# GridSeed.net
KiCad netlist of a schematic drawn in Altium Designer
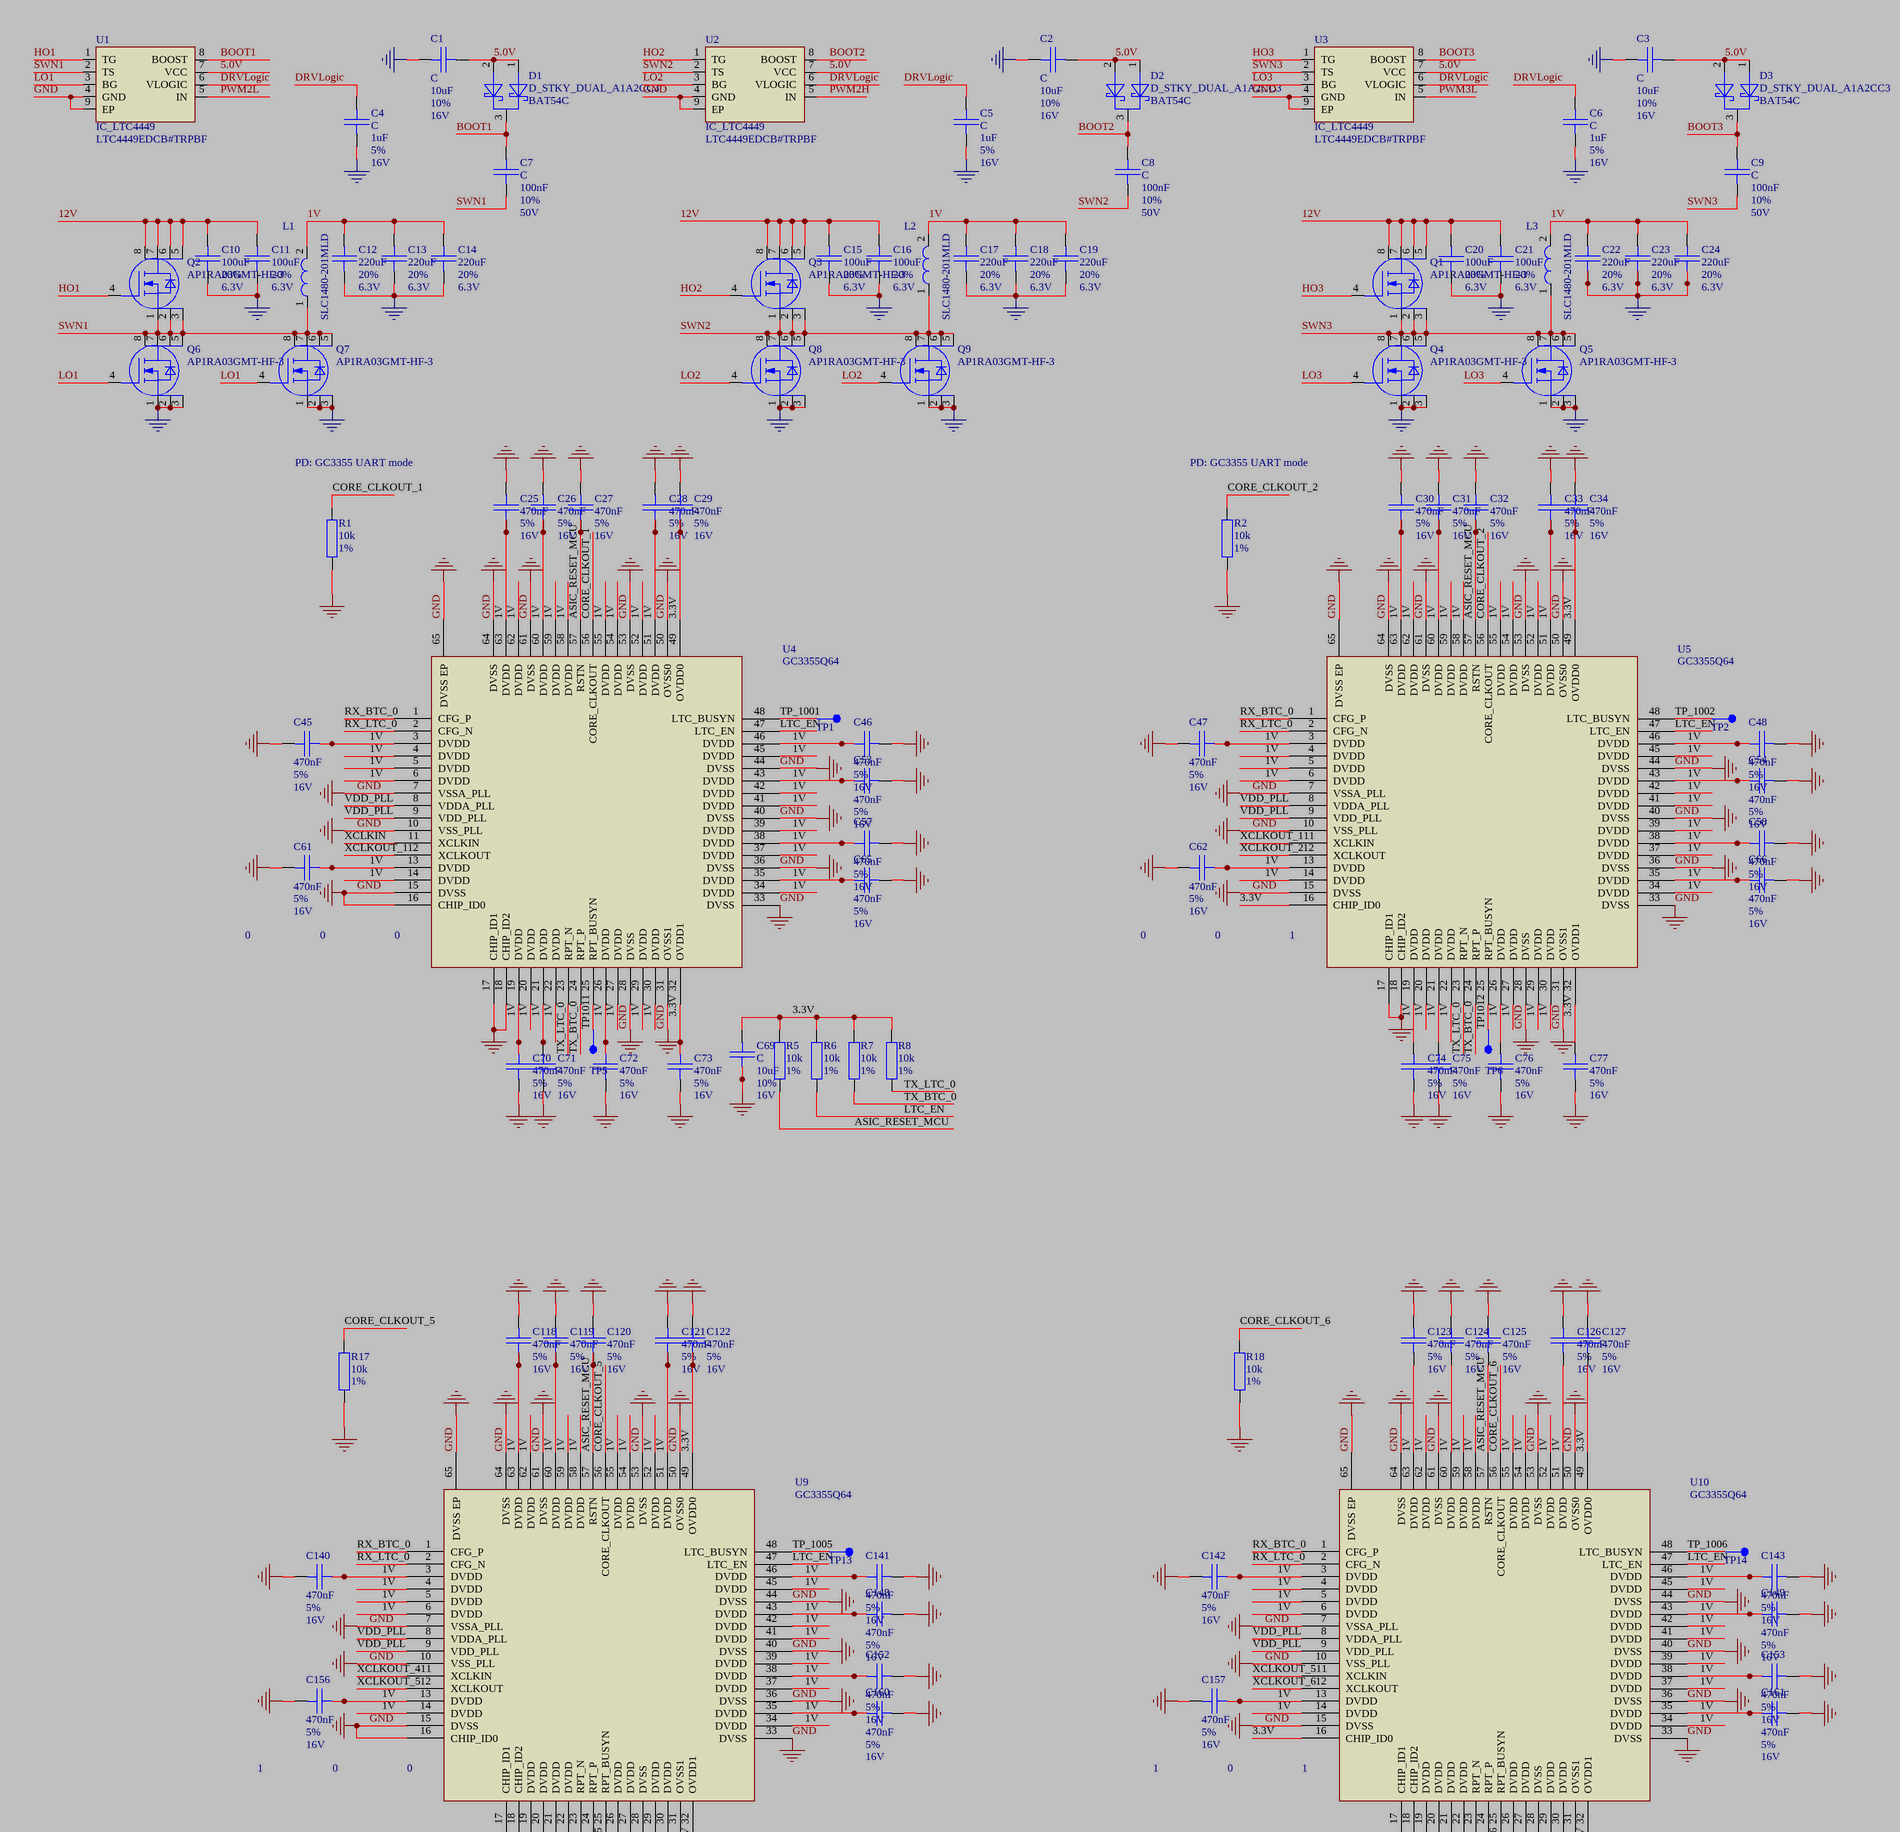
[diagram p0: GridSeed.SchDoc, top left]
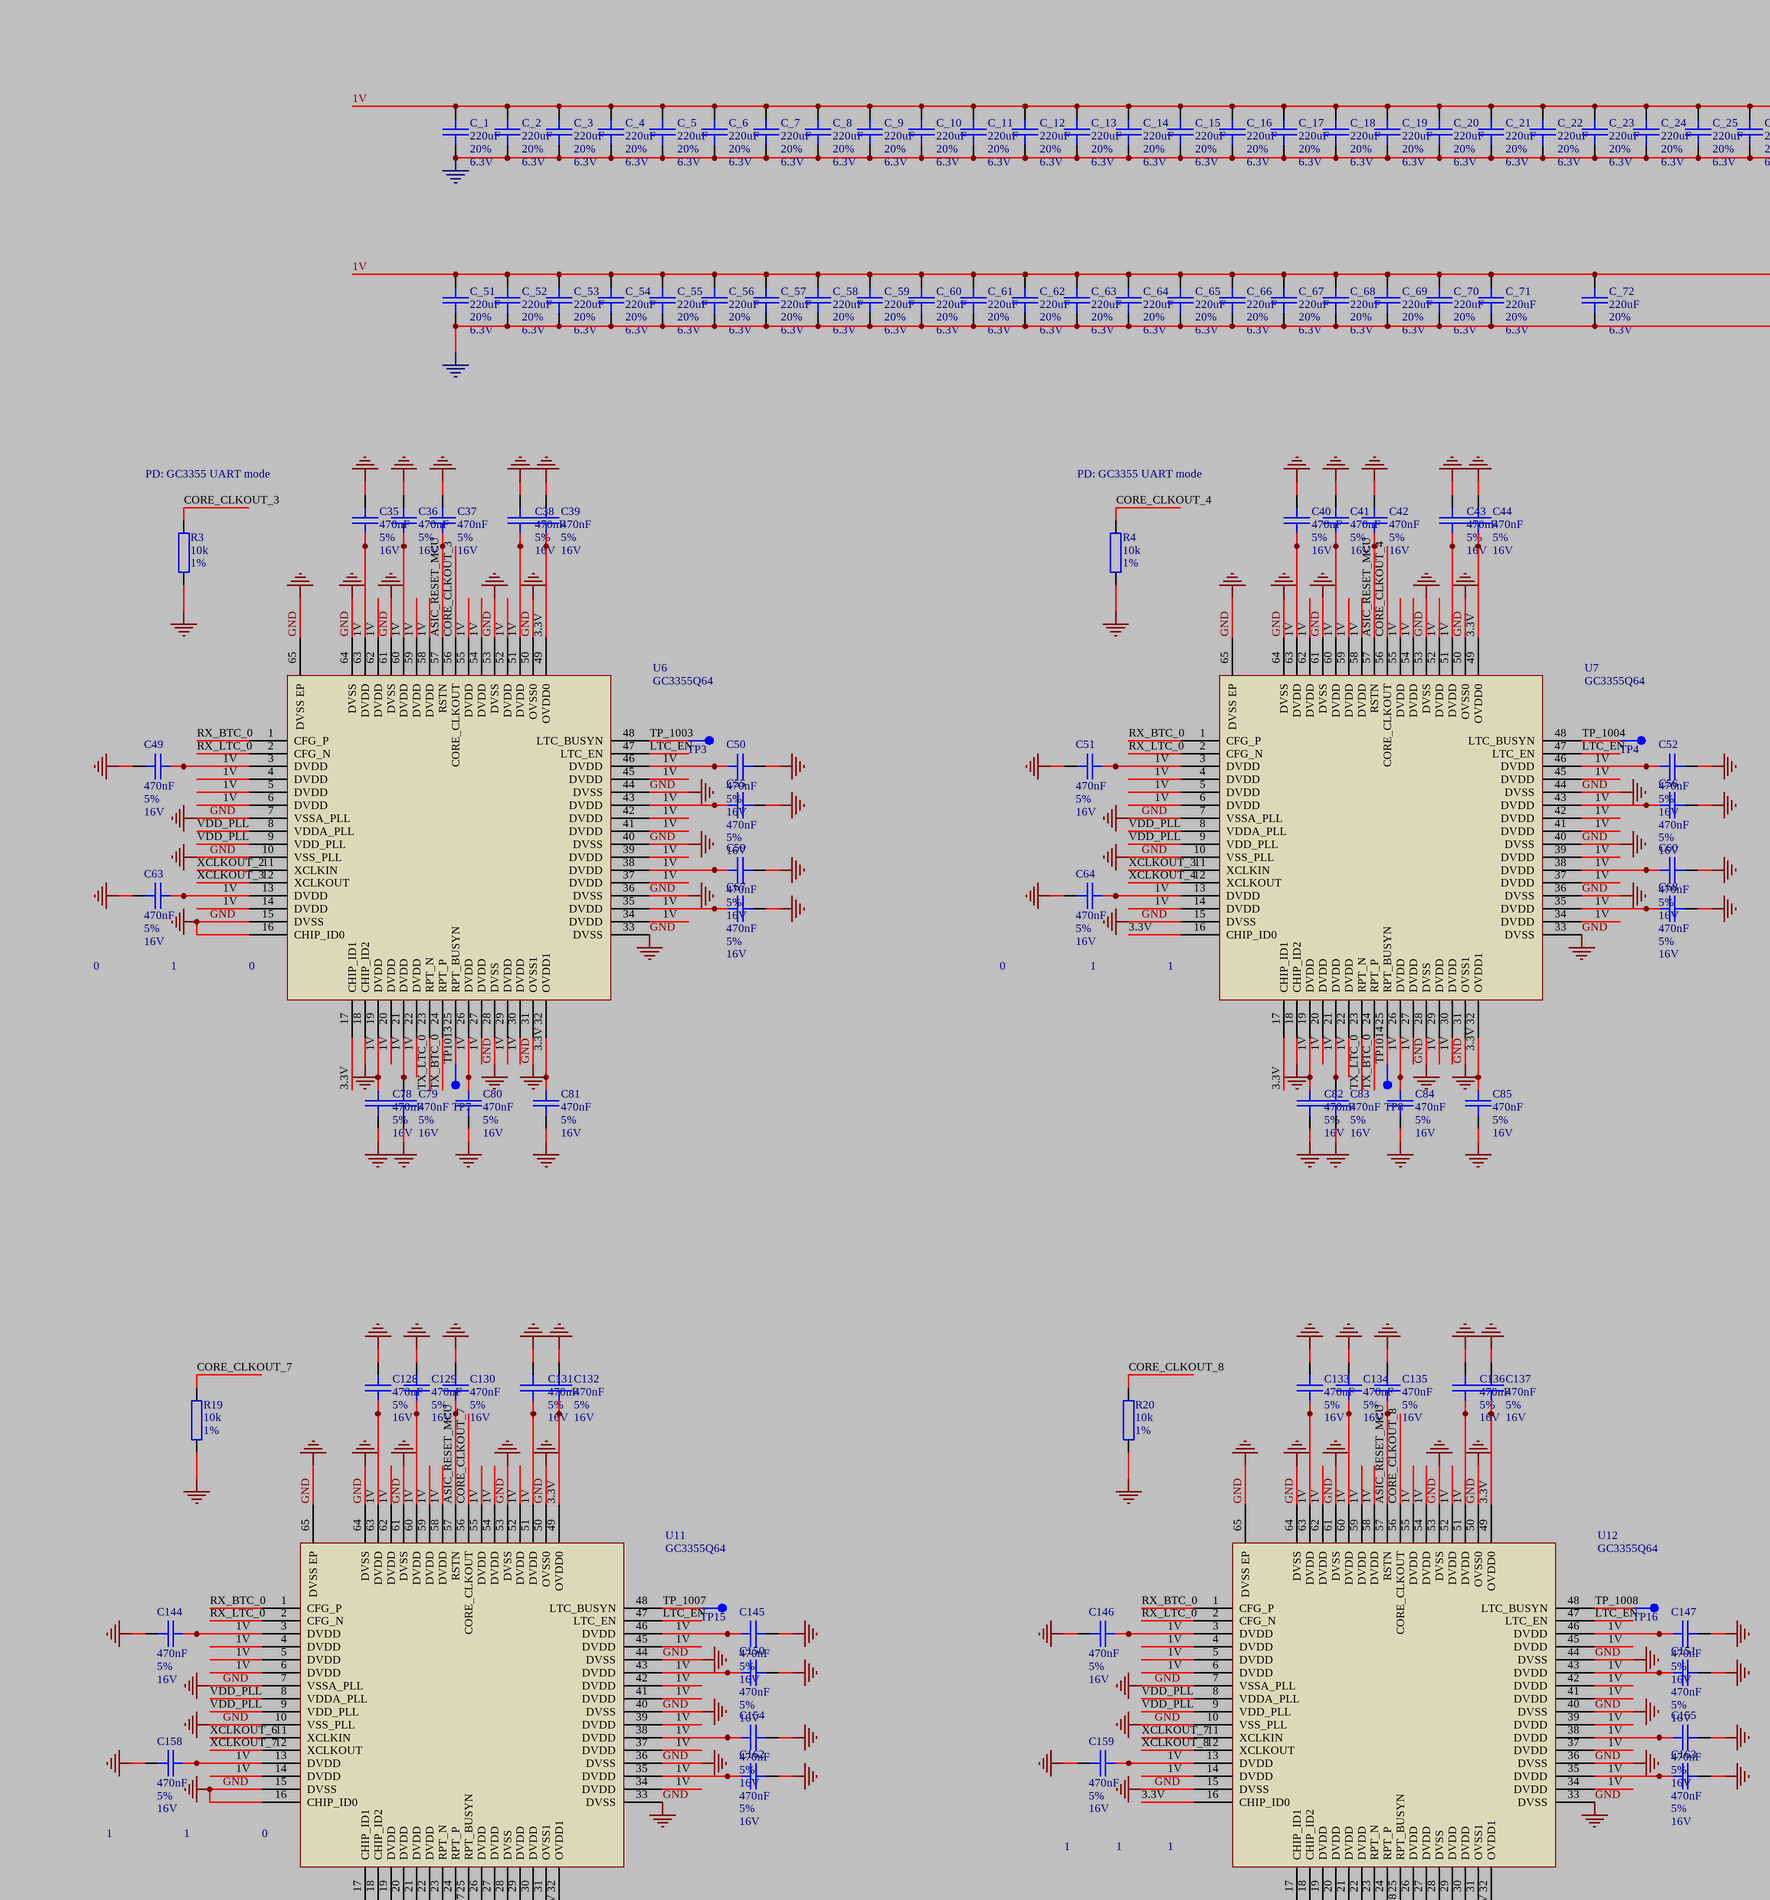
[diagram p1: GridSeed.SchDoc, top middle]
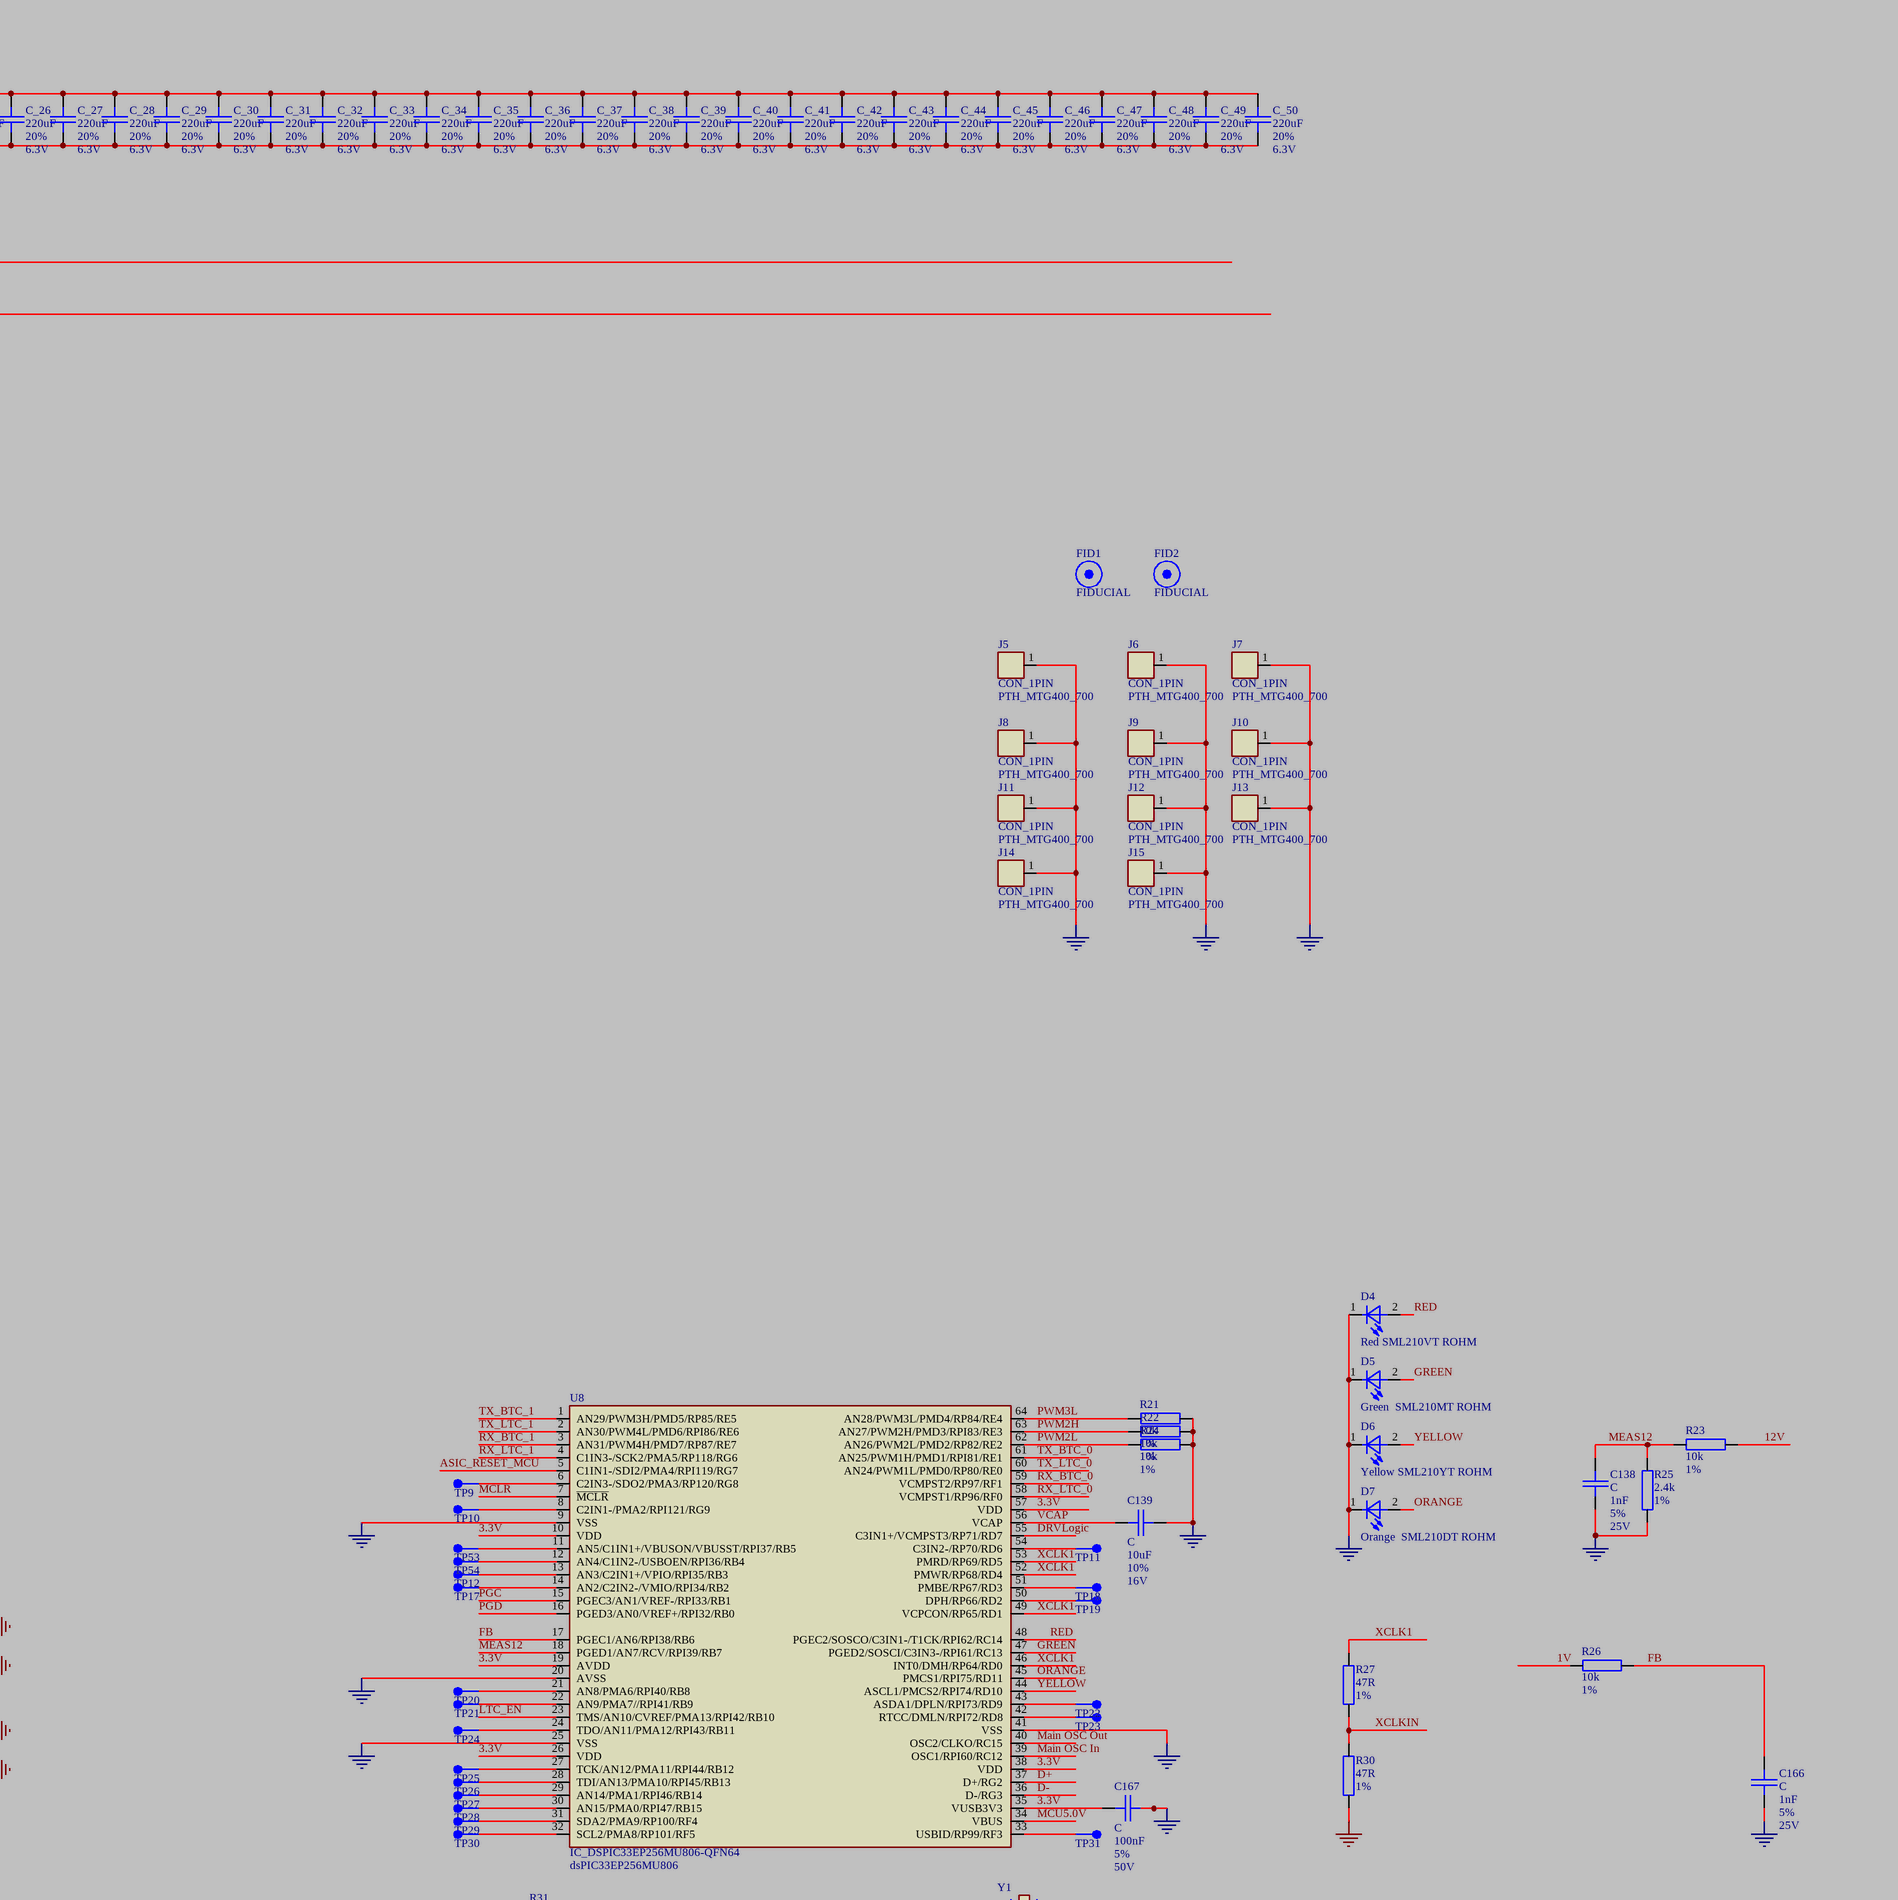
[diagram p2: GridSeed.SchDoc, top right]
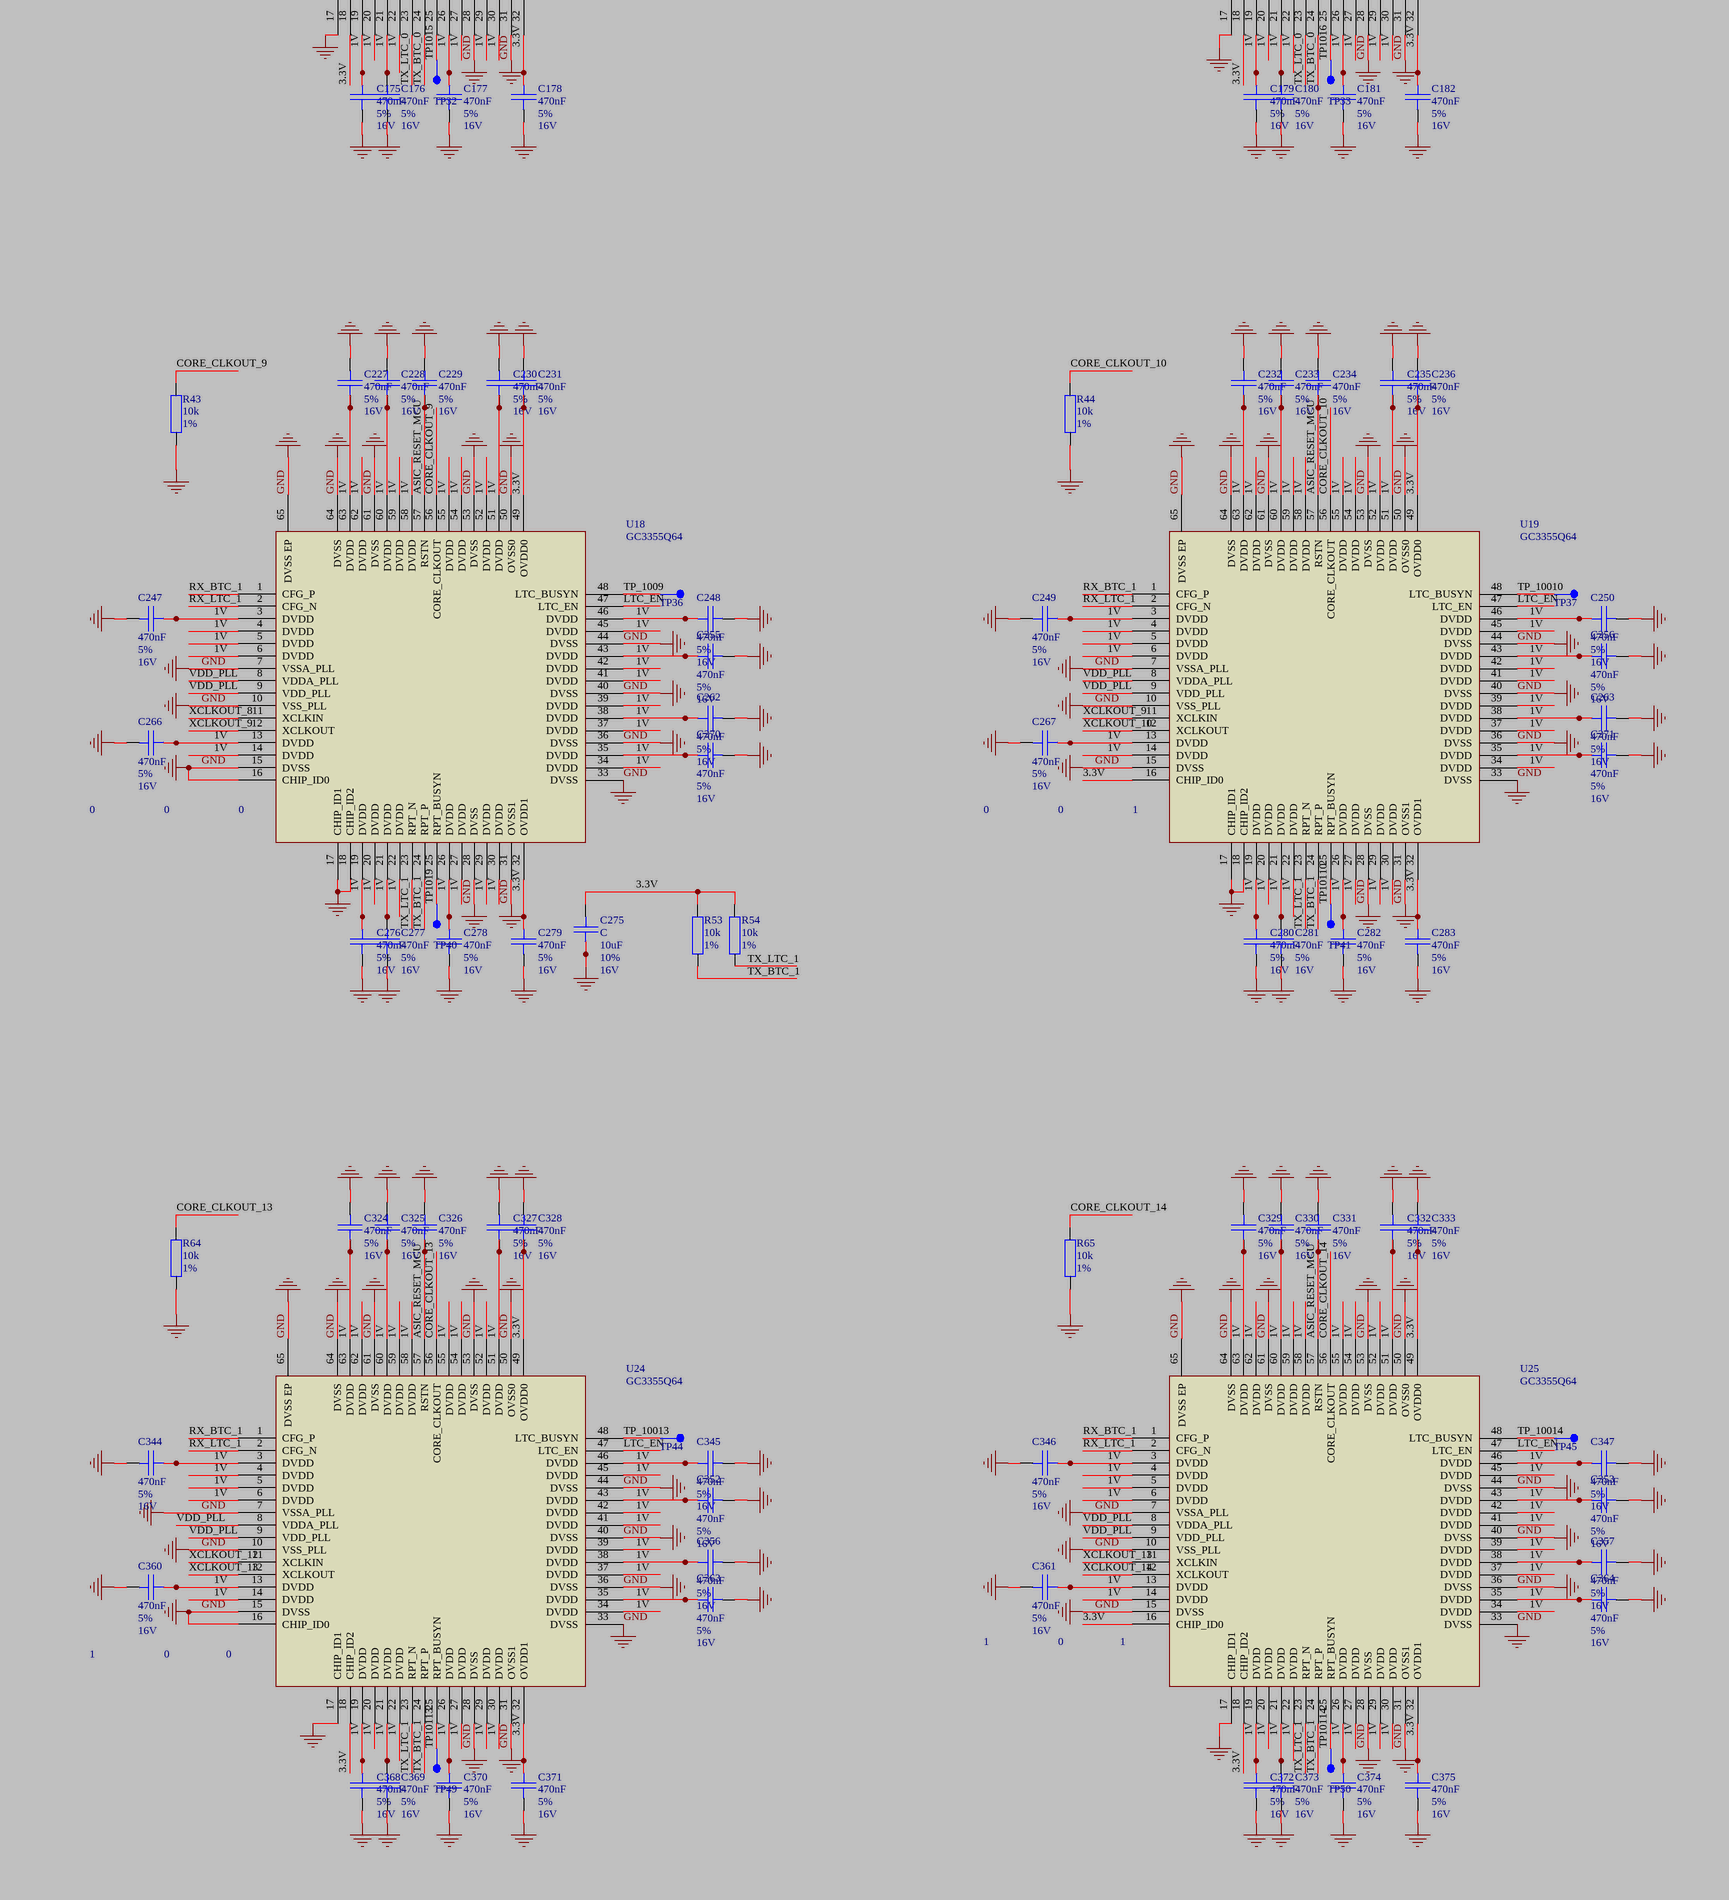
[diagram p3: GridSeed.SchDoc, bottom left]
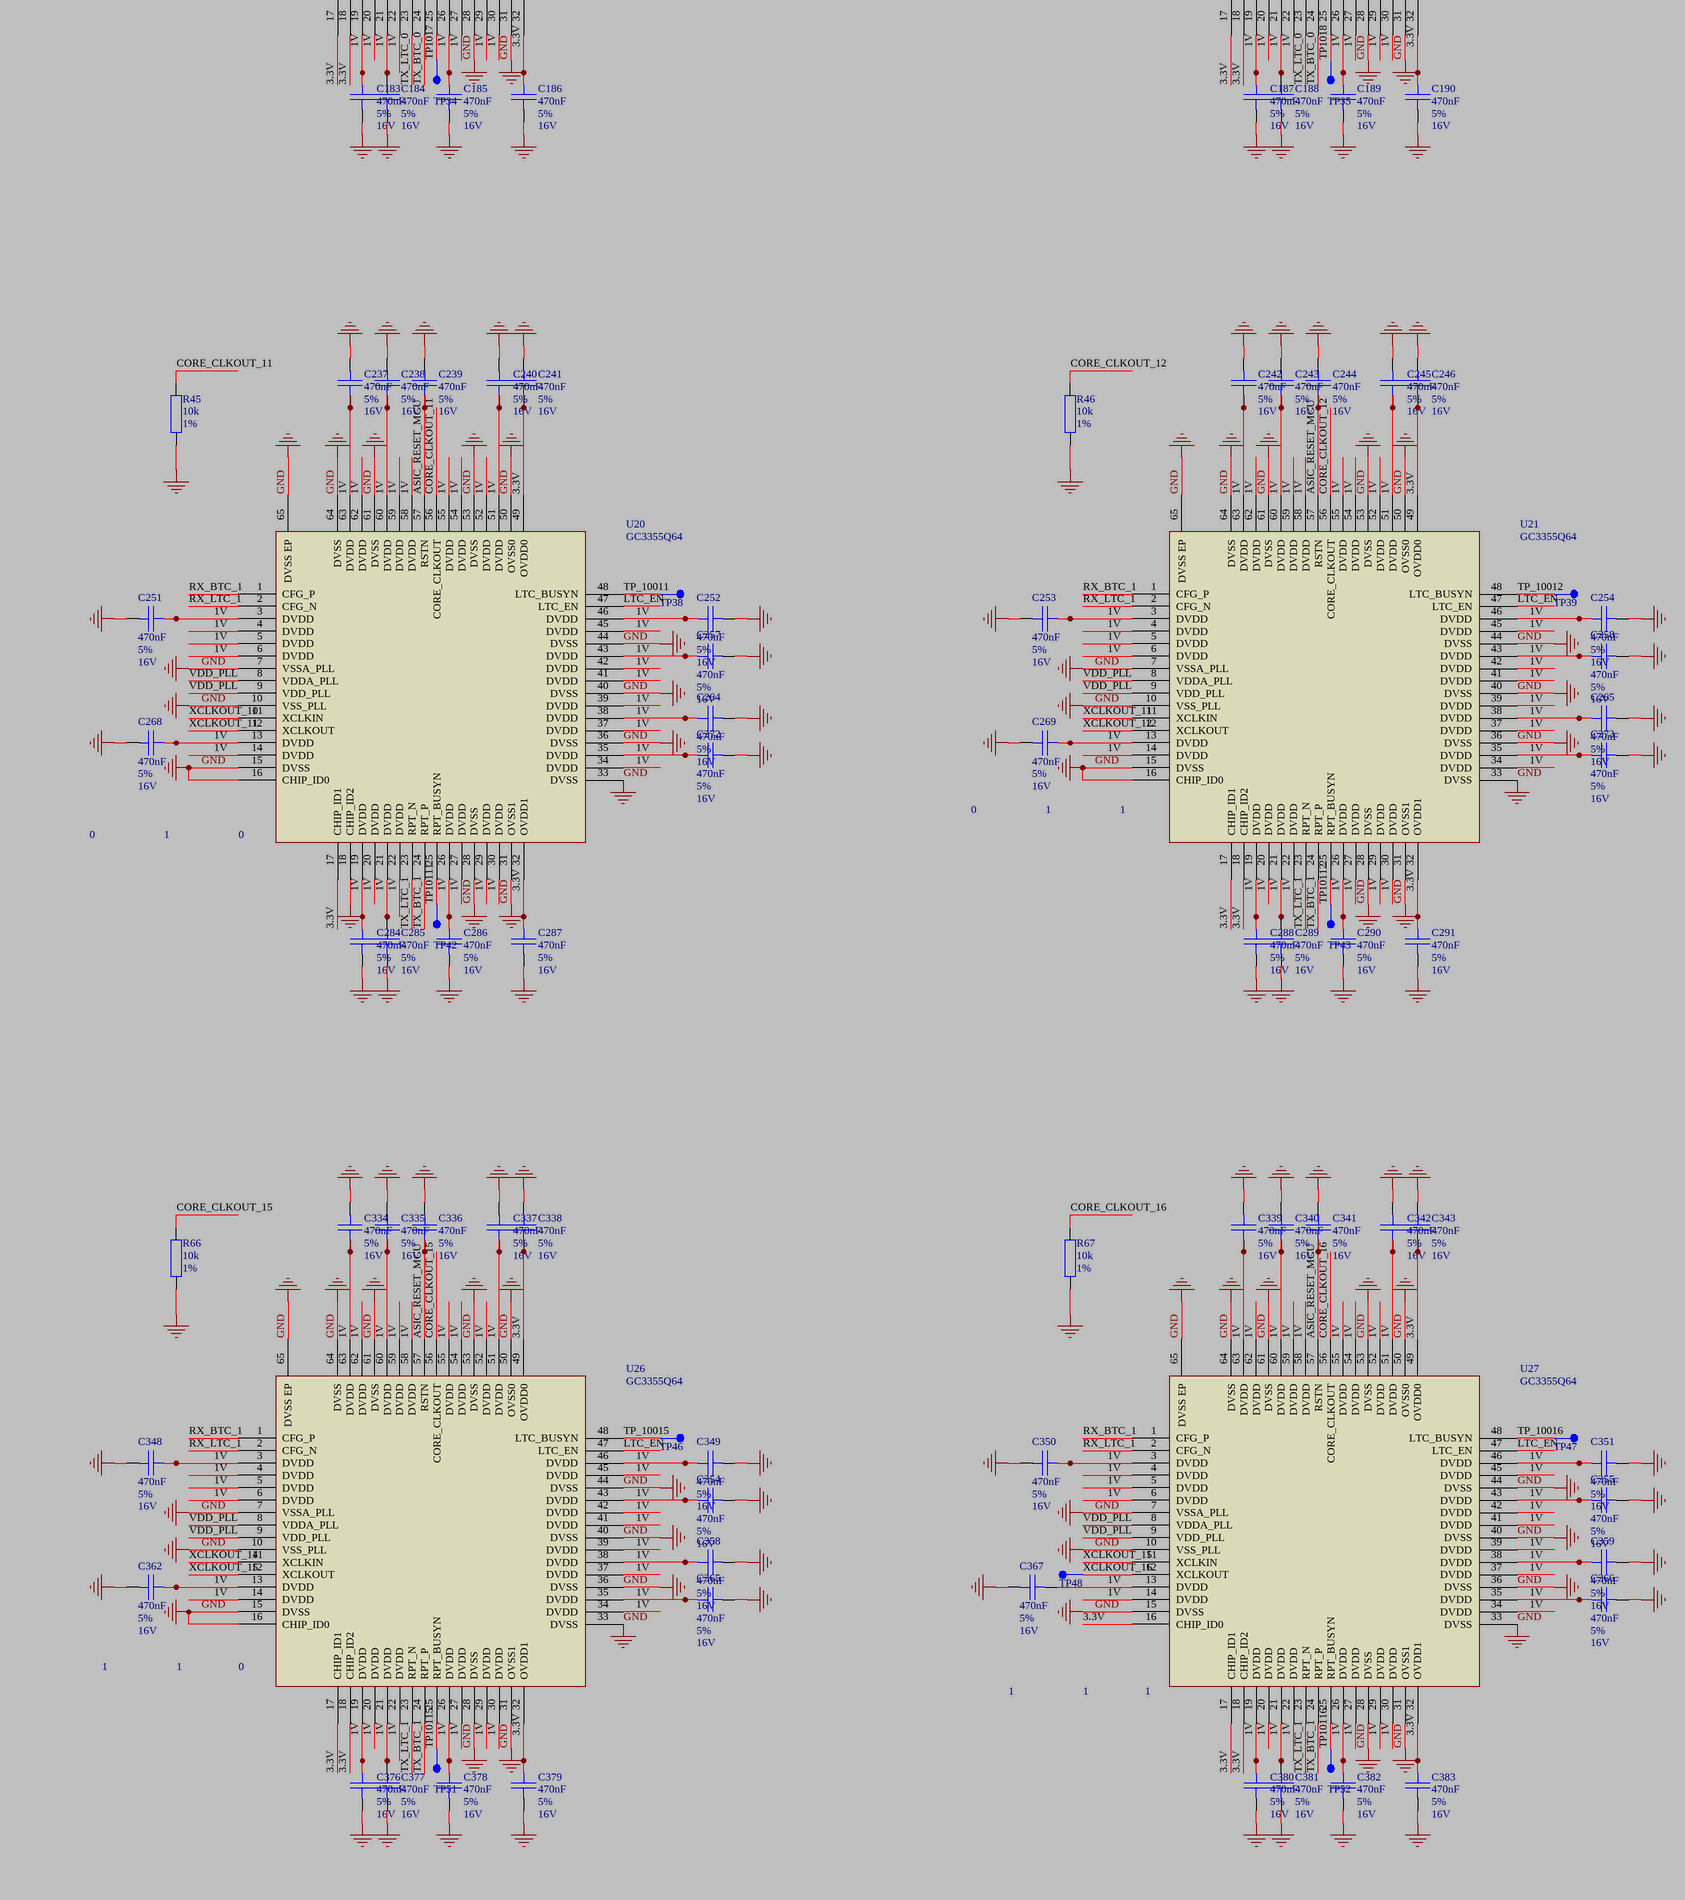
[diagram p4: GridSeed.SchDoc, bottom middle]
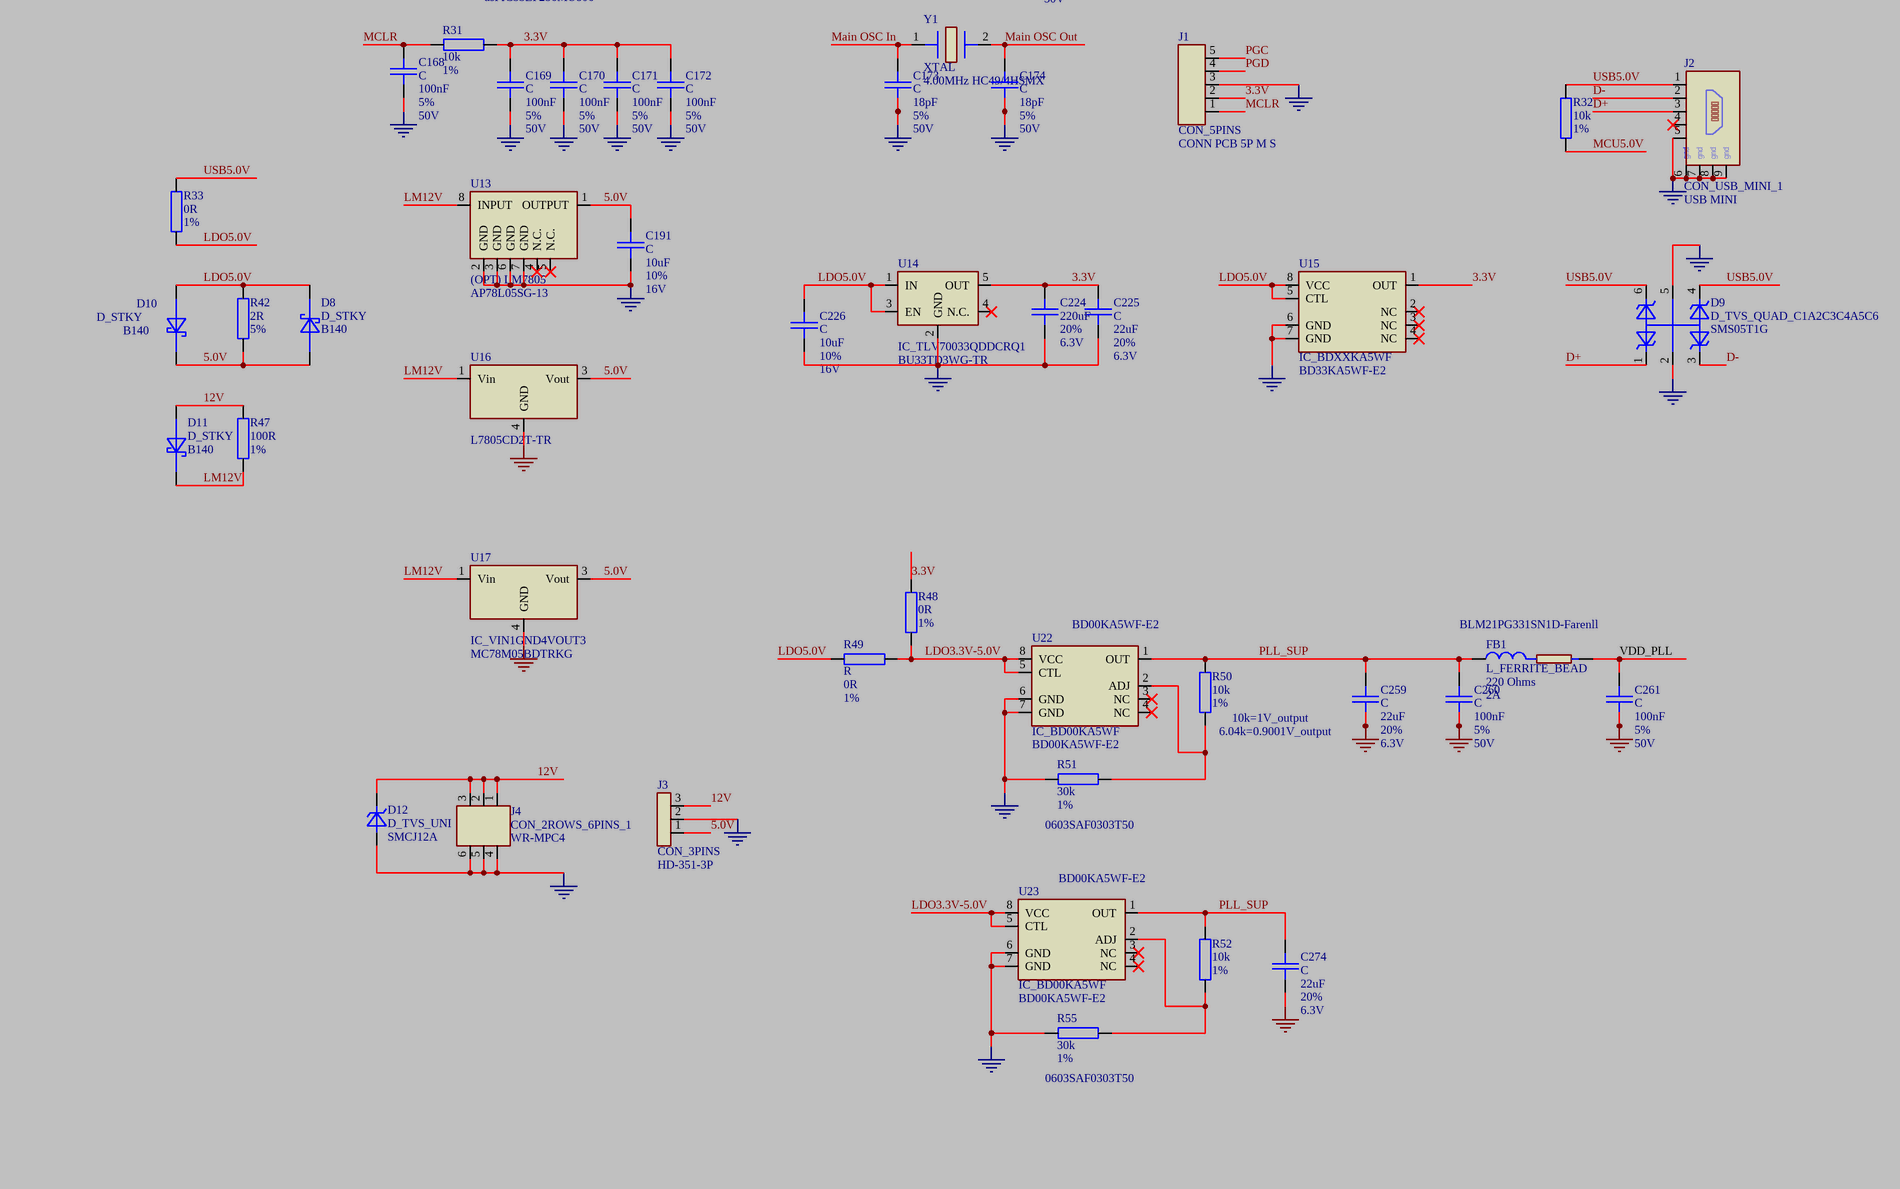
[diagram p5: GridSeed.SchDoc, bottom right]

(export (version "E")
  (design (tool "Eeschema 10.0.6"))
  (components
    (comp (ref "C1")
      (value "C")
      (footprint "SMD_0805_CAPC2012X145N")
      (fields
        (field (name "DB_PART_NUMBER") "CAP000043636")
        (field (name "DB_VALUE") "10uF")
        (field (name "DB_TOLERANCE") "10%")
        (field (name "DB_VOLTAGE") "16V")
        (field (name "DB_MANUFACTURER_PART") "KEMET    C0805C106K4PAC")
      )
      (libsource (lib "Database_Libs1") (part "C"))
    )
    (comp (ref "C2")
      (value "C")
      (footprint "SMD_0805_CAPC2012X145N")
      (fields
        (field (name "DB_PART_NUMBER") "CAP000043636")
        (field (name "DB_VALUE") "10uF")
        (field (name "DB_TOLERANCE") "10%")
        (field (name "DB_VOLTAGE") "16V")
        (field (name "DB_MANUFACTURER_PART") "KEMET    C0805C106K4PAC")
      )
      (libsource (lib "Database_Libs1") (part "C"))
    )
    (comp (ref "C3")
      (value "C")
      (footprint "SMD_0805_CAPC2012X145N")
      (fields
        (field (name "DB_PART_NUMBER") "CAP000043636")
        (field (name "DB_VALUE") "10uF")
        (field (name "DB_TOLERANCE") "10%")
        (field (name "DB_VOLTAGE") "16V")
        (field (name "DB_MANUFACTURER_PART") "KEMET    C0805C106K4PAC")
      )
      (libsource (lib "Database_Libs1") (part "C"))
    )
    (comp (ref "C4")
      (value "C")
      (footprint "SMD_0805_CAPC2012X145N")
      (fields
        (field (name "DB_PART_NUMBER") "CAP000028589")
        (field (name "DB_VALUE") "1uF")
        (field (name "DB_TOLERANCE") "5%")
        (field (name "DB_VOLTAGE") "16V")
        (field (name "DB_MANUFACTURER_PART") "KEMET    C0805C105J4RAC")
      )
      (libsource (lib "Database_Libs1") (part "C"))
    )
    (comp (ref "C5")
      (value "C")
      (footprint "SMD_0805_CAPC2012X145N")
      (fields
        (field (name "DB_PART_NUMBER") "CAP000028589")
        (field (name "DB_VALUE") "1uF")
        (field (name "DB_TOLERANCE") "5%")
        (field (name "DB_VOLTAGE") "16V")
        (field (name "DB_MANUFACTURER_PART") "KEMET    C0805C105J4RAC")
      )
      (libsource (lib "Database_Libs1") (part "C"))
    )
    (comp (ref "C6")
      (value "C")
      (footprint "SMD_0805_CAPC2012X145N")
      (fields
        (field (name "DB_PART_NUMBER") "CAP000028589")
        (field (name "DB_VALUE") "1uF")
        (field (name "DB_TOLERANCE") "5%")
        (field (name "DB_VOLTAGE") "16V")
        (field (name "DB_MANUFACTURER_PART") "KEMET    C0805C105J4RAC")
      )
      (libsource (lib "Database_Libs1") (part "C"))
    )
    (comp (ref "C7")
      (value "C")
      (footprint "SMD_0805_CAPC2012X145N")
      (fields
        (field (name "DB_PART_NUMBER") "CAP000027193")
        (field (name "DB_VALUE") "100nF")
        (field (name "DB_TOLERANCE") "10%")
        (field (name "DB_VOLTAGE") "50V")
        (field (name "DB_MANUFACTURER_PART") "KEMET    C0805C104K5RAC")
      )
      (libsource (lib "Database_Libs1") (part "C"))
    )
    (comp (ref "C8")
      (value "C")
      (footprint "SMD_0805_CAPC2012X145N")
      (fields
        (field (name "DB_PART_NUMBER") "CAP000027193")
        (field (name "DB_VALUE") "100nF")
        (field (name "DB_TOLERANCE") "10%")
        (field (name "DB_VOLTAGE") "50V")
        (field (name "DB_MANUFACTURER_PART") "KEMET    C0805C104K5RAC")
      )
      (libsource (lib "Database_Libs1") (part "C"))
    )
    (comp (ref "C9")
      (value "C")
      (footprint "SMD_0805_CAPC2012X145N")
      (fields
        (field (name "DB_PART_NUMBER") "CAP000027193")
        (field (name "DB_VALUE") "100nF")
        (field (name "DB_TOLERANCE") "10%")
        (field (name "DB_VOLTAGE") "50V")
        (field (name "DB_MANUFACTURER_PART") "KEMET    C0805C104K5RAC")
      )
      (libsource (lib "Database_Libs1") (part "C"))
    )
    (comp (ref "C10")
      (value "C")
      (footprint "SMD_1210_CAPC3225X270N")
      (fields
        (field (name "DB_PART_NUMBER") "CAP000043701")
        (field (name "DB_VALUE") "100uF")
        (field (name "DB_TOLERANCE") "20%")
        (field (name "DB_VOLTAGE") "6.3V")
        (field (name "DB_MANUFACTURER_PART") "KEMET    C1210C107M9PAC")
      )
      (libsource (lib "Database_Libs1") (part "C"))
    )
    (comp (ref "C11")
      (value "C")
      (footprint "SMD_1210_CAPC3225X270N")
      (fields
        (field (name "DB_PART_NUMBER") "CAP000043701")
        (field (name "DB_VALUE") "100uF")
        (field (name "DB_TOLERANCE") "20%")
        (field (name "DB_VOLTAGE") "6.3V")
        (field (name "DB_MANUFACTURER_PART") "KEMET    C1210C107M9PAC")
      )
      (libsource (lib "Database_Libs1") (part "C"))
    )
    (comp (ref "C12")
      (value "C")
      (footprint "SMD_1210_CAPC3225X279N")
      (fields
        (field (name "DB_PART_NUMBER") "CAP000047355")
        (field (name "DB_VALUE") "220uF")
        (field (name "DB_TOLERANCE") "20%")
        (field (name "DB_VOLTAGE") "6.3V")
        (field (name "DB_MANUFACTURER_PART") "SAMSUNG    CL32A227MQVNNNE")
        (field (name "DB_APPROVED_BY") "VSN")
      )
      (libsource (lib "Database_Libs1") (part "C"))
    )
    (comp (ref "C13")
      (value "C")
      (footprint "SMD_1210_CAPC3225X279N")
      (fields
        (field (name "DB_PART_NUMBER") "CAP000047355")
        (field (name "DB_VALUE") "220uF")
        (field (name "DB_TOLERANCE") "20%")
        (field (name "DB_VOLTAGE") "6.3V")
        (field (name "DB_MANUFACTURER_PART") "SAMSUNG    CL32A227MQVNNNE")
        (field (name "DB_APPROVED_BY") "VSN")
      )
      (libsource (lib "Database_Libs1") (part "C"))
    )
    (comp (ref "C14")
      (value "C")
      (footprint "SMD_1210_CAPC3225X279N")
      (fields
        (field (name "DB_PART_NUMBER") "CAP000047355")
        (field (name "DB_VALUE") "220uF")
        (field (name "DB_TOLERANCE") "20%")
        (field (name "DB_VOLTAGE") "6.3V")
        (field (name "DB_MANUFACTURER_PART") "SAMSUNG    CL32A227MQVNNNE")
        (field (name "DB_APPROVED_BY") "VSN")
      )
      (libsource (lib "Database_Libs1") (part "C"))
    )
    (comp (ref "C15")
      (value "C")
      (footprint "SMD_1210_CAPC3225X270N")
      (fields
        (field (name "DB_PART_NUMBER") "CAP000043701")
        (field (name "DB_VALUE") "100uF")
        (field (name "DB_TOLERANCE") "20%")
        (field (name "DB_VOLTAGE") "6.3V")
        (field (name "DB_MANUFACTURER_PART") "KEMET    C1210C107M9PAC")
      )
      (libsource (lib "Database_Libs1") (part "C"))
    )
    (comp (ref "C16")
      (value "C")
      (footprint "SMD_1210_CAPC3225X270N")
      (fields
        (field (name "DB_PART_NUMBER") "CAP000043701")
        (field (name "DB_VALUE") "100uF")
        (field (name "DB_TOLERANCE") "20%")
        (field (name "DB_VOLTAGE") "6.3V")
        (field (name "DB_MANUFACTURER_PART") "KEMET    C1210C107M9PAC")
      )
      (libsource (lib "Database_Libs1") (part "C"))
    )
    (comp (ref "C17")
      (value "C")
      (footprint "SMD_1210_CAPC3225X279N")
      (fields
        (field (name "DB_PART_NUMBER") "CAP000047355")
        (field (name "DB_VALUE") "220uF")
        (field (name "DB_TOLERANCE") "20%")
        (field (name "DB_VOLTAGE") "6.3V")
        (field (name "DB_MANUFACTURER_PART") "SAMSUNG    CL32A227MQVNNNE")
        (field (name "DB_APPROVED_BY") "VSN")
      )
      (libsource (lib "Database_Libs1") (part "C"))
    )
    (comp (ref "C18")
      (value "C")
      (footprint "SMD_1210_CAPC3225X279N")
      (fields
        (field (name "DB_PART_NUMBER") "CAP000047355")
        (field (name "DB_VALUE") "220uF")
        (field (name "DB_TOLERANCE") "20%")
        (field (name "DB_VOLTAGE") "6.3V")
        (field (name "DB_MANUFACTURER_PART") "SAMSUNG    CL32A227MQVNNNE")
        (field (name "DB_APPROVED_BY") "VSN")
      )
      (libsource (lib "Database_Libs1") (part "C"))
    )
    (comp (ref "C19")
      (value "C")
      (footprint "SMD_1210_CAPC3225X279N")
      (fields
        (field (name "DB_PART_NUMBER") "CAP000047355")
        (field (name "DB_VALUE") "220uF")
        (field (name "DB_TOLERANCE") "20%")
        (field (name "DB_VOLTAGE") "6.3V")
        (field (name "DB_MANUFACTURER_PART") "SAMSUNG    CL32A227MQVNNNE")
        (field (name "DB_APPROVED_BY") "VSN")
      )
      (libsource (lib "Database_Libs1") (part "C"))
    )
    (comp (ref "C20")
      (value "C")
      (footprint "SMD_1210_CAPC3225X270N")
      (fields
        (field (name "DB_PART_NUMBER") "CAP000043701")
        (field (name "DB_VALUE") "100uF")
        (field (name "DB_TOLERANCE") "20%")
        (field (name "DB_VOLTAGE") "6.3V")
        (field (name "DB_MANUFACTURER_PART") "KEMET    C1210C107M9PAC")
      )
      (libsource (lib "Database_Libs1") (part "C"))
    )
    (comp (ref "C21")
      (value "C")
      (footprint "SMD_1210_CAPC3225X270N")
      (fields
        (field (name "DB_PART_NUMBER") "CAP000043701")
        (field (name "DB_VALUE") "100uF")
        (field (name "DB_TOLERANCE") "20%")
        (field (name "DB_VOLTAGE") "6.3V")
        (field (name "DB_MANUFACTURER_PART") "KEMET    C1210C107M9PAC")
      )
      (libsource (lib "Database_Libs1") (part "C"))
    )
    (comp (ref "C22")
      (value "C")
      (footprint "SMD_1210_CAPC3225X279N")
      (fields
        (field (name "DB_PART_NUMBER") "CAP000047355")
        (field (name "DB_VALUE") "220uF")
        (field (name "DB_TOLERANCE") "20%")
        (field (name "DB_VOLTAGE") "6.3V")
        (field (name "DB_MANUFACTURER_PART") "SAMSUNG    CL32A227MQVNNNE")
        (field (name "DB_APPROVED_BY") "VSN")
      )
      (libsource (lib "Database_Libs1") (part "C"))
    )
    (comp (ref "C23")
      (value "C")
      (footprint "SMD_1210_CAPC3225X279N")
      (fields
        (field (name "DB_PART_NUMBER") "CAP000047355")
        (field (name "DB_VALUE") "220uF")
        (field (name "DB_TOLERANCE") "20%")
        (field (name "DB_VOLTAGE") "6.3V")
        (field (name "DB_MANUFACTURER_PART") "SAMSUNG    CL32A227MQVNNNE")
        (field (name "DB_APPROVED_BY") "VSN")
      )
      (libsource (lib "Database_Libs1") (part "C"))
    )
    (comp (ref "C24")
      (value "C")
      (footprint "SMD_1210_CAPC3225X279N")
      (fields
        (field (name "DB_PART_NUMBER") "CAP000047355")
        (field (name "DB_VALUE") "220uF")
        (field (name "DB_TOLERANCE") "20%")
        (field (name "DB_VOLTAGE") "6.3V")
        (field (name "DB_MANUFACTURER_PART") "SAMSUNG    CL32A227MQVNNNE")
        (field (name "DB_APPROVED_BY") "VSN")
      )
      (libsource (lib "Database_Libs1") (part "C"))
    )
    (comp (ref "C25")
      (value "C")
      (footprint "SMD_0603_CAPC1608X95N")
      (fields
        (field (name "DB_PART_NUMBER") "CAP000028169")
        (field (name "DB_VALUE") "470nF")
        (field (name "DB_TOLERANCE") "5%")
        (field (name "DB_VOLTAGE") "16V")
        (field (name "DB_MANUFACTURER_PART") "KEMET    C0603C474J4RAC")
      )
      (libsource (lib "Database_Libs1") (part "C"))
    )
    (comp (ref "C26")
      (value "C")
      (footprint "SMD_0603_CAPC1608X95N")
      (fields
        (field (name "DB_PART_NUMBER") "CAP000028169")
        (field (name "DB_VALUE") "470nF")
        (field (name "DB_TOLERANCE") "5%")
        (field (name "DB_VOLTAGE") "16V")
        (field (name "DB_MANUFACTURER_PART") "KEMET    C0603C474J4RAC")
      )
      (libsource (lib "Database_Libs1") (part "C"))
    )
    (comp (ref "C27")
      (value "C")
      (footprint "SMD_0603_CAPC1608X95N")
      (fields
        (field (name "DB_PART_NUMBER") "CAP000028169")
        (field (name "DB_VALUE") "470nF")
        (field (name "DB_TOLERANCE") "5%")
        (field (name "DB_VOLTAGE") "16V")
        (field (name "DB_MANUFACTURER_PART") "KEMET    C0603C474J4RAC")
      )
      (libsource (lib "Database_Libs1") (part "C"))
    )
    (comp (ref "C28")
      (value "C")
      (footprint "SMD_0603_CAPC1608X95N")
      (fields
        (field (name "DB_PART_NUMBER") "CAP000028169")
        (field (name "DB_VALUE") "470nF")
        (field (name "DB_TOLERANCE") "5%")
        (field (name "DB_VOLTAGE") "16V")
        (field (name "DB_MANUFACTURER_PART") "KEMET    C0603C474J4RAC")
      )
      (libsource (lib "Database_Libs1") (part "C"))
    )
    (comp (ref "C29")
      (value "C")
      (footprint "SMD_0603_CAPC1608X95N")
      (fields
        (field (name "DB_PART_NUMBER") "CAP000028169")
        (field (name "DB_VALUE") "470nF")
        (field (name "DB_TOLERANCE") "5%")
        (field (name "DB_VOLTAGE") "16V")
        (field (name "DB_MANUFACTURER_PART") "KEMET    C0603C474J4RAC")
      )
      (libsource (lib "Database_Libs1") (part "C"))
    )
    (comp (ref "C30")
      (value "C")
      (footprint "SMD_0603_CAPC1608X95N")
      (fields
        (field (name "DB_PART_NUMBER") "CAP000028169")
        (field (name "DB_VALUE") "470nF")
        (field (name "DB_TOLERANCE") "5%")
        (field (name "DB_VOLTAGE") "16V")
        (field (name "DB_MANUFACTURER_PART") "KEMET    C0603C474J4RAC")
      )
      (libsource (lib "Database_Libs1") (part "C"))
    )
    (comp (ref "C31")
      (value "C")
      (footprint "SMD_0603_CAPC1608X95N")
      (fields
        (field (name "DB_PART_NUMBER") "CAP000028169")
        (field (name "DB_VALUE") "470nF")
        (field (name "DB_TOLERANCE") "5%")
        (field (name "DB_VOLTAGE") "16V")
        (field (name "DB_MANUFACTURER_PART") "KEMET    C0603C474J4RAC")
      )
      (libsource (lib "Database_Libs1") (part "C"))
    )
    (comp (ref "C32")
      (value "C")
      (footprint "SMD_0603_CAPC1608X95N")
      (fields
        (field (name "DB_PART_NUMBER") "CAP000028169")
        (field (name "DB_VALUE") "470nF")
        (field (name "DB_TOLERANCE") "5%")
        (field (name "DB_VOLTAGE") "16V")
        (field (name "DB_MANUFACTURER_PART") "KEMET    C0603C474J4RAC")
      )
      (libsource (lib "Database_Libs1") (part "C"))
    )
    (comp (ref "C33")
      (value "C")
      (footprint "SMD_0603_CAPC1608X95N")
      (fields
        (field (name "DB_PART_NUMBER") "CAP000028169")
        (field (name "DB_VALUE") "470nF")
        (field (name "DB_TOLERANCE") "5%")
        (field (name "DB_VOLTAGE") "16V")
        (field (name "DB_MANUFACTURER_PART") "KEMET    C0603C474J4RAC")
      )
      (libsource (lib "Database_Libs1") (part "C"))
    )
    (comp (ref "C34")
      (value "C")
      (footprint "SMD_0603_CAPC1608X95N")
      (fields
        (field (name "DB_PART_NUMBER") "CAP000028169")
        (field (name "DB_VALUE") "470nF")
        (field (name "DB_TOLERANCE") "5%")
        (field (name "DB_VOLTAGE") "16V")
        (field (name "DB_MANUFACTURER_PART") "KEMET    C0603C474J4RAC")
      )
      (libsource (lib "Database_Libs1") (part "C"))
    )
    (comp (ref "C35")
      (value "C")
      (footprint "SMD_0603_CAPC1608X95N")
      (fields
        (field (name "DB_PART_NUMBER") "CAP000028169")
        (field (name "DB_VALUE") "470nF")
        (field (name "DB_TOLERANCE") "5%")
        (field (name "DB_VOLTAGE") "16V")
        (field (name "DB_MANUFACTURER_PART") "KEMET    C0603C474J4RAC")
      )
      (libsource (lib "Database_Libs1") (part "C"))
    )
    (comp (ref "C36")
      (value "C")
      (footprint "SMD_0603_CAPC1608X95N")
      (fields
        (field (name "DB_PART_NUMBER") "CAP000028169")
        (field (name "DB_VALUE") "470nF")
        (field (name "DB_TOLERANCE") "5%")
        (field (name "DB_VOLTAGE") "16V")
        (field (name "DB_MANUFACTURER_PART") "KEMET    C0603C474J4RAC")
      )
      (libsource (lib "Database_Libs1") (part "C"))
    )
    (comp (ref "C37")
      (value "C")
      (footprint "SMD_0603_CAPC1608X95N")
      (fields
        (field (name "DB_PART_NUMBER") "CAP000028169")
        (field (name "DB_VALUE") "470nF")
        (field (name "DB_TOLERANCE") "5%")
        (field (name "DB_VOLTAGE") "16V")
        (field (name "DB_MANUFACTURER_PART") "KEMET    C0603C474J4RAC")
      )
      (libsource (lib "Database_Libs1") (part "C"))
    )
    (comp (ref "C38")
      (value "C")
      (footprint "SMD_0603_CAPC1608X95N")
      (fields
        (field (name "DB_PART_NUMBER") "CAP000028169")
        (field (name "DB_VALUE") "470nF")
        (field (name "DB_TOLERANCE") "5%")
        (field (name "DB_VOLTAGE") "16V")
        (field (name "DB_MANUFACTURER_PART") "KEMET    C0603C474J4RAC")
      )
      (libsource (lib "Database_Libs1") (part "C"))
    )
    (comp (ref "C39")
      (value "C")
      (footprint "SMD_0603_CAPC1608X95N")
      (fields
        (field (name "DB_PART_NUMBER") "CAP000028169")
        (field (name "DB_VALUE") "470nF")
        (field (name "DB_TOLERANCE") "5%")
        (field (name "DB_VOLTAGE") "16V")
        (field (name "DB_MANUFACTURER_PART") "KEMET    C0603C474J4RAC")
      )
      (libsource (lib "Database_Libs1") (part "C"))
    )
    (comp (ref "C40")
      (value "C")
      (footprint "SMD_0603_CAPC1608X95N")
      (fields
        (field (name "DB_PART_NUMBER") "CAP000028169")
        (field (name "DB_VALUE") "470nF")
        (field (name "DB_TOLERANCE") "5%")
        (field (name "DB_VOLTAGE") "16V")
        (field (name "DB_MANUFACTURER_PART") "KEMET    C0603C474J4RAC")
      )
      (libsource (lib "Database_Libs1") (part "C"))
    )
    (comp (ref "C41")
      (value "C")
      (footprint "SMD_0603_CAPC1608X95N")
      (fields
        (field (name "DB_PART_NUMBER") "CAP000028169")
        (field (name "DB_VALUE") "470nF")
        (field (name "DB_TOLERANCE") "5%")
        (field (name "DB_VOLTAGE") "16V")
        (field (name "DB_MANUFACTURER_PART") "KEMET    C0603C474J4RAC")
      )
      (libsource (lib "Database_Libs1") (part "C"))
    )
    (comp (ref "C42")
      (value "C")
      (footprint "SMD_0603_CAPC1608X95N")
      (fields
        (field (name "DB_PART_NUMBER") "CAP000028169")
        (field (name "DB_VALUE") "470nF")
        (field (name "DB_TOLERANCE") "5%")
        (field (name "DB_VOLTAGE") "16V")
        (field (name "DB_MANUFACTURER_PART") "KEMET    C0603C474J4RAC")
      )
      (libsource (lib "Database_Libs1") (part "C"))
    )
    (comp (ref "C43")
      (value "C")
      (footprint "SMD_0603_CAPC1608X95N")
      (fields
        (field (name "DB_PART_NUMBER") "CAP000028169")
        (field (name "DB_VALUE") "470nF")
        (field (name "DB_TOLERANCE") "5%")
        (field (name "DB_VOLTAGE") "16V")
        (field (name "DB_MANUFACTURER_PART") "KEMET    C0603C474J4RAC")
      )
      (libsource (lib "Database_Libs1") (part "C"))
    )
    (comp (ref "C44")
      (value "C")
      (footprint "SMD_0603_CAPC1608X95N")
      (fields
        (field (name "DB_PART_NUMBER") "CAP000028169")
        (field (name "DB_VALUE") "470nF")
        (field (name "DB_TOLERANCE") "5%")
        (field (name "DB_VOLTAGE") "16V")
        (field (name "DB_MANUFACTURER_PART") "KEMET    C0603C474J4RAC")
      )
      (libsource (lib "Database_Libs1") (part "C"))
    )
    (comp (ref "C45")
      (value "C")
      (footprint "SMD_0603_CAPC1608X95N")
      (fields
        (field (name "DB_PART_NUMBER") "CAP000028169")
        (field (name "DB_VALUE") "470nF")
        (field (name "DB_TOLERANCE") "5%")
        (field (name "DB_VOLTAGE") "16V")
        (field (name "DB_MANUFACTURER_PART") "KEMET    C0603C474J4RAC")
      )
      (libsource (lib "Database_Libs1") (part "C"))
    )
    (comp (ref "C46")
      (value "C")
      (footprint "SMD_0603_CAPC1608X95N")
      (fields
        (field (name "DB_PART_NUMBER") "CAP000028169")
        (field (name "DB_VALUE") "470nF")
        (field (name "DB_TOLERANCE") "5%")
        (field (name "DB_VOLTAGE") "16V")
        (field (name "DB_MANUFACTURER_PART") "KEMET    C0603C474J4RAC")
      )
      (libsource (lib "Database_Libs1") (part "C"))
    )
    (comp (ref "C47")
      (value "C")
      (footprint "SMD_0603_CAPC1608X95N")
      (fields
        (field (name "DB_PART_NUMBER") "CAP000028169")
        (field (name "DB_VALUE") "470nF")
        (field (name "DB_TOLERANCE") "5%")
        (field (name "DB_VOLTAGE") "16V")
        (field (name "DB_MANUFACTURER_PART") "KEMET    C0603C474J4RAC")
      )
      (libsource (lib "Database_Libs1") (part "C"))
    )
    (comp (ref "C48")
      (value "C")
      (footprint "SMD_0603_CAPC1608X95N")
      (fields
        (field (name "DB_PART_NUMBER") "CAP000028169")
        (field (name "DB_VALUE") "470nF")
        (field (name "DB_TOLERANCE") "5%")
        (field (name "DB_VOLTAGE") "16V")
        (field (name "DB_MANUFACTURER_PART") "KEMET    C0603C474J4RAC")
      )
      (libsource (lib "Database_Libs1") (part "C"))
    )
    (comp (ref "C49")
      (value "C")
      (footprint "SMD_0603_CAPC1608X95N")
      (fields
        (field (name "DB_PART_NUMBER") "CAP000028169")
        (field (name "DB_VALUE") "470nF")
        (field (name "DB_TOLERANCE") "5%")
        (field (name "DB_VOLTAGE") "16V")
        (field (name "DB_MANUFACTURER_PART") "KEMET    C0603C474J4RAC")
      )
      (libsource (lib "Database_Libs1") (part "C"))
    )
    (comp (ref "C50")
      (value "C")
      (footprint "SMD_0603_CAPC1608X95N")
      (fields
        (field (name "DB_PART_NUMBER") "CAP000028169")
        (field (name "DB_VALUE") "470nF")
        (field (name "DB_TOLERANCE") "5%")
        (field (name "DB_VOLTAGE") "16V")
        (field (name "DB_MANUFACTURER_PART") "KEMET    C0603C474J4RAC")
      )
      (libsource (lib "Database_Libs1") (part "C"))
    )
    (comp (ref "C51")
      (value "C")
      (footprint "SMD_0603_CAPC1608X95N")
      (fields
        (field (name "DB_PART_NUMBER") "CAP000028169")
        (field (name "DB_VALUE") "470nF")
        (field (name "DB_TOLERANCE") "5%")
        (field (name "DB_VOLTAGE") "16V")
        (field (name "DB_MANUFACTURER_PART") "KEMET    C0603C474J4RAC")
      )
      (libsource (lib "Database_Libs1") (part "C"))
    )
    (comp (ref "C52")
      (value "C")
      (footprint "SMD_0603_CAPC1608X95N")
      (fields
        (field (name "DB_PART_NUMBER") "CAP000028169")
        (field (name "DB_VALUE") "470nF")
        (field (name "DB_TOLERANCE") "5%")
        (field (name "DB_VOLTAGE") "16V")
        (field (name "DB_MANUFACTURER_PART") "KEMET    C0603C474J4RAC")
      )
      (libsource (lib "Database_Libs1") (part "C"))
    )
    (comp (ref "C53")
      (value "C")
      (footprint "SMD_0603_CAPC1608X95N")
      (fields
        (field (name "DB_PART_NUMBER") "CAP000028169")
        (field (name "DB_VALUE") "470nF")
        (field (name "DB_TOLERANCE") "5%")
        (field (name "DB_VOLTAGE") "16V")
        (field (name "DB_MANUFACTURER_PART") "KEMET    C0603C474J4RAC")
      )
      (libsource (lib "Database_Libs1") (part "C"))
    )
    (comp (ref "C54")
      (value "C")
      (footprint "SMD_0603_CAPC1608X95N")
      (fields
        (field (name "DB_PART_NUMBER") "CAP000028169")
        (field (name "DB_VALUE") "470nF")
        (field (name "DB_TOLERANCE") "5%")
        (field (name "DB_VOLTAGE") "16V")
        (field (name "DB_MANUFACTURER_PART") "KEMET    C0603C474J4RAC")
      )
      (libsource (lib "Database_Libs1") (part "C"))
    )
    (comp (ref "C55")
      (value "C")
      (footprint "SMD_0603_CAPC1608X95N")
      (fields
        (field (name "DB_PART_NUMBER") "CAP000028169")
        (field (name "DB_VALUE") "470nF")
        (field (name "DB_TOLERANCE") "5%")
        (field (name "DB_VOLTAGE") "16V")
        (field (name "DB_MANUFACTURER_PART") "KEMET    C0603C474J4RAC")
      )
      (libsource (lib "Database_Libs1") (part "C"))
    )
    (comp (ref "C56")
      (value "C")
      (footprint "SMD_0603_CAPC1608X95N")
      (fields
        (field (name "DB_PART_NUMBER") "CAP000028169")
        (field (name "DB_VALUE") "470nF")
        (field (name "DB_TOLERANCE") "5%")
        (field (name "DB_VOLTAGE") "16V")
        (field (name "DB_MANUFACTURER_PART") "KEMET    C0603C474J4RAC")
      )
      (libsource (lib "Database_Libs1") (part "C"))
    )
    (comp (ref "C57")
      (value "C")
      (footprint "SMD_0603_CAPC1608X95N")
      (fields
        (field (name "DB_PART_NUMBER") "CAP000028169")
        (field (name "DB_VALUE") "470nF")
        (field (name "DB_TOLERANCE") "5%")
        (field (name "DB_VOLTAGE") "16V")
        (field (name "DB_MANUFACTURER_PART") "KEMET    C0603C474J4RAC")
      )
      (libsource (lib "Database_Libs1") (part "C"))
    )
    (comp (ref "C58")
      (value "C")
      (footprint "SMD_0603_CAPC1608X95N")
      (fields
        (field (name "DB_PART_NUMBER") "CAP000028169")
        (field (name "DB_VALUE") "470nF")
        (field (name "DB_TOLERANCE") "5%")
        (field (name "DB_VOLTAGE") "16V")
        (field (name "DB_MANUFACTURER_PART") "KEMET    C0603C474J4RAC")
      )
      (libsource (lib "Database_Libs1") (part "C"))
    )
    (comp (ref "C59")
      (value "C")
      (footprint "SMD_0603_CAPC1608X95N")
      (fields
        (field (name "DB_PART_NUMBER") "CAP000028169")
        (field (name "DB_VALUE") "470nF")
        (field (name "DB_TOLERANCE") "5%")
        (field (name "DB_VOLTAGE") "16V")
        (field (name "DB_MANUFACTURER_PART") "KEMET    C0603C474J4RAC")
      )
      (libsource (lib "Database_Libs1") (part "C"))
    )
    (comp (ref "C60")
      (value "C")
      (footprint "SMD_0603_CAPC1608X95N")
      (fields
        (field (name "DB_PART_NUMBER") "CAP000028169")
        (field (name "DB_VALUE") "470nF")
        (field (name "DB_TOLERANCE") "5%")
        (field (name "DB_VOLTAGE") "16V")
        (field (name "DB_MANUFACTURER_PART") "KEMET    C0603C474J4RAC")
      )
      (libsource (lib "Database_Libs1") (part "C"))
    )
    (comp (ref "C61")
      (value "C")
      (footprint "SMD_0603_CAPC1608X95N")
      (fields
        (field (name "DB_PART_NUMBER") "CAP000028169")
        (field (name "DB_VALUE") "470nF")
        (field (name "DB_TOLERANCE") "5%")
        (field (name "DB_VOLTAGE") "16V")
        (field (name "DB_MANUFACTURER_PART") "KEMET    C0603C474J4RAC")
      )
      (libsource (lib "Database_Libs1") (part "C"))
    )
    (comp (ref "C62")
      (value "C")
      (footprint "SMD_0603_CAPC1608X95N")
      (fields
        (field (name "DB_PART_NUMBER") "CAP000028169")
        (field (name "DB_VALUE") "470nF")
        (field (name "DB_TOLERANCE") "5%")
        (field (name "DB_VOLTAGE") "16V")
        (field (name "DB_MANUFACTURER_PART") "KEMET    C0603C474J4RAC")
      )
      (libsource (lib "Database_Libs1") (part "C"))
    )
    (comp (ref "C63")
      (value "C")
      (footprint "SMD_0603_CAPC1608X95N")
      (fields
        (field (name "DB_PART_NUMBER") "CAP000028169")
        (field (name "DB_VALUE") "470nF")
        (field (name "DB_TOLERANCE") "5%")
        (field (name "DB_VOLTAGE") "16V")
        (field (name "DB_MANUFACTURER_PART") "KEMET    C0603C474J4RAC")
      )
      (libsource (lib "Database_Libs1") (part "C"))
    )
    (comp (ref "C64")
      (value "C")
      (footprint "SMD_0603_CAPC1608X95N")
      (fields
        (field (name "DB_PART_NUMBER") "CAP000028169")
        (field (name "DB_VALUE") "470nF")
        (field (name "DB_TOLERANCE") "5%")
        (field (name "DB_VOLTAGE") "16V")
        (field (name "DB_MANUFACTURER_PART") "KEMET    C0603C474J4RAC")
      )
      (libsource (lib "Database_Libs1") (part "C"))
    )
    (comp (ref "C65")
      (value "C")
      (footprint "SMD_0603_CAPC1608X95N")
      (fields
        (field (name "DB_PART_NUMBER") "CAP000028169")
        (field (name "DB_VALUE") "470nF")
        (field (name "DB_TOLERANCE") "5%")
        (field (name "DB_VOLTAGE") "16V")
        (field (name "DB_MANUFACTURER_PART") "KEMET    C0603C474J4RAC")
      )
      (libsource (lib "Database_Libs1") (part "C"))
    )
    (comp (ref "C66")
      (value "C")
      (footprint "SMD_0603_CAPC1608X95N")
      (fields
        (field (name "DB_PART_NUMBER") "CAP000028169")
        (field (name "DB_VALUE") "470nF")
        (field (name "DB_TOLERANCE") "5%")
        (field (name "DB_VOLTAGE") "16V")
        (field (name "DB_MANUFACTURER_PART") "KEMET    C0603C474J4RAC")
      )
      (libsource (lib "Database_Libs1") (part "C"))
    )
    (comp (ref "C67")
      (value "C")
      (footprint "SMD_0603_CAPC1608X95N")
      (fields
        (field (name "DB_PART_NUMBER") "CAP000028169")
        (field (name "DB_VALUE") "470nF")
        (field (name "DB_TOLERANCE") "5%")
        (field (name "DB_VOLTAGE") "16V")
        (field (name "DB_MANUFACTURER_PART") "KEMET    C0603C474J4RAC")
      )
      (libsource (lib "Database_Libs1") (part "C"))
    )
    (comp (ref "C68")
      (value "C")
      (footprint "SMD_0603_CAPC1608X95N")
      (fields
        (field (name "DB_PART_NUMBER") "CAP000028169")
        (field (name "DB_VALUE") "470nF")
        (field (name "DB_TOLERANCE") "5%")
        (field (name "DB_VOLTAGE") "16V")
        (field (name "DB_MANUFACTURER_PART") "KEMET    C0603C474J4RAC")
      )
      (libsource (lib "Database_Libs1") (part "C"))
    )
    (comp (ref "C69")
      (value "C")
      (footprint "SMD_0805_CAPC2012X145N")
      (fields
        (field (name "DB_PART_NUMBER") "CAP000043636")
        (field (name "DB_VALUE") "10uF")
        (field (name "DB_TOLERANCE") "10%")
        (field (name "DB_VOLTAGE") "16V")
        (field (name "DB_MANUFACTURER_PART") "KEMET    C0805C106K4PAC")
      )
      (libsource (lib "Database_Libs1") (part "C"))
    )
    (comp (ref "C70")
      (value "C")
      (footprint "SMD_0603_CAPC1608X95N")
      (fields
        (field (name "DB_PART_NUMBER") "CAP000028169")
        (field (name "DB_VALUE") "470nF")
        (field (name "DB_TOLERANCE") "5%")
        (field (name "DB_VOLTAGE") "16V")
        (field (name "DB_MANUFACTURER_PART") "KEMET    C0603C474J4RAC")
      )
      (libsource (lib "Database_Libs1") (part "C"))
    )
    (comp (ref "C71")
      (value "C")
      (footprint "SMD_0603_CAPC1608X95N")
      (fields
        (field (name "DB_PART_NUMBER") "CAP000028169")
        (field (name "DB_VALUE") "470nF")
        (field (name "DB_TOLERANCE") "5%")
        (field (name "DB_VOLTAGE") "16V")
        (field (name "DB_MANUFACTURER_PART") "KEMET    C0603C474J4RAC")
      )
      (libsource (lib "Database_Libs1") (part "C"))
    )
    (comp (ref "C72")
      (value "C")
      (footprint "SMD_0603_CAPC1608X95N")
      (fields
        (field (name "DB_PART_NUMBER") "CAP000028169")
        (field (name "DB_VALUE") "470nF")
        (field (name "DB_TOLERANCE") "5%")
        (field (name "DB_VOLTAGE") "16V")
        (field (name "DB_MANUFACTURER_PART") "KEMET    C0603C474J4RAC")
      )
      (libsource (lib "Database_Libs1") (part "C"))
    )
    (comp (ref "C73")
      (value "C")
      (footprint "SMD_0603_CAPC1608X95N")
      (fields
        (field (name "DB_PART_NUMBER") "CAP000028169")
        (field (name "DB_VALUE") "470nF")
        (field (name "DB_TOLERANCE") "5%")
        (field (name "DB_VOLTAGE") "16V")
        (field (name "DB_MANUFACTURER_PART") "KEMET    C0603C474J4RAC")
      )
      (libsource (lib "Database_Libs1") (part "C"))
    )
    (comp (ref "C74")
      (value "C")
      (footprint "SMD_0603_CAPC1608X95N")
      (fields
        (field (name "DB_PART_NUMBER") "CAP000028169")
        (field (name "DB_VALUE") "470nF")
        (field (name "DB_TOLERANCE") "5%")
        (field (name "DB_VOLTAGE") "16V")
        (field (name "DB_MANUFACTURER_PART") "KEMET    C0603C474J4RAC")
      )
      (libsource (lib "Database_Libs1") (part "C"))
    )
    (comp (ref "C75")
      (value "C")
      (footprint "SMD_0603_CAPC1608X95N")
      (fields
        (field (name "DB_PART_NUMBER") "CAP000028169")
        (field (name "DB_VALUE") "470nF")
        (field (name "DB_TOLERANCE") "5%")
        (field (name "DB_VOLTAGE") "16V")
        (field (name "DB_MANUFACTURER_PART") "KEMET    C0603C474J4RAC")
      )
      (libsource (lib "Database_Libs1") (part "C"))
    )
    (comp (ref "C76")
      (value "C")
      (footprint "SMD_0603_CAPC1608X95N")
      (fields
        (field (name "DB_PART_NUMBER") "CAP000028169")
        (field (name "DB_VALUE") "470nF")
        (field (name "DB_TOLERANCE") "5%")
        (field (name "DB_VOLTAGE") "16V")
        (field (name "DB_MANUFACTURER_PART") "KEMET    C0603C474J4RAC")
      )
      (libsource (lib "Database_Libs1") (part "C"))
    )
    (comp (ref "C77")
      (value "C")
      (footprint "SMD_0603_CAPC1608X95N")
      (fields
        (field (name "DB_PART_NUMBER") "CAP000028169")
        (field (name "DB_VALUE") "470nF")
        (field (name "DB_TOLERANCE") "5%")
        (field (name "DB_VOLTAGE") "16V")
        (field (name "DB_MANUFACTURER_PART") "KEMET    C0603C474J4RAC")
      )
      (libsource (lib "Database_Libs1") (part "C"))
    )
    (comp (ref "C78")
      (value "C")
      (footprint "SMD_0603_CAPC1608X95N")
      (fields
        (field (name "DB_PART_NUMBER") "CAP000028169")
        (field (name "DB_VALUE") "470nF")
        (field (name "DB_TOLERANCE") "5%")
        (field (name "DB_VOLTAGE") "16V")
        (field (name "DB_MANUFACTURER_PART") "KEMET    C0603C474J4RAC")
      )
      (libsource (lib "Database_Libs1") (part "C"))
    )
    (comp (ref "C79")
      (value "C")
      (footprint "SMD_0603_CAPC1608X95N")
      (fields
        (field (name "DB_PART_NUMBER") "CAP000028169")
        (field (name "DB_VALUE") "470nF")
        (field (name "DB_TOLERANCE") "5%")
        (field (name "DB_VOLTAGE") "16V")
        (field (name "DB_MANUFACTURER_PART") "KEMET    C0603C474J4RAC")
      )
      (libsource (lib "Database_Libs1") (part "C"))
    )
    (comp (ref "C80")
      (value "C")
      (footprint "SMD_0603_CAPC1608X95N")
      (fields
        (field (name "DB_PART_NUMBER") "CAP000028169")
        (field (name "DB_VALUE") "470nF")
        (field (name "DB_TOLERANCE") "5%")
        (field (name "DB_VOLTAGE") "16V")
        (field (name "DB_MANUFACTURER_PART") "KEMET    C0603C474J4RAC")
      )
      (libsource (lib "Database_Libs1") (part "C"))
    )
    (comp (ref "C81")
      (value "C")
      (footprint "SMD_0603_CAPC1608X95N")
      (fields
        (field (name "DB_PART_NUMBER") "CAP000028169")
        (field (name "DB_VALUE") "470nF")
        (field (name "DB_TOLERANCE") "5%")
        (field (name "DB_VOLTAGE") "16V")
        (field (name "DB_MANUFACTURER_PART") "KEMET    C0603C474J4RAC")
      )
      (libsource (lib "Database_Libs1") (part "C"))
    )
    (comp (ref "C82")
      (value "C")
      (footprint "SMD_0603_CAPC1608X95N")
      (fields
        (field (name "DB_PART_NUMBER") "CAP000028169")
        (field (name "DB_VALUE") "470nF")
        (field (name "DB_TOLERANCE") "5%")
        (field (name "DB_VOLTAGE") "16V")
        (field (name "DB_MANUFACTURER_PART") "KEMET    C0603C474J4RAC")
      )
      (libsource (lib "Database_Libs1") (part "C"))
    )
    (comp (ref "C83")
      (value "C")
      (footprint "SMD_0603_CAPC1608X95N")
      (fields
        (field (name "DB_PART_NUMBER") "CAP000028169")
        (field (name "DB_VALUE") "470nF")
        (field (name "DB_TOLERANCE") "5%")
        (field (name "DB_VOLTAGE") "16V")
        (field (name "DB_MANUFACTURER_PART") "KEMET    C0603C474J4RAC")
      )
      (libsource (lib "Database_Libs1") (part "C"))
    )
    (comp (ref "C84")
      (value "C")
      (footprint "SMD_0603_CAPC1608X95N")
      (fields
        (field (name "DB_PART_NUMBER") "CAP000028169")
        (field (name "DB_VALUE") "470nF")
        (field (name "DB_TOLERANCE") "5%")
        (field (name "DB_VOLTAGE") "16V")
        (field (name "DB_MANUFACTURER_PART") "KEMET    C0603C474J4RAC")
      )
      (libsource (lib "Database_Libs1") (part "C"))
    )
    (comp (ref "C85")
      (value "C")
      (footprint "SMD_0603_CAPC1608X95N")
      (fields
        (field (name "DB_PART_NUMBER") "CAP000028169")
        (field (name "DB_VALUE") "470nF")
        (field (name "DB_TOLERANCE") "5%")
        (field (name "DB_VOLTAGE") "16V")
        (field (name "DB_MANUFACTURER_PART") "KEMET    C0603C474J4RAC")
      )
      (libsource (lib "Database_Libs1") (part "C"))
    )
    (comp (ref "C118")
      (value "C")
      (footprint "SMD_0603_CAPC1608X95N")
      (fields
        (field (name "DB_PART_NUMBER") "CAP000028169")
        (field (name "DB_VALUE") "470nF")
        (field (name "DB_TOLERANCE") "5%")
        (field (name "DB_VOLTAGE") "16V")
        (field (name "DB_MANUFACTURER_PART") "KEMET    C0603C474J4RAC")
      )
      (libsource (lib "Database_Libs1") (part "C"))
    )
    (comp (ref "C119")
      (value "C")
      (footprint "SMD_0603_CAPC1608X95N")
      (fields
        (field (name "DB_PART_NUMBER") "CAP000028169")
        (field (name "DB_VALUE") "470nF")
        (field (name "DB_TOLERANCE") "5%")
        (field (name "DB_VOLTAGE") "16V")
        (field (name "DB_MANUFACTURER_PART") "KEMET    C0603C474J4RAC")
      )
      (libsource (lib "Database_Libs1") (part "C"))
    )
    (comp (ref "C120")
      (value "C")
      (footprint "SMD_0603_CAPC1608X95N")
      (fields
        (field (name "DB_PART_NUMBER") "CAP000028169")
        (field (name "DB_VALUE") "470nF")
        (field (name "DB_TOLERANCE") "5%")
        (field (name "DB_VOLTAGE") "16V")
        (field (name "DB_MANUFACTURER_PART") "KEMET    C0603C474J4RAC")
      )
      (libsource (lib "Database_Libs1") (part "C"))
    )
    (comp (ref "C121")
      (value "C")
      (footprint "SMD_0603_CAPC1608X95N")
      (fields
        (field (name "DB_PART_NUMBER") "CAP000028169")
        (field (name "DB_VALUE") "470nF")
        (field (name "DB_TOLERANCE") "5%")
        (field (name "DB_VOLTAGE") "16V")
        (field (name "DB_MANUFACTURER_PART") "KEMET    C0603C474J4RAC")
      )
      (libsource (lib "Database_Libs1") (part "C"))
    )
    (comp (ref "C122")
      (value "C")
      (footprint "SMD_0603_CAPC1608X95N")
      (fields
        (field (name "DB_PART_NUMBER") "CAP000028169")
        (field (name "DB_VALUE") "470nF")
        (field (name "DB_TOLERANCE") "5%")
        (field (name "DB_VOLTAGE") "16V")
        (field (name "DB_MANUFACTURER_PART") "KEMET    C0603C474J4RAC")
      )
      (libsource (lib "Database_Libs1") (part "C"))
    )
    (comp (ref "C123")
      (value "C")
      (footprint "SMD_0603_CAPC1608X95N")
      (fields
        (field (name "DB_PART_NUMBER") "CAP000028169")
        (field (name "DB_VALUE") "470nF")
        (field (name "DB_TOLERANCE") "5%")
        (field (name "DB_VOLTAGE") "16V")
        (field (name "DB_MANUFACTURER_PART") "KEMET    C0603C474J4RAC")
      )
      (libsource (lib "Database_Libs1") (part "C"))
    )
    (comp (ref "C124")
      (value "C")
      (footprint "SMD_0603_CAPC1608X95N")
      (fields
        (field (name "DB_PART_NUMBER") "CAP000028169")
        (field (name "DB_VALUE") "470nF")
        (field (name "DB_TOLERANCE") "5%")
        (field (name "DB_VOLTAGE") "16V")
        (field (name "DB_MANUFACTURER_PART") "KEMET    C0603C474J4RAC")
      )
      (libsource (lib "Database_Libs1") (part "C"))
    )
    (comp (ref "C125")
      (value "C")
      (footprint "SMD_0603_CAPC1608X95N")
      (fields
        (field (name "DB_PART_NUMBER") "CAP000028169")
        (field (name "DB_VALUE") "470nF")
        (field (name "DB_TOLERANCE") "5%")
        (field (name "DB_VOLTAGE") "16V")
        (field (name "DB_MANUFACTURER_PART") "KEMET    C0603C474J4RAC")
      )
      (libsource (lib "Database_Libs1") (part "C"))
    )
    (comp (ref "C126")
      (value "C")
      (footprint "SMD_0603_CAPC1608X95N")
      (fields
        (field (name "DB_PART_NUMBER") "CAP000028169")
        (field (name "DB_VALUE") "470nF")
        (field (name "DB_TOLERANCE") "5%")
        (field (name "DB_VOLTAGE") "16V")
        (field (name "DB_MANUFACTURER_PART") "KEMET    C0603C474J4RAC")
      )
      (libsource (lib "Database_Libs1") (part "C"))
    )
    (comp (ref "C127")
      (value "C")
      (footprint "SMD_0603_CAPC1608X95N")
      (fields
        (field (name "DB_PART_NUMBER") "CAP000028169")
        (field (name "DB_VALUE") "470nF")
        (field (name "DB_TOLERANCE") "5%")
        (field (name "DB_VOLTAGE") "16V")
        (field (name "DB_MANUFACTURER_PART") "KEMET    C0603C474J4RAC")
      )
      (libsource (lib "Database_Libs1") (part "C"))
    )
    (comp (ref "C128")
      (value "C")
      (footprint "SMD_0603_CAPC1608X95N")
      (fields
        (field (name "DB_PART_NUMBER") "CAP000028169")
        (field (name "DB_VALUE") "470nF")
        (field (name "DB_TOLERANCE") "5%")
        (field (name "DB_VOLTAGE") "16V")
        (field (name "DB_MANUFACTURER_PART") "KEMET    C0603C474J4RAC")
      )
      (libsource (lib "Database_Libs1") (part "C"))
    )
    (comp (ref "C129")
      (value "C")
      (footprint "SMD_0603_CAPC1608X95N")
      (fields
        (field (name "DB_PART_NUMBER") "CAP000028169")
        (field (name "DB_VALUE") "470nF")
        (field (name "DB_TOLERANCE") "5%")
        (field (name "DB_VOLTAGE") "16V")
        (field (name "DB_MANUFACTURER_PART") "KEMET    C0603C474J4RAC")
      )
      (libsource (lib "Database_Libs1") (part "C"))
    )
    (comp (ref "C130")
      (value "C")
      (footprint "SMD_0603_CAPC1608X95N")
      (fields
        (field (name "DB_PART_NUMBER") "CAP000028169")
        (field (name "DB_VALUE") "470nF")
        (field (name "DB_TOLERANCE") "5%")
        (field (name "DB_VOLTAGE") "16V")
        (field (name "DB_MANUFACTURER_PART") "KEMET    C0603C474J4RAC")
      )
      (libsource (lib "Database_Libs1") (part "C"))
    )
    (comp (ref "C131")
      (value "C")
      (footprint "SMD_0603_CAPC1608X95N")
      (fields
        (field (name "DB_PART_NUMBER") "CAP000028169")
        (field (name "DB_VALUE") "470nF")
        (field (name "DB_TOLERANCE") "5%")
        (field (name "DB_VOLTAGE") "16V")
        (field (name "DB_MANUFACTURER_PART") "KEMET    C0603C474J4RAC")
      )
      (libsource (lib "Database_Libs1") (part "C"))
    )
    (comp (ref "C132")
      (value "C")
      (footprint "SMD_0603_CAPC1608X95N")
      (fields
        (field (name "DB_PART_NUMBER") "CAP000028169")
        (field (name "DB_VALUE") "470nF")
        (field (name "DB_TOLERANCE") "5%")
        (field (name "DB_VOLTAGE") "16V")
        (field (name "DB_MANUFACTURER_PART") "KEMET    C0603C474J4RAC")
      )
      (libsource (lib "Database_Libs1") (part "C"))
    )
    (comp (ref "C133")
      (value "C")
      (footprint "SMD_0603_CAPC1608X95N")
      (fields
        (field (name "DB_PART_NUMBER") "CAP000028169")
        (field (name "DB_VALUE") "470nF")
        (field (name "DB_TOLERANCE") "5%")
        (field (name "DB_VOLTAGE") "16V")
        (field (name "DB_MANUFACTURER_PART") "KEMET    C0603C474J4RAC")
      )
      (libsource (lib "Database_Libs1") (part "C"))
    )
    (comp (ref "C134")
      (value "C")
      (footprint "SMD_0603_CAPC1608X95N")
      (fields
        (field (name "DB_PART_NUMBER") "CAP000028169")
        (field (name "DB_VALUE") "470nF")
        (field (name "DB_TOLERANCE") "5%")
        (field (name "DB_VOLTAGE") "16V")
        (field (name "DB_MANUFACTURER_PART") "KEMET    C0603C474J4RAC")
      )
      (libsource (lib "Database_Libs1") (part "C"))
    )
    (comp (ref "C135")
      (value "C")
      (footprint "SMD_0603_CAPC1608X95N")
      (fields
        (field (name "DB_PART_NUMBER") "CAP000028169")
        (field (name "DB_VALUE") "470nF")
        (field (name "DB_TOLERANCE") "5%")
        (field (name "DB_VOLTAGE") "16V")
        (field (name "DB_MANUFACTURER_PART") "KEMET    C0603C474J4RAC")
      )
      (libsource (lib "Database_Libs1") (part "C"))
    )
    (comp (ref "C136")
      (value "C")
      (footprint "SMD_0603_CAPC1608X95N")
      (fields
        (field (name "DB_PART_NUMBER") "CAP000028169")
        (field (name "DB_VALUE") "470nF")
        (field (name "DB_TOLERANCE") "5%")
        (field (name "DB_VOLTAGE") "16V")
        (field (name "DB_MANUFACTURER_PART") "KEMET    C0603C474J4RAC")
      )
      (libsource (lib "Database_Libs1") (part "C"))
    )
    (comp (ref "C137")
      (value "C")
      (footprint "SMD_0603_CAPC1608X95N")
      (fields
        (field (name "DB_PART_NUMBER") "CAP000028169")
        (field (name "DB_VALUE") "470nF")
        (field (name "DB_TOLERANCE") "5%")
        (field (name "DB_VOLTAGE") "16V")
        (field (name "DB_MANUFACTURER_PART") "KEMET    C0603C474J4RAC")
      )
      (libsource (lib "Database_Libs1") (part "C"))
    )
    (comp (ref "C138")
      (value "C")
      (footprint "SMD_0603_CAPC1608X95N")
      (fields
        (field (name "DB_PART_NUMBER") "CAP000024113")
        (field (name "DB_VALUE") "1nF")
        (field (name "DB_TOLERANCE") "5%")
        (field (name "DB_VOLTAGE") "25V")
        (field (name "DB_MANUFACTURER_PART") "KEMET    C0603C102J3RAC")
      )
      (libsource (lib "Database_Libs1") (part "C"))
    )
    (comp (ref "C139")
      (value "C")
      (footprint "SMD_0805_CAPC2012X145N")
      (fields
        (field (name "DB_PART_NUMBER") "CAP000043636")
        (field (name "DB_VALUE") "10uF")
        (field (name "DB_TOLERANCE") "10%")
        (field (name "DB_VOLTAGE") "16V")
        (field (name "DB_MANUFACTURER_PART") "KEMET    C0805C106K4PAC")
      )
      (libsource (lib "Database_Libs1") (part "C"))
    )
    (comp (ref "C140")
      (value "C")
      (footprint "SMD_0603_CAPC1608X95N")
      (fields
        (field (name "DB_PART_NUMBER") "CAP000028169")
        (field (name "DB_VALUE") "470nF")
        (field (name "DB_TOLERANCE") "5%")
        (field (name "DB_VOLTAGE") "16V")
        (field (name "DB_MANUFACTURER_PART") "KEMET    C0603C474J4RAC")
      )
      (libsource (lib "Database_Libs1") (part "C"))
    )
    (comp (ref "C141")
      (value "C")
      (footprint "SMD_0603_CAPC1608X95N")
      (fields
        (field (name "DB_PART_NUMBER") "CAP000028169")
        (field (name "DB_VALUE") "470nF")
        (field (name "DB_TOLERANCE") "5%")
        (field (name "DB_VOLTAGE") "16V")
        (field (name "DB_MANUFACTURER_PART") "KEMET    C0603C474J4RAC")
      )
      (libsource (lib "Database_Libs1") (part "C"))
    )
    (comp (ref "C142")
      (value "C")
      (footprint "SMD_0603_CAPC1608X95N")
      (fields
        (field (name "DB_PART_NUMBER") "CAP000028169")
        (field (name "DB_VALUE") "470nF")
        (field (name "DB_TOLERANCE") "5%")
        (field (name "DB_VOLTAGE") "16V")
        (field (name "DB_MANUFACTURER_PART") "KEMET    C0603C474J4RAC")
      )
      (libsource (lib "Database_Libs1") (part "C"))
    )
    (comp (ref "C143")
      (value "C")
      (footprint "SMD_0603_CAPC1608X95N")
      (fields
        (field (name "DB_PART_NUMBER") "CAP000028169")
        (field (name "DB_VALUE") "470nF")
        (field (name "DB_TOLERANCE") "5%")
        (field (name "DB_VOLTAGE") "16V")
        (field (name "DB_MANUFACTURER_PART") "KEMET    C0603C474J4RAC")
      )
      (libsource (lib "Database_Libs1") (part "C"))
    )
    (comp (ref "C144")
      (value "C")
      (footprint "SMD_0603_CAPC1608X95N")
      (fields
        (field (name "DB_PART_NUMBER") "CAP000028169")
        (field (name "DB_VALUE") "470nF")
        (field (name "DB_TOLERANCE") "5%")
        (field (name "DB_VOLTAGE") "16V")
        (field (name "DB_MANUFACTURER_PART") "KEMET    C0603C474J4RAC")
      )
      (libsource (lib "Database_Libs1") (part "C"))
    )
    (comp (ref "C145")
      (value "C")
      (footprint "SMD_0603_CAPC1608X95N")
      (fields
        (field (name "DB_PART_NUMBER") "CAP000028169")
        (field (name "DB_VALUE") "470nF")
        (field (name "DB_TOLERANCE") "5%")
        (field (name "DB_VOLTAGE") "16V")
        (field (name "DB_MANUFACTURER_PART") "KEMET    C0603C474J4RAC")
      )
      (libsource (lib "Database_Libs1") (part "C"))
    )
    (comp (ref "C146")
      (value "C")
      (footprint "SMD_0603_CAPC1608X95N")
      (fields
        (field (name "DB_PART_NUMBER") "CAP000028169")
        (field (name "DB_VALUE") "470nF")
        (field (name "DB_TOLERANCE") "5%")
        (field (name "DB_VOLTAGE") "16V")
        (field (name "DB_MANUFACTURER_PART") "KEMET    C0603C474J4RAC")
      )
      (libsource (lib "Database_Libs1") (part "C"))
    )
    (comp (ref "C147")
      (value "C")
      (footprint "SMD_0603_CAPC1608X95N")
      (fields
        (field (name "DB_PART_NUMBER") "CAP000028169")
        (field (name "DB_VALUE") "470nF")
        (field (name "DB_TOLERANCE") "5%")
        (field (name "DB_VOLTAGE") "16V")
        (field (name "DB_MANUFACTURER_PART") "KEMET    C0603C474J4RAC")
      )
      (libsource (lib "Database_Libs1") (part "C"))
    )
    (comp (ref "C148")
      (value "C")
      (footprint "SMD_0603_CAPC1608X95N")
      (fields
        (field (name "DB_PART_NUMBER") "CAP000028169")
        (field (name "DB_VALUE") "470nF")
        (field (name "DB_TOLERANCE") "5%")
        (field (name "DB_VOLTAGE") "16V")
        (field (name "DB_MANUFACTURER_PART") "KEMET    C0603C474J4RAC")
      )
      (libsource (lib "Database_Libs1") (part "C"))
    )
    (comp (ref "C149")
      (value "C")
      (footprint "SMD_0603_CAPC1608X95N")
      (fields
        (field (name "DB_PART_NUMBER") "CAP000028169")
        (field (name "DB_VALUE") "470nF")
        (field (name "DB_TOLERANCE") "5%")
        (field (name "DB_VOLTAGE") "16V")
        (field (name "DB_MANUFACTURER_PART") "KEMET    C0603C474J4RAC")
      )
      (libsource (lib "Database_Libs1") (part "C"))
    )
    (comp (ref "C150")
      (value "C")
      (footprint "SMD_0603_CAPC1608X95N")
      (fields
        (field (name "DB_PART_NUMBER") "CAP000028169")
        (field (name "DB_VALUE") "470nF")
        (field (name "DB_TOLERANCE") "5%")
        (field (name "DB_VOLTAGE") "16V")
        (field (name "DB_MANUFACTURER_PART") "KEMET    C0603C474J4RAC")
      )
      (libsource (lib "Database_Libs1") (part "C"))
    )
    (comp (ref "C151")
      (value "C")
      (footprint "SMD_0603_CAPC1608X95N")
      (fields
        (field (name "DB_PART_NUMBER") "CAP000028169")
        (field (name "DB_VALUE") "470nF")
        (field (name "DB_TOLERANCE") "5%")
        (field (name "DB_VOLTAGE") "16V")
        (field (name "DB_MANUFACTURER_PART") "KEMET    C0603C474J4RAC")
      )
      (libsource (lib "Database_Libs1") (part "C"))
    )
    (comp (ref "C152")
      (value "C")
      (footprint "SMD_0603_CAPC1608X95N")
      (fields
        (field (name "DB_PART_NUMBER") "CAP000028169")
        (field (name "DB_VALUE") "470nF")
        (field (name "DB_TOLERANCE") "5%")
        (field (name "DB_VOLTAGE") "16V")
        (field (name "DB_MANUFACTURER_PART") "KEMET    C0603C474J4RAC")
      )
      (libsource (lib "Database_Libs1") (part "C"))
    )
    (comp (ref "C153")
      (value "C")
      (footprint "SMD_0603_CAPC1608X95N")
      (fields
        (field (name "DB_PART_NUMBER") "CAP000028169")
        (field (name "DB_VALUE") "470nF")
        (field (name "DB_TOLERANCE") "5%")
        (field (name "DB_VOLTAGE") "16V")
        (field (name "DB_MANUFACTURER_PART") "KEMET    C0603C474J4RAC")
      )
      (libsource (lib "Database_Libs1") (part "C"))
    )
    (comp (ref "C154")
      (value "C")
      (footprint "SMD_0603_CAPC1608X95N")
      (fields
        (field (name "DB_PART_NUMBER") "CAP000028169")
        (field (name "DB_VALUE") "470nF")
        (field (name "DB_TOLERANCE") "5%")
        (field (name "DB_VOLTAGE") "16V")
        (field (name "DB_MANUFACTURER_PART") "KEMET    C0603C474J4RAC")
      )
      (libsource (lib "Database_Libs1") (part "C"))
    )
    (comp (ref "C155")
      (value "C")
      (footprint "SMD_0603_CAPC1608X95N")
      (fields
        (field (name "DB_PART_NUMBER") "CAP000028169")
        (field (name "DB_VALUE") "470nF")
        (field (name "DB_TOLERANCE") "5%")
        (field (name "DB_VOLTAGE") "16V")
        (field (name "DB_MANUFACTURER_PART") "KEMET    C0603C474J4RAC")
      )
      (libsource (lib "Database_Libs1") (part "C"))
    )
    (comp (ref "C156")
      (value "C")
      (footprint "SMD_0603_CAPC1608X95N")
      (fields
        (field (name "DB_PART_NUMBER") "CAP000028169")
        (field (name "DB_VALUE") "470nF")
        (field (name "DB_TOLERANCE") "5%")
        (field (name "DB_VOLTAGE") "16V")
        (field (name "DB_MANUFACTURER_PART") "KEMET    C0603C474J4RAC")
      )
      (libsource (lib "Database_Libs1") (part "C"))
    )
    (comp (ref "C157")
      (value "C")
      (footprint "SMD_0603_CAPC1608X95N")
      (fields
        (field (name "DB_PART_NUMBER") "CAP000028169")
        (field (name "DB_VALUE") "470nF")
        (field (name "DB_TOLERANCE") "5%")
        (field (name "DB_VOLTAGE") "16V")
        (field (name "DB_MANUFACTURER_PART") "KEMET    C0603C474J4RAC")
      )
      (libsource (lib "Database_Libs1") (part "C"))
    )
    (comp (ref "C158")
      (value "C")
      (footprint "SMD_0603_CAPC1608X95N")
      (fields
        (field (name "DB_PART_NUMBER") "CAP000028169")
        (field (name "DB_VALUE") "470nF")
        (field (name "DB_TOLERANCE") "5%")
        (field (name "DB_VOLTAGE") "16V")
        (field (name "DB_MANUFACTURER_PART") "KEMET    C0603C474J4RAC")
      )
      (libsource (lib "Database_Libs1") (part "C"))
    )
    (comp (ref "C159")
      (value "C")
      (footprint "SMD_0603_CAPC1608X95N")
      (fields
        (field (name "DB_PART_NUMBER") "CAP000028169")
        (field (name "DB_VALUE") "470nF")
        (field (name "DB_TOLERANCE") "5%")
        (field (name "DB_VOLTAGE") "16V")
        (field (name "DB_MANUFACTURER_PART") "KEMET    C0603C474J4RAC")
      )
      (libsource (lib "Database_Libs1") (part "C"))
    )
    (comp (ref "C160")
      (value "C")
      (footprint "SMD_0603_CAPC1608X95N")
      (fields
        (field (name "DB_PART_NUMBER") "CAP000028169")
        (field (name "DB_VALUE") "470nF")
        (field (name "DB_TOLERANCE") "5%")
        (field (name "DB_VOLTAGE") "16V")
        (field (name "DB_MANUFACTURER_PART") "KEMET    C0603C474J4RAC")
      )
      (libsource (lib "Database_Libs1") (part "C"))
    )
    (comp (ref "C161")
      (value "C")
      (footprint "SMD_0603_CAPC1608X95N")
      (fields
        (field (name "DB_PART_NUMBER") "CAP000028169")
        (field (name "DB_VALUE") "470nF")
        (field (name "DB_TOLERANCE") "5%")
        (field (name "DB_VOLTAGE") "16V")
        (field (name "DB_MANUFACTURER_PART") "KEMET    C0603C474J4RAC")
      )
      (libsource (lib "Database_Libs1") (part "C"))
    )
    (comp (ref "C162")
      (value "C")
      (footprint "SMD_0603_CAPC1608X95N")
      (fields
        (field (name "DB_PART_NUMBER") "CAP000028169")
        (field (name "DB_VALUE") "470nF")
        (field (name "DB_TOLERANCE") "5%")
        (field (name "DB_VOLTAGE") "16V")
        (field (name "DB_MANUFACTURER_PART") "KEMET    C0603C474J4RAC")
      )
      (libsource (lib "Database_Libs1") (part "C"))
    )
    (comp (ref "C163")
      (value "C")
      (footprint "SMD_0603_CAPC1608X95N")
      (fields
        (field (name "DB_PART_NUMBER") "CAP000028169")
        (field (name "DB_VALUE") "470nF")
        (field (name "DB_TOLERANCE") "5%")
        (field (name "DB_VOLTAGE") "16V")
        (field (name "DB_MANUFACTURER_PART") "KEMET    C0603C474J4RAC")
      )
      (libsource (lib "Database_Libs1") (part "C"))
    )
    (comp (ref "C166")
      (value "C")
      (footprint "SMD_0603_CAPC1608X95N")
      (fields
        (field (name "DB_PART_NUMBER") "CAP000024113")
        (field (name "DB_VALUE") "1nF")
        (field (name "DB_TOLERANCE") "5%")
        (field (name "DB_VOLTAGE") "25V")
        (field (name "DB_MANUFACTURER_PART") "KEMET    C0603C102J3RAC")
      )
      (libsource (lib "Database_Libs1") (part "C"))
    )
    (comp (ref "C167")
      (value "C")
      (footprint "SMD_0603_CAPC1608X95N")
      (fields
        (field (name "DB_PART_NUMBER") "CAP000027136")
        (field (name "DB_VALUE") "100nF")
        (field (name "DB_TOLERANCE") "5%")
        (field (name "DB_VOLTAGE") "50V")
        (field (name "DB_MANUFACTURER_PART") "KEMET    C0603C104J5RAC")
      )
      (libsource (lib "Database_Libs1") (part "C"))
    )
    (comp (ref "C168")
      (value "C")
      (footprint "SMD_0603_CAPC1608X95N")
      (fields
        (field (name "DB_PART_NUMBER") "CAP000027136")
        (field (name "DB_VALUE") "100nF")
        (field (name "DB_TOLERANCE") "5%")
        (field (name "DB_VOLTAGE") "50V")
        (field (name "DB_MANUFACTURER_PART") "KEMET    C0603C104J5RAC")
      )
      (libsource (lib "Database_Libs1") (part "C"))
    )
    (comp (ref "C169")
      (value "C")
      (footprint "SMD_0603_CAPC1608X95N")
      (fields
        (field (name "DB_PART_NUMBER") "CAP000027136")
        (field (name "DB_VALUE") "100nF")
        (field (name "DB_TOLERANCE") "5%")
        (field (name "DB_VOLTAGE") "50V")
        (field (name "DB_MANUFACTURER_PART") "KEMET    C0603C104J5RAC")
      )
      (libsource (lib "Database_Libs1") (part "C"))
    )
    (comp (ref "C170")
      (value "C")
      (footprint "SMD_0603_CAPC1608X95N")
      (fields
        (field (name "DB_PART_NUMBER") "CAP000027136")
        (field (name "DB_VALUE") "100nF")
        (field (name "DB_TOLERANCE") "5%")
        (field (name "DB_VOLTAGE") "50V")
        (field (name "DB_MANUFACTURER_PART") "KEMET    C0603C104J5RAC")
      )
      (libsource (lib "Database_Libs1") (part "C"))
    )
    (comp (ref "C171")
      (value "C")
      (footprint "SMD_0603_CAPC1608X95N")
      (fields
        (field (name "DB_PART_NUMBER") "CAP000027136")
        (field (name "DB_VALUE") "100nF")
        (field (name "DB_TOLERANCE") "5%")
        (field (name "DB_VOLTAGE") "50V")
        (field (name "DB_MANUFACTURER_PART") "KEMET    C0603C104J5RAC")
      )
      (libsource (lib "Database_Libs1") (part "C"))
    )
    (comp (ref "C172")
      (value "C")
      (footprint "SMD_0603_CAPC1608X95N")
      (fields
        (field (name "DB_PART_NUMBER") "CAP000027136")
        (field (name "DB_VALUE") "100nF")
        (field (name "DB_TOLERANCE") "5%")
        (field (name "DB_VOLTAGE") "50V")
        (field (name "DB_MANUFACTURER_PART") "KEMET    C0603C104J5RAC")
      )
      (libsource (lib "Database_Libs1") (part "C"))
    )
    (comp (ref "C173")
      (value "C")
      (footprint "SMD_0603_CAPC1608X95N")
      (fields
        (field (name "DB_PART_NUMBER") "CAP000031922")
        (field (name "DB_VALUE") "18pF")
        (field (name "DB_TOLERANCE") "5%")
        (field (name "DB_VOLTAGE") "50V")
        (field (name "DB_MANUFACTURER_PART") "KEMET    C0603C180J5GAC")
      )
      (libsource (lib "Database_Libs1") (part "C"))
    )
    (comp (ref "C174")
      (value "C")
      (footprint "SMD_0603_CAPC1608X95N")
      (fields
        (field (name "DB_PART_NUMBER") "CAP000031922")
        (field (name "DB_VALUE") "18pF")
        (field (name "DB_TOLERANCE") "5%")
        (field (name "DB_VOLTAGE") "50V")
        (field (name "DB_MANUFACTURER_PART") "KEMET    C0603C180J5GAC")
      )
      (libsource (lib "Database_Libs1") (part "C"))
    )
    (comp (ref "C175")
      (value "C")
      (footprint "SMD_0603_CAPC1608X95N")
      (fields
        (field (name "DB_PART_NUMBER") "CAP000028169")
        (field (name "DB_VALUE") "470nF")
        (field (name "DB_TOLERANCE") "5%")
        (field (name "DB_VOLTAGE") "16V")
        (field (name "DB_MANUFACTURER_PART") "KEMET    C0603C474J4RAC")
      )
      (libsource (lib "Database_Libs1") (part "C"))
    )
    (comp (ref "C176")
      (value "C")
      (footprint "SMD_0603_CAPC1608X95N")
      (fields
        (field (name "DB_PART_NUMBER") "CAP000028169")
        (field (name "DB_VALUE") "470nF")
        (field (name "DB_TOLERANCE") "5%")
        (field (name "DB_VOLTAGE") "16V")
        (field (name "DB_MANUFACTURER_PART") "KEMET    C0603C474J4RAC")
      )
      (libsource (lib "Database_Libs1") (part "C"))
    )
    (comp (ref "C177")
      (value "C")
      (footprint "SMD_0603_CAPC1608X95N")
      (fields
        (field (name "DB_PART_NUMBER") "CAP000028169")
        (field (name "DB_VALUE") "470nF")
        (field (name "DB_TOLERANCE") "5%")
        (field (name "DB_VOLTAGE") "16V")
        (field (name "DB_MANUFACTURER_PART") "KEMET    C0603C474J4RAC")
      )
      (libsource (lib "Database_Libs1") (part "C"))
    )
    (comp (ref "C178")
      (value "C")
      (footprint "SMD_0603_CAPC1608X95N")
      (fields
        (field (name "DB_PART_NUMBER") "CAP000028169")
        (field (name "DB_VALUE") "470nF")
        (field (name "DB_TOLERANCE") "5%")
        (field (name "DB_VOLTAGE") "16V")
        (field (name "DB_MANUFACTURER_PART") "KEMET    C0603C474J4RAC")
      )
      (libsource (lib "Database_Libs1") (part "C"))
    )
    (comp (ref "C179")
      (value "C")
      (footprint "SMD_0603_CAPC1608X95N")
      (fields
        (field (name "DB_PART_NUMBER") "CAP000028169")
        (field (name "DB_VALUE") "470nF")
        (field (name "DB_TOLERANCE") "5%")
        (field (name "DB_VOLTAGE") "16V")
        (field (name "DB_MANUFACTURER_PART") "KEMET    C0603C474J4RAC")
      )
      (libsource (lib "Database_Libs1") (part "C"))
    )
    (comp (ref "C180")
      (value "C")
      (footprint "SMD_0603_CAPC1608X95N")
      (fields
        (field (name "DB_PART_NUMBER") "CAP000028169")
        (field (name "DB_VALUE") "470nF")
        (field (name "DB_TOLERANCE") "5%")
        (field (name "DB_VOLTAGE") "16V")
        (field (name "DB_MANUFACTURER_PART") "KEMET    C0603C474J4RAC")
      )
      (libsource (lib "Database_Libs1") (part "C"))
    )
    (comp (ref "C181")
      (value "C")
      (footprint "SMD_0603_CAPC1608X95N")
      (fields
        (field (name "DB_PART_NUMBER") "CAP000028169")
        (field (name "DB_VALUE") "470nF")
        (field (name "DB_TOLERANCE") "5%")
        (field (name "DB_VOLTAGE") "16V")
        (field (name "DB_MANUFACTURER_PART") "KEMET    C0603C474J4RAC")
      )
      (libsource (lib "Database_Libs1") (part "C"))
    )
    (comp (ref "C182")
      (value "C")
      (footprint "SMD_0603_CAPC1608X95N")
      (fields
        (field (name "DB_PART_NUMBER") "CAP000028169")
        (field (name "DB_VALUE") "470nF")
        (field (name "DB_TOLERANCE") "5%")
        (field (name "DB_VOLTAGE") "16V")
        (field (name "DB_MANUFACTURER_PART") "KEMET    C0603C474J4RAC")
      )
      (libsource (lib "Database_Libs1") (part "C"))
    )
    (comp (ref "C183")
      (value "C")
      (footprint "SMD_0603_CAPC1608X95N")
      (fields
        (field (name "DB_PART_NUMBER") "CAP000028169")
        (field (name "DB_VALUE") "470nF")
        (field (name "DB_TOLERANCE") "5%")
        (field (name "DB_VOLTAGE") "16V")
        (field (name "DB_MANUFACTURER_PART") "KEMET    C0603C474J4RAC")
      )
      (libsource (lib "Database_Libs1") (part "C"))
    )
    (comp (ref "C184")
      (value "C")
      (footprint "SMD_0603_CAPC1608X95N")
      (fields
        (field (name "DB_PART_NUMBER") "CAP000028169")
        (field (name "DB_VALUE") "470nF")
        (field (name "DB_TOLERANCE") "5%")
        (field (name "DB_VOLTAGE") "16V")
        (field (name "DB_MANUFACTURER_PART") "KEMET    C0603C474J4RAC")
      )
      (libsource (lib "Database_Libs1") (part "C"))
    )
    (comp (ref "C185")
      (value "C")
      (footprint "SMD_0603_CAPC1608X95N")
      (fields
        (field (name "DB_PART_NUMBER") "CAP000028169")
        (field (name "DB_VALUE") "470nF")
        (field (name "DB_TOLERANCE") "5%")
        (field (name "DB_VOLTAGE") "16V")
        (field (name "DB_MANUFACTURER_PART") "KEMET    C0603C474J4RAC")
      )
      (libsource (lib "Database_Libs1") (part "C"))
    )
    (comp (ref "C186")
      (value "C")
      (footprint "SMD_0603_CAPC1608X95N")
      (fields
        (field (name "DB_PART_NUMBER") "CAP000028169")
        (field (name "DB_VALUE") "470nF")
        (field (name "DB_TOLERANCE") "5%")
        (field (name "DB_VOLTAGE") "16V")
        (field (name "DB_MANUFACTURER_PART") "KEMET    C0603C474J4RAC")
      )
      (libsource (lib "Database_Libs1") (part "C"))
    )
    (comp (ref "C187")
      (value "C")
      (footprint "SMD_0603_CAPC1608X95N")
      (fields
        (field (name "DB_PART_NUMBER") "CAP000028169")
        (field (name "DB_VALUE") "470nF")
        (field (name "DB_TOLERANCE") "5%")
        (field (name "DB_VOLTAGE") "16V")
        (field (name "DB_MANUFACTURER_PART") "KEMET    C0603C474J4RAC")
      )
      (libsource (lib "Database_Libs1") (part "C"))
    )
    (comp (ref "C188")
      (value "C")
      (footprint "SMD_0603_CAPC1608X95N")
      (fields
        (field (name "DB_PART_NUMBER") "CAP000028169")
        (field (name "DB_VALUE") "470nF")
        (field (name "DB_TOLERANCE") "5%")
        (field (name "DB_VOLTAGE") "16V")
        (field (name "DB_MANUFACTURER_PART") "KEMET    C0603C474J4RAC")
      )
      (libsource (lib "Database_Libs1") (part "C"))
    )
    (comp (ref "C189")
      (value "C")
      (footprint "SMD_0603_CAPC1608X95N")
      (fields
        (field (name "DB_PART_NUMBER") "CAP000028169")
        (field (name "DB_VALUE") "470nF")
        (field (name "DB_TOLERANCE") "5%")
        (field (name "DB_VOLTAGE") "16V")
        (field (name "DB_MANUFACTURER_PART") "KEMET    C0603C474J4RAC")
      )
      (libsource (lib "Database_Libs1") (part "C"))
    )
    (comp (ref "C190")
      (value "C")
      (footprint "SMD_0603_CAPC1608X95N")
      (fields
        (field (name "DB_PART_NUMBER") "CAP000028169")
        (field (name "DB_VALUE") "470nF")
        (field (name "DB_TOLERANCE") "5%")
        (field (name "DB_VOLTAGE") "16V")
        (field (name "DB_MANUFACTURER_PART") "KEMET    C0603C474J4RAC")
      )
      (libsource (lib "Database_Libs1") (part "C"))
    )
    (comp (ref "C191")
      (value "C")
      (footprint "SMD_0805_CAPC2012X145N")
      (fields
        (field (name "DB_PART_NUMBER") "CAP000043636")
        (field (name "DB_VALUE") "10uF")
        (field (name "DB_TOLERANCE") "10%")
        (field (name "DB_VOLTAGE") "16V")
        (field (name "DB_MANUFACTURER_PART") "KEMET    C0805C106K4PAC")
      )
      (libsource (lib "Database_Libs1") (part "C"))
    )
    (comp (ref "C224")
      (value "C")
      (footprint "SMD_1210_CAPC3225X279N")
      (fields
        (field (name "DB_PART_NUMBER") "CAP000047355")
        (field (name "DB_VALUE") "220uF")
        (field (name "DB_TOLERANCE") "20%")
        (field (name "DB_VOLTAGE") "6.3V")
        (field (name "DB_MANUFACTURER_PART") "SAMSUNG    CL32A227MQVNNNE")
        (field (name "DB_APPROVED_BY") "VSN")
      )
      (libsource (lib "Database_Libs1") (part "C"))
    )
    (comp (ref "C225")
      (value "C")
      (footprint "SMD_0805_CAPC2012X145N")
      (fields
        (field (name "DB_PART_NUMBER") "CAP000043686")
        (field (name "DB_VALUE") "22uF")
        (field (name "DB_TOLERANCE") "20%")
        (field (name "DB_VOLTAGE") "6.3V")
        (field (name "DB_MANUFACTURER_PART") "KEMET    C0805C226M9PAC")
      )
      (libsource (lib "Database_Libs1") (part "C"))
    )
    (comp (ref "C226")
      (value "C")
      (footprint "SMD_0805_CAPC2012X145N")
      (fields
        (field (name "DB_PART_NUMBER") "CAP000043636")
        (field (name "DB_VALUE") "10uF")
        (field (name "DB_TOLERANCE") "10%")
        (field (name "DB_VOLTAGE") "16V")
        (field (name "DB_MANUFACTURER_PART") "KEMET    C0805C106K4PAC")
      )
      (libsource (lib "Database_Libs1") (part "C"))
    )
    (comp (ref "C227")
      (value "C")
      (footprint "SMD_0603_CAPC1608X95N")
      (fields
        (field (name "DB_PART_NUMBER") "CAP000028169")
        (field (name "DB_VALUE") "470nF")
        (field (name "DB_TOLERANCE") "5%")
        (field (name "DB_VOLTAGE") "16V")
        (field (name "DB_MANUFACTURER_PART") "KEMET    C0603C474J4RAC")
      )
      (libsource (lib "Database_Libs1") (part "C"))
    )
    (comp (ref "C228")
      (value "C")
      (footprint "SMD_0603_CAPC1608X95N")
      (fields
        (field (name "DB_PART_NUMBER") "CAP000028169")
        (field (name "DB_VALUE") "470nF")
        (field (name "DB_TOLERANCE") "5%")
        (field (name "DB_VOLTAGE") "16V")
        (field (name "DB_MANUFACTURER_PART") "KEMET    C0603C474J4RAC")
      )
      (libsource (lib "Database_Libs1") (part "C"))
    )
    (comp (ref "C229")
      (value "C")
      (footprint "SMD_0603_CAPC1608X95N")
      (fields
        (field (name "DB_PART_NUMBER") "CAP000028169")
        (field (name "DB_VALUE") "470nF")
        (field (name "DB_TOLERANCE") "5%")
        (field (name "DB_VOLTAGE") "16V")
        (field (name "DB_MANUFACTURER_PART") "KEMET    C0603C474J4RAC")
      )
      (libsource (lib "Database_Libs1") (part "C"))
    )
    (comp (ref "C230")
      (value "C")
      (footprint "SMD_0603_CAPC1608X95N")
      (fields
        (field (name "DB_PART_NUMBER") "CAP000028169")
        (field (name "DB_VALUE") "470nF")
        (field (name "DB_TOLERANCE") "5%")
        (field (name "DB_VOLTAGE") "16V")
        (field (name "DB_MANUFACTURER_PART") "KEMET    C0603C474J4RAC")
      )
      (libsource (lib "Database_Libs1") (part "C"))
    )
    (comp (ref "C231")
      (value "C")
      (footprint "SMD_0603_CAPC1608X95N")
      (fields
        (field (name "DB_PART_NUMBER") "CAP000028169")
        (field (name "DB_VALUE") "470nF")
        (field (name "DB_TOLERANCE") "5%")
        (field (name "DB_VOLTAGE") "16V")
        (field (name "DB_MANUFACTURER_PART") "KEMET    C0603C474J4RAC")
      )
      (libsource (lib "Database_Libs1") (part "C"))
    )
    (comp (ref "C232")
      (value "C")
      (footprint "SMD_0603_CAPC1608X95N")
      (fields
        (field (name "DB_PART_NUMBER") "CAP000028169")
        (field (name "DB_VALUE") "470nF")
        (field (name "DB_TOLERANCE") "5%")
        (field (name "DB_VOLTAGE") "16V")
        (field (name "DB_MANUFACTURER_PART") "KEMET    C0603C474J4RAC")
      )
      (libsource (lib "Database_Libs1") (part "C"))
    )
    (comp (ref "C233")
      (value "C")
      (footprint "SMD_0603_CAPC1608X95N")
      (fields
        (field (name "DB_PART_NUMBER") "CAP000028169")
        (field (name "DB_VALUE") "470nF")
        (field (name "DB_TOLERANCE") "5%")
        (field (name "DB_VOLTAGE") "16V")
        (field (name "DB_MANUFACTURER_PART") "KEMET    C0603C474J4RAC")
      )
      (libsource (lib "Database_Libs1") (part "C"))
    )
    (comp (ref "C234")
      (value "C")
      (footprint "SMD_0603_CAPC1608X95N")
      (fields
        (field (name "DB_PART_NUMBER") "CAP000028169")
        (field (name "DB_VALUE") "470nF")
        (field (name "DB_TOLERANCE") "5%")
        (field (name "DB_VOLTAGE") "16V")
        (field (name "DB_MANUFACTURER_PART") "KEMET    C0603C474J4RAC")
      )
      (libsource (lib "Database_Libs1") (part "C"))
    )
    (comp (ref "C235")
      (value "C")
      (footprint "SMD_0603_CAPC1608X95N")
      (fields
        (field (name "DB_PART_NUMBER") "CAP000028169")
        (field (name "DB_VALUE") "470nF")
        (field (name "DB_TOLERANCE") "5%")
        (field (name "DB_VOLTAGE") "16V")
        (field (name "DB_MANUFACTURER_PART") "KEMET    C0603C474J4RAC")
      )
      (libsource (lib "Database_Libs1") (part "C"))
    )
    (comp (ref "C236")
      (value "C")
      (footprint "SMD_0603_CAPC1608X95N")
      (fields
        (field (name "DB_PART_NUMBER") "CAP000028169")
        (field (name "DB_VALUE") "470nF")
        (field (name "DB_TOLERANCE") "5%")
        (field (name "DB_VOLTAGE") "16V")
        (field (name "DB_MANUFACTURER_PART") "KEMET    C0603C474J4RAC")
      )
      (libsource (lib "Database_Libs1") (part "C"))
    )
    (comp (ref "C237")
      (value "C")
      (footprint "SMD_0603_CAPC1608X95N")
      (fields
        (field (name "DB_PART_NUMBER") "CAP000028169")
        (field (name "DB_VALUE") "470nF")
        (field (name "DB_TOLERANCE") "5%")
        (field (name "DB_VOLTAGE") "16V")
        (field (name "DB_MANUFACTURER_PART") "KEMET    C0603C474J4RAC")
      )
      (libsource (lib "Database_Libs1") (part "C"))
    )
    (comp (ref "C238")
      (value "C")
      (footprint "SMD_0603_CAPC1608X95N")
      (fields
        (field (name "DB_PART_NUMBER") "CAP000028169")
        (field (name "DB_VALUE") "470nF")
        (field (name "DB_TOLERANCE") "5%")
        (field (name "DB_VOLTAGE") "16V")
        (field (name "DB_MANUFACTURER_PART") "KEMET    C0603C474J4RAC")
      )
      (libsource (lib "Database_Libs1") (part "C"))
    )
    (comp (ref "C239")
      (value "C")
      (footprint "SMD_0603_CAPC1608X95N")
      (fields
        (field (name "DB_PART_NUMBER") "CAP000028169")
        (field (name "DB_VALUE") "470nF")
        (field (name "DB_TOLERANCE") "5%")
        (field (name "DB_VOLTAGE") "16V")
        (field (name "DB_MANUFACTURER_PART") "KEMET    C0603C474J4RAC")
      )
      (libsource (lib "Database_Libs1") (part "C"))
    )
    (comp (ref "C240")
      (value "C")
      (footprint "SMD_0603_CAPC1608X95N")
      (fields
        (field (name "DB_PART_NUMBER") "CAP000028169")
        (field (name "DB_VALUE") "470nF")
        (field (name "DB_TOLERANCE") "5%")
        (field (name "DB_VOLTAGE") "16V")
        (field (name "DB_MANUFACTURER_PART") "KEMET    C0603C474J4RAC")
      )
      (libsource (lib "Database_Libs1") (part "C"))
    )
    (comp (ref "C241")
      (value "C")
      (footprint "SMD_0603_CAPC1608X95N")
      (fields
        (field (name "DB_PART_NUMBER") "CAP000028169")
        (field (name "DB_VALUE") "470nF")
        (field (name "DB_TOLERANCE") "5%")
        (field (name "DB_VOLTAGE") "16V")
        (field (name "DB_MANUFACTURER_PART") "KEMET    C0603C474J4RAC")
      )
      (libsource (lib "Database_Libs1") (part "C"))
    )
    (comp (ref "C242")
      (value "C")
      (footprint "SMD_0603_CAPC1608X95N")
      (fields
        (field (name "DB_PART_NUMBER") "CAP000028169")
        (field (name "DB_VALUE") "470nF")
        (field (name "DB_TOLERANCE") "5%")
        (field (name "DB_VOLTAGE") "16V")
        (field (name "DB_MANUFACTURER_PART") "KEMET    C0603C474J4RAC")
      )
      (libsource (lib "Database_Libs1") (part "C"))
    )
    (comp (ref "C243")
      (value "C")
      (footprint "SMD_0603_CAPC1608X95N")
      (fields
        (field (name "DB_PART_NUMBER") "CAP000028169")
        (field (name "DB_VALUE") "470nF")
        (field (name "DB_TOLERANCE") "5%")
        (field (name "DB_VOLTAGE") "16V")
        (field (name "DB_MANUFACTURER_PART") "KEMET    C0603C474J4RAC")
      )
      (libsource (lib "Database_Libs1") (part "C"))
    )
    (comp (ref "C244")
      (value "C")
      (footprint "SMD_0603_CAPC1608X95N")
      (fields
        (field (name "DB_PART_NUMBER") "CAP000028169")
        (field (name "DB_VALUE") "470nF")
        (field (name "DB_TOLERANCE") "5%")
        (field (name "DB_VOLTAGE") "16V")
        (field (name "DB_MANUFACTURER_PART") "KEMET    C0603C474J4RAC")
      )
      (libsource (lib "Database_Libs1") (part "C"))
    )
    (comp (ref "C245")
      (value "C")
      (footprint "SMD_0603_CAPC1608X95N")
      (fields
        (field (name "DB_PART_NUMBER") "CAP000028169")
        (field (name "DB_VALUE") "470nF")
        (field (name "DB_TOLERANCE") "5%")
        (field (name "DB_VOLTAGE") "16V")
        (field (name "DB_MANUFACTURER_PART") "KEMET    C0603C474J4RAC")
      )
      (libsource (lib "Database_Libs1") (part "C"))
    )
    (comp (ref "C246")
      (value "C")
      (footprint "SMD_0603_CAPC1608X95N")
      (fields
        (field (name "DB_PART_NUMBER") "CAP000028169")
        (field (name "DB_VALUE") "470nF")
        (field (name "DB_TOLERANCE") "5%")
        (field (name "DB_VOLTAGE") "16V")
        (field (name "DB_MANUFACTURER_PART") "KEMET    C0603C474J4RAC")
      )
      (libsource (lib "Database_Libs1") (part "C"))
    )
    (comp (ref "C247")
      (value "C")
      (footprint "SMD_0603_CAPC1608X95N")
      (fields
        (field (name "DB_PART_NUMBER") "CAP000028169")
        (field (name "DB_VALUE") "470nF")
        (field (name "DB_TOLERANCE") "5%")
        (field (name "DB_VOLTAGE") "16V")
        (field (name "DB_MANUFACTURER_PART") "KEMET    C0603C474J4RAC")
      )
      (libsource (lib "Database_Libs1") (part "C"))
    )
    (comp (ref "C248")
      (value "C")
      (footprint "SMD_0603_CAPC1608X95N")
      (fields
        (field (name "DB_PART_NUMBER") "CAP000028169")
        (field (name "DB_VALUE") "470nF")
        (field (name "DB_TOLERANCE") "5%")
        (field (name "DB_VOLTAGE") "16V")
        (field (name "DB_MANUFACTURER_PART") "KEMET    C0603C474J4RAC")
      )
      (libsource (lib "Database_Libs1") (part "C"))
    )
    (comp (ref "C249")
      (value "C")
      (footprint "SMD_0603_CAPC1608X95N")
      (fields
        (field (name "DB_PART_NUMBER") "CAP000028169")
        (field (name "DB_VALUE") "470nF")
        (field (name "DB_TOLERANCE") "5%")
        (field (name "DB_VOLTAGE") "16V")
        (field (name "DB_MANUFACTURER_PART") "KEMET    C0603C474J4RAC")
      )
      (libsource (lib "Database_Libs1") (part "C"))
    )
    (comp (ref "C250")
      (value "C")
      (footprint "SMD_0603_CAPC1608X95N")
      (fields
        (field (name "DB_PART_NUMBER") "CAP000028169")
        (field (name "DB_VALUE") "470nF")
        (field (name "DB_TOLERANCE") "5%")
        (field (name "DB_VOLTAGE") "16V")
        (field (name "DB_MANUFACTURER_PART") "KEMET    C0603C474J4RAC")
      )
      (libsource (lib "Database_Libs1") (part "C"))
    )
    (comp (ref "C251")
      (value "C")
      (footprint "SMD_0603_CAPC1608X95N")
      (fields
        (field (name "DB_PART_NUMBER") "CAP000028169")
        (field (name "DB_VALUE") "470nF")
        (field (name "DB_TOLERANCE") "5%")
        (field (name "DB_VOLTAGE") "16V")
        (field (name "DB_MANUFACTURER_PART") "KEMET    C0603C474J4RAC")
      )
      (libsource (lib "Database_Libs1") (part "C"))
    )
    (comp (ref "C252")
      (value "C")
      (footprint "SMD_0603_CAPC1608X95N")
      (fields
        (field (name "DB_PART_NUMBER") "CAP000028169")
        (field (name "DB_VALUE") "470nF")
        (field (name "DB_TOLERANCE") "5%")
        (field (name "DB_VOLTAGE") "16V")
        (field (name "DB_MANUFACTURER_PART") "KEMET    C0603C474J4RAC")
      )
      (libsource (lib "Database_Libs1") (part "C"))
    )
    (comp (ref "C253")
      (value "C")
      (footprint "SMD_0603_CAPC1608X95N")
      (fields
        (field (name "DB_PART_NUMBER") "CAP000028169")
        (field (name "DB_VALUE") "470nF")
        (field (name "DB_TOLERANCE") "5%")
        (field (name "DB_VOLTAGE") "16V")
        (field (name "DB_MANUFACTURER_PART") "KEMET    C0603C474J4RAC")
      )
      (libsource (lib "Database_Libs1") (part "C"))
    )
    (comp (ref "C254")
      (value "C")
      (footprint "SMD_0603_CAPC1608X95N")
      (fields
        (field (name "DB_PART_NUMBER") "CAP000028169")
        (field (name "DB_VALUE") "470nF")
        (field (name "DB_TOLERANCE") "5%")
        (field (name "DB_VOLTAGE") "16V")
        (field (name "DB_MANUFACTURER_PART") "KEMET    C0603C474J4RAC")
      )
      (libsource (lib "Database_Libs1") (part "C"))
    )
    (comp (ref "C255")
      (value "C")
      (footprint "SMD_0603_CAPC1608X95N")
      (fields
        (field (name "DB_PART_NUMBER") "CAP000028169")
        (field (name "DB_VALUE") "470nF")
        (field (name "DB_TOLERANCE") "5%")
        (field (name "DB_VOLTAGE") "16V")
        (field (name "DB_MANUFACTURER_PART") "KEMET    C0603C474J4RAC")
      )
      (libsource (lib "Database_Libs1") (part "C"))
    )
    (comp (ref "C256")
      (value "C")
      (footprint "SMD_0603_CAPC1608X95N")
      (fields
        (field (name "DB_PART_NUMBER") "CAP000028169")
        (field (name "DB_VALUE") "470nF")
        (field (name "DB_TOLERANCE") "5%")
        (field (name "DB_VOLTAGE") "16V")
        (field (name "DB_MANUFACTURER_PART") "KEMET    C0603C474J4RAC")
      )
      (libsource (lib "Database_Libs1") (part "C"))
    )
    (comp (ref "C257")
      (value "C")
      (footprint "SMD_0603_CAPC1608X95N")
      (fields
        (field (name "DB_PART_NUMBER") "CAP000028169")
        (field (name "DB_VALUE") "470nF")
        (field (name "DB_TOLERANCE") "5%")
        (field (name "DB_VOLTAGE") "16V")
        (field (name "DB_MANUFACTURER_PART") "KEMET    C0603C474J4RAC")
      )
      (libsource (lib "Database_Libs1") (part "C"))
    )
    (comp (ref "C258")
      (value "C")
      (footprint "SMD_0603_CAPC1608X95N")
      (fields
        (field (name "DB_PART_NUMBER") "CAP000028169")
        (field (name "DB_VALUE") "470nF")
        (field (name "DB_TOLERANCE") "5%")
        (field (name "DB_VOLTAGE") "16V")
        (field (name "DB_MANUFACTURER_PART") "KEMET    C0603C474J4RAC")
      )
      (libsource (lib "Database_Libs1") (part "C"))
    )
    (comp (ref "C259")
      (value "C")
      (footprint "SMD_0805_CAPC2012X145N")
      (fields
        (field (name "DB_PART_NUMBER") "CAP000043686")
        (field (name "DB_VALUE") "22uF")
        (field (name "DB_TOLERANCE") "20%")
        (field (name "DB_VOLTAGE") "6.3V")
        (field (name "DB_MANUFACTURER_PART") "KEMET    C0805C226M9PAC")
      )
      (libsource (lib "Database_Libs1") (part "C"))
    )
    (comp (ref "C260")
      (value "C")
      (footprint "SMD_0603_CAPC1608X95N")
      (fields
        (field (name "DB_PART_NUMBER") "CAP000027136")
        (field (name "DB_VALUE") "100nF")
        (field (name "DB_TOLERANCE") "5%")
        (field (name "DB_VOLTAGE") "50V")
        (field (name "DB_MANUFACTURER_PART") "KEMET    C0603C104J5RAC")
      )
      (libsource (lib "Database_Libs1") (part "C"))
    )
    (comp (ref "C261")
      (value "C")
      (footprint "SMD_0603_CAPC1608X95N")
      (fields
        (field (name "DB_PART_NUMBER") "CAP000027136")
        (field (name "DB_VALUE") "100nF")
        (field (name "DB_TOLERANCE") "5%")
        (field (name "DB_VOLTAGE") "50V")
        (field (name "DB_MANUFACTURER_PART") "KEMET    C0603C104J5RAC")
      )
      (libsource (lib "Database_Libs1") (part "C"))
    )
    (comp (ref "C262")
      (value "C")
      (footprint "SMD_0603_CAPC1608X95N")
      (fields
        (field (name "DB_PART_NUMBER") "CAP000028169")
        (field (name "DB_VALUE") "470nF")
        (field (name "DB_TOLERANCE") "5%")
        (field (name "DB_VOLTAGE") "16V")
        (field (name "DB_MANUFACTURER_PART") "KEMET    C0603C474J4RAC")
      )
      (libsource (lib "Database_Libs1") (part "C"))
    )
    (comp (ref "C263")
      (value "C")
      (footprint "SMD_0603_CAPC1608X95N")
      (fields
        (field (name "DB_PART_NUMBER") "CAP000028169")
        (field (name "DB_VALUE") "470nF")
        (field (name "DB_TOLERANCE") "5%")
        (field (name "DB_VOLTAGE") "16V")
        (field (name "DB_MANUFACTURER_PART") "KEMET    C0603C474J4RAC")
      )
      (libsource (lib "Database_Libs1") (part "C"))
    )
    (comp (ref "C264")
      (value "C")
      (footprint "SMD_0603_CAPC1608X95N")
      (fields
        (field (name "DB_PART_NUMBER") "CAP000028169")
        (field (name "DB_VALUE") "470nF")
        (field (name "DB_TOLERANCE") "5%")
        (field (name "DB_VOLTAGE") "16V")
        (field (name "DB_MANUFACTURER_PART") "KEMET    C0603C474J4RAC")
      )
      (libsource (lib "Database_Libs1") (part "C"))
    )
    (comp (ref "C265")
      (value "C")
      (footprint "SMD_0603_CAPC1608X95N")
      (fields
        (field (name "DB_PART_NUMBER") "CAP000028169")
        (field (name "DB_VALUE") "470nF")
        (field (name "DB_TOLERANCE") "5%")
        (field (name "DB_VOLTAGE") "16V")
        (field (name "DB_MANUFACTURER_PART") "KEMET    C0603C474J4RAC")
      )
      (libsource (lib "Database_Libs1") (part "C"))
    )
    (comp (ref "C266")
      (value "C")
      (footprint "SMD_0603_CAPC1608X95N")
      (fields
        (field (name "DB_PART_NUMBER") "CAP000028169")
        (field (name "DB_VALUE") "470nF")
        (field (name "DB_TOLERANCE") "5%")
        (field (name "DB_VOLTAGE") "16V")
        (field (name "DB_MANUFACTURER_PART") "KEMET    C0603C474J4RAC")
      )
      (libsource (lib "Database_Libs1") (part "C"))
    )
    (comp (ref "C267")
      (value "C")
      (footprint "SMD_0603_CAPC1608X95N")
      (fields
        (field (name "DB_PART_NUMBER") "CAP000028169")
        (field (name "DB_VALUE") "470nF")
        (field (name "DB_TOLERANCE") "5%")
        (field (name "DB_VOLTAGE") "16V")
        (field (name "DB_MANUFACTURER_PART") "KEMET    C0603C474J4RAC")
      )
      (libsource (lib "Database_Libs1") (part "C"))
    )
    (comp (ref "C268")
      (value "C")
      (footprint "SMD_0603_CAPC1608X95N")
      (fields
        (field (name "DB_PART_NUMBER") "CAP000028169")
        (field (name "DB_VALUE") "470nF")
        (field (name "DB_TOLERANCE") "5%")
        (field (name "DB_VOLTAGE") "16V")
        (field (name "DB_MANUFACTURER_PART") "KEMET    C0603C474J4RAC")
      )
      (libsource (lib "Database_Libs1") (part "C"))
    )
    (comp (ref "C269")
      (value "C")
      (footprint "SMD_0603_CAPC1608X95N")
      (fields
        (field (name "DB_PART_NUMBER") "CAP000028169")
        (field (name "DB_VALUE") "470nF")
        (field (name "DB_TOLERANCE") "5%")
        (field (name "DB_VOLTAGE") "16V")
        (field (name "DB_MANUFACTURER_PART") "KEMET    C0603C474J4RAC")
      )
      (libsource (lib "Database_Libs1") (part "C"))
    )
    (comp (ref "C270")
      (value "C")
      (footprint "SMD_0603_CAPC1608X95N")
      (fields
        (field (name "DB_PART_NUMBER") "CAP000028169")
        (field (name "DB_VALUE") "470nF")
        (field (name "DB_TOLERANCE") "5%")
        (field (name "DB_VOLTAGE") "16V")
        (field (name "DB_MANUFACTURER_PART") "KEMET    C0603C474J4RAC")
      )
      (libsource (lib "Database_Libs1") (part "C"))
    )
    (comp (ref "C271")
      (value "C")
      (footprint "SMD_0603_CAPC1608X95N")
      (fields
        (field (name "DB_PART_NUMBER") "CAP000028169")
        (field (name "DB_VALUE") "470nF")
        (field (name "DB_TOLERANCE") "5%")
        (field (name "DB_VOLTAGE") "16V")
        (field (name "DB_MANUFACTURER_PART") "KEMET    C0603C474J4RAC")
      )
      (libsource (lib "Database_Libs1") (part "C"))
    )
    (comp (ref "C272")
      (value "C")
      (footprint "SMD_0603_CAPC1608X95N")
      (fields
        (field (name "DB_PART_NUMBER") "CAP000028169")
        (field (name "DB_VALUE") "470nF")
        (field (name "DB_TOLERANCE") "5%")
        (field (name "DB_VOLTAGE") "16V")
        (field (name "DB_MANUFACTURER_PART") "KEMET    C0603C474J4RAC")
      )
      (libsource (lib "Database_Libs1") (part "C"))
    )
    (comp (ref "C273")
      (value "C")
      (footprint "SMD_0603_CAPC1608X95N")
      (fields
        (field (name "DB_PART_NUMBER") "CAP000028169")
        (field (name "DB_VALUE") "470nF")
        (field (name "DB_TOLERANCE") "5%")
        (field (name "DB_VOLTAGE") "16V")
        (field (name "DB_MANUFACTURER_PART") "KEMET    C0603C474J4RAC")
      )
      (libsource (lib "Database_Libs1") (part "C"))
    )
    (comp (ref "C274")
      (value "C")
      (footprint "SMD_0805_CAPC2012X145N")
      (fields
        (field (name "DB_PART_NUMBER") "CAP000043686")
        (field (name "DB_VALUE") "22uF")
        (field (name "DB_TOLERANCE") "20%")
        (field (name "DB_VOLTAGE") "6.3V")
        (field (name "DB_MANUFACTURER_PART") "KEMET    C0805C226M9PAC")
      )
      (libsource (lib "Database_Libs1") (part "C"))
    )
    (comp (ref "C275")
      (value "C")
      (footprint "SMD_0805_CAPC2012X145N")
      (fields
        (field (name "DB_PART_NUMBER") "CAP000043636")
        (field (name "DB_VALUE") "10uF")
        (field (name "DB_TOLERANCE") "10%")
        (field (name "DB_VOLTAGE") "16V")
        (field (name "DB_MANUFACTURER_PART") "KEMET    C0805C106K4PAC")
      )
      (libsource (lib "Database_Libs1") (part "C"))
    )
    (comp (ref "C276")
      (value "C")
      (footprint "SMD_0603_CAPC1608X95N")
      (fields
        (field (name "DB_PART_NUMBER") "CAP000028169")
        (field (name "DB_VALUE") "470nF")
        (field (name "DB_TOLERANCE") "5%")
        (field (name "DB_VOLTAGE") "16V")
        (field (name "DB_MANUFACTURER_PART") "KEMET    C0603C474J4RAC")
      )
      (libsource (lib "Database_Libs1") (part "C"))
    )
    (comp (ref "C277")
      (value "C")
      (footprint "SMD_0603_CAPC1608X95N")
      (fields
        (field (name "DB_PART_NUMBER") "CAP000028169")
        (field (name "DB_VALUE") "470nF")
        (field (name "DB_TOLERANCE") "5%")
        (field (name "DB_VOLTAGE") "16V")
        (field (name "DB_MANUFACTURER_PART") "KEMET    C0603C474J4RAC")
      )
      (libsource (lib "Database_Libs1") (part "C"))
    )
    (comp (ref "C278")
      (value "C")
      (footprint "SMD_0603_CAPC1608X95N")
      (fields
        (field (name "DB_PART_NUMBER") "CAP000028169")
        (field (name "DB_VALUE") "470nF")
        (field (name "DB_TOLERANCE") "5%")
        (field (name "DB_VOLTAGE") "16V")
        (field (name "DB_MANUFACTURER_PART") "KEMET    C0603C474J4RAC")
      )
      (libsource (lib "Database_Libs1") (part "C"))
    )
    (comp (ref "C279")
      (value "C")
      (footprint "SMD_0603_CAPC1608X95N")
      (fields
        (field (name "DB_PART_NUMBER") "CAP000028169")
        (field (name "DB_VALUE") "470nF")
        (field (name "DB_TOLERANCE") "5%")
        (field (name "DB_VOLTAGE") "16V")
        (field (name "DB_MANUFACTURER_PART") "KEMET    C0603C474J4RAC")
      )
      (libsource (lib "Database_Libs1") (part "C"))
    )
    (comp (ref "C280")
      (value "C")
      (footprint "SMD_0603_CAPC1608X95N")
      (fields
        (field (name "DB_PART_NUMBER") "CAP000028169")
        (field (name "DB_VALUE") "470nF")
        (field (name "DB_TOLERANCE") "5%")
        (field (name "DB_VOLTAGE") "16V")
        (field (name "DB_MANUFACTURER_PART") "KEMET    C0603C474J4RAC")
      )
      (libsource (lib "Database_Libs1") (part "C"))
    )
    (comp (ref "C281")
      (value "C")
      (footprint "SMD_0603_CAPC1608X95N")
      (fields
        (field (name "DB_PART_NUMBER") "CAP000028169")
        (field (name "DB_VALUE") "470nF")
        (field (name "DB_TOLERANCE") "5%")
        (field (name "DB_VOLTAGE") "16V")
        (field (name "DB_MANUFACTURER_PART") "KEMET    C0603C474J4RAC")
      )
      (libsource (lib "Database_Libs1") (part "C"))
    )
    (comp (ref "C282")
      (value "C")
      (footprint "SMD_0603_CAPC1608X95N")
      (fields
        (field (name "DB_PART_NUMBER") "CAP000028169")
        (field (name "DB_VALUE") "470nF")
        (field (name "DB_TOLERANCE") "5%")
        (field (name "DB_VOLTAGE") "16V")
        (field (name "DB_MANUFACTURER_PART") "KEMET    C0603C474J4RAC")
      )
      (libsource (lib "Database_Libs1") (part "C"))
    )
    (comp (ref "C283")
      (value "C")
      (footprint "SMD_0603_CAPC1608X95N")
      (fields
        (field (name "DB_PART_NUMBER") "CAP000028169")
        (field (name "DB_VALUE") "470nF")
        (field (name "DB_TOLERANCE") "5%")
        (field (name "DB_VOLTAGE") "16V")
        (field (name "DB_MANUFACTURER_PART") "KEMET    C0603C474J4RAC")
      )
      (libsource (lib "Database_Libs1") (part "C"))
    )
    (comp (ref "C284")
      (value "C")
      (footprint "SMD_0603_CAPC1608X95N")
      (fields
        (field (name "DB_PART_NUMBER") "CAP000028169")
        (field (name "DB_VALUE") "470nF")
        (field (name "DB_TOLERANCE") "5%")
        (field (name "DB_VOLTAGE") "16V")
        (field (name "DB_MANUFACTURER_PART") "KEMET    C0603C474J4RAC")
      )
      (libsource (lib "Database_Libs1") (part "C"))
    )
    (comp (ref "C285")
      (value "C")
      (footprint "SMD_0603_CAPC1608X95N")
      (fields
        (field (name "DB_PART_NUMBER") "CAP000028169")
        (field (name "DB_VALUE") "470nF")
        (field (name "DB_TOLERANCE") "5%")
        (field (name "DB_VOLTAGE") "16V")
        (field (name "DB_MANUFACTURER_PART") "KEMET    C0603C474J4RAC")
      )
      (libsource (lib "Database_Libs1") (part "C"))
    )
    (comp (ref "C286")
      (value "C")
      (footprint "SMD_0603_CAPC1608X95N")
      (fields
        (field (name "DB_PART_NUMBER") "CAP000028169")
        (field (name "DB_VALUE") "470nF")
        (field (name "DB_TOLERANCE") "5%")
        (field (name "DB_VOLTAGE") "16V")
        (field (name "DB_MANUFACTURER_PART") "KEMET    C0603C474J4RAC")
      )
      (libsource (lib "Database_Libs1") (part "C"))
    )
    (comp (ref "C287")
      (value "C")
      (footprint "SMD_0603_CAPC1608X95N")
      (fields
        (field (name "DB_PART_NUMBER") "CAP000028169")
        (field (name "DB_VALUE") "470nF")
        (field (name "DB_TOLERANCE") "5%")
        (field (name "DB_VOLTAGE") "16V")
        (field (name "DB_MANUFACTURER_PART") "KEMET    C0603C474J4RAC")
      )
      (libsource (lib "Database_Libs1") (part "C"))
    )
    (comp (ref "C288")
      (value "C")
      (footprint "SMD_0603_CAPC1608X95N")
      (fields
        (field (name "DB_PART_NUMBER") "CAP000028169")
        (field (name "DB_VALUE") "470nF")
        (field (name "DB_TOLERANCE") "5%")
        (field (name "DB_VOLTAGE") "16V")
        (field (name "DB_MANUFACTURER_PART") "KEMET    C0603C474J4RAC")
      )
      (libsource (lib "Database_Libs1") (part "C"))
    )
    (comp (ref "C289")
      (value "C")
      (footprint "SMD_0603_CAPC1608X95N")
      (fields
        (field (name "DB_PART_NUMBER") "CAP000028169")
        (field (name "DB_VALUE") "470nF")
        (field (name "DB_TOLERANCE") "5%")
        (field (name "DB_VOLTAGE") "16V")
        (field (name "DB_MANUFACTURER_PART") "KEMET    C0603C474J4RAC")
      )
      (libsource (lib "Database_Libs1") (part "C"))
    )
    (comp (ref "C290")
      (value "C")
      (footprint "SMD_0603_CAPC1608X95N")
      (fields
        (field (name "DB_PART_NUMBER") "CAP000028169")
        (field (name "DB_VALUE") "470nF")
        (field (name "DB_TOLERANCE") "5%")
        (field (name "DB_VOLTAGE") "16V")
        (field (name "DB_MANUFACTURER_PART") "KEMET    C0603C474J4RAC")
      )
      (libsource (lib "Database_Libs1") (part "C"))
    )
    (comp (ref "C291")
      (value "C")
      (footprint "SMD_0603_CAPC1608X95N")
      (fields
        (field (name "DB_PART_NUMBER") "CAP000028169")
        (field (name "DB_VALUE") "470nF")
        (field (name "DB_TOLERANCE") "5%")
        (field (name "DB_VOLTAGE") "16V")
        (field (name "DB_MANUFACTURER_PART") "KEMET    C0603C474J4RAC")
      )
      (libsource (lib "Database_Libs1") (part "C"))
    )
    (comp (ref "C324")
      (value "C")
      (footprint "SMD_0603_CAPC1608X95N")
      (fields
        (field (name "DB_PART_NUMBER") "CAP000028169")
        (field (name "DB_VALUE") "470nF")
        (field (name "DB_TOLERANCE") "5%")
        (field (name "DB_VOLTAGE") "16V")
        (field (name "DB_MANUFACTURER_PART") "KEMET    C0603C474J4RAC")
      )
      (libsource (lib "Database_Libs1") (part "C"))
    )
    (comp (ref "C325")
      (value "C")
      (footprint "SMD_0603_CAPC1608X95N")
      (fields
        (field (name "DB_PART_NUMBER") "CAP000028169")
        (field (name "DB_VALUE") "470nF")
        (field (name "DB_TOLERANCE") "5%")
        (field (name "DB_VOLTAGE") "16V")
        (field (name "DB_MANUFACTURER_PART") "KEMET    C0603C474J4RAC")
      )
      (libsource (lib "Database_Libs1") (part "C"))
    )
    (comp (ref "C326")
      (value "C")
      (footprint "SMD_0603_CAPC1608X95N")
      (fields
        (field (name "DB_PART_NUMBER") "CAP000028169")
        (field (name "DB_VALUE") "470nF")
        (field (name "DB_TOLERANCE") "5%")
        (field (name "DB_VOLTAGE") "16V")
        (field (name "DB_MANUFACTURER_PART") "KEMET    C0603C474J4RAC")
      )
      (libsource (lib "Database_Libs1") (part "C"))
    )
    (comp (ref "C327")
      (value "C")
      (footprint "SMD_0603_CAPC1608X95N")
      (fields
        (field (name "DB_PART_NUMBER") "CAP000028169")
        (field (name "DB_VALUE") "470nF")
        (field (name "DB_TOLERANCE") "5%")
        (field (name "DB_VOLTAGE") "16V")
        (field (name "DB_MANUFACTURER_PART") "KEMET    C0603C474J4RAC")
      )
      (libsource (lib "Database_Libs1") (part "C"))
    )
    (comp (ref "C328")
      (value "C")
      (footprint "SMD_0603_CAPC1608X95N")
      (fields
        (field (name "DB_PART_NUMBER") "CAP000028169")
        (field (name "DB_VALUE") "470nF")
        (field (name "DB_TOLERANCE") "5%")
        (field (name "DB_VOLTAGE") "16V")
        (field (name "DB_MANUFACTURER_PART") "KEMET    C0603C474J4RAC")
      )
      (libsource (lib "Database_Libs1") (part "C"))
    )
    (comp (ref "C329")
      (value "C")
      (footprint "SMD_0603_CAPC1608X95N")
      (fields
        (field (name "DB_PART_NUMBER") "CAP000028169")
        (field (name "DB_VALUE") "470nF")
        (field (name "DB_TOLERANCE") "5%")
        (field (name "DB_VOLTAGE") "16V")
        (field (name "DB_MANUFACTURER_PART") "KEMET    C0603C474J4RAC")
      )
      (libsource (lib "Database_Libs1") (part "C"))
    )
    (comp (ref "C330")
      (value "C")
      (footprint "SMD_0603_CAPC1608X95N")
      (fields
        (field (name "DB_PART_NUMBER") "CAP000028169")
        (field (name "DB_VALUE") "470nF")
        (field (name "DB_TOLERANCE") "5%")
        (field (name "DB_VOLTAGE") "16V")
        (field (name "DB_MANUFACTURER_PART") "KEMET    C0603C474J4RAC")
      )
      (libsource (lib "Database_Libs1") (part "C"))
    )
    (comp (ref "C331")
      (value "C")
      (footprint "SMD_0603_CAPC1608X95N")
      (fields
        (field (name "DB_PART_NUMBER") "CAP000028169")
        (field (name "DB_VALUE") "470nF")
        (field (name "DB_TOLERANCE") "5%")
        (field (name "DB_VOLTAGE") "16V")
        (field (name "DB_MANUFACTURER_PART") "KEMET    C0603C474J4RAC")
      )
      (libsource (lib "Database_Libs1") (part "C"))
    )
    (comp (ref "C332")
      (value "C")
      (footprint "SMD_0603_CAPC1608X95N")
      (fields
        (field (name "DB_PART_NUMBER") "CAP000028169")
        (field (name "DB_VALUE") "470nF")
        (field (name "DB_TOLERANCE") "5%")
        (field (name "DB_VOLTAGE") "16V")
        (field (name "DB_MANUFACTURER_PART") "KEMET    C0603C474J4RAC")
      )
      (libsource (lib "Database_Libs1") (part "C"))
    )
    (comp (ref "C333")
      (value "C")
      (footprint "SMD_0603_CAPC1608X95N")
      (fields
        (field (name "DB_PART_NUMBER") "CAP000028169")
        (field (name "DB_VALUE") "470nF")
        (field (name "DB_TOLERANCE") "5%")
        (field (name "DB_VOLTAGE") "16V")
        (field (name "DB_MANUFACTURER_PART") "KEMET    C0603C474J4RAC")
      )
      (libsource (lib "Database_Libs1") (part "C"))
    )
    (comp (ref "C334")
      (value "C")
      (footprint "SMD_0603_CAPC1608X95N")
      (fields
        (field (name "DB_PART_NUMBER") "CAP000028169")
        (field (name "DB_VALUE") "470nF")
        (field (name "DB_TOLERANCE") "5%")
        (field (name "DB_VOLTAGE") "16V")
        (field (name "DB_MANUFACTURER_PART") "KEMET    C0603C474J4RAC")
      )
      (libsource (lib "Database_Libs1") (part "C"))
    )
    (comp (ref "C335")
      (value "C")
      (footprint "SMD_0603_CAPC1608X95N")
      (fields
        (field (name "DB_PART_NUMBER") "CAP000028169")
        (field (name "DB_VALUE") "470nF")
        (field (name "DB_TOLERANCE") "5%")
        (field (name "DB_VOLTAGE") "16V")
        (field (name "DB_MANUFACTURER_PART") "KEMET    C0603C474J4RAC")
      )
      (libsource (lib "Database_Libs1") (part "C"))
    )
    (comp (ref "C336")
      (value "C")
      (footprint "SMD_0603_CAPC1608X95N")
      (fields
        (field (name "DB_PART_NUMBER") "CAP000028169")
        (field (name "DB_VALUE") "470nF")
        (field (name "DB_TOLERANCE") "5%")
        (field (name "DB_VOLTAGE") "16V")
        (field (name "DB_MANUFACTURER_PART") "KEMET    C0603C474J4RAC")
      )
      (libsource (lib "Database_Libs1") (part "C"))
    )
    (comp (ref "C337")
      (value "C")
      (footprint "SMD_0603_CAPC1608X95N")
      (fields
        (field (name "DB_PART_NUMBER") "CAP000028169")
        (field (name "DB_VALUE") "470nF")
        (field (name "DB_TOLERANCE") "5%")
        (field (name "DB_VOLTAGE") "16V")
        (field (name "DB_MANUFACTURER_PART") "KEMET    C0603C474J4RAC")
      )
      (libsource (lib "Database_Libs1") (part "C"))
    )
    (comp (ref "C338")
      (value "C")
      (footprint "SMD_0603_CAPC1608X95N")
      (fields
        (field (name "DB_PART_NUMBER") "CAP000028169")
        (field (name "DB_VALUE") "470nF")
        (field (name "DB_TOLERANCE") "5%")
        (field (name "DB_VOLTAGE") "16V")
        (field (name "DB_MANUFACTURER_PART") "KEMET    C0603C474J4RAC")
      )
      (libsource (lib "Database_Libs1") (part "C"))
    )
    (comp (ref "C339")
      (value "C")
      (footprint "SMD_0603_CAPC1608X95N")
      (fields
        (field (name "DB_PART_NUMBER") "CAP000028169")
        (field (name "DB_VALUE") "470nF")
        (field (name "DB_TOLERANCE") "5%")
        (field (name "DB_VOLTAGE") "16V")
        (field (name "DB_MANUFACTURER_PART") "KEMET    C0603C474J4RAC")
      )
      (libsource (lib "Database_Libs1") (part "C"))
    )
    (comp (ref "C340")
      (value "C")
      (footprint "SMD_0603_CAPC1608X95N")
      (fields
        (field (name "DB_PART_NUMBER") "CAP000028169")
        (field (name "DB_VALUE") "470nF")
        (field (name "DB_TOLERANCE") "5%")
        (field (name "DB_VOLTAGE") "16V")
        (field (name "DB_MANUFACTURER_PART") "KEMET    C0603C474J4RAC")
      )
      (libsource (lib "Database_Libs1") (part "C"))
    )
    (comp (ref "C341")
      (value "C")
      (footprint "SMD_0603_CAPC1608X95N")
      (fields
        (field (name "DB_PART_NUMBER") "CAP000028169")
        (field (name "DB_VALUE") "470nF")
        (field (name "DB_TOLERANCE") "5%")
        (field (name "DB_VOLTAGE") "16V")
        (field (name "DB_MANUFACTURER_PART") "KEMET    C0603C474J4RAC")
      )
      (libsource (lib "Database_Libs1") (part "C"))
    )
    (comp (ref "C342")
      (value "C")
      (footprint "SMD_0603_CAPC1608X95N")
      (fields
        (field (name "DB_PART_NUMBER") "CAP000028169")
        (field (name "DB_VALUE") "470nF")
        (field (name "DB_TOLERANCE") "5%")
        (field (name "DB_VOLTAGE") "16V")
        (field (name "DB_MANUFACTURER_PART") "KEMET    C0603C474J4RAC")
      )
      (libsource (lib "Database_Libs1") (part "C"))
    )
    (comp (ref "C343")
      (value "C")
      (footprint "SMD_0603_CAPC1608X95N")
      (fields
        (field (name "DB_PART_NUMBER") "CAP000028169")
        (field (name "DB_VALUE") "470nF")
        (field (name "DB_TOLERANCE") "5%")
        (field (name "DB_VOLTAGE") "16V")
        (field (name "DB_MANUFACTURER_PART") "KEMET    C0603C474J4RAC")
      )
      (libsource (lib "Database_Libs1") (part "C"))
    )
    (comp (ref "C344")
      (value "C")
      (footprint "SMD_0603_CAPC1608X95N")
      (fields
        (field (name "DB_PART_NUMBER") "CAP000028169")
        (field (name "DB_VALUE") "470nF")
        (field (name "DB_TOLERANCE") "5%")
        (field (name "DB_VOLTAGE") "16V")
        (field (name "DB_MANUFACTURER_PART") "KEMET    C0603C474J4RAC")
      )
      (libsource (lib "Database_Libs1") (part "C"))
    )
    (comp (ref "C345")
      (value "C")
      (footprint "SMD_0603_CAPC1608X95N")
      (fields
        (field (name "DB_PART_NUMBER") "CAP000028169")
        (field (name "DB_VALUE") "470nF")
        (field (name "DB_TOLERANCE") "5%")
        (field (name "DB_VOLTAGE") "16V")
        (field (name "DB_MANUFACTURER_PART") "KEMET    C0603C474J4RAC")
      )
      (libsource (lib "Database_Libs1") (part "C"))
    )
    (comp (ref "C346")
      (value "C")
      (footprint "SMD_0603_CAPC1608X95N")
      (fields
        (field (name "DB_PART_NUMBER") "CAP000028169")
        (field (name "DB_VALUE") "470nF")
        (field (name "DB_TOLERANCE") "5%")
        (field (name "DB_VOLTAGE") "16V")
        (field (name "DB_MANUFACTURER_PART") "KEMET    C0603C474J4RAC")
      )
      (libsource (lib "Database_Libs1") (part "C"))
    )
    (comp (ref "C347")
      (value "C")
      (footprint "SMD_0603_CAPC1608X95N")
      (fields
        (field (name "DB_PART_NUMBER") "CAP000028169")
        (field (name "DB_VALUE") "470nF")
        (field (name "DB_TOLERANCE") "5%")
        (field (name "DB_VOLTAGE") "16V")
        (field (name "DB_MANUFACTURER_PART") "KEMET    C0603C474J4RAC")
      )
      (libsource (lib "Database_Libs1") (part "C"))
    )
    (comp (ref "C348")
      (value "C")
      (footprint "SMD_0603_CAPC1608X95N")
      (fields
        (field (name "DB_PART_NUMBER") "CAP000028169")
        (field (name "DB_VALUE") "470nF")
        (field (name "DB_TOLERANCE") "5%")
        (field (name "DB_VOLTAGE") "16V")
        (field (name "DB_MANUFACTURER_PART") "KEMET    C0603C474J4RAC")
      )
      (libsource (lib "Database_Libs1") (part "C"))
    )
    (comp (ref "C349")
      (value "C")
      (footprint "SMD_0603_CAPC1608X95N")
      (fields
        (field (name "DB_PART_NUMBER") "CAP000028169")
        (field (name "DB_VALUE") "470nF")
        (field (name "DB_TOLERANCE") "5%")
        (field (name "DB_VOLTAGE") "16V")
        (field (name "DB_MANUFACTURER_PART") "KEMET    C0603C474J4RAC")
      )
      (libsource (lib "Database_Libs1") (part "C"))
    )
    (comp (ref "C350")
      (value "C")
      (footprint "SMD_0603_CAPC1608X95N")
      (fields
        (field (name "DB_PART_NUMBER") "CAP000028169")
        (field (name "DB_VALUE") "470nF")
        (field (name "DB_TOLERANCE") "5%")
        (field (name "DB_VOLTAGE") "16V")
        (field (name "DB_MANUFACTURER_PART") "KEMET    C0603C474J4RAC")
      )
      (libsource (lib "Database_Libs1") (part "C"))
    )
    (comp (ref "C351")
      (value "C")
      (footprint "SMD_0603_CAPC1608X95N")
      (fields
        (field (name "DB_PART_NUMBER") "CAP000028169")
        (field (name "DB_VALUE") "470nF")
        (field (name "DB_TOLERANCE") "5%")
        (field (name "DB_VOLTAGE") "16V")
        (field (name "DB_MANUFACTURER_PART") "KEMET    C0603C474J4RAC")
      )
      (libsource (lib "Database_Libs1") (part "C"))
    )
    (comp (ref "C352")
      (value "C")
      (footprint "SMD_0603_CAPC1608X95N")
      (fields
        (field (name "DB_PART_NUMBER") "CAP000028169")
        (field (name "DB_VALUE") "470nF")
        (field (name "DB_TOLERANCE") "5%")
        (field (name "DB_VOLTAGE") "16V")
        (field (name "DB_MANUFACTURER_PART") "KEMET    C0603C474J4RAC")
      )
      (libsource (lib "Database_Libs1") (part "C"))
    )
    (comp (ref "C353")
      (value "C")
      (footprint "SMD_0603_CAPC1608X95N")
      (fields
        (field (name "DB_PART_NUMBER") "CAP000028169")
        (field (name "DB_VALUE") "470nF")
        (field (name "DB_TOLERANCE") "5%")
        (field (name "DB_VOLTAGE") "16V")
        (field (name "DB_MANUFACTURER_PART") "KEMET    C0603C474J4RAC")
      )
      (libsource (lib "Database_Libs1") (part "C"))
    )
    (comp (ref "C354")
      (value "C")
      (footprint "SMD_0603_CAPC1608X95N")
      (fields
        (field (name "DB_PART_NUMBER") "CAP000028169")
        (field (name "DB_VALUE") "470nF")
        (field (name "DB_TOLERANCE") "5%")
        (field (name "DB_VOLTAGE") "16V")
        (field (name "DB_MANUFACTURER_PART") "KEMET    C0603C474J4RAC")
      )
      (libsource (lib "Database_Libs1") (part "C"))
    )
    (comp (ref "C355")
      (value "C")
      (footprint "SMD_0603_CAPC1608X95N")
      (fields
        (field (name "DB_PART_NUMBER") "CAP000028169")
        (field (name "DB_VALUE") "470nF")
        (field (name "DB_TOLERANCE") "5%")
        (field (name "DB_VOLTAGE") "16V")
        (field (name "DB_MANUFACTURER_PART") "KEMET    C0603C474J4RAC")
      )
      (libsource (lib "Database_Libs1") (part "C"))
    )
    (comp (ref "C356")
      (value "C")
      (footprint "SMD_0603_CAPC1608X95N")
      (fields
        (field (name "DB_PART_NUMBER") "CAP000028169")
        (field (name "DB_VALUE") "470nF")
        (field (name "DB_TOLERANCE") "5%")
        (field (name "DB_VOLTAGE") "16V")
        (field (name "DB_MANUFACTURER_PART") "KEMET    C0603C474J4RAC")
      )
      (libsource (lib "Database_Libs1") (part "C"))
    )
    (comp (ref "C357")
      (value "C")
      (footprint "SMD_0603_CAPC1608X95N")
      (fields
        (field (name "DB_PART_NUMBER") "CAP000028169")
        (field (name "DB_VALUE") "470nF")
        (field (name "DB_TOLERANCE") "5%")
        (field (name "DB_VOLTAGE") "16V")
        (field (name "DB_MANUFACTURER_PART") "KEMET    C0603C474J4RAC")
      )
      (libsource (lib "Database_Libs1") (part "C"))
    )
    (comp (ref "C358")
      (value "C")
      (footprint "SMD_0603_CAPC1608X95N")
      (fields
        (field (name "DB_PART_NUMBER") "CAP000028169")
        (field (name "DB_VALUE") "470nF")
        (field (name "DB_TOLERANCE") "5%")
        (field (name "DB_VOLTAGE") "16V")
        (field (name "DB_MANUFACTURER_PART") "KEMET    C0603C474J4RAC")
      )
      (libsource (lib "Database_Libs1") (part "C"))
    )
    (comp (ref "C359")
      (value "C")
      (footprint "SMD_0603_CAPC1608X95N")
      (fields
        (field (name "DB_PART_NUMBER") "CAP000028169")
        (field (name "DB_VALUE") "470nF")
        (field (name "DB_TOLERANCE") "5%")
        (field (name "DB_VOLTAGE") "16V")
        (field (name "DB_MANUFACTURER_PART") "KEMET    C0603C474J4RAC")
      )
      (libsource (lib "Database_Libs1") (part "C"))
    )
    (comp (ref "C360")
      (value "C")
      (footprint "SMD_0603_CAPC1608X95N")
      (fields
        (field (name "DB_PART_NUMBER") "CAP000028169")
        (field (name "DB_VALUE") "470nF")
        (field (name "DB_TOLERANCE") "5%")
        (field (name "DB_VOLTAGE") "16V")
        (field (name "DB_MANUFACTURER_PART") "KEMET    C0603C474J4RAC")
      )
      (libsource (lib "Database_Libs1") (part "C"))
    )
    (comp (ref "C361")
      (value "C")
      (footprint "SMD_0603_CAPC1608X95N")
      (fields
        (field (name "DB_PART_NUMBER") "CAP000028169")
        (field (name "DB_VALUE") "470nF")
        (field (name "DB_TOLERANCE") "5%")
        (field (name "DB_VOLTAGE") "16V")
        (field (name "DB_MANUFACTURER_PART") "KEMET    C0603C474J4RAC")
      )
      (libsource (lib "Database_Libs1") (part "C"))
    )
    (comp (ref "C362")
      (value "C")
      (footprint "SMD_0603_CAPC1608X95N")
      (fields
        (field (name "DB_PART_NUMBER") "CAP000028169")
        (field (name "DB_VALUE") "470nF")
        (field (name "DB_TOLERANCE") "5%")
        (field (name "DB_VOLTAGE") "16V")
        (field (name "DB_MANUFACTURER_PART") "KEMET    C0603C474J4RAC")
      )
      (libsource (lib "Database_Libs1") (part "C"))
    )
    (comp (ref "C363")
      (value "C")
      (footprint "SMD_0603_CAPC1608X95N")
      (fields
        (field (name "DB_PART_NUMBER") "CAP000028169")
        (field (name "DB_VALUE") "470nF")
        (field (name "DB_TOLERANCE") "5%")
        (field (name "DB_VOLTAGE") "16V")
        (field (name "DB_MANUFACTURER_PART") "KEMET    C0603C474J4RAC")
      )
      (libsource (lib "Database_Libs1") (part "C"))
    )
    (comp (ref "C364")
      (value "C")
      (footprint "SMD_0603_CAPC1608X95N")
      (fields
        (field (name "DB_PART_NUMBER") "CAP000028169")
        (field (name "DB_VALUE") "470nF")
        (field (name "DB_TOLERANCE") "5%")
        (field (name "DB_VOLTAGE") "16V")
        (field (name "DB_MANUFACTURER_PART") "KEMET    C0603C474J4RAC")
      )
      (libsource (lib "Database_Libs1") (part "C"))
    )
    (comp (ref "C365")
      (value "C")
      (footprint "SMD_0603_CAPC1608X95N")
      (fields
        (field (name "DB_PART_NUMBER") "CAP000028169")
        (field (name "DB_VALUE") "470nF")
        (field (name "DB_TOLERANCE") "5%")
        (field (name "DB_VOLTAGE") "16V")
        (field (name "DB_MANUFACTURER_PART") "KEMET    C0603C474J4RAC")
      )
      (libsource (lib "Database_Libs1") (part "C"))
    )
    (comp (ref "C366")
      (value "C")
      (footprint "SMD_0603_CAPC1608X95N")
      (fields
        (field (name "DB_PART_NUMBER") "CAP000028169")
        (field (name "DB_VALUE") "470nF")
        (field (name "DB_TOLERANCE") "5%")
        (field (name "DB_VOLTAGE") "16V")
        (field (name "DB_MANUFACTURER_PART") "KEMET    C0603C474J4RAC")
      )
      (libsource (lib "Database_Libs1") (part "C"))
    )
    (comp (ref "C367")
      (value "C")
      (footprint "SMD_0603_CAPC1608X95N")
      (fields
        (field (name "DB_PART_NUMBER") "CAP000028169")
        (field (name "DB_VALUE") "470nF")
        (field (name "DB_TOLERANCE") "5%")
        (field (name "DB_VOLTAGE") "16V")
        (field (name "DB_MANUFACTURER_PART") "KEMET    C0603C474J4RAC")
      )
      (libsource (lib "Database_Libs1") (part "C"))
    )
    (comp (ref "C368")
      (value "C")
      (footprint "SMD_0603_CAPC1608X95N")
      (fields
        (field (name "DB_PART_NUMBER") "CAP000028169")
        (field (name "DB_VALUE") "470nF")
        (field (name "DB_TOLERANCE") "5%")
        (field (name "DB_VOLTAGE") "16V")
        (field (name "DB_MANUFACTURER_PART") "KEMET    C0603C474J4RAC")
      )
      (libsource (lib "Database_Libs1") (part "C"))
    )
    (comp (ref "C369")
      (value "C")
      (footprint "SMD_0603_CAPC1608X95N")
      (fields
        (field (name "DB_PART_NUMBER") "CAP000028169")
        (field (name "DB_VALUE") "470nF")
        (field (name "DB_TOLERANCE") "5%")
        (field (name "DB_VOLTAGE") "16V")
        (field (name "DB_MANUFACTURER_PART") "KEMET    C0603C474J4RAC")
      )
      (libsource (lib "Database_Libs1") (part "C"))
    )
    (comp (ref "C370")
      (value "C")
      (footprint "SMD_0603_CAPC1608X95N")
      (fields
        (field (name "DB_PART_NUMBER") "CAP000028169")
        (field (name "DB_VALUE") "470nF")
        (field (name "DB_TOLERANCE") "5%")
        (field (name "DB_VOLTAGE") "16V")
        (field (name "DB_MANUFACTURER_PART") "KEMET    C0603C474J4RAC")
      )
      (libsource (lib "Database_Libs1") (part "C"))
    )
    (comp (ref "C371")
      (value "C")
      (footprint "SMD_0603_CAPC1608X95N")
      (fields
        (field (name "DB_PART_NUMBER") "CAP000028169")
        (field (name "DB_VALUE") "470nF")
        (field (name "DB_TOLERANCE") "5%")
        (field (name "DB_VOLTAGE") "16V")
        (field (name "DB_MANUFACTURER_PART") "KEMET    C0603C474J4RAC")
      )
      (libsource (lib "Database_Libs1") (part "C"))
    )
    (comp (ref "C372")
      (value "C")
      (footprint "SMD_0603_CAPC1608X95N")
      (fields
        (field (name "DB_PART_NUMBER") "CAP000028169")
        (field (name "DB_VALUE") "470nF")
        (field (name "DB_TOLERANCE") "5%")
        (field (name "DB_VOLTAGE") "16V")
        (field (name "DB_MANUFACTURER_PART") "KEMET    C0603C474J4RAC")
      )
      (libsource (lib "Database_Libs1") (part "C"))
    )
    (comp (ref "C373")
      (value "C")
      (footprint "SMD_0603_CAPC1608X95N")
      (fields
        (field (name "DB_PART_NUMBER") "CAP000028169")
        (field (name "DB_VALUE") "470nF")
        (field (name "DB_TOLERANCE") "5%")
        (field (name "DB_VOLTAGE") "16V")
        (field (name "DB_MANUFACTURER_PART") "KEMET    C0603C474J4RAC")
      )
      (libsource (lib "Database_Libs1") (part "C"))
    )
    (comp (ref "C374")
      (value "C")
      (footprint "SMD_0603_CAPC1608X95N")
      (fields
        (field (name "DB_PART_NUMBER") "CAP000028169")
        (field (name "DB_VALUE") "470nF")
        (field (name "DB_TOLERANCE") "5%")
        (field (name "DB_VOLTAGE") "16V")
        (field (name "DB_MANUFACTURER_PART") "KEMET    C0603C474J4RAC")
      )
      (libsource (lib "Database_Libs1") (part "C"))
    )
    (comp (ref "C375")
      (value "C")
      (footprint "SMD_0603_CAPC1608X95N")
      (fields
        (field (name "DB_PART_NUMBER") "CAP000028169")
        (field (name "DB_VALUE") "470nF")
        (field (name "DB_TOLERANCE") "5%")
        (field (name "DB_VOLTAGE") "16V")
        (field (name "DB_MANUFACTURER_PART") "KEMET    C0603C474J4RAC")
      )
      (libsource (lib "Database_Libs1") (part "C"))
    )
    (comp (ref "C376")
      (value "C")
      (footprint "SMD_0603_CAPC1608X95N")
      (fields
        (field (name "DB_PART_NUMBER") "CAP000028169")
        (field (name "DB_VALUE") "470nF")
        (field (name "DB_TOLERANCE") "5%")
        (field (name "DB_VOLTAGE") "16V")
        (field (name "DB_MANUFACTURER_PART") "KEMET    C0603C474J4RAC")
      )
      (libsource (lib "Database_Libs1") (part "C"))
    )
    (comp (ref "C377")
      (value "C")
      (footprint "SMD_0603_CAPC1608X95N")
      (fields
        (field (name "DB_PART_NUMBER") "CAP000028169")
        (field (name "DB_VALUE") "470nF")
        (field (name "DB_TOLERANCE") "5%")
        (field (name "DB_VOLTAGE") "16V")
        (field (name "DB_MANUFACTURER_PART") "KEMET    C0603C474J4RAC")
      )
      (libsource (lib "Database_Libs1") (part "C"))
    )
    (comp (ref "C378")
      (value "C")
      (footprint "SMD_0603_CAPC1608X95N")
      (fields
        (field (name "DB_PART_NUMBER") "CAP000028169")
        (field (name "DB_VALUE") "470nF")
        (field (name "DB_TOLERANCE") "5%")
        (field (name "DB_VOLTAGE") "16V")
        (field (name "DB_MANUFACTURER_PART") "KEMET    C0603C474J4RAC")
      )
      (libsource (lib "Database_Libs1") (part "C"))
    )
    (comp (ref "C379")
      (value "C")
      (footprint "SMD_0603_CAPC1608X95N")
      (fields
        (field (name "DB_PART_NUMBER") "CAP000028169")
        (field (name "DB_VALUE") "470nF")
        (field (name "DB_TOLERANCE") "5%")
        (field (name "DB_VOLTAGE") "16V")
        (field (name "DB_MANUFACTURER_PART") "KEMET    C0603C474J4RAC")
      )
      (libsource (lib "Database_Libs1") (part "C"))
    )
    (comp (ref "C380")
      (value "C")
      (footprint "SMD_0603_CAPC1608X95N")
      (fields
        (field (name "DB_PART_NUMBER") "CAP000028169")
        (field (name "DB_VALUE") "470nF")
        (field (name "DB_TOLERANCE") "5%")
        (field (name "DB_VOLTAGE") "16V")
        (field (name "DB_MANUFACTURER_PART") "KEMET    C0603C474J4RAC")
      )
      (libsource (lib "Database_Libs1") (part "C"))
    )
    (comp (ref "C381")
      (value "C")
      (footprint "SMD_0603_CAPC1608X95N")
      (fields
        (field (name "DB_PART_NUMBER") "CAP000028169")
        (field (name "DB_VALUE") "470nF")
        (field (name "DB_TOLERANCE") "5%")
        (field (name "DB_VOLTAGE") "16V")
        (field (name "DB_MANUFACTURER_PART") "KEMET    C0603C474J4RAC")
      )
      (libsource (lib "Database_Libs1") (part "C"))
    )
    (comp (ref "C382")
      (value "C")
      (footprint "SMD_0603_CAPC1608X95N")
      (fields
        (field (name "DB_PART_NUMBER") "CAP000028169")
        (field (name "DB_VALUE") "470nF")
        (field (name "DB_TOLERANCE") "5%")
        (field (name "DB_VOLTAGE") "16V")
        (field (name "DB_MANUFACTURER_PART") "KEMET    C0603C474J4RAC")
      )
      (libsource (lib "Database_Libs1") (part "C"))
    )
    (comp (ref "C383")
      (value "C")
      (footprint "SMD_0603_CAPC1608X95N")
      (fields
        (field (name "DB_PART_NUMBER") "CAP000028169")
        (field (name "DB_VALUE") "470nF")
        (field (name "DB_TOLERANCE") "5%")
        (field (name "DB_VOLTAGE") "16V")
        (field (name "DB_MANUFACTURER_PART") "KEMET    C0603C474J4RAC")
      )
      (libsource (lib "Database_Libs1") (part "C"))
    )
    (comp (ref "C_1")
      (value "C")
      (footprint "SMD_1210_CAPC3225X279N")
      (fields
        (field (name "DB_PART_NUMBER") "CAP000047355")
        (field (name "DB_VALUE") "220uF")
        (field (name "DB_TOLERANCE") "20%")
        (field (name "DB_VOLTAGE") "6.3V")
        (field (name "DB_MANUFACTURER_PART") "SAMSUNG    CL32A227MQVNNNE")
        (field (name "DB_APPROVED_BY") "VSN")
      )
      (libsource (lib "Database_Libs1") (part "C"))
    )
    (comp (ref "C_2")
      (value "C")
      (footprint "SMD_1210_CAPC3225X279N")
      (fields
        (field (name "DB_PART_NUMBER") "CAP000047355")
        (field (name "DB_VALUE") "220uF")
        (field (name "DB_TOLERANCE") "20%")
        (field (name "DB_VOLTAGE") "6.3V")
        (field (name "DB_MANUFACTURER_PART") "SAMSUNG    CL32A227MQVNNNE")
        (field (name "DB_APPROVED_BY") "VSN")
      )
      (libsource (lib "Database_Libs1") (part "C"))
    )
    (comp (ref "C_3")
      (value "C")
      (footprint "SMD_1210_CAPC3225X279N")
      (fields
        (field (name "DB_PART_NUMBER") "CAP000047355")
        (field (name "DB_VALUE") "220uF")
        (field (name "DB_TOLERANCE") "20%")
        (field (name "DB_VOLTAGE") "6.3V")
        (field (name "DB_MANUFACTURER_PART") "SAMSUNG    CL32A227MQVNNNE")
        (field (name "DB_APPROVED_BY") "VSN")
      )
      (libsource (lib "Database_Libs1") (part "C"))
    )
    (comp (ref "C_4")
      (value "C")
      (footprint "SMD_1210_CAPC3225X279N")
      (fields
        (field (name "DB_PART_NUMBER") "CAP000047355")
        (field (name "DB_VALUE") "220uF")
        (field (name "DB_TOLERANCE") "20%")
        (field (name "DB_VOLTAGE") "6.3V")
        (field (name "DB_MANUFACTURER_PART") "SAMSUNG    CL32A227MQVNNNE")
        (field (name "DB_APPROVED_BY") "VSN")
      )
      (libsource (lib "Database_Libs1") (part "C"))
    )
    (comp (ref "C_5")
      (value "C")
      (footprint "SMD_1210_CAPC3225X279N")
      (fields
        (field (name "DB_PART_NUMBER") "CAP000047355")
        (field (name "DB_VALUE") "220uF")
        (field (name "DB_TOLERANCE") "20%")
        (field (name "DB_VOLTAGE") "6.3V")
        (field (name "DB_MANUFACTURER_PART") "SAMSUNG    CL32A227MQVNNNE")
        (field (name "DB_APPROVED_BY") "VSN")
      )
      (libsource (lib "Database_Libs1") (part "C"))
    )
    (comp (ref "C_6")
      (value "C")
      (footprint "SMD_1210_CAPC3225X279N")
      (fields
        (field (name "DB_PART_NUMBER") "CAP000047355")
        (field (name "DB_VALUE") "220uF")
        (field (name "DB_TOLERANCE") "20%")
        (field (name "DB_VOLTAGE") "6.3V")
        (field (name "DB_MANUFACTURER_PART") "SAMSUNG    CL32A227MQVNNNE")
        (field (name "DB_APPROVED_BY") "VSN")
      )
      (libsource (lib "Database_Libs1") (part "C"))
    )
    (comp (ref "C_7")
      (value "C")
      (footprint "SMD_1210_CAPC3225X279N")
      (fields
        (field (name "DB_PART_NUMBER") "CAP000047355")
        (field (name "DB_VALUE") "220uF")
        (field (name "DB_TOLERANCE") "20%")
        (field (name "DB_VOLTAGE") "6.3V")
        (field (name "DB_MANUFACTURER_PART") "SAMSUNG    CL32A227MQVNNNE")
        (field (name "DB_APPROVED_BY") "VSN")
      )
      (libsource (lib "Database_Libs1") (part "C"))
    )
    (comp (ref "C_8")
      (value "C")
      (footprint "SMD_1210_CAPC3225X279N")
      (fields
        (field (name "DB_PART_NUMBER") "CAP000047355")
        (field (name "DB_VALUE") "220uF")
        (field (name "DB_TOLERANCE") "20%")
        (field (name "DB_VOLTAGE") "6.3V")
        (field (name "DB_MANUFACTURER_PART") "SAMSUNG    CL32A227MQVNNNE")
        (field (name "DB_APPROVED_BY") "VSN")
      )
      (libsource (lib "Database_Libs1") (part "C"))
    )
    (comp (ref "C_9")
      (value "C")
      (footprint "SMD_1210_CAPC3225X279N")
      (fields
        (field (name "DB_PART_NUMBER") "CAP000047355")
        (field (name "DB_VALUE") "220uF")
        (field (name "DB_TOLERANCE") "20%")
        (field (name "DB_VOLTAGE") "6.3V")
        (field (name "DB_MANUFACTURER_PART") "SAMSUNG    CL32A227MQVNNNE")
        (field (name "DB_APPROVED_BY") "VSN")
      )
      (libsource (lib "Database_Libs1") (part "C"))
    )
    (comp (ref "C_10")
      (value "C")
      (footprint "SMD_1210_CAPC3225X279N")
      (fields
        (field (name "DB_PART_NUMBER") "CAP000047355")
        (field (name "DB_VALUE") "220uF")
        (field (name "DB_TOLERANCE") "20%")
        (field (name "DB_VOLTAGE") "6.3V")
        (field (name "DB_MANUFACTURER_PART") "SAMSUNG    CL32A227MQVNNNE")
        (field (name "DB_APPROVED_BY") "VSN")
      )
      (libsource (lib "Database_Libs1") (part "C"))
    )
    (comp (ref "C_11")
      (value "C")
      (footprint "SMD_1210_CAPC3225X279N")
      (fields
        (field (name "DB_PART_NUMBER") "CAP000047355")
        (field (name "DB_VALUE") "220uF")
        (field (name "DB_TOLERANCE") "20%")
        (field (name "DB_VOLTAGE") "6.3V")
        (field (name "DB_MANUFACTURER_PART") "SAMSUNG    CL32A227MQVNNNE")
        (field (name "DB_APPROVED_BY") "VSN")
      )
      (libsource (lib "Database_Libs1") (part "C"))
    )
    (comp (ref "C_12")
      (value "C")
      (footprint "SMD_1210_CAPC3225X279N")
      (fields
        (field (name "DB_PART_NUMBER") "CAP000047355")
        (field (name "DB_VALUE") "220uF")
        (field (name "DB_TOLERANCE") "20%")
        (field (name "DB_VOLTAGE") "6.3V")
        (field (name "DB_MANUFACTURER_PART") "SAMSUNG    CL32A227MQVNNNE")
        (field (name "DB_APPROVED_BY") "VSN")
      )
      (libsource (lib "Database_Libs1") (part "C"))
    )
    (comp (ref "C_13")
      (value "C")
      (footprint "SMD_1210_CAPC3225X279N")
      (fields
        (field (name "DB_PART_NUMBER") "CAP000047355")
        (field (name "DB_VALUE") "220uF")
        (field (name "DB_TOLERANCE") "20%")
        (field (name "DB_VOLTAGE") "6.3V")
        (field (name "DB_MANUFACTURER_PART") "SAMSUNG    CL32A227MQVNNNE")
        (field (name "DB_APPROVED_BY") "VSN")
      )
      (libsource (lib "Database_Libs1") (part "C"))
    )
    (comp (ref "C_14")
      (value "C")
      (footprint "SMD_1210_CAPC3225X279N")
      (fields
        (field (name "DB_PART_NUMBER") "CAP000047355")
        (field (name "DB_VALUE") "220uF")
        (field (name "DB_TOLERANCE") "20%")
        (field (name "DB_VOLTAGE") "6.3V")
        (field (name "DB_MANUFACTURER_PART") "SAMSUNG    CL32A227MQVNNNE")
        (field (name "DB_APPROVED_BY") "VSN")
      )
      (libsource (lib "Database_Libs1") (part "C"))
    )
    (comp (ref "C_15")
      (value "C")
      (footprint "SMD_1210_CAPC3225X279N")
      (fields
        (field (name "DB_PART_NUMBER") "CAP000047355")
        (field (name "DB_VALUE") "220uF")
        (field (name "DB_TOLERANCE") "20%")
        (field (name "DB_VOLTAGE") "6.3V")
        (field (name "DB_MANUFACTURER_PART") "SAMSUNG    CL32A227MQVNNNE")
        (field (name "DB_APPROVED_BY") "VSN")
      )
      (libsource (lib "Database_Libs1") (part "C"))
    )
    (comp (ref "C_16")
      (value "C")
      (footprint "SMD_1210_CAPC3225X279N")
      (fields
        (field (name "DB_PART_NUMBER") "CAP000047355")
        (field (name "DB_VALUE") "220uF")
        (field (name "DB_TOLERANCE") "20%")
        (field (name "DB_VOLTAGE") "6.3V")
        (field (name "DB_MANUFACTURER_PART") "SAMSUNG    CL32A227MQVNNNE")
        (field (name "DB_APPROVED_BY") "VSN")
      )
      (libsource (lib "Database_Libs1") (part "C"))
    )
    (comp (ref "C_17")
      (value "C")
      (footprint "SMD_1210_CAPC3225X279N")
      (fields
        (field (name "DB_PART_NUMBER") "CAP000047355")
        (field (name "DB_VALUE") "220uF")
        (field (name "DB_TOLERANCE") "20%")
        (field (name "DB_VOLTAGE") "6.3V")
        (field (name "DB_MANUFACTURER_PART") "SAMSUNG    CL32A227MQVNNNE")
        (field (name "DB_APPROVED_BY") "VSN")
      )
      (libsource (lib "Database_Libs1") (part "C"))
    )
    (comp (ref "C_18")
      (value "C")
      (footprint "SMD_1210_CAPC3225X279N")
      (fields
        (field (name "DB_PART_NUMBER") "CAP000047355")
        (field (name "DB_VALUE") "220uF")
        (field (name "DB_TOLERANCE") "20%")
        (field (name "DB_VOLTAGE") "6.3V")
        (field (name "DB_MANUFACTURER_PART") "SAMSUNG    CL32A227MQVNNNE")
        (field (name "DB_APPROVED_BY") "VSN")
      )
      (libsource (lib "Database_Libs1") (part "C"))
    )
    (comp (ref "C_19")
      (value "C")
      (footprint "SMD_1210_CAPC3225X279N")
      (fields
        (field (name "DB_PART_NUMBER") "CAP000047355")
        (field (name "DB_VALUE") "220uF")
        (field (name "DB_TOLERANCE") "20%")
        (field (name "DB_VOLTAGE") "6.3V")
        (field (name "DB_MANUFACTURER_PART") "SAMSUNG    CL32A227MQVNNNE")
        (field (name "DB_APPROVED_BY") "VSN")
      )
      (libsource (lib "Database_Libs1") (part "C"))
    )
    (comp (ref "C_20")
      (value "C")
      (footprint "SMD_1210_CAPC3225X279N")
      (fields
        (field (name "DB_PART_NUMBER") "CAP000047355")
        (field (name "DB_VALUE") "220uF")
        (field (name "DB_TOLERANCE") "20%")
        (field (name "DB_VOLTAGE") "6.3V")
        (field (name "DB_MANUFACTURER_PART") "SAMSUNG    CL32A227MQVNNNE")
        (field (name "DB_APPROVED_BY") "VSN")
      )
      (libsource (lib "Database_Libs1") (part "C"))
    )
    (comp (ref "C_21")
      (value "C")
      (footprint "SMD_1210_CAPC3225X279N")
      (fields
        (field (name "DB_PART_NUMBER") "CAP000047355")
        (field (name "DB_VALUE") "220uF")
        (field (name "DB_TOLERANCE") "20%")
        (field (name "DB_VOLTAGE") "6.3V")
        (field (name "DB_MANUFACTURER_PART") "SAMSUNG    CL32A227MQVNNNE")
        (field (name "DB_APPROVED_BY") "VSN")
      )
      (libsource (lib "Database_Libs1") (part "C"))
    )
    (comp (ref "C_22")
      (value "C")
      (footprint "SMD_1210_CAPC3225X279N")
      (fields
        (field (name "DB_PART_NUMBER") "CAP000047355")
        (field (name "DB_VALUE") "220uF")
        (field (name "DB_TOLERANCE") "20%")
        (field (name "DB_VOLTAGE") "6.3V")
        (field (name "DB_MANUFACTURER_PART") "SAMSUNG    CL32A227MQVNNNE")
        (field (name "DB_APPROVED_BY") "VSN")
      )
      (libsource (lib "Database_Libs1") (part "C"))
    )
    (comp (ref "C_23")
      (value "C")
      (footprint "SMD_1210_CAPC3225X279N")
      (fields
        (field (name "DB_PART_NUMBER") "CAP000047355")
        (field (name "DB_VALUE") "220uF")
        (field (name "DB_TOLERANCE") "20%")
        (field (name "DB_VOLTAGE") "6.3V")
        (field (name "DB_MANUFACTURER_PART") "SAMSUNG    CL32A227MQVNNNE")
        (field (name "DB_APPROVED_BY") "VSN")
      )
      (libsource (lib "Database_Libs1") (part "C"))
    )
    (comp (ref "C_24")
      (value "C")
      (footprint "SMD_1210_CAPC3225X279N")
      (fields
        (field (name "DB_PART_NUMBER") "CAP000047355")
        (field (name "DB_VALUE") "220uF")
        (field (name "DB_TOLERANCE") "20%")
        (field (name "DB_VOLTAGE") "6.3V")
        (field (name "DB_MANUFACTURER_PART") "SAMSUNG    CL32A227MQVNNNE")
        (field (name "DB_APPROVED_BY") "VSN")
      )
      (libsource (lib "Database_Libs1") (part "C"))
    )
    (comp (ref "C_25")
      (value "C")
      (footprint "SMD_1210_CAPC3225X279N")
      (fields
        (field (name "DB_PART_NUMBER") "CAP000047355")
        (field (name "DB_VALUE") "220uF")
        (field (name "DB_TOLERANCE") "20%")
        (field (name "DB_VOLTAGE") "6.3V")
        (field (name "DB_MANUFACTURER_PART") "SAMSUNG    CL32A227MQVNNNE")
        (field (name "DB_APPROVED_BY") "VSN")
      )
      (libsource (lib "Database_Libs1") (part "C"))
    )
    (comp (ref "C_26")
      (value "C")
      (footprint "SMD_1210_CAPC3225X279N")
      (fields
        (field (name "DB_PART_NUMBER") "CAP000047355")
        (field (name "DB_VALUE") "220uF")
        (field (name "DB_TOLERANCE") "20%")
        (field (name "DB_VOLTAGE") "6.3V")
        (field (name "DB_MANUFACTURER_PART") "SAMSUNG    CL32A227MQVNNNE")
        (field (name "DB_APPROVED_BY") "VSN")
      )
      (libsource (lib "Database_Libs1") (part "C"))
    )
    (comp (ref "C_27")
      (value "C")
      (footprint "SMD_1210_CAPC3225X279N")
      (fields
        (field (name "DB_PART_NUMBER") "CAP000047355")
        (field (name "DB_VALUE") "220uF")
        (field (name "DB_TOLERANCE") "20%")
        (field (name "DB_VOLTAGE") "6.3V")
        (field (name "DB_MANUFACTURER_PART") "SAMSUNG    CL32A227MQVNNNE")
        (field (name "DB_APPROVED_BY") "VSN")
      )
      (libsource (lib "Database_Libs1") (part "C"))
    )
    (comp (ref "C_28")
      (value "C")
      (footprint "SMD_1210_CAPC3225X279N")
      (fields
        (field (name "DB_PART_NUMBER") "CAP000047355")
        (field (name "DB_VALUE") "220uF")
        (field (name "DB_TOLERANCE") "20%")
        (field (name "DB_VOLTAGE") "6.3V")
        (field (name "DB_MANUFACTURER_PART") "SAMSUNG    CL32A227MQVNNNE")
        (field (name "DB_APPROVED_BY") "VSN")
      )
      (libsource (lib "Database_Libs1") (part "C"))
    )
    (comp (ref "C_29")
      (value "C")
      (footprint "SMD_1210_CAPC3225X279N")
      (fields
        (field (name "DB_PART_NUMBER") "CAP000047355")
        (field (name "DB_VALUE") "220uF")
        (field (name "DB_TOLERANCE") "20%")
        (field (name "DB_VOLTAGE") "6.3V")
        (field (name "DB_MANUFACTURER_PART") "SAMSUNG    CL32A227MQVNNNE")
        (field (name "DB_APPROVED_BY") "VSN")
      )
      (libsource (lib "Database_Libs1") (part "C"))
    )
    (comp (ref "C_30")
      (value "C")
      (footprint "SMD_1210_CAPC3225X279N")
      (fields
        (field (name "DB_PART_NUMBER") "CAP000047355")
        (field (name "DB_VALUE") "220uF")
        (field (name "DB_TOLERANCE") "20%")
        (field (name "DB_VOLTAGE") "6.3V")
        (field (name "DB_MANUFACTURER_PART") "SAMSUNG    CL32A227MQVNNNE")
        (field (name "DB_APPROVED_BY") "VSN")
      )
      (libsource (lib "Database_Libs1") (part "C"))
    )
    (comp (ref "C_31")
      (value "C")
      (footprint "SMD_1210_CAPC3225X279N")
      (fields
        (field (name "DB_PART_NUMBER") "CAP000047355")
        (field (name "DB_VALUE") "220uF")
        (field (name "DB_TOLERANCE") "20%")
        (field (name "DB_VOLTAGE") "6.3V")
        (field (name "DB_MANUFACTURER_PART") "SAMSUNG    CL32A227MQVNNNE")
        (field (name "DB_APPROVED_BY") "VSN")
      )
      (libsource (lib "Database_Libs1") (part "C"))
    )
    (comp (ref "C_32")
      (value "C")
      (footprint "SMD_1210_CAPC3225X279N")
      (fields
        (field (name "DB_PART_NUMBER") "CAP000047355")
        (field (name "DB_VALUE") "220uF")
        (field (name "DB_TOLERANCE") "20%")
        (field (name "DB_VOLTAGE") "6.3V")
        (field (name "DB_MANUFACTURER_PART") "SAMSUNG    CL32A227MQVNNNE")
        (field (name "DB_APPROVED_BY") "VSN")
      )
      (libsource (lib "Database_Libs1") (part "C"))
    )
    (comp (ref "C_33")
      (value "C")
      (footprint "SMD_1210_CAPC3225X279N")
      (fields
        (field (name "DB_PART_NUMBER") "CAP000047355")
        (field (name "DB_VALUE") "220uF")
        (field (name "DB_TOLERANCE") "20%")
        (field (name "DB_VOLTAGE") "6.3V")
        (field (name "DB_MANUFACTURER_PART") "SAMSUNG    CL32A227MQVNNNE")
        (field (name "DB_APPROVED_BY") "VSN")
      )
      (libsource (lib "Database_Libs1") (part "C"))
    )
    (comp (ref "C_34")
      (value "C")
      (footprint "SMD_1210_CAPC3225X279N")
      (fields
        (field (name "DB_PART_NUMBER") "CAP000047355")
        (field (name "DB_VALUE") "220uF")
        (field (name "DB_TOLERANCE") "20%")
        (field (name "DB_VOLTAGE") "6.3V")
        (field (name "DB_MANUFACTURER_PART") "SAMSUNG    CL32A227MQVNNNE")
        (field (name "DB_APPROVED_BY") "VSN")
      )
      (libsource (lib "Database_Libs1") (part "C"))
    )
    (comp (ref "C_35")
      (value "C")
      (footprint "SMD_1210_CAPC3225X279N")
      (fields
        (field (name "DB_PART_NUMBER") "CAP000047355")
        (field (name "DB_VALUE") "220uF")
        (field (name "DB_TOLERANCE") "20%")
        (field (name "DB_VOLTAGE") "6.3V")
        (field (name "DB_MANUFACTURER_PART") "SAMSUNG    CL32A227MQVNNNE")
        (field (name "DB_APPROVED_BY") "VSN")
      )
      (libsource (lib "Database_Libs1") (part "C"))
    )
    (comp (ref "C_36")
      (value "C")
      (footprint "SMD_1210_CAPC3225X279N")
      (fields
        (field (name "DB_PART_NUMBER") "CAP000047355")
        (field (name "DB_VALUE") "220uF")
        (field (name "DB_TOLERANCE") "20%")
        (field (name "DB_VOLTAGE") "6.3V")
        (field (name "DB_MANUFACTURER_PART") "SAMSUNG    CL32A227MQVNNNE")
        (field (name "DB_APPROVED_BY") "VSN")
      )
      (libsource (lib "Database_Libs1") (part "C"))
    )
    (comp (ref "C_37")
      (value "C")
      (footprint "SMD_1210_CAPC3225X279N")
      (fields
        (field (name "DB_PART_NUMBER") "CAP000047355")
        (field (name "DB_VALUE") "220uF")
        (field (name "DB_TOLERANCE") "20%")
        (field (name "DB_VOLTAGE") "6.3V")
        (field (name "DB_MANUFACTURER_PART") "SAMSUNG    CL32A227MQVNNNE")
        (field (name "DB_APPROVED_BY") "VSN")
      )
      (libsource (lib "Database_Libs1") (part "C"))
    )
    (comp (ref "C_38")
      (value "C")
      (footprint "SMD_1210_CAPC3225X279N")
      (fields
        (field (name "DB_PART_NUMBER") "CAP000047355")
        (field (name "DB_VALUE") "220uF")
        (field (name "DB_TOLERANCE") "20%")
        (field (name "DB_VOLTAGE") "6.3V")
        (field (name "DB_MANUFACTURER_PART") "SAMSUNG    CL32A227MQVNNNE")
        (field (name "DB_APPROVED_BY") "VSN")
      )
      (libsource (lib "Database_Libs1") (part "C"))
    )
    (comp (ref "C_39")
      (value "C")
      (footprint "SMD_1210_CAPC3225X279N")
      (fields
        (field (name "DB_PART_NUMBER") "CAP000047355")
        (field (name "DB_VALUE") "220uF")
        (field (name "DB_TOLERANCE") "20%")
        (field (name "DB_VOLTAGE") "6.3V")
        (field (name "DB_MANUFACTURER_PART") "SAMSUNG    CL32A227MQVNNNE")
        (field (name "DB_APPROVED_BY") "VSN")
      )
      (libsource (lib "Database_Libs1") (part "C"))
    )
    (comp (ref "C_40")
      (value "C")
      (footprint "SMD_1210_CAPC3225X279N")
      (fields
        (field (name "DB_PART_NUMBER") "CAP000047355")
        (field (name "DB_VALUE") "220uF")
        (field (name "DB_TOLERANCE") "20%")
        (field (name "DB_VOLTAGE") "6.3V")
        (field (name "DB_MANUFACTURER_PART") "SAMSUNG    CL32A227MQVNNNE")
        (field (name "DB_APPROVED_BY") "VSN")
      )
      (libsource (lib "Database_Libs1") (part "C"))
    )
    (comp (ref "C_41")
      (value "C")
      (footprint "SMD_1210_CAPC3225X279N")
      (fields
        (field (name "DB_PART_NUMBER") "CAP000047355")
        (field (name "DB_VALUE") "220uF")
        (field (name "DB_TOLERANCE") "20%")
        (field (name "DB_VOLTAGE") "6.3V")
        (field (name "DB_MANUFACTURER_PART") "SAMSUNG    CL32A227MQVNNNE")
        (field (name "DB_APPROVED_BY") "VSN")
      )
      (libsource (lib "Database_Libs1") (part "C"))
    )
    (comp (ref "C_42")
      (value "C")
      (footprint "SMD_1210_CAPC3225X279N")
      (fields
        (field (name "DB_PART_NUMBER") "CAP000047355")
        (field (name "DB_VALUE") "220uF")
        (field (name "DB_TOLERANCE") "20%")
        (field (name "DB_VOLTAGE") "6.3V")
        (field (name "DB_MANUFACTURER_PART") "SAMSUNG    CL32A227MQVNNNE")
        (field (name "DB_APPROVED_BY") "VSN")
      )
      (libsource (lib "Database_Libs1") (part "C"))
    )
    (comp (ref "C_43")
      (value "C")
      (footprint "SMD_1210_CAPC3225X279N")
      (fields
        (field (name "DB_PART_NUMBER") "CAP000047355")
        (field (name "DB_VALUE") "220uF")
        (field (name "DB_TOLERANCE") "20%")
        (field (name "DB_VOLTAGE") "6.3V")
        (field (name "DB_MANUFACTURER_PART") "SAMSUNG    CL32A227MQVNNNE")
        (field (name "DB_APPROVED_BY") "VSN")
      )
      (libsource (lib "Database_Libs1") (part "C"))
    )
    (comp (ref "C_44")
      (value "C")
      (footprint "SMD_1210_CAPC3225X279N")
      (fields
        (field (name "DB_PART_NUMBER") "CAP000047355")
        (field (name "DB_VALUE") "220uF")
        (field (name "DB_TOLERANCE") "20%")
        (field (name "DB_VOLTAGE") "6.3V")
        (field (name "DB_MANUFACTURER_PART") "SAMSUNG    CL32A227MQVNNNE")
        (field (name "DB_APPROVED_BY") "VSN")
      )
      (libsource (lib "Database_Libs1") (part "C"))
    )
    (comp (ref "C_45")
      (value "C")
      (footprint "SMD_1210_CAPC3225X279N")
      (fields
        (field (name "DB_PART_NUMBER") "CAP000047355")
        (field (name "DB_VALUE") "220uF")
        (field (name "DB_TOLERANCE") "20%")
        (field (name "DB_VOLTAGE") "6.3V")
        (field (name "DB_MANUFACTURER_PART") "SAMSUNG    CL32A227MQVNNNE")
        (field (name "DB_APPROVED_BY") "VSN")
      )
      (libsource (lib "Database_Libs1") (part "C"))
    )
    (comp (ref "C_46")
      (value "C")
      (footprint "SMD_1210_CAPC3225X279N")
      (fields
        (field (name "DB_PART_NUMBER") "CAP000047355")
        (field (name "DB_VALUE") "220uF")
        (field (name "DB_TOLERANCE") "20%")
        (field (name "DB_VOLTAGE") "6.3V")
        (field (name "DB_MANUFACTURER_PART") "SAMSUNG    CL32A227MQVNNNE")
        (field (name "DB_APPROVED_BY") "VSN")
      )
      (libsource (lib "Database_Libs1") (part "C"))
    )
    (comp (ref "C_47")
      (value "C")
      (footprint "SMD_1210_CAPC3225X279N")
      (fields
        (field (name "DB_PART_NUMBER") "CAP000047355")
        (field (name "DB_VALUE") "220uF")
        (field (name "DB_TOLERANCE") "20%")
        (field (name "DB_VOLTAGE") "6.3V")
        (field (name "DB_MANUFACTURER_PART") "SAMSUNG    CL32A227MQVNNNE")
        (field (name "DB_APPROVED_BY") "VSN")
      )
      (libsource (lib "Database_Libs1") (part "C"))
    )
    (comp (ref "C_48")
      (value "C")
      (footprint "SMD_1210_CAPC3225X279N")
      (fields
        (field (name "DB_PART_NUMBER") "CAP000047355")
        (field (name "DB_VALUE") "220uF")
        (field (name "DB_TOLERANCE") "20%")
        (field (name "DB_VOLTAGE") "6.3V")
        (field (name "DB_MANUFACTURER_PART") "SAMSUNG    CL32A227MQVNNNE")
        (field (name "DB_APPROVED_BY") "VSN")
      )
      (libsource (lib "Database_Libs1") (part "C"))
    )
    (comp (ref "C_49")
      (value "C")
      (footprint "SMD_1210_CAPC3225X279N")
      (fields
        (field (name "DB_PART_NUMBER") "CAP000047355")
        (field (name "DB_VALUE") "220uF")
        (field (name "DB_TOLERANCE") "20%")
        (field (name "DB_VOLTAGE") "6.3V")
        (field (name "DB_MANUFACTURER_PART") "SAMSUNG    CL32A227MQVNNNE")
        (field (name "DB_APPROVED_BY") "VSN")
      )
      (libsource (lib "Database_Libs1") (part "C"))
    )
    (comp (ref "C_50")
      (value "C")
      (footprint "SMD_1210_CAPC3225X279N")
      (fields
        (field (name "DB_PART_NUMBER") "CAP000047355")
        (field (name "DB_VALUE") "220uF")
        (field (name "DB_TOLERANCE") "20%")
        (field (name "DB_VOLTAGE") "6.3V")
        (field (name "DB_MANUFACTURER_PART") "SAMSUNG    CL32A227MQVNNNE")
        (field (name "DB_APPROVED_BY") "VSN")
      )
      (libsource (lib "Database_Libs1") (part "C"))
    )
    (comp (ref "C_51")
      (value "C")
      (footprint "SMD_1210_CAPC3225X279N")
      (fields
        (field (name "DB_PART_NUMBER") "CAP000047355")
        (field (name "DB_VALUE") "220uF")
        (field (name "DB_TOLERANCE") "20%")
        (field (name "DB_VOLTAGE") "6.3V")
        (field (name "DB_MANUFACTURER_PART") "SAMSUNG    CL32A227MQVNNNE")
        (field (name "DB_APPROVED_BY") "VSN")
      )
      (libsource (lib "Database_Libs1") (part "C"))
    )
    (comp (ref "C_52")
      (value "C")
      (footprint "SMD_1210_CAPC3225X279N")
      (fields
        (field (name "DB_PART_NUMBER") "CAP000047355")
        (field (name "DB_VALUE") "220uF")
        (field (name "DB_TOLERANCE") "20%")
        (field (name "DB_VOLTAGE") "6.3V")
        (field (name "DB_MANUFACTURER_PART") "SAMSUNG    CL32A227MQVNNNE")
        (field (name "DB_APPROVED_BY") "VSN")
      )
      (libsource (lib "Database_Libs1") (part "C"))
    )
    (comp (ref "C_53")
      (value "C")
      (footprint "SMD_1210_CAPC3225X279N")
      (fields
        (field (name "DB_PART_NUMBER") "CAP000047355")
        (field (name "DB_VALUE") "220uF")
        (field (name "DB_TOLERANCE") "20%")
        (field (name "DB_VOLTAGE") "6.3V")
        (field (name "DB_MANUFACTURER_PART") "SAMSUNG    CL32A227MQVNNNE")
        (field (name "DB_APPROVED_BY") "VSN")
      )
      (libsource (lib "Database_Libs1") (part "C"))
    )
    (comp (ref "C_54")
      (value "C")
      (footprint "SMD_1210_CAPC3225X279N")
      (fields
        (field (name "DB_PART_NUMBER") "CAP000047355")
        (field (name "DB_VALUE") "220uF")
        (field (name "DB_TOLERANCE") "20%")
        (field (name "DB_VOLTAGE") "6.3V")
        (field (name "DB_MANUFACTURER_PART") "SAMSUNG    CL32A227MQVNNNE")
        (field (name "DB_APPROVED_BY") "VSN")
      )
      (libsource (lib "Database_Libs1") (part "C"))
    )
    (comp (ref "C_55")
      (value "C")
      (footprint "SMD_1210_CAPC3225X279N")
      (fields
        (field (name "DB_PART_NUMBER") "CAP000047355")
        (field (name "DB_VALUE") "220uF")
        (field (name "DB_TOLERANCE") "20%")
        (field (name "DB_VOLTAGE") "6.3V")
        (field (name "DB_MANUFACTURER_PART") "SAMSUNG    CL32A227MQVNNNE")
        (field (name "DB_APPROVED_BY") "VSN")
      )
      (libsource (lib "Database_Libs1") (part "C"))
    )
    (comp (ref "C_56")
      (value "C")
      (footprint "SMD_1210_CAPC3225X279N")
      (fields
        (field (name "DB_PART_NUMBER") "CAP000047355")
        (field (name "DB_VALUE") "220uF")
        (field (name "DB_TOLERANCE") "20%")
        (field (name "DB_VOLTAGE") "6.3V")
        (field (name "DB_MANUFACTURER_PART") "SAMSUNG    CL32A227MQVNNNE")
        (field (name "DB_APPROVED_BY") "VSN")
      )
      (libsource (lib "Database_Libs1") (part "C"))
    )
    (comp (ref "C_57")
      (value "C")
      (footprint "SMD_1210_CAPC3225X279N")
      (fields
        (field (name "DB_PART_NUMBER") "CAP000047355")
        (field (name "DB_VALUE") "220uF")
        (field (name "DB_TOLERANCE") "20%")
        (field (name "DB_VOLTAGE") "6.3V")
        (field (name "DB_MANUFACTURER_PART") "SAMSUNG    CL32A227MQVNNNE")
        (field (name "DB_APPROVED_BY") "VSN")
      )
      (libsource (lib "Database_Libs1") (part "C"))
    )
    (comp (ref "C_58")
      (value "C")
      (footprint "SMD_1210_CAPC3225X279N")
      (fields
        (field (name "DB_PART_NUMBER") "CAP000047355")
        (field (name "DB_VALUE") "220uF")
        (field (name "DB_TOLERANCE") "20%")
        (field (name "DB_VOLTAGE") "6.3V")
        (field (name "DB_MANUFACTURER_PART") "SAMSUNG    CL32A227MQVNNNE")
        (field (name "DB_APPROVED_BY") "VSN")
      )
      (libsource (lib "Database_Libs1") (part "C"))
    )
    (comp (ref "C_59")
      (value "C")
      (footprint "SMD_1210_CAPC3225X279N")
      (fields
        (field (name "DB_PART_NUMBER") "CAP000047355")
        (field (name "DB_VALUE") "220uF")
        (field (name "DB_TOLERANCE") "20%")
        (field (name "DB_VOLTAGE") "6.3V")
        (field (name "DB_MANUFACTURER_PART") "SAMSUNG    CL32A227MQVNNNE")
        (field (name "DB_APPROVED_BY") "VSN")
      )
      (libsource (lib "Database_Libs1") (part "C"))
    )
    (comp (ref "C_60")
      (value "C")
      (footprint "SMD_1210_CAPC3225X279N")
      (fields
        (field (name "DB_PART_NUMBER") "CAP000047355")
        (field (name "DB_VALUE") "220uF")
        (field (name "DB_TOLERANCE") "20%")
        (field (name "DB_VOLTAGE") "6.3V")
        (field (name "DB_MANUFACTURER_PART") "SAMSUNG    CL32A227MQVNNNE")
        (field (name "DB_APPROVED_BY") "VSN")
      )
      (libsource (lib "Database_Libs1") (part "C"))
    )
    (comp (ref "C_61")
      (value "C")
      (footprint "SMD_1210_CAPC3225X279N")
      (fields
        (field (name "DB_PART_NUMBER") "CAP000047355")
        (field (name "DB_VALUE") "220uF")
        (field (name "DB_TOLERANCE") "20%")
        (field (name "DB_VOLTAGE") "6.3V")
        (field (name "DB_MANUFACTURER_PART") "SAMSUNG    CL32A227MQVNNNE")
        (field (name "DB_APPROVED_BY") "VSN")
      )
      (libsource (lib "Database_Libs1") (part "C"))
    )
    (comp (ref "C_62")
      (value "C")
      (footprint "SMD_1210_CAPC3225X279N")
      (fields
        (field (name "DB_PART_NUMBER") "CAP000047355")
        (field (name "DB_VALUE") "220uF")
        (field (name "DB_TOLERANCE") "20%")
        (field (name "DB_VOLTAGE") "6.3V")
        (field (name "DB_MANUFACTURER_PART") "SAMSUNG    CL32A227MQVNNNE")
        (field (name "DB_APPROVED_BY") "VSN")
      )
      (libsource (lib "Database_Libs1") (part "C"))
    )
    (comp (ref "C_63")
      (value "C")
      (footprint "SMD_1210_CAPC3225X279N")
      (fields
        (field (name "DB_PART_NUMBER") "CAP000047355")
        (field (name "DB_VALUE") "220uF")
        (field (name "DB_TOLERANCE") "20%")
        (field (name "DB_VOLTAGE") "6.3V")
        (field (name "DB_MANUFACTURER_PART") "SAMSUNG    CL32A227MQVNNNE")
        (field (name "DB_APPROVED_BY") "VSN")
      )
      (libsource (lib "Database_Libs1") (part "C"))
    )
    (comp (ref "C_64")
      (value "C")
      (footprint "SMD_1210_CAPC3225X279N")
      (fields
        (field (name "DB_PART_NUMBER") "CAP000047355")
        (field (name "DB_VALUE") "220uF")
        (field (name "DB_TOLERANCE") "20%")
        (field (name "DB_VOLTAGE") "6.3V")
        (field (name "DB_MANUFACTURER_PART") "SAMSUNG    CL32A227MQVNNNE")
        (field (name "DB_APPROVED_BY") "VSN")
      )
      (libsource (lib "Database_Libs1") (part "C"))
    )
    (comp (ref "C_65")
      (value "C")
      (footprint "SMD_1210_CAPC3225X279N")
      (fields
        (field (name "DB_PART_NUMBER") "CAP000047355")
        (field (name "DB_VALUE") "220uF")
        (field (name "DB_TOLERANCE") "20%")
        (field (name "DB_VOLTAGE") "6.3V")
        (field (name "DB_MANUFACTURER_PART") "SAMSUNG    CL32A227MQVNNNE")
        (field (name "DB_APPROVED_BY") "VSN")
      )
      (libsource (lib "Database_Libs1") (part "C"))
    )
    (comp (ref "C_66")
      (value "C")
      (footprint "SMD_1210_CAPC3225X279N")
      (fields
        (field (name "DB_PART_NUMBER") "CAP000047355")
        (field (name "DB_VALUE") "220uF")
        (field (name "DB_TOLERANCE") "20%")
        (field (name "DB_VOLTAGE") "6.3V")
        (field (name "DB_MANUFACTURER_PART") "SAMSUNG    CL32A227MQVNNNE")
        (field (name "DB_APPROVED_BY") "VSN")
      )
      (libsource (lib "Database_Libs1") (part "C"))
    )
    (comp (ref "C_67")
      (value "C")
      (footprint "SMD_1210_CAPC3225X279N")
      (fields
        (field (name "DB_PART_NUMBER") "CAP000047355")
        (field (name "DB_VALUE") "220uF")
        (field (name "DB_TOLERANCE") "20%")
        (field (name "DB_VOLTAGE") "6.3V")
        (field (name "DB_MANUFACTURER_PART") "SAMSUNG    CL32A227MQVNNNE")
        (field (name "DB_APPROVED_BY") "VSN")
      )
      (libsource (lib "Database_Libs1") (part "C"))
    )
    (comp (ref "C_68")
      (value "C")
      (footprint "SMD_1210_CAPC3225X279N")
      (fields
        (field (name "DB_PART_NUMBER") "CAP000047355")
        (field (name "DB_VALUE") "220uF")
        (field (name "DB_TOLERANCE") "20%")
        (field (name "DB_VOLTAGE") "6.3V")
        (field (name "DB_MANUFACTURER_PART") "SAMSUNG    CL32A227MQVNNNE")
        (field (name "DB_APPROVED_BY") "VSN")
      )
      (libsource (lib "Database_Libs1") (part "C"))
    )
    (comp (ref "C_69")
      (value "C")
      (footprint "SMD_1210_CAPC3225X279N")
      (fields
        (field (name "DB_PART_NUMBER") "CAP000047355")
        (field (name "DB_VALUE") "220uF")
        (field (name "DB_TOLERANCE") "20%")
        (field (name "DB_VOLTAGE") "6.3V")
        (field (name "DB_MANUFACTURER_PART") "SAMSUNG    CL32A227MQVNNNE")
        (field (name "DB_APPROVED_BY") "VSN")
      )
      (libsource (lib "Database_Libs1") (part "C"))
    )
    (comp (ref "C_70")
      (value "C")
      (footprint "SMD_1210_CAPC3225X279N")
      (fields
        (field (name "DB_PART_NUMBER") "CAP000047355")
        (field (name "DB_VALUE") "220uF")
        (field (name "DB_TOLERANCE") "20%")
        (field (name "DB_VOLTAGE") "6.3V")
        (field (name "DB_MANUFACTURER_PART") "SAMSUNG    CL32A227MQVNNNE")
        (field (name "DB_APPROVED_BY") "VSN")
      )
      (libsource (lib "Database_Libs1") (part "C"))
    )
    (comp (ref "C_71")
      (value "C")
      (footprint "SMD_1210_CAPC3225X279N")
      (fields
        (field (name "DB_PART_NUMBER") "CAP000047355")
        (field (name "DB_VALUE") "220uF")
        (field (name "DB_TOLERANCE") "20%")
        (field (name "DB_VOLTAGE") "6.3V")
        (field (name "DB_MANUFACTURER_PART") "SAMSUNG    CL32A227MQVNNNE")
        (field (name "DB_APPROVED_BY") "VSN")
      )
      (libsource (lib "Database_Libs1") (part "C"))
    )
    (comp (ref "C_72")
      (value "C")
      (footprint "SMD_1210_CAPC3225X279N")
      (fields
        (field (name "DB_PART_NUMBER") "CAP000047355")
        (field (name "DB_VALUE") "220uF")
        (field (name "DB_TOLERANCE") "20%")
        (field (name "DB_VOLTAGE") "6.3V")
        (field (name "DB_MANUFACTURER_PART") "SAMSUNG    CL32A227MQVNNNE")
        (field (name "DB_APPROVED_BY") "VSN")
      )
      (libsource (lib "Database_Libs1") (part "C"))
    )
    (comp (ref "D1")
      (value "D_STKY_DUAL_A1A2CC3")
      (footprint "SMD_SOT23_SOT95P240X120-3N")
      (fields
        (field (name "DB_PART_NUMBER") "DDE000000490")
        (field (name "DB_VALUE") "BAT54C")
        (field (name "DB_MANUFACTURER_PART") "Diodes        BAT54C")
      )
      (libsource (lib "Database_Libs1") (part "D_STKY_DUAL_A1A2CC3"))
    )
    (comp (ref "D2")
      (value "D_STKY_DUAL_A1A2CC3")
      (footprint "SMD_SOT23_SOT95P240X120-3N")
      (fields
        (field (name "DB_PART_NUMBER") "DDE000000490")
        (field (name "DB_VALUE") "BAT54C")
        (field (name "DB_MANUFACTURER_PART") "Diodes        BAT54C")
      )
      (libsource (lib "Database_Libs1") (part "D_STKY_DUAL_A1A2CC3"))
    )
    (comp (ref "D3")
      (value "D_STKY_DUAL_A1A2CC3")
      (footprint "SMD_SOT23_SOT95P240X120-3N")
      (fields
        (field (name "DB_PART_NUMBER") "DDE000000490")
        (field (name "DB_VALUE") "BAT54C")
        (field (name "DB_MANUFACTURER_PART") "Diodes        BAT54C")
      )
      (libsource (lib "Database_Libs1") (part "D_STKY_DUAL_A1A2CC3"))
    )
    (comp (ref "D4")
      (value "Red SML210VT ROHM")
      (footprint "SMD_0805_LED2012X100N")
      (libsource (lib "EPIQ_DND_CIS_Library") (part "LED_2"))
    )
    (comp (ref "D5")
      (value "Green 	SML210MT ROHM")
      (footprint "SMD_0805_LED2012X100N")
      (libsource (lib "EPIQ_DND_CIS_Library") (part "LED_2"))
    )
    (comp (ref "D6")
      (value "Yellow SML210YT ROHM")
      (footprint "SMD_0805_LED2012X100N")
      (libsource (lib "EPIQ_DND_CIS_Library") (part "LED_2"))
    )
    (comp (ref "D7")
      (value "Orange 	SML210DT ROHM")
      (footprint "SMD_0805_LED2012X100N")
      (libsource (lib "EPIQ_DND_CIS_Library") (part "LED_2"))
    )
    (comp (ref "D8")
      (value "D_STKY")
      (footprint "SMD_DO214AC_SMA")
      (fields
        (field (name "DB_PART_NUMBER") "DDE000000580")
        (field (name "DB_VALUE") "B140")
        (field (name "DB_MANUFACTURER_PART") "Diodes        B140")
      )
      (libsource (lib "Database_Libs1") (part "D_STKY"))
    )
    (comp (ref "D9")
      (value "D_TVS_QUAD_C1A2C3C4A5C6")
      (footprint "SMD_SOT457_SOT95P275X110-6N")
      (fields
        (field (name "DB_PART_NUMBER") "DDE000002846")
        (field (name "DB_VALUE") "SMS05T1G")
        (field (name "DB_MANUFACTURER_PART") "ON SEMICONDUCTOR        SMS05T1G")
        (field (name "DB_APPROVED_BY") "VSN")
      )
      (libsource (lib "Database_Libs1") (part "D_TVS_QUAD_C1A2C3C4A5C6"))
    )
    (comp (ref "D10")
      (value "D_STKY")
      (footprint "SMD_DO214AC_SMA")
      (fields
        (field (name "DB_PART_NUMBER") "DDE000000580")
        (field (name "DB_VALUE") "B140")
        (field (name "DB_MANUFACTURER_PART") "Diodes        B140")
      )
      (libsource (lib "Database_Libs1") (part "D_STKY"))
    )
    (comp (ref "D11")
      (value "D_STKY")
      (footprint "SMD_DO214AC_SMA")
      (fields
        (field (name "DB_PART_NUMBER") "DDE000000580")
        (field (name "DB_VALUE") "B140")
        (field (name "DB_MANUFACTURER_PART") "Diodes        B140")
      )
      (libsource (lib "Database_Libs1") (part "D_STKY"))
    )
    (comp (ref "D12")
      (value "D_TVS_UNI")
      (footprint "SMD_DO214AC_SMC")
      (fields
        (field (name "DB_PART_NUMBER") "DDE000001725")
        (field (name "DB_VALUE") "SMCJ12A")
        (field (name "DB_MANUFACTURER_PART") "Diodes        SMCJ12A")
      )
      (libsource (lib "Database_Libs1") (part "D_TVS_UNI"))
    )
    (comp (ref "FB1")
      (value "L_FERRITE_BEAD")
      (footprint "SMD_0805_INDC2012X105N")
      (fields
        (field (name "DB_PART_NUMBER") "IND000000029")
        (field (name "DB_VALUE") "220 Ohms")
        (field (name "DB_CURRENT") "2A")
        (field (name "DB_MANUFACTURER_PART") "MURATA       BLM21PG221SN1D")
        (field (name "DB_APPROVED_BY") "VSN")
      )
      (libsource (lib "Database_Libs1") (part "L_FERRITE_BEAD"))
    )
    (comp (ref "FID1")
      (value "FIDUCIAL")
      (footprint "FID100X200")
      (fields (field (name "DB_PART_NUMBER") "FID000000001"))
      (libsource (lib "Database_Libs1") (part "FIDUCIAL"))
    )
    (comp (ref "FID2")
      (value "FIDUCIAL")
      (footprint "FID100X200")
      (fields (field (name "DB_PART_NUMBER") "FID000000001"))
      (libsource (lib "Database_Libs1") (part "FIDUCIAL"))
    )
    (comp (ref "J1")
      (value "CON_5PINS")
      (footprint "PTH_HDRV05W64P254_1X05")
      (fields
        (field (name "DB_PART_NUMBER") "CON000000006")
        (field (name "DB_VALUE") "CONN PCB 5P M S")
        (field (name "DB_MANUFACTURER_PART") "W+P        143-12-005-00")
        (field (name "DB_APPROVED_BY") "VSN")
      )
      (libsource (lib "Database_Libs1") (part "CON_5PINS"))
    )
    (comp (ref "J2")
      (value "CON_USB_MINI_1")
      (footprint "SMD_CON-CVILUX-CU04-SCM15B0")
      (fields
        (field (name "DB_PART_NUMBER") "CON000000048")
        (field (name "DB_VALUE") "USB MINI")
        (field (name "DB_MANUFACTURER_PART") "CVILUX       CU04-SCM15B0-R0-LF")
        (field (name "DB_APPROVED_BY") "VSN")
      )
      (libsource (lib "Database_Libs1") (part "CON_USB_MINI_1"))
    )
    (comp (ref "J3")
      (value "CON_3PINS")
      (footprint "PTH_CON_HD-351-3P")
      (fields
        (field (name "DB_PART_NUMBER") "CON000000272")
        (field (name "DB_VALUE") "HD-351-3P")
        (field (name "DB_MANUFACTURER_PART") "HOW DER      HD-351-3P")
        (field (name "DB_APPROVED_BY") "VSN")
      )
      (libsource (lib "Database_Libs1") (part "CON_3PINS"))
    )
    (comp (ref "J4")
      (value "CON_2ROWS_6PINS_1")
      (footprint "PTH_CON_WR-MRC4-6P")
      (fields
        (field (name "DB_PART_NUMBER") "CON000000271")
        (field (name "DB_VALUE") "WR-MPC4")
        (field (name "DB_MANUFACTURER_PART") "WE         649 006 295 22")
        (field (name "DB_APPROVED_BY") "VSN")
      )
      (libsource (lib "Database_Libs1") (part "CON_2ROWS_6PINS_1"))
    )
    (comp (ref "J5")
      (value "CON_1PIN")
      (footprint "PTH_MTG400_700")
      (fields
        (field (name "DB_PART_NUMBER") "MTH000000030")
        (field (name "DB_VALUE") "PTH_MTG400_700")
        (field (name "DB_APPROVED_BY") "VSN")
      )
      (libsource (lib "Database_Libs1") (part "CON_1PIN"))
    )
    (comp (ref "J6")
      (value "CON_1PIN")
      (footprint "PTH_MTG400_700")
      (fields
        (field (name "DB_PART_NUMBER") "MTH000000030")
        (field (name "DB_VALUE") "PTH_MTG400_700")
        (field (name "DB_APPROVED_BY") "VSN")
      )
      (libsource (lib "Database_Libs1") (part "CON_1PIN"))
    )
    (comp (ref "J7")
      (value "CON_1PIN")
      (footprint "PTH_MTG400_700")
      (fields
        (field (name "DB_PART_NUMBER") "MTH000000030")
        (field (name "DB_VALUE") "PTH_MTG400_700")
        (field (name "DB_APPROVED_BY") "VSN")
      )
      (libsource (lib "Database_Libs1") (part "CON_1PIN"))
    )
    (comp (ref "J8")
      (value "CON_1PIN")
      (footprint "PTH_MTG400_700")
      (fields
        (field (name "DB_PART_NUMBER") "MTH000000030")
        (field (name "DB_VALUE") "PTH_MTG400_700")
        (field (name "DB_APPROVED_BY") "VSN")
      )
      (libsource (lib "Database_Libs1") (part "CON_1PIN"))
    )
    (comp (ref "J9")
      (value "CON_1PIN")
      (footprint "PTH_MTG400_700")
      (fields
        (field (name "DB_PART_NUMBER") "MTH000000030")
        (field (name "DB_VALUE") "PTH_MTG400_700")
        (field (name "DB_APPROVED_BY") "VSN")
      )
      (libsource (lib "Database_Libs1") (part "CON_1PIN"))
    )
    (comp (ref "J10")
      (value "CON_1PIN")
      (footprint "PTH_MTG400_700")
      (fields
        (field (name "DB_PART_NUMBER") "MTH000000030")
        (field (name "DB_VALUE") "PTH_MTG400_700")
        (field (name "DB_APPROVED_BY") "VSN")
      )
      (libsource (lib "Database_Libs1") (part "CON_1PIN"))
    )
    (comp (ref "J11")
      (value "CON_1PIN")
      (footprint "PTH_MTG400_700")
      (fields
        (field (name "DB_PART_NUMBER") "MTH000000030")
        (field (name "DB_VALUE") "PTH_MTG400_700")
        (field (name "DB_APPROVED_BY") "VSN")
      )
      (libsource (lib "Database_Libs1") (part "CON_1PIN"))
    )
    (comp (ref "J12")
      (value "CON_1PIN")
      (footprint "PTH_MTG400_700")
      (fields
        (field (name "DB_PART_NUMBER") "MTH000000030")
        (field (name "DB_VALUE") "PTH_MTG400_700")
        (field (name "DB_APPROVED_BY") "VSN")
      )
      (libsource (lib "Database_Libs1") (part "CON_1PIN"))
    )
    (comp (ref "J13")
      (value "CON_1PIN")
      (footprint "PTH_MTG400_700")
      (fields
        (field (name "DB_PART_NUMBER") "MTH000000030")
        (field (name "DB_VALUE") "PTH_MTG400_700")
        (field (name "DB_APPROVED_BY") "VSN")
      )
      (libsource (lib "Database_Libs1") (part "CON_1PIN"))
    )
    (comp (ref "J14")
      (value "CON_1PIN")
      (footprint "PTH_MTG400_700")
      (fields
        (field (name "DB_PART_NUMBER") "MTH000000030")
        (field (name "DB_VALUE") "PTH_MTG400_700")
        (field (name "DB_APPROVED_BY") "VSN")
      )
      (libsource (lib "Database_Libs1") (part "CON_1PIN"))
    )
    (comp (ref "J15")
      (value "CON_1PIN")
      (footprint "PTH_MTG400_700")
      (fields
        (field (name "DB_PART_NUMBER") "MTH000000030")
        (field (name "DB_VALUE") "PTH_MTG400_700")
        (field (name "DB_APPROVED_BY") "VSN")
      )
      (libsource (lib "Database_Libs1") (part "CON_1PIN"))
    )
    (comp (ref "L1")
      (value "SLC1480-201MLD")
      (footprint "SMT_INDM135130X800N")
      (libsource (lib "EPIQ_DND_CIS_Library") (part "L"))
    )
    (comp (ref "L2")
      (value "SLC1480-201MLD")
      (footprint "SMT_INDM135130X800N")
      (libsource (lib "EPIQ_DND_CIS_Library") (part "L"))
    )
    (comp (ref "L3")
      (value "SLC1480-201MLD")
      (footprint "SMT_INDM135130X800N")
      (libsource (lib "EPIQ_DND_CIS_Library") (part "L"))
    )
    (comp (ref "Q1")
      (value "MOS_N_D1_S1S2S3G4D5D6D7D8")
      (footprint "SMD_SOIC127P600X110-9AN")
      (fields
        (field (name "DB_PART_NUMBER") "TRA000001604")
        (field (name "DB_VALUE") "AP1RA03GMT-HF-3")
        (field (name "DB_MANUFACTURER_PART") "ADVANCED POWER ELECTRONICS CORP      AP1RA03GMT-HF-3")
        (field (name "DB_APPROVED_BY") "VSN")
      )
      (libsource (lib "Database_Libs1") (part "MOS_N_D1_S1S2S3G4D5D6D7D8"))
    )
    (comp (ref "Q2")
      (value "MOS_N_D1_S1S2S3G4D5D6D7D8")
      (footprint "SMD_SOIC127P600X110-9AN")
      (fields
        (field (name "DB_PART_NUMBER") "TRA000001604")
        (field (name "DB_VALUE") "AP1RA03GMT-HF-3")
        (field (name "DB_MANUFACTURER_PART") "ADVANCED POWER ELECTRONICS CORP      AP1RA03GMT-HF-3")
        (field (name "DB_APPROVED_BY") "VSN")
      )
      (libsource (lib "Database_Libs1") (part "MOS_N_D1_S1S2S3G4D5D6D7D8"))
    )
    (comp (ref "Q3")
      (value "MOS_N_D1_S1S2S3G4D5D6D7D8")
      (footprint "SMD_SOIC127P600X110-9AN")
      (fields
        (field (name "DB_PART_NUMBER") "TRA000001604")
        (field (name "DB_VALUE") "AP1RA03GMT-HF-3")
        (field (name "DB_MANUFACTURER_PART") "ADVANCED POWER ELECTRONICS CORP      AP1RA03GMT-HF-3")
        (field (name "DB_APPROVED_BY") "VSN")
      )
      (libsource (lib "Database_Libs1") (part "MOS_N_D1_S1S2S3G4D5D6D7D8"))
    )
    (comp (ref "Q4")
      (value "MOS_N_D1_S1S2S3G4D5D6D7D8")
      (footprint "SMD_SOIC127P600X110-9AN")
      (fields
        (field (name "DB_PART_NUMBER") "TRA000001604")
        (field (name "DB_VALUE") "AP1RA03GMT-HF-3")
        (field (name "DB_MANUFACTURER_PART") "ADVANCED POWER ELECTRONICS CORP      AP1RA03GMT-HF-3")
        (field (name "DB_APPROVED_BY") "VSN")
      )
      (libsource (lib "Database_Libs1") (part "MOS_N_D1_S1S2S3G4D5D6D7D8"))
    )
    (comp (ref "Q5")
      (value "MOS_N_D1_S1S2S3G4D5D6D7D8")
      (footprint "SMD_SOIC127P600X110-9AN")
      (fields
        (field (name "DB_PART_NUMBER") "TRA000001604")
        (field (name "DB_VALUE") "AP1RA03GMT-HF-3")
        (field (name "DB_MANUFACTURER_PART") "ADVANCED POWER ELECTRONICS CORP      AP1RA03GMT-HF-3")
        (field (name "DB_APPROVED_BY") "VSN")
      )
      (libsource (lib "Database_Libs1") (part "MOS_N_D1_S1S2S3G4D5D6D7D8"))
    )
    (comp (ref "Q6")
      (value "MOS_N_D1_S1S2S3G4D5D6D7D8")
      (footprint "SMD_SOIC127P600X110-9AN")
      (fields
        (field (name "DB_PART_NUMBER") "TRA000001604")
        (field (name "DB_VALUE") "AP1RA03GMT-HF-3")
        (field (name "DB_MANUFACTURER_PART") "ADVANCED POWER ELECTRONICS CORP      AP1RA03GMT-HF-3")
        (field (name "DB_APPROVED_BY") "VSN")
      )
      (libsource (lib "Database_Libs1") (part "MOS_N_D1_S1S2S3G4D5D6D7D8"))
    )
    (comp (ref "Q7")
      (value "MOS_N_D1_S1S2S3G4D5D6D7D8")
      (footprint "SMD_SOIC127P600X110-9AN")
      (fields
        (field (name "DB_PART_NUMBER") "TRA000001604")
        (field (name "DB_VALUE") "AP1RA03GMT-HF-3")
        (field (name "DB_MANUFACTURER_PART") "ADVANCED POWER ELECTRONICS CORP      AP1RA03GMT-HF-3")
        (field (name "DB_APPROVED_BY") "VSN")
      )
      (libsource (lib "Database_Libs1") (part "MOS_N_D1_S1S2S3G4D5D6D7D8"))
    )
    (comp (ref "Q8")
      (value "MOS_N_D1_S1S2S3G4D5D6D7D8")
      (footprint "SMD_SOIC127P600X110-9AN")
      (fields
        (field (name "DB_PART_NUMBER") "TRA000001604")
        (field (name "DB_VALUE") "AP1RA03GMT-HF-3")
        (field (name "DB_MANUFACTURER_PART") "ADVANCED POWER ELECTRONICS CORP      AP1RA03GMT-HF-3")
        (field (name "DB_APPROVED_BY") "VSN")
      )
      (libsource (lib "Database_Libs1") (part "MOS_N_D1_S1S2S3G4D5D6D7D8"))
    )
    (comp (ref "Q9")
      (value "MOS_N_D1_S1S2S3G4D5D6D7D8")
      (footprint "SMD_SOIC127P600X110-9AN")
      (fields
        (field (name "DB_PART_NUMBER") "TRA000001604")
        (field (name "DB_VALUE") "AP1RA03GMT-HF-3")
        (field (name "DB_MANUFACTURER_PART") "ADVANCED POWER ELECTRONICS CORP      AP1RA03GMT-HF-3")
        (field (name "DB_APPROVED_BY") "VSN")
      )
      (libsource (lib "Database_Libs1") (part "MOS_N_D1_S1S2S3G4D5D6D7D8"))
    )
    (comp (ref "R1")
      (value "R")
      (footprint "SMD_0603_RESC1608X55N")
      (fields
        (field (name "DB_PART_NUMBER") "RES000008663")
        (field (name "DB_VALUE") "10k")
        (field (name "DB_TOLERANCE") "1%")
        (field (name "DB_MANUFACTURER_PART") "YAGEO    RC0603FR-0710KL")
        (field (name "DB_APPROVED_BY") "VSN")
      )
      (libsource (lib "Database_Libs1") (part "R"))
    )
    (comp (ref "R2")
      (value "R")
      (footprint "SMD_0603_RESC1608X55N")
      (fields
        (field (name "DB_PART_NUMBER") "RES000008663")
        (field (name "DB_VALUE") "10k")
        (field (name "DB_TOLERANCE") "1%")
        (field (name "DB_MANUFACTURER_PART") "YAGEO    RC0603FR-0710KL")
        (field (name "DB_APPROVED_BY") "VSN")
      )
      (libsource (lib "Database_Libs1") (part "R"))
    )
    (comp (ref "R3")
      (value "R")
      (footprint "SMD_0603_RESC1608X55N")
      (fields
        (field (name "DB_PART_NUMBER") "RES000008663")
        (field (name "DB_VALUE") "10k")
        (field (name "DB_TOLERANCE") "1%")
        (field (name "DB_MANUFACTURER_PART") "YAGEO    RC0603FR-0710KL")
        (field (name "DB_APPROVED_BY") "VSN")
      )
      (libsource (lib "Database_Libs1") (part "R"))
    )
    (comp (ref "R4")
      (value "R")
      (footprint "SMD_0603_RESC1608X55N")
      (fields
        (field (name "DB_PART_NUMBER") "RES000008663")
        (field (name "DB_VALUE") "10k")
        (field (name "DB_TOLERANCE") "1%")
        (field (name "DB_MANUFACTURER_PART") "YAGEO    RC0603FR-0710KL")
        (field (name "DB_APPROVED_BY") "VSN")
      )
      (libsource (lib "Database_Libs1") (part "R"))
    )
    (comp (ref "R5")
      (value "R")
      (footprint "SMD_0603_RESC1608X55N")
      (fields
        (field (name "DB_PART_NUMBER") "RES000008663")
        (field (name "DB_VALUE") "10k")
        (field (name "DB_TOLERANCE") "1%")
        (field (name "DB_MANUFACTURER_PART") "YAGEO    RC0603FR-0710KL")
        (field (name "DB_APPROVED_BY") "VSN")
      )
      (libsource (lib "Database_Libs1") (part "R"))
    )
    (comp (ref "R6")
      (value "R")
      (footprint "SMD_0603_RESC1608X55N")
      (fields
        (field (name "DB_PART_NUMBER") "RES000008663")
        (field (name "DB_VALUE") "10k")
        (field (name "DB_TOLERANCE") "1%")
        (field (name "DB_MANUFACTURER_PART") "YAGEO    RC0603FR-0710KL")
        (field (name "DB_APPROVED_BY") "VSN")
      )
      (libsource (lib "Database_Libs1") (part "R"))
    )
    (comp (ref "R7")
      (value "R")
      (footprint "SMD_0603_RESC1608X55N")
      (fields
        (field (name "DB_PART_NUMBER") "RES000008663")
        (field (name "DB_VALUE") "10k")
        (field (name "DB_TOLERANCE") "1%")
        (field (name "DB_MANUFACTURER_PART") "YAGEO    RC0603FR-0710KL")
        (field (name "DB_APPROVED_BY") "VSN")
      )
      (libsource (lib "Database_Libs1") (part "R"))
    )
    (comp (ref "R8")
      (value "R")
      (footprint "SMD_0603_RESC1608X55N")
      (fields
        (field (name "DB_PART_NUMBER") "RES000008663")
        (field (name "DB_VALUE") "10k")
        (field (name "DB_TOLERANCE") "1%")
        (field (name "DB_MANUFACTURER_PART") "YAGEO    RC0603FR-0710KL")
        (field (name "DB_APPROVED_BY") "VSN")
      )
      (libsource (lib "Database_Libs1") (part "R"))
    )
    (comp (ref "R17")
      (value "R")
      (footprint "SMD_0603_RESC1608X55N")
      (fields
        (field (name "DB_PART_NUMBER") "RES000008663")
        (field (name "DB_VALUE") "10k")
        (field (name "DB_TOLERANCE") "1%")
        (field (name "DB_MANUFACTURER_PART") "YAGEO    RC0603FR-0710KL")
        (field (name "DB_APPROVED_BY") "VSN")
      )
      (libsource (lib "Database_Libs1") (part "R"))
    )
    (comp (ref "R18")
      (value "R")
      (footprint "SMD_0603_RESC1608X55N")
      (fields
        (field (name "DB_PART_NUMBER") "RES000008663")
        (field (name "DB_VALUE") "10k")
        (field (name "DB_TOLERANCE") "1%")
        (field (name "DB_MANUFACTURER_PART") "YAGEO    RC0603FR-0710KL")
        (field (name "DB_APPROVED_BY") "VSN")
      )
      (libsource (lib "Database_Libs1") (part "R"))
    )
    (comp (ref "R19")
      (value "R")
      (footprint "SMD_0603_RESC1608X55N")
      (fields
        (field (name "DB_PART_NUMBER") "RES000008663")
        (field (name "DB_VALUE") "10k")
        (field (name "DB_TOLERANCE") "1%")
        (field (name "DB_MANUFACTURER_PART") "YAGEO    RC0603FR-0710KL")
        (field (name "DB_APPROVED_BY") "VSN")
      )
      (libsource (lib "Database_Libs1") (part "R"))
    )
    (comp (ref "R20")
      (value "R")
      (footprint "SMD_0603_RESC1608X55N")
      (fields
        (field (name "DB_PART_NUMBER") "RES000008663")
        (field (name "DB_VALUE") "10k")
        (field (name "DB_TOLERANCE") "1%")
        (field (name "DB_MANUFACTURER_PART") "YAGEO    RC0603FR-0710KL")
        (field (name "DB_APPROVED_BY") "VSN")
      )
      (libsource (lib "Database_Libs1") (part "R"))
    )
    (comp (ref "R21")
      (value "R")
      (footprint "SMD_0603_RESC1608X55N")
      (fields
        (field (name "DB_PART_NUMBER") "RES000008663")
        (field (name "DB_VALUE") "10k")
        (field (name "DB_TOLERANCE") "1%")
        (field (name "DB_MANUFACTURER_PART") "YAGEO    RC0603FR-0710KL")
        (field (name "DB_APPROVED_BY") "VSN")
      )
      (libsource (lib "Database_Libs1") (part "R"))
    )
    (comp (ref "R22")
      (value "R")
      (footprint "SMD_0603_RESC1608X55N")
      (fields
        (field (name "DB_PART_NUMBER") "RES000008663")
        (field (name "DB_VALUE") "10k")
        (field (name "DB_TOLERANCE") "1%")
        (field (name "DB_MANUFACTURER_PART") "YAGEO    RC0603FR-0710KL")
        (field (name "DB_APPROVED_BY") "VSN")
      )
      (libsource (lib "Database_Libs1") (part "R"))
    )
    (comp (ref "R23")
      (value "R")
      (footprint "SMD_0603_RESC1608X55N")
      (fields
        (field (name "DB_PART_NUMBER") "RES000008663")
        (field (name "DB_VALUE") "10k")
        (field (name "DB_TOLERANCE") "1%")
        (field (name "DB_MANUFACTURER_PART") "YAGEO    RC0603FR-0710KL")
        (field (name "DB_APPROVED_BY") "VSN")
      )
      (libsource (lib "Database_Libs1") (part "R"))
    )
    (comp (ref "R24")
      (value "R")
      (footprint "SMD_0603_RESC1608X55N")
      (fields
        (field (name "DB_PART_NUMBER") "RES000008663")
        (field (name "DB_VALUE") "10k")
        (field (name "DB_TOLERANCE") "1%")
        (field (name "DB_MANUFACTURER_PART") "YAGEO    RC0603FR-0710KL")
        (field (name "DB_APPROVED_BY") "VSN")
      )
      (libsource (lib "Database_Libs1") (part "R"))
    )
    (comp (ref "R25")
      (value "R")
      (footprint "SMD_0603_RESC1608X55N")
      (fields
        (field (name "DB_PART_NUMBER") "RES000006261")
        (field (name "DB_VALUE") "2.4k")
        (field (name "DB_TOLERANCE") "1%")
        (field (name "DB_MANUFACTURER_PART") "YAGEO    RC0603FR-072K4")
      )
      (libsource (lib "Database_Libs1") (part "R"))
    )
    (comp (ref "R26")
      (value "R")
      (footprint "SMD_0603_RESC1608X55N")
      (fields
        (field (name "DB_PART_NUMBER") "RES000008663")
        (field (name "DB_VALUE") "10k")
        (field (name "DB_TOLERANCE") "1%")
        (field (name "DB_MANUFACTURER_PART") "YAGEO    RC0603FR-0710KL")
        (field (name "DB_APPROVED_BY") "VSN")
      )
      (libsource (lib "Database_Libs1") (part "R"))
    )
    (comp (ref "R27")
      (value "R")
      (footprint "SMD_0603_RESC1608X55N")
      (fields
        (field (name "DB_PART_NUMBER") "RES000006220")
        (field (name "DB_VALUE") "47R")
        (field (name "DB_TOLERANCE") "1%")
        (field (name "DB_MANUFACTURER_PART") "YAGEO    RC0603FR-0747R")
      )
      (libsource (lib "Database_Libs1") (part "R"))
    )
    (comp (ref "R30")
      (value "R")
      (footprint "SMD_0603_RESC1608X55N")
      (fields
        (field (name "DB_PART_NUMBER") "RES000006220")
        (field (name "DB_VALUE") "47R")
        (field (name "DB_TOLERANCE") "1%")
        (field (name "DB_MANUFACTURER_PART") "YAGEO    RC0603FR-0747R")
      )
      (libsource (lib "Database_Libs1") (part "R"))
    )
    (comp (ref "R31")
      (value "R")
      (footprint "SMD_0603_RESC1608X55N")
      (fields
        (field (name "DB_PART_NUMBER") "RES000008663")
        (field (name "DB_VALUE") "10k")
        (field (name "DB_TOLERANCE") "1%")
        (field (name "DB_MANUFACTURER_PART") "YAGEO    RC0603FR-0710KL")
        (field (name "DB_APPROVED_BY") "VSN")
      )
      (libsource (lib "Database_Libs1") (part "R"))
    )
    (comp (ref "R32")
      (value "R")
      (footprint "SMD_0603_RESC1608X55N")
      (fields
        (field (name "DB_PART_NUMBER") "RES000008663")
        (field (name "DB_VALUE") "10k")
        (field (name "DB_TOLERANCE") "1%")
        (field (name "DB_MANUFACTURER_PART") "YAGEO    RC0603FR-0710KL")
        (field (name "DB_APPROVED_BY") "VSN")
      )
      (libsource (lib "Database_Libs1") (part "R"))
    )
    (comp (ref "R33")
      (value "R")
      (footprint "SMD_0603_RESC1608X55N")
      (fields
        (field (name "DB_PART_NUMBER") "RES000008926")
        (field (name "DB_VALUE") "0R")
        (field (name "DB_TOLERANCE") "1%")
        (field (name "DB_MANUFACTURER_PART") "YAGEO    AC0603FR-070RL")
        (field (name "DB_APPROVED_BY") "VSN")
      )
      (libsource (lib "Database_Libs1") (part "R"))
    )
    (comp (ref "R42")
      (value "R")
      (footprint "SMD_1206_RESC3216X65N")
      (fields
        (field (name "DB_PART_NUMBER") "RES000007051")
        (field (name "DB_VALUE") "2R")
        (field (name "DB_TOLERANCE") "5%")
        (field (name "DB_MANUFACTURER_PART") "YAGEO    RC1206JR-072R")
      )
      (libsource (lib "Database_Libs1") (part "R"))
    )
    (comp (ref "R43")
      (value "R")
      (footprint "SMD_0603_RESC1608X55N")
      (fields
        (field (name "DB_PART_NUMBER") "RES000008663")
        (field (name "DB_VALUE") "10k")
        (field (name "DB_TOLERANCE") "1%")
        (field (name "DB_MANUFACTURER_PART") "YAGEO    RC0603FR-0710KL")
        (field (name "DB_APPROVED_BY") "VSN")
      )
      (libsource (lib "Database_Libs1") (part "R"))
    )
    (comp (ref "R44")
      (value "R")
      (footprint "SMD_0603_RESC1608X55N")
      (fields
        (field (name "DB_PART_NUMBER") "RES000008663")
        (field (name "DB_VALUE") "10k")
        (field (name "DB_TOLERANCE") "1%")
        (field (name "DB_MANUFACTURER_PART") "YAGEO    RC0603FR-0710KL")
        (field (name "DB_APPROVED_BY") "VSN")
      )
      (libsource (lib "Database_Libs1") (part "R"))
    )
    (comp (ref "R45")
      (value "R")
      (footprint "SMD_0603_RESC1608X55N")
      (fields
        (field (name "DB_PART_NUMBER") "RES000008663")
        (field (name "DB_VALUE") "10k")
        (field (name "DB_TOLERANCE") "1%")
        (field (name "DB_MANUFACTURER_PART") "YAGEO    RC0603FR-0710KL")
        (field (name "DB_APPROVED_BY") "VSN")
      )
      (libsource (lib "Database_Libs1") (part "R"))
    )
    (comp (ref "R46")
      (value "R")
      (footprint "SMD_0603_RESC1608X55N")
      (fields
        (field (name "DB_PART_NUMBER") "RES000008663")
        (field (name "DB_VALUE") "10k")
        (field (name "DB_TOLERANCE") "1%")
        (field (name "DB_MANUFACTURER_PART") "YAGEO    RC0603FR-0710KL")
        (field (name "DB_APPROVED_BY") "VSN")
      )
      (libsource (lib "Database_Libs1") (part "R"))
    )
    (comp (ref "R47")
      (value "R")
      (footprint "SMD_1206_RESC3216X65N")
      (fields
        (field (name "DB_PART_NUMBER") "RES000006922")
        (field (name "DB_VALUE") "100R")
        (field (name "DB_TOLERANCE") "1%")
        (field (name "DB_MANUFACTURER_PART") "YAGEO    RC1206FR-07100R")
      )
      (libsource (lib "Database_Libs1") (part "R"))
    )
    (comp (ref "R48")
      (value "R")
      (footprint "SMD_1206_RESC3216X65N")
      (fields
        (field (name "DB_PART_NUMBER") "RES000008756")
        (field (name "DB_VALUE") "0R")
        (field (name "DB_TOLERANCE") "1%")
        (field (name "DB_MANUFACTURER_PART") "YAGEO    AC1206FR-070RL")
        (field (name "DB_APPROVED_BY") "VSN")
      )
      (libsource (lib "Database_Libs1") (part "R"))
    )
    (comp (ref "R49")
      (value "R")
      (footprint "SMD_1206_RESC3216X65N")
      (fields
        (field (name "DB_PART_NUMBER") "RES000008756")
        (field (name "DB_VALUE") "0R")
        (field (name "DB_TOLERANCE") "1%")
        (field (name "DB_MANUFACTURER_PART") "YAGEO    AC1206FR-070RL")
        (field (name "DB_APPROVED_BY") "VSN")
      )
      (libsource (lib "Database_Libs1") (part "R"))
    )
    (comp (ref "R50")
      (value "R")
      (footprint "SMD_0603_RESC1608X55N")
      (fields
        (field (name "DB_PART_NUMBER") "RES000008663")
        (field (name "DB_VALUE") "10k")
        (field (name "DB_TOLERANCE") "1%")
        (field (name "DB_MANUFACTURER_PART") "YAGEO    RC0603FR-0710KL")
        (field (name "DB_APPROVED_BY") "VSN")
      )
      (libsource (lib "Database_Libs1") (part "R"))
    )
    (comp (ref "R51")
      (value "R")
      (footprint "SMD_0603_RESC1608X55N")
      (fields
        (field (name "DB_PART_NUMBER") "RES000006287")
        (field (name "DB_VALUE") "30k")
        (field (name "DB_TOLERANCE") "1%")
        (field (name "DB_MANUFACTURER_PART") "YAGEO    RC0603FR-0730K")
      )
      (libsource (lib "Database_Libs1") (part "R"))
    )
    (comp (ref "R52")
      (value "R")
      (footprint "SMD_0603_RESC1608X55N")
      (fields
        (field (name "DB_PART_NUMBER") "RES000008663")
        (field (name "DB_VALUE") "10k")
        (field (name "DB_TOLERANCE") "1%")
        (field (name "DB_MANUFACTURER_PART") "YAGEO    RC0603FR-0710KL")
        (field (name "DB_APPROVED_BY") "VSN")
      )
      (libsource (lib "Database_Libs1") (part "R"))
    )
    (comp (ref "R53")
      (value "R")
      (footprint "SMD_0603_RESC1608X55N")
      (fields
        (field (name "DB_PART_NUMBER") "RES000008663")
        (field (name "DB_VALUE") "10k")
        (field (name "DB_TOLERANCE") "1%")
        (field (name "DB_MANUFACTURER_PART") "YAGEO    RC0603FR-0710KL")
        (field (name "DB_APPROVED_BY") "VSN")
      )
      (libsource (lib "Database_Libs1") (part "R"))
    )
    (comp (ref "R54")
      (value "R")
      (footprint "SMD_0603_RESC1608X55N")
      (fields
        (field (name "DB_PART_NUMBER") "RES000008663")
        (field (name "DB_VALUE") "10k")
        (field (name "DB_TOLERANCE") "1%")
        (field (name "DB_MANUFACTURER_PART") "YAGEO    RC0603FR-0710KL")
        (field (name "DB_APPROVED_BY") "VSN")
      )
      (libsource (lib "Database_Libs1") (part "R"))
    )
    (comp (ref "R55")
      (value "R")
      (footprint "SMD_0603_RESC1608X55N")
      (fields
        (field (name "DB_PART_NUMBER") "RES000006287")
        (field (name "DB_VALUE") "30k")
        (field (name "DB_TOLERANCE") "1%")
        (field (name "DB_MANUFACTURER_PART") "YAGEO    RC0603FR-0730K")
      )
      (libsource (lib "Database_Libs1") (part "R"))
    )
    (comp (ref "R64")
      (value "R")
      (footprint "SMD_0603_RESC1608X55N")
      (fields
        (field (name "DB_PART_NUMBER") "RES000008663")
        (field (name "DB_VALUE") "10k")
        (field (name "DB_TOLERANCE") "1%")
        (field (name "DB_MANUFACTURER_PART") "YAGEO    RC0603FR-0710KL")
        (field (name "DB_APPROVED_BY") "VSN")
      )
      (libsource (lib "Database_Libs1") (part "R"))
    )
    (comp (ref "R65")
      (value "R")
      (footprint "SMD_0603_RESC1608X55N")
      (fields
        (field (name "DB_PART_NUMBER") "RES000008663")
        (field (name "DB_VALUE") "10k")
        (field (name "DB_TOLERANCE") "1%")
        (field (name "DB_MANUFACTURER_PART") "YAGEO    RC0603FR-0710KL")
        (field (name "DB_APPROVED_BY") "VSN")
      )
      (libsource (lib "Database_Libs1") (part "R"))
    )
    (comp (ref "R66")
      (value "R")
      (footprint "SMD_0603_RESC1608X55N")
      (fields
        (field (name "DB_PART_NUMBER") "RES000008663")
        (field (name "DB_VALUE") "10k")
        (field (name "DB_TOLERANCE") "1%")
        (field (name "DB_MANUFACTURER_PART") "YAGEO    RC0603FR-0710KL")
        (field (name "DB_APPROVED_BY") "VSN")
      )
      (libsource (lib "Database_Libs1") (part "R"))
    )
    (comp (ref "R67")
      (value "R")
      (footprint "SMD_0603_RESC1608X55N")
      (fields
        (field (name "DB_PART_NUMBER") "RES000008663")
        (field (name "DB_VALUE") "10k")
        (field (name "DB_TOLERANCE") "1%")
        (field (name "DB_MANUFACTURER_PART") "YAGEO    RC0603FR-0710KL")
        (field (name "DB_APPROVED_BY") "VSN")
      )
      (libsource (lib "Database_Libs1") (part "R"))
    )
    (comp (ref "TP1")
      (value "TEST_POINT_1")
      (footprint "SMD_TP_100-254")
      (fields (field (name "DB_PART_NUMBER") "TPO000000001"))
      (libsource (lib "Database_Libs1") (part "TEST_POINT_1"))
    )
    (comp (ref "TP2")
      (value "TEST_POINT_1")
      (footprint "SMD_TP_100-254")
      (fields (field (name "DB_PART_NUMBER") "TPO000000001"))
      (libsource (lib "Database_Libs1") (part "TEST_POINT_1"))
    )
    (comp (ref "TP3")
      (value "TEST_POINT_1")
      (footprint "SMD_TP_100-254")
      (fields (field (name "DB_PART_NUMBER") "TPO000000001"))
      (libsource (lib "Database_Libs1") (part "TEST_POINT_1"))
    )
    (comp (ref "TP4")
      (value "TEST_POINT_1")
      (footprint "SMD_TP_100-254")
      (fields (field (name "DB_PART_NUMBER") "TPO000000001"))
      (libsource (lib "Database_Libs1") (part "TEST_POINT_1"))
    )
    (comp (ref "TP5")
      (value "TEST_POINT_1")
      (footprint "SMD_TP_100-254")
      (fields (field (name "DB_PART_NUMBER") "TPO000000001"))
      (libsource (lib "Database_Libs1") (part "TEST_POINT_1"))
    )
    (comp (ref "TP6")
      (value "TEST_POINT_1")
      (footprint "SMD_TP_100-254")
      (fields (field (name "DB_PART_NUMBER") "TPO000000001"))
      (libsource (lib "Database_Libs1") (part "TEST_POINT_1"))
    )
    (comp (ref "TP7")
      (value "TEST_POINT_1")
      (footprint "SMD_TP_100-254")
      (fields (field (name "DB_PART_NUMBER") "TPO000000001"))
      (libsource (lib "Database_Libs1") (part "TEST_POINT_1"))
    )
    (comp (ref "TP8")
      (value "TEST_POINT_1")
      (footprint "SMD_TP_100-254")
      (fields (field (name "DB_PART_NUMBER") "TPO000000001"))
      (libsource (lib "Database_Libs1") (part "TEST_POINT_1"))
    )
    (comp (ref "TP9")
      (value "TEST_POINT_1")
      (footprint "SMD_TP_100-254")
      (fields (field (name "DB_PART_NUMBER") "TPO000000001"))
      (libsource (lib "Database_Libs1") (part "TEST_POINT_1"))
    )
    (comp (ref "TP10")
      (value "TEST_POINT_1")
      (footprint "SMD_TP_100-254")
      (fields (field (name "DB_PART_NUMBER") "TPO000000001"))
      (libsource (lib "Database_Libs1") (part "TEST_POINT_1"))
    )
    (comp (ref "TP11")
      (value "TEST_POINT_1")
      (footprint "SMD_TP_100-254")
      (fields (field (name "DB_PART_NUMBER") "TPO000000001"))
      (libsource (lib "Database_Libs1") (part "TEST_POINT_1"))
    )
    (comp (ref "TP12")
      (value "TEST_POINT_1")
      (footprint "SMD_TP_100-254")
      (fields (field (name "DB_PART_NUMBER") "TPO000000001"))
      (libsource (lib "Database_Libs1") (part "TEST_POINT_1"))
    )
    (comp (ref "TP13")
      (value "TEST_POINT_1")
      (footprint "SMD_TP_100-254")
      (fields (field (name "DB_PART_NUMBER") "TPO000000001"))
      (libsource (lib "Database_Libs1") (part "TEST_POINT_1"))
    )
    (comp (ref "TP14")
      (value "TEST_POINT_1")
      (footprint "SMD_TP_100-254")
      (fields (field (name "DB_PART_NUMBER") "TPO000000001"))
      (libsource (lib "Database_Libs1") (part "TEST_POINT_1"))
    )
    (comp (ref "TP15")
      (value "TEST_POINT_1")
      (footprint "SMD_TP_100-254")
      (fields (field (name "DB_PART_NUMBER") "TPO000000001"))
      (libsource (lib "Database_Libs1") (part "TEST_POINT_1"))
    )
    (comp (ref "TP16")
      (value "TEST_POINT_1")
      (footprint "SMD_TP_100-254")
      (fields (field (name "DB_PART_NUMBER") "TPO000000001"))
      (libsource (lib "Database_Libs1") (part "TEST_POINT_1"))
    )
    (comp (ref "TP17")
      (value "TEST_POINT_1")
      (footprint "SMD_TP_100-254")
      (fields (field (name "DB_PART_NUMBER") "TPO000000001"))
      (libsource (lib "Database_Libs1") (part "TEST_POINT_1"))
    )
    (comp (ref "TP18")
      (value "TEST_POINT_1")
      (footprint "SMD_TP_100-254")
      (fields (field (name "DB_PART_NUMBER") "TPO000000001"))
      (libsource (lib "Database_Libs1") (part "TEST_POINT_1"))
    )
    (comp (ref "TP19")
      (value "TEST_POINT_1")
      (footprint "SMD_TP_100-254")
      (fields (field (name "DB_PART_NUMBER") "TPO000000001"))
      (libsource (lib "Database_Libs1") (part "TEST_POINT_1"))
    )
    (comp (ref "TP20")
      (value "TEST_POINT_1")
      (footprint "SMD_TP_100-254")
      (fields (field (name "DB_PART_NUMBER") "TPO000000001"))
      (libsource (lib "Database_Libs1") (part "TEST_POINT_1"))
    )
    (comp (ref "TP21")
      (value "TEST_POINT_1")
      (footprint "SMD_TP_100-254")
      (fields (field (name "DB_PART_NUMBER") "TPO000000001"))
      (libsource (lib "Database_Libs1") (part "TEST_POINT_1"))
    )
    (comp (ref "TP22")
      (value "TEST_POINT_1")
      (footprint "SMD_TP_100-254")
      (fields (field (name "DB_PART_NUMBER") "TPO000000001"))
      (libsource (lib "Database_Libs1") (part "TEST_POINT_1"))
    )
    (comp (ref "TP23")
      (value "TEST_POINT_1")
      (footprint "SMD_TP_100-254")
      (fields (field (name "DB_PART_NUMBER") "TPO000000001"))
      (libsource (lib "Database_Libs1") (part "TEST_POINT_1"))
    )
    (comp (ref "TP24")
      (value "TEST_POINT_1")
      (footprint "SMD_TP_100-254")
      (fields (field (name "DB_PART_NUMBER") "TPO000000001"))
      (libsource (lib "Database_Libs1") (part "TEST_POINT_1"))
    )
    (comp (ref "TP25")
      (value "TEST_POINT_1")
      (footprint "SMD_TP_100-254")
      (fields (field (name "DB_PART_NUMBER") "TPO000000001"))
      (libsource (lib "Database_Libs1") (part "TEST_POINT_1"))
    )
    (comp (ref "TP26")
      (value "TEST_POINT_1")
      (footprint "SMD_TP_100-254")
      (fields (field (name "DB_PART_NUMBER") "TPO000000001"))
      (libsource (lib "Database_Libs1") (part "TEST_POINT_1"))
    )
    (comp (ref "TP27")
      (value "TEST_POINT_1")
      (footprint "SMD_TP_100-254")
      (fields (field (name "DB_PART_NUMBER") "TPO000000001"))
      (libsource (lib "Database_Libs1") (part "TEST_POINT_1"))
    )
    (comp (ref "TP28")
      (value "TEST_POINT_1")
      (footprint "SMD_TP_100-254")
      (fields (field (name "DB_PART_NUMBER") "TPO000000001"))
      (libsource (lib "Database_Libs1") (part "TEST_POINT_1"))
    )
    (comp (ref "TP29")
      (value "TEST_POINT_1")
      (footprint "SMD_TP_100-254")
      (fields (field (name "DB_PART_NUMBER") "TPO000000001"))
      (libsource (lib "Database_Libs1") (part "TEST_POINT_1"))
    )
    (comp (ref "TP30")
      (value "TEST_POINT_1")
      (footprint "SMD_TP_100-254")
      (fields (field (name "DB_PART_NUMBER") "TPO000000001"))
      (libsource (lib "Database_Libs1") (part "TEST_POINT_1"))
    )
    (comp (ref "TP31")
      (value "TEST_POINT_1")
      (footprint "SMD_TP_100-254")
      (fields (field (name "DB_PART_NUMBER") "TPO000000001"))
      (libsource (lib "Database_Libs1") (part "TEST_POINT_1"))
    )
    (comp (ref "TP32")
      (value "TEST_POINT_1")
      (footprint "SMD_TP_100-254")
      (fields (field (name "DB_PART_NUMBER") "TPO000000001"))
      (libsource (lib "Database_Libs1") (part "TEST_POINT_1"))
    )
    (comp (ref "TP33")
      (value "TEST_POINT_1")
      (footprint "SMD_TP_100-254")
      (fields (field (name "DB_PART_NUMBER") "TPO000000001"))
      (libsource (lib "Database_Libs1") (part "TEST_POINT_1"))
    )
    (comp (ref "TP34")
      (value "TEST_POINT_1")
      (footprint "SMD_TP_100-254")
      (fields (field (name "DB_PART_NUMBER") "TPO000000001"))
      (libsource (lib "Database_Libs1") (part "TEST_POINT_1"))
    )
    (comp (ref "TP35")
      (value "TEST_POINT_1")
      (footprint "SMD_TP_100-254")
      (fields (field (name "DB_PART_NUMBER") "TPO000000001"))
      (libsource (lib "Database_Libs1") (part "TEST_POINT_1"))
    )
    (comp (ref "TP36")
      (value "TEST_POINT_1")
      (footprint "SMD_TP_100-254")
      (fields (field (name "DB_PART_NUMBER") "TPO000000001"))
      (libsource (lib "Database_Libs1") (part "TEST_POINT_1"))
    )
    (comp (ref "TP37")
      (value "TEST_POINT_1")
      (footprint "SMD_TP_100-254")
      (fields (field (name "DB_PART_NUMBER") "TPO000000001"))
      (libsource (lib "Database_Libs1") (part "TEST_POINT_1"))
    )
    (comp (ref "TP38")
      (value "TEST_POINT_1")
      (footprint "SMD_TP_100-254")
      (fields (field (name "DB_PART_NUMBER") "TPO000000001"))
      (libsource (lib "Database_Libs1") (part "TEST_POINT_1"))
    )
    (comp (ref "TP39")
      (value "TEST_POINT_1")
      (footprint "SMD_TP_100-254")
      (fields (field (name "DB_PART_NUMBER") "TPO000000001"))
      (libsource (lib "Database_Libs1") (part "TEST_POINT_1"))
    )
    (comp (ref "TP40")
      (value "TEST_POINT_1")
      (footprint "SMD_TP_100-254")
      (fields (field (name "DB_PART_NUMBER") "TPO000000001"))
      (libsource (lib "Database_Libs1") (part "TEST_POINT_1"))
    )
    (comp (ref "TP41")
      (value "TEST_POINT_1")
      (footprint "SMD_TP_100-254")
      (fields (field (name "DB_PART_NUMBER") "TPO000000001"))
      (libsource (lib "Database_Libs1") (part "TEST_POINT_1"))
    )
    (comp (ref "TP42")
      (value "TEST_POINT_1")
      (footprint "SMD_TP_100-254")
      (fields (field (name "DB_PART_NUMBER") "TPO000000001"))
      (libsource (lib "Database_Libs1") (part "TEST_POINT_1"))
    )
    (comp (ref "TP43")
      (value "TEST_POINT_1")
      (footprint "SMD_TP_100-254")
      (fields (field (name "DB_PART_NUMBER") "TPO000000001"))
      (libsource (lib "Database_Libs1") (part "TEST_POINT_1"))
    )
    (comp (ref "TP44")
      (value "TEST_POINT_1")
      (footprint "SMD_TP_100-254")
      (fields (field (name "DB_PART_NUMBER") "TPO000000001"))
      (libsource (lib "Database_Libs1") (part "TEST_POINT_1"))
    )
    (comp (ref "TP45")
      (value "TEST_POINT_1")
      (footprint "SMD_TP_100-254")
      (fields (field (name "DB_PART_NUMBER") "TPO000000001"))
      (libsource (lib "Database_Libs1") (part "TEST_POINT_1"))
    )
    (comp (ref "TP46")
      (value "TEST_POINT_1")
      (footprint "SMD_TP_100-254")
      (fields (field (name "DB_PART_NUMBER") "TPO000000001"))
      (libsource (lib "Database_Libs1") (part "TEST_POINT_1"))
    )
    (comp (ref "TP47")
      (value "TEST_POINT_1")
      (footprint "SMD_TP_100-254")
      (fields (field (name "DB_PART_NUMBER") "TPO000000001"))
      (libsource (lib "Database_Libs1") (part "TEST_POINT_1"))
    )
    (comp (ref "TP48")
      (value "TEST_POINT_1")
      (footprint "SMD_TP_100-254")
      (fields (field (name "DB_PART_NUMBER") "TPO000000001"))
      (libsource (lib "Database_Libs1") (part "TEST_POINT_1"))
    )
    (comp (ref "TP49")
      (value "TEST_POINT_1")
      (footprint "SMD_TP_100-254")
      (fields (field (name "DB_PART_NUMBER") "TPO000000001"))
      (libsource (lib "Database_Libs1") (part "TEST_POINT_1"))
    )
    (comp (ref "TP50")
      (value "TEST_POINT_1")
      (footprint "SMD_TP_100-254")
      (fields (field (name "DB_PART_NUMBER") "TPO000000001"))
      (libsource (lib "Database_Libs1") (part "TEST_POINT_1"))
    )
    (comp (ref "TP51")
      (value "TEST_POINT_1")
      (footprint "SMD_TP_100-254")
      (fields (field (name "DB_PART_NUMBER") "TPO000000001"))
      (libsource (lib "Database_Libs1") (part "TEST_POINT_1"))
    )
    (comp (ref "TP52")
      (value "TEST_POINT_1")
      (footprint "SMD_TP_100-254")
      (fields (field (name "DB_PART_NUMBER") "TPO000000001"))
      (libsource (lib "Database_Libs1") (part "TEST_POINT_1"))
    )
    (comp (ref "TP53")
      (value "TEST_POINT_1")
      (footprint "SMD_TP_100-254")
      (fields (field (name "DB_PART_NUMBER") "TPO000000001"))
      (libsource (lib "Database_Libs1") (part "TEST_POINT_1"))
    )
    (comp (ref "TP54")
      (value "TEST_POINT_1")
      (footprint "SMD_TP_100-254")
      (fields (field (name "DB_PART_NUMBER") "TPO000000001"))
      (libsource (lib "Database_Libs1") (part "TEST_POINT_1"))
    )
    (comp (ref "U1")
      (value "IC_LTC4449")
      (footprint "SMD_SON45P300X200X80-9N")
      (fields
        (field (name "DB_PART_NUMBER") "DRV000000079")
        (field (name "DB_VALUE") "LTC4449EDCB#TRPBF")
        (field (name "DB_MANUFACTURER_PART") "LINEAR       LTC4449EDCB#TRPBF")
        (field (name "DB_APPROVED_BY") "VSN")
      )
      (libsource (lib "Database_Libs1") (part "IC_LTC4449"))
    )
    (comp (ref "U2")
      (value "IC_LTC4449")
      (footprint "SMD_SON45P300X200X80-9N")
      (fields
        (field (name "DB_PART_NUMBER") "DRV000000079")
        (field (name "DB_VALUE") "LTC4449EDCB#TRPBF")
        (field (name "DB_MANUFACTURER_PART") "LINEAR       LTC4449EDCB#TRPBF")
        (field (name "DB_APPROVED_BY") "VSN")
      )
      (libsource (lib "Database_Libs1") (part "IC_LTC4449"))
    )
    (comp (ref "U3")
      (value "IC_LTC4449")
      (footprint "SMD_SON45P300X200X80-9N")
      (fields
        (field (name "DB_PART_NUMBER") "DRV000000079")
        (field (name "DB_VALUE") "LTC4449EDCB#TRPBF")
        (field (name "DB_MANUFACTURER_PART") "LINEAR       LTC4449EDCB#TRPBF")
        (field (name "DB_APPROVED_BY") "VSN")
      )
      (libsource (lib "Database_Libs1") (part "IC_LTC4449"))
    )
    (comp (ref "U4")
      (value "GC3355Q64")
      (footprint "SMT_QFN40P800X800X90-65N")
      (description "GridSeed")
      (libsource (lib "altium-import") (part "root_0__*"))
    )
    (comp (ref "U5")
      (value "GC3355Q64")
      (footprint "SMT_QFN40P800X800X90-65N")
      (description "GridSeed")
      (libsource (lib "altium-import") (part "root_0__*"))
    )
    (comp (ref "U6")
      (value "GC3355Q64")
      (footprint "SMT_QFN40P800X800X90-65N")
      (description "GridSeed")
      (libsource (lib "altium-import") (part "root_0__*"))
    )
    (comp (ref "U7")
      (value "GC3355Q64")
      (footprint "SMT_QFN40P800X800X90-65N")
      (description "GridSeed")
      (libsource (lib "altium-import") (part "root_0__*"))
    )
    (comp (ref "U8")
      (value "IC_DSPIC33EP256MU806-QFN64")
      (footprint "SMD_QFP50P1200X1200X120-64N")
      (fields
        (field (name "DB_PART_NUMBER") "MCU000000070")
        (field (name "DB_VALUE") "dsPIC33EP256MU806")
        (field (name "DB_MANUFACTURER_PART") "MICROCHIP        DSPIC33EP256MU806-E/PT")
        (field (name "DB_APPROVED_BY") "VSN")
      )
      (libsource (lib "Database_Libs1") (part "IC_DSPIC33EP256MU806-QFN64"))
    )
    (comp (ref "U9")
      (value "GC3355Q64")
      (footprint "SMT_QFN40P800X800X90-65N")
      (description "GridSeed")
      (libsource (lib "altium-import") (part "root_0__*"))
    )
    (comp (ref "U10")
      (value "GC3355Q64")
      (footprint "SMT_QFN40P800X800X90-65N")
      (description "GridSeed")
      (libsource (lib "altium-import") (part "root_0__*"))
    )
    (comp (ref "U11")
      (value "GC3355Q64")
      (footprint "SMT_QFN40P800X800X90-65N")
      (description "GridSeed")
      (libsource (lib "altium-import") (part "root_0__*"))
    )
    (comp (ref "U12")
      (value "GC3355Q64")
      (footprint "SMT_QFN40P800X800X90-65N")
      (description "GridSeed")
      (libsource (lib "altium-import") (part "root_0__*"))
    )
    (comp (ref "U13")
      (value "(OPT) LM7805")
      (footprint "SMD_SOIC127P600X175-8N")
      (fields
        (field (name "DB_PART_NUMBER") "PSU000000125")
        (field (name "DB_VALUE") "AP78L05SG-13")
        (field (name "DB_MANUFACTURER_PART") "DIODES        AP78L05SG-13")
        (field (name "DB_APPROVED_BY") "VSN")
      )
      (libsource (lib "Database_Libs1") (part "IC_LM2931AD-5.0R2G_SO-8"))
    )
    (comp (ref "U14")
      (value "IC_TLV70033QDDCRQ1")
      (footprint "SMD_SOT95P280X135-5N")
      (fields
        (field (name "DB_PART_NUMBER") "PSU000000126")
        (field (name "DB_VALUE") "BU33TD3WG-TR")
        (field (name "DB_MANUFACTURER_PART") "ROHM     BU33TD3WG-TR")
        (field (name "DB_APPROVED_BY") "VSN")
      )
      (libsource (lib "Database_Libs1") (part "IC_TLV70033QDDCRQ1"))
    )
    (comp (ref "U15")
      (value "IC_BDXXKA5WF")
      (footprint "SMD_SOIC127P620X160-8N")
      (fields
        (field (name "DB_PART_NUMBER") "PSU000000127")
        (field (name "DB_VALUE") "BD33KA5WF-E2")
        (field (name "DB_MANUFACTURER_PART") "ROHM        BD33KA5WF-E2")
        (field (name "DB_APPROVED_BY") "VSN")
      )
      (libsource (lib "Database_Libs1") (part "IC_BDXXKA5WF"))
    )
    (comp (ref "U16")
      (value "IC_IN1OUT3GND4")
      (footprint "SMD_TO254P1542X460-3_4N")
      (fields
        (field (name "DB_PART_NUMBER") "PSU000000129")
        (field (name "DB_VALUE") "L7805CD2T-TR")
        (field (name "DB_MANUFACTURER_PART") "ST       L7805CD2T-TR")
        (field (name "DB_APPROVED_BY") "VSN")
      )
      (libsource (lib "Database_Libs1") (part "IC_IN1OUT3GND4"))
    )
    (comp (ref "U17")
      (value "IC_VIN1GND4VOUT3")
      (footprint "SMD_TO229P991X239-4N_DPAK")
      (fields
        (field (name "DB_PART_NUMBER") "PSU000000031")
        (field (name "DB_VALUE") "MC78M05BDTRKG")
        (field (name "DB_MANUFACTURER_PART") "ON Semiconductor       MC78M05BDTRKG")
        (field (name "DB_APPROVED_BY") "VSN")
      )
      (libsource (lib "Database_Libs1") (part "IC_VIN1GND4VOUT3"))
    )
    (comp (ref "U18")
      (value "GC3355Q64")
      (footprint "SMT_QFN40P800X800X90-65N")
      (description "GridSeed")
      (libsource (lib "altium-import") (part "root_0__*"))
    )
    (comp (ref "U19")
      (value "GC3355Q64")
      (footprint "SMT_QFN40P800X800X90-65N")
      (description "GridSeed")
      (libsource (lib "altium-import") (part "root_0__*"))
    )
    (comp (ref "U20")
      (value "GC3355Q64")
      (footprint "SMT_QFN40P800X800X90-65N")
      (description "GridSeed")
      (libsource (lib "altium-import") (part "root_0__*"))
    )
    (comp (ref "U21")
      (value "GC3355Q64")
      (footprint "SMT_QFN40P800X800X90-65N")
      (description "GridSeed")
      (libsource (lib "altium-import") (part "root_0__*"))
    )
    (comp (ref "U22")
      (value "IC_BD00KA5WF")
      (footprint "SMD_SOIC127P620X160-8N")
      (fields
        (field (name "DB_PART_NUMBER") "PSU000000128")
        (field (name "DB_VALUE") "BD00KA5WF-E2")
        (field (name "DB_MANUFACTURER_PART") "ROHM        BD00KA5WF-E2")
        (field (name "DB_APPROVED_BY") "VSN")
      )
      (libsource (lib "Database_Libs1") (part "IC_BD00KA5WF"))
    )
    (comp (ref "U23")
      (value "IC_BD00KA5WF")
      (footprint "SMD_SOIC127P620X160-8N")
      (fields
        (field (name "DB_PART_NUMBER") "PSU000000128")
        (field (name "DB_VALUE") "BD00KA5WF-E2")
        (field (name "DB_MANUFACTURER_PART") "ROHM        BD00KA5WF-E2")
        (field (name "DB_APPROVED_BY") "VSN")
      )
      (libsource (lib "Database_Libs1") (part "IC_BD00KA5WF"))
    )
    (comp (ref "U24")
      (value "GC3355Q64")
      (footprint "SMT_QFN40P800X800X90-65N")
      (description "GridSeed")
      (libsource (lib "altium-import") (part "root_0__*"))
    )
    (comp (ref "U25")
      (value "GC3355Q64")
      (footprint "SMT_QFN40P800X800X90-65N")
      (description "GridSeed")
      (libsource (lib "altium-import") (part "root_0__*"))
    )
    (comp (ref "U26")
      (value "GC3355Q64")
      (footprint "SMT_QFN40P800X800X90-65N")
      (description "GridSeed")
      (libsource (lib "altium-import") (part "root_0__*"))
    )
    (comp (ref "U27")
      (value "GC3355Q64")
      (footprint "SMT_QFN40P800X800X90-65N")
      (description "GridSeed")
      (libsource (lib "altium-import") (part "root_0__*"))
    )
    (comp (ref "Y1")
      (value "XTAL")
      (footprint "SMD_HC49_XTAL1140X480X420N")
      (fields
        (field (name "DB_PART_NUMBER") "OSC000000012")
        (field (name "DB_VALUE") "4.00MHz HC49/4HSMX")
        (field (name "DB_MANUFACTURER_PART") "IQD       4.00MHz HC49/4HSMX")
        (field (name "DB_APPROVED_BY") "VSN")
      )
      (libsource (lib "Database_Libs1") (part "XTAL"))
    )
  )
  (nets
    (net (code "1") (name "/1V") (class "Default")
      (node (ref "C118") (pin "2") (pinfunction "2_2") (pintype "passive"))
      (node (ref "C119") (pin "2") (pinfunction "2_2") (pintype "passive"))
      (node (ref "C12") (pin "2") (pinfunction "2_2") (pintype "passive"))
      (node (ref "C121") (pin "2") (pinfunction "2_2") (pintype "passive"))
      (node (ref "C123") (pin "2") (pinfunction "2_2") (pintype "passive"))
      (node (ref "C124") (pin "2") (pinfunction "2_2") (pintype "passive"))
      (node (ref "C126") (pin "2") (pinfunction "2_2") (pintype "passive"))
      (node (ref "C128") (pin "2") (pinfunction "2_2") (pintype "passive"))
      (node (ref "C129") (pin "2") (pinfunction "2_2") (pintype "passive"))
      (node (ref "C13") (pin "2") (pinfunction "2_2") (pintype "passive"))
      (node (ref "C131") (pin "2") (pinfunction "2_2") (pintype "passive"))
      (node (ref "C133") (pin "2") (pinfunction "2_2") (pintype "passive"))
      (node (ref "C134") (pin "2") (pinfunction "2_2") (pintype "passive"))
      (node (ref "C136") (pin "2") (pinfunction "2_2") (pintype "passive"))
      (node (ref "C14") (pin "2") (pinfunction "2_2") (pintype "passive"))
      (node (ref "C140") (pin "2") (pinfunction "2_2") (pintype "passive"))
      (node (ref "C141") (pin "2") (pinfunction "2_2") (pintype "passive"))
      (node (ref "C142") (pin "2") (pinfunction "2_2") (pintype "passive"))
      (node (ref "C143") (pin "2") (pinfunction "2_2") (pintype "passive"))
      (node (ref "C144") (pin "2") (pinfunction "2_2") (pintype "passive"))
      (node (ref "C145") (pin "2") (pinfunction "2_2") (pintype "passive"))
      (node (ref "C146") (pin "2") (pinfunction "2_2") (pintype "passive"))
      (node (ref "C147") (pin "2") (pinfunction "2_2") (pintype "passive"))
      (node (ref "C148") (pin "2") (pinfunction "2_2") (pintype "passive"))
      (node (ref "C149") (pin "2") (pinfunction "2_2") (pintype "passive"))
      (node (ref "C150") (pin "2") (pinfunction "2_2") (pintype "passive"))
      (node (ref "C151") (pin "2") (pinfunction "2_2") (pintype "passive"))
      (node (ref "C152") (pin "2") (pinfunction "2_2") (pintype "passive"))
      (node (ref "C153") (pin "2") (pinfunction "2_2") (pintype "passive"))
      (node (ref "C154") (pin "2") (pinfunction "2_2") (pintype "passive"))
      (node (ref "C155") (pin "2") (pinfunction "2_2") (pintype "passive"))
      (node (ref "C156") (pin "2") (pinfunction "2_2") (pintype "passive"))
      (node (ref "C157") (pin "2") (pinfunction "2_2") (pintype "passive"))
      (node (ref "C158") (pin "2") (pinfunction "2_2") (pintype "passive"))
      (node (ref "C159") (pin "2") (pinfunction "2_2") (pintype "passive"))
      (node (ref "C160") (pin "2") (pinfunction "2_2") (pintype "passive"))
      (node (ref "C161") (pin "2") (pinfunction "2_2") (pintype "passive"))
      (node (ref "C162") (pin "2") (pinfunction "2_2") (pintype "passive"))
      (node (ref "C163") (pin "2") (pinfunction "2_2") (pintype "passive"))
      (node (ref "C17") (pin "2") (pinfunction "2_2") (pintype "passive"))
      (node (ref "C175") (pin "2") (pinfunction "2_2") (pintype "passive"))
      (node (ref "C176") (pin "2") (pinfunction "2_2") (pintype "passive"))
      (node (ref "C177") (pin "2") (pinfunction "2_2") (pintype "passive"))
      (node (ref "C179") (pin "2") (pinfunction "2_2") (pintype "passive"))
      (node (ref "C18") (pin "2") (pinfunction "2_2") (pintype "passive"))
      (node (ref "C180") (pin "2") (pinfunction "2_2") (pintype "passive"))
      (node (ref "C181") (pin "2") (pinfunction "2_2") (pintype "passive"))
      (node (ref "C183") (pin "2") (pinfunction "2_2") (pintype "passive"))
      (node (ref "C184") (pin "2") (pinfunction "2_2") (pintype "passive"))
      (node (ref "C185") (pin "2") (pinfunction "2_2") (pintype "passive"))
      (node (ref "C187") (pin "2") (pinfunction "2_2") (pintype "passive"))
      (node (ref "C188") (pin "2") (pinfunction "2_2") (pintype "passive"))
      (node (ref "C189") (pin "2") (pinfunction "2_2") (pintype "passive"))
      (node (ref "C19") (pin "2") (pinfunction "2_2") (pintype "passive"))
      (node (ref "C22") (pin "2") (pinfunction "2_2") (pintype "passive"))
      (node (ref "C227") (pin "2") (pinfunction "2_2") (pintype "passive"))
      (node (ref "C228") (pin "2") (pinfunction "2_2") (pintype "passive"))
      (node (ref "C23") (pin "2") (pinfunction "2_2") (pintype "passive"))
      (node (ref "C230") (pin "2") (pinfunction "2_2") (pintype "passive"))
      (node (ref "C232") (pin "2") (pinfunction "2_2") (pintype "passive"))
      (node (ref "C233") (pin "2") (pinfunction "2_2") (pintype "passive"))
      (node (ref "C235") (pin "2") (pinfunction "2_2") (pintype "passive"))
      (node (ref "C237") (pin "2") (pinfunction "2_2") (pintype "passive"))
      (node (ref "C238") (pin "2") (pinfunction "2_2") (pintype "passive"))
      (node (ref "C24") (pin "2") (pinfunction "2_2") (pintype "passive"))
      (node (ref "C240") (pin "2") (pinfunction "2_2") (pintype "passive"))
      (node (ref "C242") (pin "2") (pinfunction "2_2") (pintype "passive"))
      (node (ref "C243") (pin "2") (pinfunction "2_2") (pintype "passive"))
      (node (ref "C245") (pin "2") (pinfunction "2_2") (pintype "passive"))
      (node (ref "C247") (pin "2") (pinfunction "2_2") (pintype "passive"))
      (node (ref "C248") (pin "2") (pinfunction "2_2") (pintype "passive"))
      (node (ref "C249") (pin "2") (pinfunction "2_2") (pintype "passive"))
      (node (ref "C25") (pin "2") (pinfunction "2_2") (pintype "passive"))
      (node (ref "C250") (pin "2") (pinfunction "2_2") (pintype "passive"))
      (node (ref "C251") (pin "2") (pinfunction "2_2") (pintype "passive"))
      (node (ref "C252") (pin "2") (pinfunction "2_2") (pintype "passive"))
      (node (ref "C253") (pin "2") (pinfunction "2_2") (pintype "passive"))
      (node (ref "C254") (pin "2") (pinfunction "2_2") (pintype "passive"))
      (node (ref "C255") (pin "2") (pinfunction "2_2") (pintype "passive"))
      (node (ref "C256") (pin "2") (pinfunction "2_2") (pintype "passive"))
      (node (ref "C257") (pin "2") (pinfunction "2_2") (pintype "passive"))
      (node (ref "C258") (pin "2") (pinfunction "2_2") (pintype "passive"))
      (node (ref "C26") (pin "2") (pinfunction "2_2") (pintype "passive"))
      (node (ref "C262") (pin "2") (pinfunction "2_2") (pintype "passive"))
      (node (ref "C263") (pin "2") (pinfunction "2_2") (pintype "passive"))
      (node (ref "C264") (pin "2") (pinfunction "2_2") (pintype "passive"))
      (node (ref "C265") (pin "2") (pinfunction "2_2") (pintype "passive"))
      (node (ref "C266") (pin "2") (pinfunction "2_2") (pintype "passive"))
      (node (ref "C267") (pin "2") (pinfunction "2_2") (pintype "passive"))
      (node (ref "C268") (pin "2") (pinfunction "2_2") (pintype "passive"))
      (node (ref "C269") (pin "2") (pinfunction "2_2") (pintype "passive"))
      (node (ref "C270") (pin "2") (pinfunction "2_2") (pintype "passive"))
      (node (ref "C271") (pin "2") (pinfunction "2_2") (pintype "passive"))
      (node (ref "C272") (pin "2") (pinfunction "2_2") (pintype "passive"))
      (node (ref "C273") (pin "2") (pinfunction "2_2") (pintype "passive"))
      (node (ref "C276") (pin "2") (pinfunction "2_2") (pintype "passive"))
      (node (ref "C277") (pin "2") (pinfunction "2_2") (pintype "passive"))
      (node (ref "C278") (pin "2") (pinfunction "2_2") (pintype "passive"))
      (node (ref "C28") (pin "2") (pinfunction "2_2") (pintype "passive"))
      (node (ref "C280") (pin "2") (pinfunction "2_2") (pintype "passive"))
      (node (ref "C281") (pin "2") (pinfunction "2_2") (pintype "passive"))
      (node (ref "C282") (pin "2") (pinfunction "2_2") (pintype "passive"))
      (node (ref "C284") (pin "2") (pinfunction "2_2") (pintype "passive"))
      (node (ref "C285") (pin "2") (pinfunction "2_2") (pintype "passive"))
      (node (ref "C286") (pin "2") (pinfunction "2_2") (pintype "passive"))
      (node (ref "C288") (pin "2") (pinfunction "2_2") (pintype "passive"))
      (node (ref "C289") (pin "2") (pinfunction "2_2") (pintype "passive"))
      (node (ref "C290") (pin "2") (pinfunction "2_2") (pintype "passive"))
      (node (ref "C30") (pin "2") (pinfunction "2_2") (pintype "passive"))
      (node (ref "C31") (pin "2") (pinfunction "2_2") (pintype "passive"))
      (node (ref "C324") (pin "2") (pinfunction "2_2") (pintype "passive"))
      (node (ref "C325") (pin "2") (pinfunction "2_2") (pintype "passive"))
      (node (ref "C327") (pin "2") (pinfunction "2_2") (pintype "passive"))
      (node (ref "C329") (pin "2") (pinfunction "2_2") (pintype "passive"))
      (node (ref "C33") (pin "2") (pinfunction "2_2") (pintype "passive"))
      (node (ref "C330") (pin "2") (pinfunction "2_2") (pintype "passive"))
      (node (ref "C332") (pin "2") (pinfunction "2_2") (pintype "passive"))
      (node (ref "C334") (pin "2") (pinfunction "2_2") (pintype "passive"))
      (node (ref "C335") (pin "2") (pinfunction "2_2") (pintype "passive"))
      (node (ref "C337") (pin "2") (pinfunction "2_2") (pintype "passive"))
      (node (ref "C339") (pin "2") (pinfunction "2_2") (pintype "passive"))
      (node (ref "C340") (pin "2") (pinfunction "2_2") (pintype "passive"))
      (node (ref "C342") (pin "2") (pinfunction "2_2") (pintype "passive"))
      (node (ref "C344") (pin "2") (pinfunction "2_2") (pintype "passive"))
      (node (ref "C345") (pin "2") (pinfunction "2_2") (pintype "passive"))
      (node (ref "C346") (pin "2") (pinfunction "2_2") (pintype "passive"))
      (node (ref "C347") (pin "2") (pinfunction "2_2") (pintype "passive"))
      (node (ref "C348") (pin "2") (pinfunction "2_2") (pintype "passive"))
      (node (ref "C349") (pin "2") (pinfunction "2_2") (pintype "passive"))
      (node (ref "C35") (pin "2") (pinfunction "2_2") (pintype "passive"))
      (node (ref "C350") (pin "2") (pinfunction "2_2") (pintype "passive"))
      (node (ref "C351") (pin "2") (pinfunction "2_2") (pintype "passive"))
      (node (ref "C352") (pin "2") (pinfunction "2_2") (pintype "passive"))
      (node (ref "C353") (pin "2") (pinfunction "2_2") (pintype "passive"))
      (node (ref "C354") (pin "2") (pinfunction "2_2") (pintype "passive"))
      (node (ref "C355") (pin "2") (pinfunction "2_2") (pintype "passive"))
      (node (ref "C356") (pin "2") (pinfunction "2_2") (pintype "passive"))
      (node (ref "C357") (pin "2") (pinfunction "2_2") (pintype "passive"))
      (node (ref "C358") (pin "2") (pinfunction "2_2") (pintype "passive"))
      (node (ref "C359") (pin "2") (pinfunction "2_2") (pintype "passive"))
      (node (ref "C36") (pin "2") (pinfunction "2_2") (pintype "passive"))
      (node (ref "C360") (pin "2") (pinfunction "2_2") (pintype "passive"))
      (node (ref "C361") (pin "2") (pinfunction "2_2") (pintype "passive"))
      (node (ref "C362") (pin "2") (pinfunction "2_2") (pintype "passive"))
      (node (ref "C363") (pin "2") (pinfunction "2_2") (pintype "passive"))
      (node (ref "C364") (pin "2") (pinfunction "2_2") (pintype "passive"))
      (node (ref "C365") (pin "2") (pinfunction "2_2") (pintype "passive"))
      (node (ref "C366") (pin "2") (pinfunction "2_2") (pintype "passive"))
      (node (ref "C367") (pin "2") (pinfunction "2_2") (pintype "passive"))
      (node (ref "C368") (pin "2") (pinfunction "2_2") (pintype "passive"))
      (node (ref "C369") (pin "2") (pinfunction "2_2") (pintype "passive"))
      (node (ref "C370") (pin "2") (pinfunction "2_2") (pintype "passive"))
      (node (ref "C372") (pin "2") (pinfunction "2_2") (pintype "passive"))
      (node (ref "C373") (pin "2") (pinfunction "2_2") (pintype "passive"))
      (node (ref "C374") (pin "2") (pinfunction "2_2") (pintype "passive"))
      (node (ref "C376") (pin "2") (pinfunction "2_2") (pintype "passive"))
      (node (ref "C377") (pin "2") (pinfunction "2_2") (pintype "passive"))
      (node (ref "C378") (pin "2") (pinfunction "2_2") (pintype "passive"))
      (node (ref "C38") (pin "2") (pinfunction "2_2") (pintype "passive"))
      (node (ref "C380") (pin "2") (pinfunction "2_2") (pintype "passive"))
      (node (ref "C381") (pin "2") (pinfunction "2_2") (pintype "passive"))
      (node (ref "C382") (pin "2") (pinfunction "2_2") (pintype "passive"))
      (node (ref "C40") (pin "2") (pinfunction "2_2") (pintype "passive"))
      (node (ref "C41") (pin "2") (pinfunction "2_2") (pintype "passive"))
      (node (ref "C43") (pin "2") (pinfunction "2_2") (pintype "passive"))
      (node (ref "C45") (pin "2") (pinfunction "2_2") (pintype "passive"))
      (node (ref "C46") (pin "2") (pinfunction "2_2") (pintype "passive"))
      (node (ref "C47") (pin "2") (pinfunction "2_2") (pintype "passive"))
      (node (ref "C48") (pin "2") (pinfunction "2_2") (pintype "passive"))
      (node (ref "C49") (pin "2") (pinfunction "2_2") (pintype "passive"))
      (node (ref "C50") (pin "2") (pinfunction "2_2") (pintype "passive"))
      (node (ref "C51") (pin "2") (pinfunction "2_2") (pintype "passive"))
      (node (ref "C52") (pin "2") (pinfunction "2_2") (pintype "passive"))
      (node (ref "C53") (pin "2") (pinfunction "2_2") (pintype "passive"))
      (node (ref "C54") (pin "2") (pinfunction "2_2") (pintype "passive"))
      (node (ref "C55") (pin "2") (pinfunction "2_2") (pintype "passive"))
      (node (ref "C56") (pin "2") (pinfunction "2_2") (pintype "passive"))
      (node (ref "C57") (pin "2") (pinfunction "2_2") (pintype "passive"))
      (node (ref "C58") (pin "2") (pinfunction "2_2") (pintype "passive"))
      (node (ref "C59") (pin "2") (pinfunction "2_2") (pintype "passive"))
      (node (ref "C60") (pin "2") (pinfunction "2_2") (pintype "passive"))
      (node (ref "C61") (pin "2") (pinfunction "2_2") (pintype "passive"))
      (node (ref "C62") (pin "2") (pinfunction "2_2") (pintype "passive"))
      (node (ref "C63") (pin "2") (pinfunction "2_2") (pintype "passive"))
      (node (ref "C64") (pin "2") (pinfunction "2_2") (pintype "passive"))
      (node (ref "C65") (pin "2") (pinfunction "2_2") (pintype "passive"))
      (node (ref "C66") (pin "2") (pinfunction "2_2") (pintype "passive"))
      (node (ref "C67") (pin "2") (pinfunction "2_2") (pintype "passive"))
      (node (ref "C68") (pin "2") (pinfunction "2_2") (pintype "passive"))
      (node (ref "C70") (pin "2") (pinfunction "2_2") (pintype "passive"))
      (node (ref "C71") (pin "2") (pinfunction "2_2") (pintype "passive"))
      (node (ref "C72") (pin "2") (pinfunction "2_2") (pintype "passive"))
      (node (ref "C74") (pin "2") (pinfunction "2_2") (pintype "passive"))
      (node (ref "C75") (pin "2") (pinfunction "2_2") (pintype "passive"))
      (node (ref "C76") (pin "2") (pinfunction "2_2") (pintype "passive"))
      (node (ref "C78") (pin "2") (pinfunction "2_2") (pintype "passive"))
      (node (ref "C79") (pin "2") (pinfunction "2_2") (pintype "passive"))
      (node (ref "C80") (pin "2") (pinfunction "2_2") (pintype "passive"))
      (node (ref "C82") (pin "2") (pinfunction "2_2") (pintype "passive"))
      (node (ref "C83") (pin "2") (pinfunction "2_2") (pintype "passive"))
      (node (ref "C84") (pin "2") (pinfunction "2_2") (pintype "passive"))
      (node (ref "C_1") (pin "1") (pinfunction "1_1") (pintype "passive"))
      (node (ref "C_10") (pin "1") (pinfunction "1_1") (pintype "passive"))
      (node (ref "C_11") (pin "1") (pinfunction "1_1") (pintype "passive"))
      (node (ref "C_12") (pin "1") (pinfunction "1_1") (pintype "passive"))
      (node (ref "C_13") (pin "1") (pinfunction "1_1") (pintype "passive"))
      (node (ref "C_14") (pin "1") (pinfunction "1_1") (pintype "passive"))
      (node (ref "C_15") (pin "1") (pinfunction "1_1") (pintype "passive"))
      (node (ref "C_16") (pin "1") (pinfunction "1_1") (pintype "passive"))
      (node (ref "C_17") (pin "1") (pinfunction "1_1") (pintype "passive"))
      (node (ref "C_18") (pin "1") (pinfunction "1_1") (pintype "passive"))
      (node (ref "C_19") (pin "1") (pinfunction "1_1") (pintype "passive"))
      (node (ref "C_2") (pin "1") (pinfunction "1_1") (pintype "passive"))
      (node (ref "C_20") (pin "1") (pinfunction "1_1") (pintype "passive"))
      (node (ref "C_21") (pin "1") (pinfunction "1_1") (pintype "passive"))
      (node (ref "C_22") (pin "1") (pinfunction "1_1") (pintype "passive"))
      (node (ref "C_23") (pin "1") (pinfunction "1_1") (pintype "passive"))
      (node (ref "C_24") (pin "1") (pinfunction "1_1") (pintype "passive"))
      (node (ref "C_25") (pin "1") (pinfunction "1_1") (pintype "passive"))
      (node (ref "C_26") (pin "1") (pinfunction "1_1") (pintype "passive"))
      (node (ref "C_27") (pin "1") (pinfunction "1_1") (pintype "passive"))
      (node (ref "C_28") (pin "1") (pinfunction "1_1") (pintype "passive"))
      (node (ref "C_29") (pin "1") (pinfunction "1_1") (pintype "passive"))
      (node (ref "C_3") (pin "1") (pinfunction "1_1") (pintype "passive"))
      (node (ref "C_30") (pin "1") (pinfunction "1_1") (pintype "passive"))
      (node (ref "C_31") (pin "1") (pinfunction "1_1") (pintype "passive"))
      (node (ref "C_32") (pin "1") (pinfunction "1_1") (pintype "passive"))
      (node (ref "C_33") (pin "1") (pinfunction "1_1") (pintype "passive"))
      (node (ref "C_34") (pin "1") (pinfunction "1_1") (pintype "passive"))
      (node (ref "C_35") (pin "1") (pinfunction "1_1") (pintype "passive"))
      (node (ref "C_36") (pin "1") (pinfunction "1_1") (pintype "passive"))
      (node (ref "C_37") (pin "1") (pinfunction "1_1") (pintype "passive"))
      (node (ref "C_38") (pin "1") (pinfunction "1_1") (pintype "passive"))
      (node (ref "C_39") (pin "1") (pinfunction "1_1") (pintype "passive"))
      (node (ref "C_4") (pin "1") (pinfunction "1_1") (pintype "passive"))
      (node (ref "C_40") (pin "1") (pinfunction "1_1") (pintype "passive"))
      (node (ref "C_41") (pin "1") (pinfunction "1_1") (pintype "passive"))
      (node (ref "C_42") (pin "1") (pinfunction "1_1") (pintype "passive"))
      (node (ref "C_43") (pin "1") (pinfunction "1_1") (pintype "passive"))
      (node (ref "C_44") (pin "1") (pinfunction "1_1") (pintype "passive"))
      (node (ref "C_45") (pin "1") (pinfunction "1_1") (pintype "passive"))
      (node (ref "C_46") (pin "1") (pinfunction "1_1") (pintype "passive"))
      (node (ref "C_47") (pin "1") (pinfunction "1_1") (pintype "passive"))
      (node (ref "C_48") (pin "1") (pinfunction "1_1") (pintype "passive"))
      (node (ref "C_49") (pin "1") (pinfunction "1_1") (pintype "passive"))
      (node (ref "C_5") (pin "1") (pinfunction "1_1") (pintype "passive"))
      (node (ref "C_50") (pin "1") (pinfunction "1_1") (pintype "passive"))
      (node (ref "C_51") (pin "1") (pinfunction "1_1") (pintype "passive"))
      (node (ref "C_52") (pin "1") (pinfunction "1_1") (pintype "passive"))
      (node (ref "C_53") (pin "1") (pinfunction "1_1") (pintype "passive"))
      (node (ref "C_54") (pin "1") (pinfunction "1_1") (pintype "passive"))
      (node (ref "C_55") (pin "1") (pinfunction "1_1") (pintype "passive"))
      (node (ref "C_56") (pin "1") (pinfunction "1_1") (pintype "passive"))
      (node (ref "C_57") (pin "1") (pinfunction "1_1") (pintype "passive"))
      (node (ref "C_58") (pin "1") (pinfunction "1_1") (pintype "passive"))
      (node (ref "C_59") (pin "1") (pinfunction "1_1") (pintype "passive"))
      (node (ref "C_6") (pin "1") (pinfunction "1_1") (pintype "passive"))
      (node (ref "C_60") (pin "1") (pinfunction "1_1") (pintype "passive"))
      (node (ref "C_61") (pin "1") (pinfunction "1_1") (pintype "passive"))
      (node (ref "C_62") (pin "1") (pinfunction "1_1") (pintype "passive"))
      (node (ref "C_63") (pin "1") (pinfunction "1_1") (pintype "passive"))
      (node (ref "C_64") (pin "1") (pinfunction "1_1") (pintype "passive"))
      (node (ref "C_65") (pin "1") (pinfunction "1_1") (pintype "passive"))
      (node (ref "C_66") (pin "1") (pinfunction "1_1") (pintype "passive"))
      (node (ref "C_67") (pin "1") (pinfunction "1_1") (pintype "passive"))
      (node (ref "C_68") (pin "1") (pinfunction "1_1") (pintype "passive"))
      (node (ref "C_69") (pin "1") (pinfunction "1_1") (pintype "passive"))
      (node (ref "C_7") (pin "1") (pinfunction "1_1") (pintype "passive"))
      (node (ref "C_70") (pin "1") (pinfunction "1_1") (pintype "passive"))
      (node (ref "C_71") (pin "1") (pinfunction "1_1") (pintype "passive"))
      (node (ref "C_72") (pin "1") (pinfunction "1_1") (pintype "passive"))
      (node (ref "C_8") (pin "1") (pinfunction "1_1") (pintype "passive"))
      (node (ref "C_9") (pin "1") (pinfunction "1_1") (pintype "passive"))
      (node (ref "L1") (pin "2") (pinfunction "2_2") (pintype "passive"))
      (node (ref "L2") (pin "2") (pinfunction "2_2") (pintype "passive"))
      (node (ref "L3") (pin "2") (pinfunction "2_2") (pintype "passive"))
      (node (ref "R26") (pin "2") (pinfunction "2_2") (pintype "passive"))
      (node (ref "U10") (pin "13") (pinfunction "DVDD_13") (pintype "passive"))
      (node (ref "U10") (pin "14") (pinfunction "DVDD_14") (pintype "passive"))
      (node (ref "U10") (pin "19") (pinfunction "DVDD_19") (pintype "passive"))
      (node (ref "U10") (pin "20") (pinfunction "DVDD_20") (pintype "passive"))
      (node (ref "U10") (pin "21") (pinfunction "DVDD_21") (pintype "passive"))
      (node (ref "U10") (pin "22") (pinfunction "DVDD_22") (pintype "passive"))
      (node (ref "U10") (pin "26") (pinfunction "DVDD_26") (pintype "passive"))
      (node (ref "U10") (pin "27") (pinfunction "DVDD_27") (pintype "passive"))
      (node (ref "U10") (pin "29") (pinfunction "DVDD_29") (pintype "passive"))
      (node (ref "U10") (pin "3") (pinfunction "DVDD_3") (pintype "passive"))
      (node (ref "U10") (pin "30") (pinfunction "DVDD_30") (pintype "passive"))
      (node (ref "U10") (pin "34") (pinfunction "DVDD_34") (pintype "passive"))
      (node (ref "U10") (pin "35") (pinfunction "DVDD_35") (pintype "passive"))
      (node (ref "U10") (pin "37") (pinfunction "DVDD_37") (pintype "passive"))
      (node (ref "U10") (pin "38") (pinfunction "DVDD_38") (pintype "passive"))
      (node (ref "U10") (pin "39") (pinfunction "DVDD_39") (pintype "passive"))
      (node (ref "U10") (pin "4") (pinfunction "DVDD_4") (pintype "passive"))
      (node (ref "U10") (pin "41") (pinfunction "DVDD_41") (pintype "passive"))
      (node (ref "U10") (pin "42") (pinfunction "DVDD_42") (pintype "passive"))
      (node (ref "U10") (pin "43") (pinfunction "DVDD_43") (pintype "passive"))
      (node (ref "U10") (pin "45") (pinfunction "DVDD_45") (pintype "passive"))
      (node (ref "U10") (pin "46") (pinfunction "DVDD_46") (pintype "passive"))
      (node (ref "U10") (pin "5") (pinfunction "DVDD_5") (pintype "passive"))
      (node (ref "U10") (pin "51") (pinfunction "DVDD_51") (pintype "passive"))
      (node (ref "U10") (pin "52") (pinfunction "DVDD_52") (pintype "passive"))
      (node (ref "U10") (pin "54") (pinfunction "DVDD_54") (pintype "passive"))
      (node (ref "U10") (pin "55") (pinfunction "DVDD_55") (pintype "passive"))
      (node (ref "U10") (pin "58") (pinfunction "DVDD_58") (pintype "passive"))
      (node (ref "U10") (pin "59") (pinfunction "DVDD_59") (pintype "passive"))
      (node (ref "U10") (pin "6") (pinfunction "DVDD_6") (pintype "passive"))
      (node (ref "U10") (pin "60") (pinfunction "DVDD_60") (pintype "passive"))
      (node (ref "U10") (pin "62") (pinfunction "DVDD_62") (pintype "passive"))
      (node (ref "U10") (pin "63") (pinfunction "DVDD_63") (pintype "passive"))
      (node (ref "U11") (pin "13") (pinfunction "DVDD_13") (pintype "passive"))
      (node (ref "U11") (pin "14") (pinfunction "DVDD_14") (pintype "passive"))
      (node (ref "U11") (pin "19") (pinfunction "DVDD_19") (pintype "passive"))
      (node (ref "U11") (pin "20") (pinfunction "DVDD_20") (pintype "passive"))
      (node (ref "U11") (pin "21") (pinfunction "DVDD_21") (pintype "passive"))
      (node (ref "U11") (pin "22") (pinfunction "DVDD_22") (pintype "passive"))
      (node (ref "U11") (pin "26") (pinfunction "DVDD_26") (pintype "passive"))
      (node (ref "U11") (pin "27") (pinfunction "DVDD_27") (pintype "passive"))
      (node (ref "U11") (pin "29") (pinfunction "DVDD_29") (pintype "passive"))
      (node (ref "U11") (pin "3") (pinfunction "DVDD_3") (pintype "passive"))
      (node (ref "U11") (pin "30") (pinfunction "DVDD_30") (pintype "passive"))
      (node (ref "U11") (pin "34") (pinfunction "DVDD_34") (pintype "passive"))
      (node (ref "U11") (pin "35") (pinfunction "DVDD_35") (pintype "passive"))
      (node (ref "U11") (pin "37") (pinfunction "DVDD_37") (pintype "passive"))
      (node (ref "U11") (pin "38") (pinfunction "DVDD_38") (pintype "passive"))
      (node (ref "U11") (pin "39") (pinfunction "DVDD_39") (pintype "passive"))
      (node (ref "U11") (pin "4") (pinfunction "DVDD_4") (pintype "passive"))
      (node (ref "U11") (pin "41") (pinfunction "DVDD_41") (pintype "passive"))
      (node (ref "U11") (pin "42") (pinfunction "DVDD_42") (pintype "passive"))
      (node (ref "U11") (pin "43") (pinfunction "DVDD_43") (pintype "passive"))
      (node (ref "U11") (pin "45") (pinfunction "DVDD_45") (pintype "passive"))
      (node (ref "U11") (pin "46") (pinfunction "DVDD_46") (pintype "passive"))
      (node (ref "U11") (pin "5") (pinfunction "DVDD_5") (pintype "passive"))
      (node (ref "U11") (pin "51") (pinfunction "DVDD_51") (pintype "passive"))
      (node (ref "U11") (pin "52") (pinfunction "DVDD_52") (pintype "passive"))
      (node (ref "U11") (pin "54") (pinfunction "DVDD_54") (pintype "passive"))
      (node (ref "U11") (pin "55") (pinfunction "DVDD_55") (pintype "passive"))
      (node (ref "U11") (pin "58") (pinfunction "DVDD_58") (pintype "passive"))
      (node (ref "U11") (pin "59") (pinfunction "DVDD_59") (pintype "passive"))
      (node (ref "U11") (pin "6") (pinfunction "DVDD_6") (pintype "passive"))
      (node (ref "U11") (pin "60") (pinfunction "DVDD_60") (pintype "passive"))
      (node (ref "U11") (pin "62") (pinfunction "DVDD_62") (pintype "passive"))
      (node (ref "U11") (pin "63") (pinfunction "DVDD_63") (pintype "passive"))
      (node (ref "U12") (pin "13") (pinfunction "DVDD_13") (pintype "passive"))
      (node (ref "U12") (pin "14") (pinfunction "DVDD_14") (pintype "passive"))
      (node (ref "U12") (pin "19") (pinfunction "DVDD_19") (pintype "passive"))
      (node (ref "U12") (pin "20") (pinfunction "DVDD_20") (pintype "passive"))
      (node (ref "U12") (pin "21") (pinfunction "DVDD_21") (pintype "passive"))
      (node (ref "U12") (pin "22") (pinfunction "DVDD_22") (pintype "passive"))
      (node (ref "U12") (pin "26") (pinfunction "DVDD_26") (pintype "passive"))
      (node (ref "U12") (pin "27") (pinfunction "DVDD_27") (pintype "passive"))
      (node (ref "U12") (pin "29") (pinfunction "DVDD_29") (pintype "passive"))
      (node (ref "U12") (pin "3") (pinfunction "DVDD_3") (pintype "passive"))
      (node (ref "U12") (pin "30") (pinfunction "DVDD_30") (pintype "passive"))
      (node (ref "U12") (pin "34") (pinfunction "DVDD_34") (pintype "passive"))
      (node (ref "U12") (pin "35") (pinfunction "DVDD_35") (pintype "passive"))
      (node (ref "U12") (pin "37") (pinfunction "DVDD_37") (pintype "passive"))
      (node (ref "U12") (pin "38") (pinfunction "DVDD_38") (pintype "passive"))
      (node (ref "U12") (pin "39") (pinfunction "DVDD_39") (pintype "passive"))
      (node (ref "U12") (pin "4") (pinfunction "DVDD_4") (pintype "passive"))
      (node (ref "U12") (pin "41") (pinfunction "DVDD_41") (pintype "passive"))
      (node (ref "U12") (pin "42") (pinfunction "DVDD_42") (pintype "passive"))
      (node (ref "U12") (pin "43") (pinfunction "DVDD_43") (pintype "passive"))
      (node (ref "U12") (pin "45") (pinfunction "DVDD_45") (pintype "passive"))
      (node (ref "U12") (pin "46") (pinfunction "DVDD_46") (pintype "passive"))
      (node (ref "U12") (pin "5") (pinfunction "DVDD_5") (pintype "passive"))
      (node (ref "U12") (pin "51") (pinfunction "DVDD_51") (pintype "passive"))
      (node (ref "U12") (pin "52") (pinfunction "DVDD_52") (pintype "passive"))
      (node (ref "U12") (pin "54") (pinfunction "DVDD_54") (pintype "passive"))
      (node (ref "U12") (pin "55") (pinfunction "DVDD_55") (pintype "passive"))
      (node (ref "U12") (pin "58") (pinfunction "DVDD_58") (pintype "passive"))
      (node (ref "U12") (pin "59") (pinfunction "DVDD_59") (pintype "passive"))
      (node (ref "U12") (pin "6") (pinfunction "DVDD_6") (pintype "passive"))
      (node (ref "U12") (pin "60") (pinfunction "DVDD_60") (pintype "passive"))
      (node (ref "U12") (pin "62") (pinfunction "DVDD_62") (pintype "passive"))
      (node (ref "U12") (pin "63") (pinfunction "DVDD_63") (pintype "passive"))
      (node (ref "U18") (pin "13") (pinfunction "DVDD_13") (pintype "passive"))
      (node (ref "U18") (pin "14") (pinfunction "DVDD_14") (pintype "passive"))
      (node (ref "U18") (pin "19") (pinfunction "DVDD_19") (pintype "passive"))
      (node (ref "U18") (pin "20") (pinfunction "DVDD_20") (pintype "passive"))
      (node (ref "U18") (pin "21") (pinfunction "DVDD_21") (pintype "passive"))
      (node (ref "U18") (pin "22") (pinfunction "DVDD_22") (pintype "passive"))
      (node (ref "U18") (pin "26") (pinfunction "DVDD_26") (pintype "passive"))
      (node (ref "U18") (pin "27") (pinfunction "DVDD_27") (pintype "passive"))
      (node (ref "U18") (pin "29") (pinfunction "DVDD_29") (pintype "passive"))
      (node (ref "U18") (pin "3") (pinfunction "DVDD_3") (pintype "passive"))
      (node (ref "U18") (pin "30") (pinfunction "DVDD_30") (pintype "passive"))
      (node (ref "U18") (pin "34") (pinfunction "DVDD_34") (pintype "passive"))
      (node (ref "U18") (pin "35") (pinfunction "DVDD_35") (pintype "passive"))
      (node (ref "U18") (pin "37") (pinfunction "DVDD_37") (pintype "passive"))
      (node (ref "U18") (pin "38") (pinfunction "DVDD_38") (pintype "passive"))
      (node (ref "U18") (pin "39") (pinfunction "DVDD_39") (pintype "passive"))
      (node (ref "U18") (pin "4") (pinfunction "DVDD_4") (pintype "passive"))
      (node (ref "U18") (pin "41") (pinfunction "DVDD_41") (pintype "passive"))
      (node (ref "U18") (pin "42") (pinfunction "DVDD_42") (pintype "passive"))
      (node (ref "U18") (pin "43") (pinfunction "DVDD_43") (pintype "passive"))
      (node (ref "U18") (pin "45") (pinfunction "DVDD_45") (pintype "passive"))
      (node (ref "U18") (pin "46") (pinfunction "DVDD_46") (pintype "passive"))
      (node (ref "U18") (pin "5") (pinfunction "DVDD_5") (pintype "passive"))
      (node (ref "U18") (pin "51") (pinfunction "DVDD_51") (pintype "passive"))
      (node (ref "U18") (pin "52") (pinfunction "DVDD_52") (pintype "passive"))
      (node (ref "U18") (pin "54") (pinfunction "DVDD_54") (pintype "passive"))
      (node (ref "U18") (pin "55") (pinfunction "DVDD_55") (pintype "passive"))
      (node (ref "U18") (pin "58") (pinfunction "DVDD_58") (pintype "passive"))
      (node (ref "U18") (pin "59") (pinfunction "DVDD_59") (pintype "passive"))
      (node (ref "U18") (pin "6") (pinfunction "DVDD_6") (pintype "passive"))
      (node (ref "U18") (pin "60") (pinfunction "DVDD_60") (pintype "passive"))
      (node (ref "U18") (pin "62") (pinfunction "DVDD_62") (pintype "passive"))
      (node (ref "U18") (pin "63") (pinfunction "DVDD_63") (pintype "passive"))
      (node (ref "U19") (pin "13") (pinfunction "DVDD_13") (pintype "passive"))
      (node (ref "U19") (pin "14") (pinfunction "DVDD_14") (pintype "passive"))
      (node (ref "U19") (pin "19") (pinfunction "DVDD_19") (pintype "passive"))
      (node (ref "U19") (pin "20") (pinfunction "DVDD_20") (pintype "passive"))
      (node (ref "U19") (pin "21") (pinfunction "DVDD_21") (pintype "passive"))
      (node (ref "U19") (pin "22") (pinfunction "DVDD_22") (pintype "passive"))
      (node (ref "U19") (pin "26") (pinfunction "DVDD_26") (pintype "passive"))
      (node (ref "U19") (pin "27") (pinfunction "DVDD_27") (pintype "passive"))
      (node (ref "U19") (pin "29") (pinfunction "DVDD_29") (pintype "passive"))
      (node (ref "U19") (pin "3") (pinfunction "DVDD_3") (pintype "passive"))
      (node (ref "U19") (pin "30") (pinfunction "DVDD_30") (pintype "passive"))
      (node (ref "U19") (pin "34") (pinfunction "DVDD_34") (pintype "passive"))
      (node (ref "U19") (pin "35") (pinfunction "DVDD_35") (pintype "passive"))
      (node (ref "U19") (pin "37") (pinfunction "DVDD_37") (pintype "passive"))
      (node (ref "U19") (pin "38") (pinfunction "DVDD_38") (pintype "passive"))
      (node (ref "U19") (pin "39") (pinfunction "DVDD_39") (pintype "passive"))
      (node (ref "U19") (pin "4") (pinfunction "DVDD_4") (pintype "passive"))
      (node (ref "U19") (pin "41") (pinfunction "DVDD_41") (pintype "passive"))
      (node (ref "U19") (pin "42") (pinfunction "DVDD_42") (pintype "passive"))
      (node (ref "U19") (pin "43") (pinfunction "DVDD_43") (pintype "passive"))
      (node (ref "U19") (pin "45") (pinfunction "DVDD_45") (pintype "passive"))
      (node (ref "U19") (pin "46") (pinfunction "DVDD_46") (pintype "passive"))
      (node (ref "U19") (pin "5") (pinfunction "DVDD_5") (pintype "passive"))
      (node (ref "U19") (pin "51") (pinfunction "DVDD_51") (pintype "passive"))
      (node (ref "U19") (pin "52") (pinfunction "DVDD_52") (pintype "passive"))
      (node (ref "U19") (pin "54") (pinfunction "DVDD_54") (pintype "passive"))
      (node (ref "U19") (pin "55") (pinfunction "DVDD_55") (pintype "passive"))
      (node (ref "U19") (pin "58") (pinfunction "DVDD_58") (pintype "passive"))
      (node (ref "U19") (pin "59") (pinfunction "DVDD_59") (pintype "passive"))
      (node (ref "U19") (pin "6") (pinfunction "DVDD_6") (pintype "passive"))
      (node (ref "U19") (pin "60") (pinfunction "DVDD_60") (pintype "passive"))
      (node (ref "U19") (pin "62") (pinfunction "DVDD_62") (pintype "passive"))
      (node (ref "U19") (pin "63") (pinfunction "DVDD_63") (pintype "passive"))
      (node (ref "U20") (pin "13") (pinfunction "DVDD_13") (pintype "passive"))
      (node (ref "U20") (pin "14") (pinfunction "DVDD_14") (pintype "passive"))
      (node (ref "U20") (pin "19") (pinfunction "DVDD_19") (pintype "passive"))
      (node (ref "U20") (pin "20") (pinfunction "DVDD_20") (pintype "passive"))
      (node (ref "U20") (pin "21") (pinfunction "DVDD_21") (pintype "passive"))
      (node (ref "U20") (pin "22") (pinfunction "DVDD_22") (pintype "passive"))
      (node (ref "U20") (pin "26") (pinfunction "DVDD_26") (pintype "passive"))
      (node (ref "U20") (pin "27") (pinfunction "DVDD_27") (pintype "passive"))
      (node (ref "U20") (pin "29") (pinfunction "DVDD_29") (pintype "passive"))
      (node (ref "U20") (pin "3") (pinfunction "DVDD_3") (pintype "passive"))
      (node (ref "U20") (pin "30") (pinfunction "DVDD_30") (pintype "passive"))
      (node (ref "U20") (pin "34") (pinfunction "DVDD_34") (pintype "passive"))
      (node (ref "U20") (pin "35") (pinfunction "DVDD_35") (pintype "passive"))
      (node (ref "U20") (pin "37") (pinfunction "DVDD_37") (pintype "passive"))
      (node (ref "U20") (pin "38") (pinfunction "DVDD_38") (pintype "passive"))
      (node (ref "U20") (pin "39") (pinfunction "DVDD_39") (pintype "passive"))
      (node (ref "U20") (pin "4") (pinfunction "DVDD_4") (pintype "passive"))
      (node (ref "U20") (pin "41") (pinfunction "DVDD_41") (pintype "passive"))
      (node (ref "U20") (pin "42") (pinfunction "DVDD_42") (pintype "passive"))
      (node (ref "U20") (pin "43") (pinfunction "DVDD_43") (pintype "passive"))
      (node (ref "U20") (pin "45") (pinfunction "DVDD_45") (pintype "passive"))
      (node (ref "U20") (pin "46") (pinfunction "DVDD_46") (pintype "passive"))
      (node (ref "U20") (pin "5") (pinfunction "DVDD_5") (pintype "passive"))
      (node (ref "U20") (pin "51") (pinfunction "DVDD_51") (pintype "passive"))
      (node (ref "U20") (pin "52") (pinfunction "DVDD_52") (pintype "passive"))
      (node (ref "U20") (pin "54") (pinfunction "DVDD_54") (pintype "passive"))
      (node (ref "U20") (pin "55") (pinfunction "DVDD_55") (pintype "passive"))
      (node (ref "U20") (pin "58") (pinfunction "DVDD_58") (pintype "passive"))
      (node (ref "U20") (pin "59") (pinfunction "DVDD_59") (pintype "passive"))
      (node (ref "U20") (pin "6") (pinfunction "DVDD_6") (pintype "passive"))
      (node (ref "U20") (pin "60") (pinfunction "DVDD_60") (pintype "passive"))
      (node (ref "U20") (pin "62") (pinfunction "DVDD_62") (pintype "passive"))
      (node (ref "U20") (pin "63") (pinfunction "DVDD_63") (pintype "passive"))
      (node (ref "U21") (pin "13") (pinfunction "DVDD_13") (pintype "passive"))
      (node (ref "U21") (pin "14") (pinfunction "DVDD_14") (pintype "passive"))
      (node (ref "U21") (pin "19") (pinfunction "DVDD_19") (pintype "passive"))
      (node (ref "U21") (pin "20") (pinfunction "DVDD_20") (pintype "passive"))
      (node (ref "U21") (pin "21") (pinfunction "DVDD_21") (pintype "passive"))
      (node (ref "U21") (pin "22") (pinfunction "DVDD_22") (pintype "passive"))
      (node (ref "U21") (pin "26") (pinfunction "DVDD_26") (pintype "passive"))
      (node (ref "U21") (pin "27") (pinfunction "DVDD_27") (pintype "passive"))
      (node (ref "U21") (pin "29") (pinfunction "DVDD_29") (pintype "passive"))
      (node (ref "U21") (pin "3") (pinfunction "DVDD_3") (pintype "passive"))
      (node (ref "U21") (pin "30") (pinfunction "DVDD_30") (pintype "passive"))
      (node (ref "U21") (pin "34") (pinfunction "DVDD_34") (pintype "passive"))
      (node (ref "U21") (pin "35") (pinfunction "DVDD_35") (pintype "passive"))
      (node (ref "U21") (pin "37") (pinfunction "DVDD_37") (pintype "passive"))
      (node (ref "U21") (pin "38") (pinfunction "DVDD_38") (pintype "passive"))
      (node (ref "U21") (pin "39") (pinfunction "DVDD_39") (pintype "passive"))
      (node (ref "U21") (pin "4") (pinfunction "DVDD_4") (pintype "passive"))
      (node (ref "U21") (pin "41") (pinfunction "DVDD_41") (pintype "passive"))
      (node (ref "U21") (pin "42") (pinfunction "DVDD_42") (pintype "passive"))
      (node (ref "U21") (pin "43") (pinfunction "DVDD_43") (pintype "passive"))
      (node (ref "U21") (pin "45") (pinfunction "DVDD_45") (pintype "passive"))
      (node (ref "U21") (pin "46") (pinfunction "DVDD_46") (pintype "passive"))
      (node (ref "U21") (pin "5") (pinfunction "DVDD_5") (pintype "passive"))
      (node (ref "U21") (pin "51") (pinfunction "DVDD_51") (pintype "passive"))
      (node (ref "U21") (pin "52") (pinfunction "DVDD_52") (pintype "passive"))
      (node (ref "U21") (pin "54") (pinfunction "DVDD_54") (pintype "passive"))
      (node (ref "U21") (pin "55") (pinfunction "DVDD_55") (pintype "passive"))
      (node (ref "U21") (pin "58") (pinfunction "DVDD_58") (pintype "passive"))
      (node (ref "U21") (pin "59") (pinfunction "DVDD_59") (pintype "passive"))
      (node (ref "U21") (pin "6") (pinfunction "DVDD_6") (pintype "passive"))
      (node (ref "U21") (pin "60") (pinfunction "DVDD_60") (pintype "passive"))
      (node (ref "U21") (pin "62") (pinfunction "DVDD_62") (pintype "passive"))
      (node (ref "U21") (pin "63") (pinfunction "DVDD_63") (pintype "passive"))
      (node (ref "U24") (pin "13") (pinfunction "DVDD_13") (pintype "passive"))
      (node (ref "U24") (pin "14") (pinfunction "DVDD_14") (pintype "passive"))
      (node (ref "U24") (pin "19") (pinfunction "DVDD_19") (pintype "passive"))
      (node (ref "U24") (pin "20") (pinfunction "DVDD_20") (pintype "passive"))
      (node (ref "U24") (pin "21") (pinfunction "DVDD_21") (pintype "passive"))
      (node (ref "U24") (pin "22") (pinfunction "DVDD_22") (pintype "passive"))
      (node (ref "U24") (pin "26") (pinfunction "DVDD_26") (pintype "passive"))
      (node (ref "U24") (pin "27") (pinfunction "DVDD_27") (pintype "passive"))
      (node (ref "U24") (pin "29") (pinfunction "DVDD_29") (pintype "passive"))
      (node (ref "U24") (pin "3") (pinfunction "DVDD_3") (pintype "passive"))
      (node (ref "U24") (pin "30") (pinfunction "DVDD_30") (pintype "passive"))
      (node (ref "U24") (pin "34") (pinfunction "DVDD_34") (pintype "passive"))
      (node (ref "U24") (pin "35") (pinfunction "DVDD_35") (pintype "passive"))
      (node (ref "U24") (pin "37") (pinfunction "DVDD_37") (pintype "passive"))
      (node (ref "U24") (pin "38") (pinfunction "DVDD_38") (pintype "passive"))
      (node (ref "U24") (pin "39") (pinfunction "DVDD_39") (pintype "passive"))
      (node (ref "U24") (pin "4") (pinfunction "DVDD_4") (pintype "passive"))
      (node (ref "U24") (pin "41") (pinfunction "DVDD_41") (pintype "passive"))
      (node (ref "U24") (pin "42") (pinfunction "DVDD_42") (pintype "passive"))
      (node (ref "U24") (pin "43") (pinfunction "DVDD_43") (pintype "passive"))
      (node (ref "U24") (pin "45") (pinfunction "DVDD_45") (pintype "passive"))
      (node (ref "U24") (pin "46") (pinfunction "DVDD_46") (pintype "passive"))
      (node (ref "U24") (pin "5") (pinfunction "DVDD_5") (pintype "passive"))
      (node (ref "U24") (pin "51") (pinfunction "DVDD_51") (pintype "passive"))
      (node (ref "U24") (pin "52") (pinfunction "DVDD_52") (pintype "passive"))
      (node (ref "U24") (pin "54") (pinfunction "DVDD_54") (pintype "passive"))
      (node (ref "U24") (pin "55") (pinfunction "DVDD_55") (pintype "passive"))
      (node (ref "U24") (pin "58") (pinfunction "DVDD_58") (pintype "passive"))
      (node (ref "U24") (pin "59") (pinfunction "DVDD_59") (pintype "passive"))
      (node (ref "U24") (pin "6") (pinfunction "DVDD_6") (pintype "passive"))
      (node (ref "U24") (pin "60") (pinfunction "DVDD_60") (pintype "passive"))
      (node (ref "U24") (pin "62") (pinfunction "DVDD_62") (pintype "passive"))
      (node (ref "U24") (pin "63") (pinfunction "DVDD_63") (pintype "passive"))
      (node (ref "U25") (pin "13") (pinfunction "DVDD_13") (pintype "passive"))
      (node (ref "U25") (pin "14") (pinfunction "DVDD_14") (pintype "passive"))
      (node (ref "U25") (pin "19") (pinfunction "DVDD_19") (pintype "passive"))
      (node (ref "U25") (pin "20") (pinfunction "DVDD_20") (pintype "passive"))
      (node (ref "U25") (pin "21") (pinfunction "DVDD_21") (pintype "passive"))
      (node (ref "U25") (pin "22") (pinfunction "DVDD_22") (pintype "passive"))
      (node (ref "U25") (pin "26") (pinfunction "DVDD_26") (pintype "passive"))
      (node (ref "U25") (pin "27") (pinfunction "DVDD_27") (pintype "passive"))
      (node (ref "U25") (pin "29") (pinfunction "DVDD_29") (pintype "passive"))
      (node (ref "U25") (pin "3") (pinfunction "DVDD_3") (pintype "passive"))
      (node (ref "U25") (pin "30") (pinfunction "DVDD_30") (pintype "passive"))
      (node (ref "U25") (pin "34") (pinfunction "DVDD_34") (pintype "passive"))
      (node (ref "U25") (pin "35") (pinfunction "DVDD_35") (pintype "passive"))
      (node (ref "U25") (pin "37") (pinfunction "DVDD_37") (pintype "passive"))
      (node (ref "U25") (pin "38") (pinfunction "DVDD_38") (pintype "passive"))
      (node (ref "U25") (pin "39") (pinfunction "DVDD_39") (pintype "passive"))
      (node (ref "U25") (pin "4") (pinfunction "DVDD_4") (pintype "passive"))
      (node (ref "U25") (pin "41") (pinfunction "DVDD_41") (pintype "passive"))
      (node (ref "U25") (pin "42") (pinfunction "DVDD_42") (pintype "passive"))
      (node (ref "U25") (pin "43") (pinfunction "DVDD_43") (pintype "passive"))
      (node (ref "U25") (pin "45") (pinfunction "DVDD_45") (pintype "passive"))
      (node (ref "U25") (pin "46") (pinfunction "DVDD_46") (pintype "passive"))
      (node (ref "U25") (pin "5") (pinfunction "DVDD_5") (pintype "passive"))
      (node (ref "U25") (pin "51") (pinfunction "DVDD_51") (pintype "passive"))
      (node (ref "U25") (pin "52") (pinfunction "DVDD_52") (pintype "passive"))
      (node (ref "U25") (pin "54") (pinfunction "DVDD_54") (pintype "passive"))
      (node (ref "U25") (pin "55") (pinfunction "DVDD_55") (pintype "passive"))
      (node (ref "U25") (pin "58") (pinfunction "DVDD_58") (pintype "passive"))
      (node (ref "U25") (pin "59") (pinfunction "DVDD_59") (pintype "passive"))
      (node (ref "U25") (pin "6") (pinfunction "DVDD_6") (pintype "passive"))
      (node (ref "U25") (pin "60") (pinfunction "DVDD_60") (pintype "passive"))
      (node (ref "U25") (pin "62") (pinfunction "DVDD_62") (pintype "passive"))
      (node (ref "U25") (pin "63") (pinfunction "DVDD_63") (pintype "passive"))
      (node (ref "U26") (pin "13") (pinfunction "DVDD_13") (pintype "passive"))
      (node (ref "U26") (pin "14") (pinfunction "DVDD_14") (pintype "passive"))
      (node (ref "U26") (pin "19") (pinfunction "DVDD_19") (pintype "passive"))
      (node (ref "U26") (pin "20") (pinfunction "DVDD_20") (pintype "passive"))
      (node (ref "U26") (pin "21") (pinfunction "DVDD_21") (pintype "passive"))
      (node (ref "U26") (pin "22") (pinfunction "DVDD_22") (pintype "passive"))
      (node (ref "U26") (pin "26") (pinfunction "DVDD_26") (pintype "passive"))
      (node (ref "U26") (pin "27") (pinfunction "DVDD_27") (pintype "passive"))
      (node (ref "U26") (pin "29") (pinfunction "DVDD_29") (pintype "passive"))
      (node (ref "U26") (pin "3") (pinfunction "DVDD_3") (pintype "passive"))
      (node (ref "U26") (pin "30") (pinfunction "DVDD_30") (pintype "passive"))
      (node (ref "U26") (pin "34") (pinfunction "DVDD_34") (pintype "passive"))
      (node (ref "U26") (pin "35") (pinfunction "DVDD_35") (pintype "passive"))
      (node (ref "U26") (pin "37") (pinfunction "DVDD_37") (pintype "passive"))
      (node (ref "U26") (pin "38") (pinfunction "DVDD_38") (pintype "passive"))
      (node (ref "U26") (pin "39") (pinfunction "DVDD_39") (pintype "passive"))
      (node (ref "U26") (pin "4") (pinfunction "DVDD_4") (pintype "passive"))
      (node (ref "U26") (pin "41") (pinfunction "DVDD_41") (pintype "passive"))
      (node (ref "U26") (pin "42") (pinfunction "DVDD_42") (pintype "passive"))
      (node (ref "U26") (pin "43") (pinfunction "DVDD_43") (pintype "passive"))
      (node (ref "U26") (pin "45") (pinfunction "DVDD_45") (pintype "passive"))
      (node (ref "U26") (pin "46") (pinfunction "DVDD_46") (pintype "passive"))
      (node (ref "U26") (pin "5") (pinfunction "DVDD_5") (pintype "passive"))
      (node (ref "U26") (pin "51") (pinfunction "DVDD_51") (pintype "passive"))
      (node (ref "U26") (pin "52") (pinfunction "DVDD_52") (pintype "passive"))
      (node (ref "U26") (pin "54") (pinfunction "DVDD_54") (pintype "passive"))
      (node (ref "U26") (pin "55") (pinfunction "DVDD_55") (pintype "passive"))
      (node (ref "U26") (pin "58") (pinfunction "DVDD_58") (pintype "passive"))
      (node (ref "U26") (pin "59") (pinfunction "DVDD_59") (pintype "passive"))
      (node (ref "U26") (pin "6") (pinfunction "DVDD_6") (pintype "passive"))
      (node (ref "U26") (pin "60") (pinfunction "DVDD_60") (pintype "passive"))
      (node (ref "U26") (pin "62") (pinfunction "DVDD_62") (pintype "passive"))
      (node (ref "U26") (pin "63") (pinfunction "DVDD_63") (pintype "passive"))
      (node (ref "U27") (pin "13") (pinfunction "DVDD_13") (pintype "passive"))
      (node (ref "U27") (pin "14") (pinfunction "DVDD_14") (pintype "passive"))
      (node (ref "U27") (pin "19") (pinfunction "DVDD_19") (pintype "passive"))
      (node (ref "U27") (pin "20") (pinfunction "DVDD_20") (pintype "passive"))
      (node (ref "U27") (pin "21") (pinfunction "DVDD_21") (pintype "passive"))
      (node (ref "U27") (pin "22") (pinfunction "DVDD_22") (pintype "passive"))
      (node (ref "U27") (pin "26") (pinfunction "DVDD_26") (pintype "passive"))
      (node (ref "U27") (pin "27") (pinfunction "DVDD_27") (pintype "passive"))
      (node (ref "U27") (pin "29") (pinfunction "DVDD_29") (pintype "passive"))
      (node (ref "U27") (pin "3") (pinfunction "DVDD_3") (pintype "passive"))
      (node (ref "U27") (pin "30") (pinfunction "DVDD_30") (pintype "passive"))
      (node (ref "U27") (pin "34") (pinfunction "DVDD_34") (pintype "passive"))
      (node (ref "U27") (pin "35") (pinfunction "DVDD_35") (pintype "passive"))
      (node (ref "U27") (pin "37") (pinfunction "DVDD_37") (pintype "passive"))
      (node (ref "U27") (pin "38") (pinfunction "DVDD_38") (pintype "passive"))
      (node (ref "U27") (pin "39") (pinfunction "DVDD_39") (pintype "passive"))
      (node (ref "U27") (pin "4") (pinfunction "DVDD_4") (pintype "passive"))
      (node (ref "U27") (pin "41") (pinfunction "DVDD_41") (pintype "passive"))
      (node (ref "U27") (pin "42") (pinfunction "DVDD_42") (pintype "passive"))
      (node (ref "U27") (pin "43") (pinfunction "DVDD_43") (pintype "passive"))
      (node (ref "U27") (pin "45") (pinfunction "DVDD_45") (pintype "passive"))
      (node (ref "U27") (pin "46") (pinfunction "DVDD_46") (pintype "passive"))
      (node (ref "U27") (pin "5") (pinfunction "DVDD_5") (pintype "passive"))
      (node (ref "U27") (pin "51") (pinfunction "DVDD_51") (pintype "passive"))
      (node (ref "U27") (pin "52") (pinfunction "DVDD_52") (pintype "passive"))
      (node (ref "U27") (pin "54") (pinfunction "DVDD_54") (pintype "passive"))
      (node (ref "U27") (pin "55") (pinfunction "DVDD_55") (pintype "passive"))
      (node (ref "U27") (pin "58") (pinfunction "DVDD_58") (pintype "passive"))
      (node (ref "U27") (pin "59") (pinfunction "DVDD_59") (pintype "passive"))
      (node (ref "U27") (pin "6") (pinfunction "DVDD_6") (pintype "passive"))
      (node (ref "U27") (pin "60") (pinfunction "DVDD_60") (pintype "passive"))
      (node (ref "U27") (pin "62") (pinfunction "DVDD_62") (pintype "passive"))
      (node (ref "U27") (pin "63") (pinfunction "DVDD_63") (pintype "passive"))
      (node (ref "U4") (pin "13") (pinfunction "DVDD_13") (pintype "passive"))
      (node (ref "U4") (pin "14") (pinfunction "DVDD_14") (pintype "passive"))
      (node (ref "U4") (pin "19") (pinfunction "DVDD_19") (pintype "passive"))
      (node (ref "U4") (pin "20") (pinfunction "DVDD_20") (pintype "passive"))
      (node (ref "U4") (pin "21") (pinfunction "DVDD_21") (pintype "passive"))
      (node (ref "U4") (pin "22") (pinfunction "DVDD_22") (pintype "passive"))
      (node (ref "U4") (pin "26") (pinfunction "DVDD_26") (pintype "passive"))
      (node (ref "U4") (pin "27") (pinfunction "DVDD_27") (pintype "passive"))
      (node (ref "U4") (pin "29") (pinfunction "DVDD_29") (pintype "passive"))
      (node (ref "U4") (pin "3") (pinfunction "DVDD_3") (pintype "passive"))
      (node (ref "U4") (pin "30") (pinfunction "DVDD_30") (pintype "passive"))
      (node (ref "U4") (pin "34") (pinfunction "DVDD_34") (pintype "passive"))
      (node (ref "U4") (pin "35") (pinfunction "DVDD_35") (pintype "passive"))
      (node (ref "U4") (pin "37") (pinfunction "DVDD_37") (pintype "passive"))
      (node (ref "U4") (pin "38") (pinfunction "DVDD_38") (pintype "passive"))
      (node (ref "U4") (pin "39") (pinfunction "DVDD_39") (pintype "passive"))
      (node (ref "U4") (pin "4") (pinfunction "DVDD_4") (pintype "passive"))
      (node (ref "U4") (pin "41") (pinfunction "DVDD_41") (pintype "passive"))
      (node (ref "U4") (pin "42") (pinfunction "DVDD_42") (pintype "passive"))
      (node (ref "U4") (pin "43") (pinfunction "DVDD_43") (pintype "passive"))
      (node (ref "U4") (pin "45") (pinfunction "DVDD_45") (pintype "passive"))
      (node (ref "U4") (pin "46") (pinfunction "DVDD_46") (pintype "passive"))
      (node (ref "U4") (pin "5") (pinfunction "DVDD_5") (pintype "passive"))
      (node (ref "U4") (pin "51") (pinfunction "DVDD_51") (pintype "passive"))
      (node (ref "U4") (pin "52") (pinfunction "DVDD_52") (pintype "passive"))
      (node (ref "U4") (pin "54") (pinfunction "DVDD_54") (pintype "passive"))
      (node (ref "U4") (pin "55") (pinfunction "DVDD_55") (pintype "passive"))
      (node (ref "U4") (pin "58") (pinfunction "DVDD_58") (pintype "passive"))
      (node (ref "U4") (pin "59") (pinfunction "DVDD_59") (pintype "passive"))
      (node (ref "U4") (pin "6") (pinfunction "DVDD_6") (pintype "passive"))
      (node (ref "U4") (pin "60") (pinfunction "DVDD_60") (pintype "passive"))
      (node (ref "U4") (pin "62") (pinfunction "DVDD_62") (pintype "passive"))
      (node (ref "U4") (pin "63") (pinfunction "DVDD_63") (pintype "passive"))
      (node (ref "U5") (pin "13") (pinfunction "DVDD_13") (pintype "passive"))
      (node (ref "U5") (pin "14") (pinfunction "DVDD_14") (pintype "passive"))
      (node (ref "U5") (pin "19") (pinfunction "DVDD_19") (pintype "passive"))
      (node (ref "U5") (pin "20") (pinfunction "DVDD_20") (pintype "passive"))
      (node (ref "U5") (pin "21") (pinfunction "DVDD_21") (pintype "passive"))
      (node (ref "U5") (pin "22") (pinfunction "DVDD_22") (pintype "passive"))
      (node (ref "U5") (pin "26") (pinfunction "DVDD_26") (pintype "passive"))
      (node (ref "U5") (pin "27") (pinfunction "DVDD_27") (pintype "passive"))
      (node (ref "U5") (pin "29") (pinfunction "DVDD_29") (pintype "passive"))
      (node (ref "U5") (pin "3") (pinfunction "DVDD_3") (pintype "passive"))
      (node (ref "U5") (pin "30") (pinfunction "DVDD_30") (pintype "passive"))
      (node (ref "U5") (pin "34") (pinfunction "DVDD_34") (pintype "passive"))
      (node (ref "U5") (pin "35") (pinfunction "DVDD_35") (pintype "passive"))
      (node (ref "U5") (pin "37") (pinfunction "DVDD_37") (pintype "passive"))
      (node (ref "U5") (pin "38") (pinfunction "DVDD_38") (pintype "passive"))
      (node (ref "U5") (pin "39") (pinfunction "DVDD_39") (pintype "passive"))
      (node (ref "U5") (pin "4") (pinfunction "DVDD_4") (pintype "passive"))
      (node (ref "U5") (pin "41") (pinfunction "DVDD_41") (pintype "passive"))
      (node (ref "U5") (pin "42") (pinfunction "DVDD_42") (pintype "passive"))
      (node (ref "U5") (pin "43") (pinfunction "DVDD_43") (pintype "passive"))
      (node (ref "U5") (pin "45") (pinfunction "DVDD_45") (pintype "passive"))
      (node (ref "U5") (pin "46") (pinfunction "DVDD_46") (pintype "passive"))
      (node (ref "U5") (pin "5") (pinfunction "DVDD_5") (pintype "passive"))
      (node (ref "U5") (pin "51") (pinfunction "DVDD_51") (pintype "passive"))
      (node (ref "U5") (pin "52") (pinfunction "DVDD_52") (pintype "passive"))
      (node (ref "U5") (pin "54") (pinfunction "DVDD_54") (pintype "passive"))
      (node (ref "U5") (pin "55") (pinfunction "DVDD_55") (pintype "passive"))
      (node (ref "U5") (pin "58") (pinfunction "DVDD_58") (pintype "passive"))
      (node (ref "U5") (pin "59") (pinfunction "DVDD_59") (pintype "passive"))
      (node (ref "U5") (pin "6") (pinfunction "DVDD_6") (pintype "passive"))
      (node (ref "U5") (pin "60") (pinfunction "DVDD_60") (pintype "passive"))
      (node (ref "U5") (pin "62") (pinfunction "DVDD_62") (pintype "passive"))
      (node (ref "U5") (pin "63") (pinfunction "DVDD_63") (pintype "passive"))
      (node (ref "U6") (pin "13") (pinfunction "DVDD_13") (pintype "passive"))
      (node (ref "U6") (pin "14") (pinfunction "DVDD_14") (pintype "passive"))
      (node (ref "U6") (pin "19") (pinfunction "DVDD_19") (pintype "passive"))
      (node (ref "U6") (pin "20") (pinfunction "DVDD_20") (pintype "passive"))
      (node (ref "U6") (pin "21") (pinfunction "DVDD_21") (pintype "passive"))
      (node (ref "U6") (pin "22") (pinfunction "DVDD_22") (pintype "passive"))
      (node (ref "U6") (pin "26") (pinfunction "DVDD_26") (pintype "passive"))
      (node (ref "U6") (pin "27") (pinfunction "DVDD_27") (pintype "passive"))
      (node (ref "U6") (pin "29") (pinfunction "DVDD_29") (pintype "passive"))
      (node (ref "U6") (pin "3") (pinfunction "DVDD_3") (pintype "passive"))
      (node (ref "U6") (pin "30") (pinfunction "DVDD_30") (pintype "passive"))
      (node (ref "U6") (pin "34") (pinfunction "DVDD_34") (pintype "passive"))
      (node (ref "U6") (pin "35") (pinfunction "DVDD_35") (pintype "passive"))
      (node (ref "U6") (pin "37") (pinfunction "DVDD_37") (pintype "passive"))
      (node (ref "U6") (pin "38") (pinfunction "DVDD_38") (pintype "passive"))
      (node (ref "U6") (pin "39") (pinfunction "DVDD_39") (pintype "passive"))
      (node (ref "U6") (pin "4") (pinfunction "DVDD_4") (pintype "passive"))
      (node (ref "U6") (pin "41") (pinfunction "DVDD_41") (pintype "passive"))
      (node (ref "U6") (pin "42") (pinfunction "DVDD_42") (pintype "passive"))
      (node (ref "U6") (pin "43") (pinfunction "DVDD_43") (pintype "passive"))
      (node (ref "U6") (pin "45") (pinfunction "DVDD_45") (pintype "passive"))
      (node (ref "U6") (pin "46") (pinfunction "DVDD_46") (pintype "passive"))
      (node (ref "U6") (pin "5") (pinfunction "DVDD_5") (pintype "passive"))
      (node (ref "U6") (pin "51") (pinfunction "DVDD_51") (pintype "passive"))
      (node (ref "U6") (pin "52") (pinfunction "DVDD_52") (pintype "passive"))
      (node (ref "U6") (pin "54") (pinfunction "DVDD_54") (pintype "passive"))
      (node (ref "U6") (pin "55") (pinfunction "DVDD_55") (pintype "passive"))
      (node (ref "U6") (pin "58") (pinfunction "DVDD_58") (pintype "passive"))
      (node (ref "U6") (pin "59") (pinfunction "DVDD_59") (pintype "passive"))
      (node (ref "U6") (pin "6") (pinfunction "DVDD_6") (pintype "passive"))
      (node (ref "U6") (pin "60") (pinfunction "DVDD_60") (pintype "passive"))
      (node (ref "U6") (pin "62") (pinfunction "DVDD_62") (pintype "passive"))
      (node (ref "U6") (pin "63") (pinfunction "DVDD_63") (pintype "passive"))
      (node (ref "U7") (pin "13") (pinfunction "DVDD_13") (pintype "passive"))
      (node (ref "U7") (pin "14") (pinfunction "DVDD_14") (pintype "passive"))
      (node (ref "U7") (pin "19") (pinfunction "DVDD_19") (pintype "passive"))
      (node (ref "U7") (pin "20") (pinfunction "DVDD_20") (pintype "passive"))
      (node (ref "U7") (pin "21") (pinfunction "DVDD_21") (pintype "passive"))
      (node (ref "U7") (pin "22") (pinfunction "DVDD_22") (pintype "passive"))
      (node (ref "U7") (pin "26") (pinfunction "DVDD_26") (pintype "passive"))
      (node (ref "U7") (pin "27") (pinfunction "DVDD_27") (pintype "passive"))
      (node (ref "U7") (pin "29") (pinfunction "DVDD_29") (pintype "passive"))
      (node (ref "U7") (pin "3") (pinfunction "DVDD_3") (pintype "passive"))
      (node (ref "U7") (pin "30") (pinfunction "DVDD_30") (pintype "passive"))
      (node (ref "U7") (pin "34") (pinfunction "DVDD_34") (pintype "passive"))
      (node (ref "U7") (pin "35") (pinfunction "DVDD_35") (pintype "passive"))
      (node (ref "U7") (pin "37") (pinfunction "DVDD_37") (pintype "passive"))
      (node (ref "U7") (pin "38") (pinfunction "DVDD_38") (pintype "passive"))
      (node (ref "U7") (pin "39") (pinfunction "DVDD_39") (pintype "passive"))
      (node (ref "U7") (pin "4") (pinfunction "DVDD_4") (pintype "passive"))
      (node (ref "U7") (pin "41") (pinfunction "DVDD_41") (pintype "passive"))
      (node (ref "U7") (pin "42") (pinfunction "DVDD_42") (pintype "passive"))
      (node (ref "U7") (pin "43") (pinfunction "DVDD_43") (pintype "passive"))
      (node (ref "U7") (pin "45") (pinfunction "DVDD_45") (pintype "passive"))
      (node (ref "U7") (pin "46") (pinfunction "DVDD_46") (pintype "passive"))
      (node (ref "U7") (pin "5") (pinfunction "DVDD_5") (pintype "passive"))
      (node (ref "U7") (pin "51") (pinfunction "DVDD_51") (pintype "passive"))
      (node (ref "U7") (pin "52") (pinfunction "DVDD_52") (pintype "passive"))
      (node (ref "U7") (pin "54") (pinfunction "DVDD_54") (pintype "passive"))
      (node (ref "U7") (pin "55") (pinfunction "DVDD_55") (pintype "passive"))
      (node (ref "U7") (pin "58") (pinfunction "DVDD_58") (pintype "passive"))
      (node (ref "U7") (pin "59") (pinfunction "DVDD_59") (pintype "passive"))
      (node (ref "U7") (pin "6") (pinfunction "DVDD_6") (pintype "passive"))
      (node (ref "U7") (pin "60") (pinfunction "DVDD_60") (pintype "passive"))
      (node (ref "U7") (pin "62") (pinfunction "DVDD_62") (pintype "passive"))
      (node (ref "U7") (pin "63") (pinfunction "DVDD_63") (pintype "passive"))
      (node (ref "U9") (pin "13") (pinfunction "DVDD_13") (pintype "passive"))
      (node (ref "U9") (pin "14") (pinfunction "DVDD_14") (pintype "passive"))
      (node (ref "U9") (pin "19") (pinfunction "DVDD_19") (pintype "passive"))
      (node (ref "U9") (pin "20") (pinfunction "DVDD_20") (pintype "passive"))
      (node (ref "U9") (pin "21") (pinfunction "DVDD_21") (pintype "passive"))
      (node (ref "U9") (pin "22") (pinfunction "DVDD_22") (pintype "passive"))
      (node (ref "U9") (pin "26") (pinfunction "DVDD_26") (pintype "passive"))
      (node (ref "U9") (pin "27") (pinfunction "DVDD_27") (pintype "passive"))
      (node (ref "U9") (pin "29") (pinfunction "DVDD_29") (pintype "passive"))
      (node (ref "U9") (pin "3") (pinfunction "DVDD_3") (pintype "passive"))
      (node (ref "U9") (pin "30") (pinfunction "DVDD_30") (pintype "passive"))
      (node (ref "U9") (pin "34") (pinfunction "DVDD_34") (pintype "passive"))
      (node (ref "U9") (pin "35") (pinfunction "DVDD_35") (pintype "passive"))
      (node (ref "U9") (pin "37") (pinfunction "DVDD_37") (pintype "passive"))
      (node (ref "U9") (pin "38") (pinfunction "DVDD_38") (pintype "passive"))
      (node (ref "U9") (pin "39") (pinfunction "DVDD_39") (pintype "passive"))
      (node (ref "U9") (pin "4") (pinfunction "DVDD_4") (pintype "passive"))
      (node (ref "U9") (pin "41") (pinfunction "DVDD_41") (pintype "passive"))
      (node (ref "U9") (pin "42") (pinfunction "DVDD_42") (pintype "passive"))
      (node (ref "U9") (pin "43") (pinfunction "DVDD_43") (pintype "passive"))
      (node (ref "U9") (pin "45") (pinfunction "DVDD_45") (pintype "passive"))
      (node (ref "U9") (pin "46") (pinfunction "DVDD_46") (pintype "passive"))
      (node (ref "U9") (pin "5") (pinfunction "DVDD_5") (pintype "passive"))
      (node (ref "U9") (pin "51") (pinfunction "DVDD_51") (pintype "passive"))
      (node (ref "U9") (pin "52") (pinfunction "DVDD_52") (pintype "passive"))
      (node (ref "U9") (pin "54") (pinfunction "DVDD_54") (pintype "passive"))
      (node (ref "U9") (pin "55") (pinfunction "DVDD_55") (pintype "passive"))
      (node (ref "U9") (pin "58") (pinfunction "DVDD_58") (pintype "passive"))
      (node (ref "U9") (pin "59") (pinfunction "DVDD_59") (pintype "passive"))
      (node (ref "U9") (pin "6") (pinfunction "DVDD_6") (pintype "passive"))
      (node (ref "U9") (pin "60") (pinfunction "DVDD_60") (pintype "passive"))
      (node (ref "U9") (pin "62") (pinfunction "DVDD_62") (pintype "passive"))
      (node (ref "U9") (pin "63") (pinfunction "DVDD_63") (pintype "passive"))
    )
    (net (code "2") (name "/3.3V") (class "Default")
      (node (ref "C122") (pin "2") (pinfunction "2_2") (pintype "passive"))
      (node (ref "C127") (pin "2") (pinfunction "2_2") (pintype "passive"))
      (node (ref "C132") (pin "2") (pinfunction "2_2") (pintype "passive"))
      (node (ref "C137") (pin "2") (pinfunction "2_2") (pintype "passive"))
      (node (ref "C167") (pin "1") (pinfunction "1_1") (pintype "passive"))
      (node (ref "C169") (pin "1") (pinfunction "1_1") (pintype "passive"))
      (node (ref "C170") (pin "1") (pinfunction "1_1") (pintype "passive"))
      (node (ref "C171") (pin "1") (pinfunction "1_1") (pintype "passive"))
      (node (ref "C172") (pin "1") (pinfunction "1_1") (pintype "passive"))
      (node (ref "C178") (pin "2") (pinfunction "2_2") (pintype "passive"))
      (node (ref "C182") (pin "2") (pinfunction "2_2") (pintype "passive"))
      (node (ref "C186") (pin "2") (pinfunction "2_2") (pintype "passive"))
      (node (ref "C190") (pin "2") (pinfunction "2_2") (pintype "passive"))
      (node (ref "C224") (pin "2") (pinfunction "2_2") (pintype "passive"))
      (node (ref "C225") (pin "1") (pinfunction "1_1") (pintype "passive"))
      (node (ref "C231") (pin "2") (pinfunction "2_2") (pintype "passive"))
      (node (ref "C236") (pin "2") (pinfunction "2_2") (pintype "passive"))
      (node (ref "C241") (pin "2") (pinfunction "2_2") (pintype "passive"))
      (node (ref "C246") (pin "2") (pinfunction "2_2") (pintype "passive"))
      (node (ref "C275") (pin "1") (pinfunction "1_1") (pintype "passive"))
      (node (ref "C279") (pin "2") (pinfunction "2_2") (pintype "passive"))
      (node (ref "C283") (pin "2") (pinfunction "2_2") (pintype "passive"))
      (node (ref "C287") (pin "2") (pinfunction "2_2") (pintype "passive"))
      (node (ref "C29") (pin "2") (pinfunction "2_2") (pintype "passive"))
      (node (ref "C291") (pin "2") (pinfunction "2_2") (pintype "passive"))
      (node (ref "C328") (pin "2") (pinfunction "2_2") (pintype "passive"))
      (node (ref "C333") (pin "2") (pinfunction "2_2") (pintype "passive"))
      (node (ref "C338") (pin "2") (pinfunction "2_2") (pintype "passive"))
      (node (ref "C34") (pin "2") (pinfunction "2_2") (pintype "passive"))
      (node (ref "C343") (pin "2") (pinfunction "2_2") (pintype "passive"))
      (node (ref "C371") (pin "2") (pinfunction "2_2") (pintype "passive"))
      (node (ref "C375") (pin "2") (pinfunction "2_2") (pintype "passive"))
      (node (ref "C379") (pin "2") (pinfunction "2_2") (pintype "passive"))
      (node (ref "C383") (pin "2") (pinfunction "2_2") (pintype "passive"))
      (node (ref "C39") (pin "2") (pinfunction "2_2") (pintype "passive"))
      (node (ref "C44") (pin "2") (pinfunction "2_2") (pintype "passive"))
      (node (ref "C69") (pin "1") (pinfunction "1_1") (pintype "passive"))
      (node (ref "C73") (pin "2") (pinfunction "2_2") (pintype "passive"))
      (node (ref "C77") (pin "2") (pinfunction "2_2") (pintype "passive"))
      (node (ref "C81") (pin "2") (pinfunction "2_2") (pintype "passive"))
      (node (ref "C85") (pin "2") (pinfunction "2_2") (pintype "passive"))
      (node (ref "J1") (pin "2") (pinfunction "2_2") (pintype "passive"))
      (node (ref "R31") (pin "2") (pinfunction "2_2") (pintype "passive"))
      (node (ref "R48") (pin "2") (pinfunction "2_2") (pintype "passive"))
      (node (ref "R5") (pin "2") (pinfunction "2_2") (pintype "passive"))
      (node (ref "R53") (pin "2") (pinfunction "2_2") (pintype "passive"))
      (node (ref "R54") (pin "1") (pinfunction "1_1") (pintype "passive"))
      (node (ref "R6") (pin "2") (pinfunction "2_2") (pintype "passive"))
      (node (ref "R7") (pin "2") (pinfunction "2_2") (pintype "passive"))
      (node (ref "R8") (pin "1") (pinfunction "1_1") (pintype "passive"))
      (node (ref "U10") (pin "16") (pinfunction "CHIP_ID0_16") (pintype "passive"))
      (node (ref "U10") (pin "18") (pinfunction "CHIP_ID2_18") (pintype "passive"))
      (node (ref "U10") (pin "32") (pinfunction "OVDD1_32") (pintype "passive"))
      (node (ref "U10") (pin "49") (pinfunction "OVDD0_49") (pintype "passive"))
      (node (ref "U11") (pin "17") (pinfunction "CHIP_ID1_17") (pintype "passive"))
      (node (ref "U11") (pin "18") (pinfunction "CHIP_ID2_18") (pintype "passive"))
      (node (ref "U11") (pin "32") (pinfunction "OVDD1_32") (pintype "passive"))
      (node (ref "U11") (pin "49") (pinfunction "OVDD0_49") (pintype "passive"))
      (node (ref "U12") (pin "16") (pinfunction "CHIP_ID0_16") (pintype "passive"))
      (node (ref "U12") (pin "17") (pinfunction "CHIP_ID1_17") (pintype "passive"))
      (node (ref "U12") (pin "18") (pinfunction "CHIP_ID2_18") (pintype "passive"))
      (node (ref "U12") (pin "32") (pinfunction "OVDD1_32") (pintype "passive"))
      (node (ref "U12") (pin "49") (pinfunction "OVDD0_49") (pintype "passive"))
      (node (ref "U14") (pin "5") (pinfunction "OUT_5") (pintype "passive"))
      (node (ref "U15") (pin "1") (pinfunction "OUT_1") (pintype "passive"))
      (node (ref "U18") (pin "32") (pinfunction "OVDD1_32") (pintype "passive"))
      (node (ref "U18") (pin "49") (pinfunction "OVDD0_49") (pintype "passive"))
      (node (ref "U19") (pin "16") (pinfunction "CHIP_ID0_16") (pintype "passive"))
      (node (ref "U19") (pin "32") (pinfunction "OVDD1_32") (pintype "passive"))
      (node (ref "U19") (pin "49") (pinfunction "OVDD0_49") (pintype "passive"))
      (node (ref "U20") (pin "17") (pinfunction "CHIP_ID1_17") (pintype "passive"))
      (node (ref "U20") (pin "32") (pinfunction "OVDD1_32") (pintype "passive"))
      (node (ref "U20") (pin "49") (pinfunction "OVDD0_49") (pintype "passive"))
      (node (ref "U21") (pin "17") (pinfunction "CHIP_ID1_17") (pintype "passive"))
      (node (ref "U21") (pin "18") (pinfunction "CHIP_ID2_18") (pintype "passive"))
      (node (ref "U21") (pin "32") (pinfunction "OVDD1_32") (pintype "passive"))
      (node (ref "U21") (pin "49") (pinfunction "OVDD0_49") (pintype "passive"))
      (node (ref "U24") (pin "18") (pinfunction "CHIP_ID2_18") (pintype "passive"))
      (node (ref "U24") (pin "32") (pinfunction "OVDD1_32") (pintype "passive"))
      (node (ref "U24") (pin "49") (pinfunction "OVDD0_49") (pintype "passive"))
      (node (ref "U25") (pin "16") (pinfunction "CHIP_ID0_16") (pintype "passive"))
      (node (ref "U25") (pin "18") (pinfunction "CHIP_ID2_18") (pintype "passive"))
      (node (ref "U25") (pin "32") (pinfunction "OVDD1_32") (pintype "passive"))
      (node (ref "U25") (pin "49") (pinfunction "OVDD0_49") (pintype "passive"))
      (node (ref "U26") (pin "17") (pinfunction "CHIP_ID1_17") (pintype "passive"))
      (node (ref "U26") (pin "18") (pinfunction "CHIP_ID2_18") (pintype "passive"))
      (node (ref "U26") (pin "32") (pinfunction "OVDD1_32") (pintype "passive"))
      (node (ref "U26") (pin "49") (pinfunction "OVDD0_49") (pintype "passive"))
      (node (ref "U27") (pin "16") (pinfunction "CHIP_ID0_16") (pintype "passive"))
      (node (ref "U27") (pin "17") (pinfunction "CHIP_ID1_17") (pintype "passive"))
      (node (ref "U27") (pin "18") (pinfunction "CHIP_ID2_18") (pintype "passive"))
      (node (ref "U27") (pin "32") (pinfunction "OVDD1_32") (pintype "passive"))
      (node (ref "U27") (pin "49") (pinfunction "OVDD0_49") (pintype "passive"))
      (node (ref "U4") (pin "32") (pinfunction "OVDD1_32") (pintype "passive"))
      (node (ref "U4") (pin "49") (pinfunction "OVDD0_49") (pintype "passive"))
      (node (ref "U5") (pin "16") (pinfunction "CHIP_ID0_16") (pintype "passive"))
      (node (ref "U5") (pin "32") (pinfunction "OVDD1_32") (pintype "passive"))
      (node (ref "U5") (pin "49") (pinfunction "OVDD0_49") (pintype "passive"))
      (node (ref "U6") (pin "17") (pinfunction "CHIP_ID1_17") (pintype "passive"))
      (node (ref "U6") (pin "32") (pinfunction "OVDD1_32") (pintype "passive"))
      (node (ref "U6") (pin "49") (pinfunction "OVDD0_49") (pintype "passive"))
      (node (ref "U7") (pin "16") (pinfunction "CHIP_ID0_16") (pintype "passive"))
      (node (ref "U7") (pin "17") (pinfunction "CHIP_ID1_17") (pintype "passive"))
      (node (ref "U7") (pin "32") (pinfunction "OVDD1_32") (pintype "passive"))
      (node (ref "U7") (pin "49") (pinfunction "OVDD0_49") (pintype "passive"))
      (node (ref "U8") (pin "10") (pinfunction "VDD_10") (pintype "passive"))
      (node (ref "U8") (pin "19") (pinfunction "AVDD_19") (pintype "passive"))
      (node (ref "U8") (pin "26") (pinfunction "VDD_26") (pintype "passive"))
      (node (ref "U8") (pin "35") (pinfunction "VUSB3V3_35") (pintype "passive"))
      (node (ref "U8") (pin "38") (pinfunction "VDD_38") (pintype "passive"))
      (node (ref "U8") (pin "57") (pinfunction "VDD_57") (pintype "passive"))
      (node (ref "U9") (pin "18") (pinfunction "CHIP_ID2_18") (pintype "passive"))
      (node (ref "U9") (pin "32") (pinfunction "OVDD1_32") (pintype "passive"))
      (node (ref "U9") (pin "49") (pinfunction "OVDD0_49") (pintype "passive"))
    )
    (net (code "3") (name "/5.0V") (class "Default")
      (node (ref "C1") (pin "2") (pinfunction "2_2") (pintype "passive"))
      (node (ref "C191") (pin "1") (pinfunction "1_1") (pintype "passive"))
      (node (ref "C2") (pin "2") (pinfunction "2_2") (pintype "passive"))
      (node (ref "C3") (pin "2") (pinfunction "2_2") (pintype "passive"))
      (node (ref "D1") (pin "1") (pinfunction "A1_1") (pintype "passive"))
      (node (ref "D1") (pin "2") (pinfunction "A2_2") (pintype "passive"))
      (node (ref "D10") (pin "1") (pinfunction "C_1") (pintype "passive"))
      (node (ref "D2") (pin "1") (pinfunction "A1_1") (pintype "passive"))
      (node (ref "D2") (pin "2") (pinfunction "A2_2") (pintype "passive"))
      (node (ref "D3") (pin "1") (pinfunction "A1_1") (pintype "passive"))
      (node (ref "D3") (pin "2") (pinfunction "A2_2") (pintype "passive"))
      (node (ref "D8") (pin "2") (pinfunction "A_2") (pintype "passive"))
      (node (ref "J3") (pin "1") (pinfunction "1_1") (pintype "passive"))
      (node (ref "R42") (pin "1") (pinfunction "1_1") (pintype "passive"))
      (node (ref "U1") (pin "7") (pinfunction "VCC_7") (pintype "passive"))
      (node (ref "U13") (pin "1") (pinfunction "OUTPUT_1") (pintype "passive"))
      (node (ref "U16") (pin "3") (pinfunction "Vout_3") (pintype "passive"))
      (node (ref "U17") (pin "3") (pinfunction "Vout_3") (pintype "passive"))
      (node (ref "U2") (pin "7") (pinfunction "VCC_7") (pintype "passive"))
      (node (ref "U3") (pin "7") (pinfunction "VCC_7") (pintype "passive"))
    )
    (net (code "4") (name "/12V") (class "Default")
      (node (ref "C10") (pin "2") (pinfunction "2_2") (pintype "passive"))
      (node (ref "C11") (pin "2") (pinfunction "2_2") (pintype "passive"))
      (node (ref "C15") (pin "2") (pinfunction "2_2") (pintype "passive"))
      (node (ref "C16") (pin "2") (pinfunction "2_2") (pintype "passive"))
      (node (ref "C20") (pin "1") (pinfunction "1_1") (pintype "passive"))
      (node (ref "C21") (pin "1") (pinfunction "1_1") (pintype "passive"))
      (node (ref "D11") (pin "2") (pinfunction "A_2") (pintype "passive"))
      (node (ref "D12") (pin "1") (pinfunction "C_1") (pintype "passive"))
      (node (ref "J3") (pin "3") (pinfunction "3_3") (pintype "passive"))
      (node (ref "J4") (pin "1") (pinfunction "1_1") (pintype "passive"))
      (node (ref "J4") (pin "2") (pinfunction "2_2") (pintype "passive"))
      (node (ref "J4") (pin "3") (pinfunction "3_3") (pintype "passive"))
      (node (ref "Q1") (pin "5") (pinfunction "D_5") (pintype "passive"))
      (node (ref "Q1") (pin "6") (pinfunction "D_6") (pintype "passive"))
      (node (ref "Q1") (pin "7") (pinfunction "D_7") (pintype "passive"))
      (node (ref "Q1") (pin "8") (pinfunction "D_8") (pintype "passive"))
      (node (ref "Q2") (pin "5") (pinfunction "D_5") (pintype "passive"))
      (node (ref "Q2") (pin "6") (pinfunction "D_6") (pintype "passive"))
      (node (ref "Q2") (pin "7") (pinfunction "D_7") (pintype "passive"))
      (node (ref "Q2") (pin "8") (pinfunction "D_8") (pintype "passive"))
      (node (ref "Q3") (pin "5") (pinfunction "D_5") (pintype "passive"))
      (node (ref "Q3") (pin "6") (pinfunction "D_6") (pintype "passive"))
      (node (ref "Q3") (pin "7") (pinfunction "D_7") (pintype "passive"))
      (node (ref "Q3") (pin "8") (pinfunction "D_8") (pintype "passive"))
      (node (ref "R23") (pin "1") (pinfunction "1_1") (pintype "passive"))
      (node (ref "R47") (pin "2") (pinfunction "2_2") (pintype "passive"))
    )
    (net (code "5") (name "/ASIC_RESET_MCU") (class "Default")
      (node (ref "C120") (pin "2") (pinfunction "2_2") (pintype "passive"))
      (node (ref "C125") (pin "2") (pinfunction "2_2") (pintype "passive"))
      (node (ref "C130") (pin "2") (pinfunction "2_2") (pintype "passive"))
      (node (ref "C135") (pin "2") (pinfunction "2_2") (pintype "passive"))
      (node (ref "C229") (pin "2") (pinfunction "2_2") (pintype "passive"))
      (node (ref "C234") (pin "2") (pinfunction "2_2") (pintype "passive"))
      (node (ref "C239") (pin "2") (pinfunction "2_2") (pintype "passive"))
      (node (ref "C244") (pin "2") (pinfunction "2_2") (pintype "passive"))
      (node (ref "C27") (pin "2") (pinfunction "2_2") (pintype "passive"))
      (node (ref "C32") (pin "2") (pinfunction "2_2") (pintype "passive"))
      (node (ref "C326") (pin "2") (pinfunction "2_2") (pintype "passive"))
      (node (ref "C331") (pin "2") (pinfunction "2_2") (pintype "passive"))
      (node (ref "C336") (pin "2") (pinfunction "2_2") (pintype "passive"))
      (node (ref "C341") (pin "2") (pinfunction "2_2") (pintype "passive"))
      (node (ref "C37") (pin "2") (pinfunction "2_2") (pintype "passive"))
      (node (ref "C42") (pin "2") (pinfunction "2_2") (pintype "passive"))
      (node (ref "R5") (pin "1") (pinfunction "1_1") (pintype "passive"))
      (node (ref "U10") (pin "57") (pinfunction "RSTN_57") (pintype "passive"))
      (node (ref "U11") (pin "57") (pinfunction "RSTN_57") (pintype "passive"))
      (node (ref "U12") (pin "57") (pinfunction "RSTN_57") (pintype "passive"))
      (node (ref "U18") (pin "57") (pinfunction "RSTN_57") (pintype "passive"))
      (node (ref "U19") (pin "57") (pinfunction "RSTN_57") (pintype "passive"))
      (node (ref "U20") (pin "57") (pinfunction "RSTN_57") (pintype "passive"))
      (node (ref "U21") (pin "57") (pinfunction "RSTN_57") (pintype "passive"))
      (node (ref "U24") (pin "57") (pinfunction "RSTN_57") (pintype "passive"))
      (node (ref "U25") (pin "57") (pinfunction "RSTN_57") (pintype "passive"))
      (node (ref "U26") (pin "57") (pinfunction "RSTN_57") (pintype "passive"))
      (node (ref "U27") (pin "57") (pinfunction "RSTN_57") (pintype "passive"))
      (node (ref "U4") (pin "57") (pinfunction "RSTN_57") (pintype "passive"))
      (node (ref "U5") (pin "57") (pinfunction "RSTN_57") (pintype "passive"))
      (node (ref "U6") (pin "57") (pinfunction "RSTN_57") (pintype "passive"))
      (node (ref "U7") (pin "57") (pinfunction "RSTN_57") (pintype "passive"))
      (node (ref "U8") (pin "5") (pinfunction "C1IN1-/SDI2/PMA4/RPI119/RG7_5") (pintype "passive"))
      (node (ref "U9") (pin "57") (pinfunction "RSTN_57") (pintype "passive"))
    )
    (net (code "6") (name "/BOOT1") (class "Default")
      (node (ref "C7") (pin "1") (pinfunction "1_1") (pintype "passive"))
      (node (ref "D1") (pin "3") (pinfunction "CC_3") (pintype "passive"))
      (node (ref "U1") (pin "8") (pinfunction "BOOST_8") (pintype "passive"))
    )
    (net (code "7") (name "/BOOT2") (class "Default")
      (node (ref "C8") (pin "1") (pinfunction "1_1") (pintype "passive"))
      (node (ref "D2") (pin "3") (pinfunction "CC_3") (pintype "passive"))
      (node (ref "U2") (pin "8") (pinfunction "BOOST_8") (pintype "passive"))
    )
    (net (code "8") (name "/BOOT3") (class "Default")
      (node (ref "C9") (pin "1") (pinfunction "1_1") (pintype "passive"))
      (node (ref "D3") (pin "3") (pinfunction "CC_3") (pintype "passive"))
      (node (ref "U3") (pin "8") (pinfunction "BOOST_8") (pintype "passive"))
    )
    (net (code "9") (name "/CORE_CLKOUT_1") (class "Default")
      (node (ref "R1") (pin "2") (pinfunction "2_2") (pintype "passive"))
      (node (ref "U4") (pin "56") (pinfunction "CORE_CLKOUT_56") (pintype "passive"))
    )
    (net (code "10") (name "/CORE_CLKOUT_2") (class "Default")
      (node (ref "R2") (pin "2") (pinfunction "2_2") (pintype "passive"))
      (node (ref "U5") (pin "56") (pinfunction "CORE_CLKOUT_56") (pintype "passive"))
    )
    (net (code "11") (name "/CORE_CLKOUT_3") (class "Default")
      (node (ref "R3") (pin "2") (pinfunction "2_2") (pintype "passive"))
      (node (ref "U6") (pin "56") (pinfunction "CORE_CLKOUT_56") (pintype "passive"))
    )
    (net (code "12") (name "/CORE_CLKOUT_4") (class "Default")
      (node (ref "R4") (pin "2") (pinfunction "2_2") (pintype "passive"))
      (node (ref "U7") (pin "56") (pinfunction "CORE_CLKOUT_56") (pintype "passive"))
    )
    (net (code "13") (name "/CORE_CLKOUT_5") (class "Default")
      (node (ref "R17") (pin "1") (pinfunction "1_1") (pintype "passive"))
      (node (ref "U9") (pin "56") (pinfunction "CORE_CLKOUT_56") (pintype "passive"))
    )
    (net (code "14") (name "/CORE_CLKOUT_6") (class "Default")
      (node (ref "R18") (pin "2") (pinfunction "2_2") (pintype "passive"))
      (node (ref "U10") (pin "56") (pinfunction "CORE_CLKOUT_56") (pintype "passive"))
    )
    (net (code "15") (name "/CORE_CLKOUT_7") (class "Default")
      (node (ref "R19") (pin "2") (pinfunction "2_2") (pintype "passive"))
      (node (ref "U11") (pin "56") (pinfunction "CORE_CLKOUT_56") (pintype "passive"))
    )
    (net (code "16") (name "/CORE_CLKOUT_8") (class "Default")
      (node (ref "R20") (pin "2") (pinfunction "2_2") (pintype "passive"))
      (node (ref "U12") (pin "56") (pinfunction "CORE_CLKOUT_56") (pintype "passive"))
    )
    (net (code "17") (name "/CORE_CLKOUT_9") (class "Default")
      (node (ref "R43") (pin "2") (pinfunction "2_2") (pintype "passive"))
      (node (ref "U18") (pin "56") (pinfunction "CORE_CLKOUT_56") (pintype "passive"))
    )
    (net (code "18") (name "/CORE_CLKOUT_10") (class "Default")
      (node (ref "R44") (pin "2") (pinfunction "2_2") (pintype "passive"))
      (node (ref "U19") (pin "56") (pinfunction "CORE_CLKOUT_56") (pintype "passive"))
    )
    (net (code "19") (name "/CORE_CLKOUT_11") (class "Default")
      (node (ref "R45") (pin "2") (pinfunction "2_2") (pintype "passive"))
      (node (ref "U20") (pin "56") (pinfunction "CORE_CLKOUT_56") (pintype "passive"))
    )
    (net (code "20") (name "/CORE_CLKOUT_12") (class "Default")
      (node (ref "R46") (pin "2") (pinfunction "2_2") (pintype "passive"))
      (node (ref "U21") (pin "56") (pinfunction "CORE_CLKOUT_56") (pintype "passive"))
    )
    (net (code "21") (name "/CORE_CLKOUT_13") (class "Default")
      (node (ref "R64") (pin "2") (pinfunction "2_2") (pintype "passive"))
      (node (ref "U24") (pin "56") (pinfunction "CORE_CLKOUT_56") (pintype "passive"))
    )
    (net (code "22") (name "/CORE_CLKOUT_14") (class "Default")
      (node (ref "R65") (pin "2") (pinfunction "2_2") (pintype "passive"))
      (node (ref "U25") (pin "56") (pinfunction "CORE_CLKOUT_56") (pintype "passive"))
    )
    (net (code "23") (name "/CORE_CLKOUT_15") (class "Default")
      (node (ref "R66") (pin "2") (pinfunction "2_2") (pintype "passive"))
      (node (ref "U26") (pin "56") (pinfunction "CORE_CLKOUT_56") (pintype "passive"))
    )
    (net (code "24") (name "/CORE_CLKOUT_16") (class "Default")
      (node (ref "R67") (pin "2") (pinfunction "2_2") (pintype "passive"))
      (node (ref "U27") (pin "56") (pinfunction "CORE_CLKOUT_56") (pintype "passive"))
    )
    (net (code "25") (name "/D+") (class "Default")
      (node (ref "D9") (pin "1") (pinfunction "1_1") (pintype "passive"))
      (node (ref "J2") (pin "3") (pinfunction "3_3") (pintype "passive"))
      (node (ref "U8") (pin "37") (pinfunction "D+/RG2_37") (pintype "passive"))
    )
    (net (code "26") (name "/D-") (class "Default")
      (node (ref "D9") (pin "3") (pinfunction "3_3") (pintype "passive"))
      (node (ref "J2") (pin "2") (pinfunction "2_2") (pintype "passive"))
      (node (ref "U8") (pin "36") (pinfunction "D-/RG3_36") (pintype "passive"))
    )
    (net (code "27") (name "/DRVLogic") (class "Default")
      (node (ref "C4") (pin "1") (pinfunction "1_1") (pintype "passive"))
      (node (ref "C5") (pin "1") (pinfunction "1_1") (pintype "passive"))
      (node (ref "C6") (pin "1") (pinfunction "1_1") (pintype "passive"))
      (node (ref "U1") (pin "6") (pinfunction "VLOGIC_6") (pintype "passive"))
      (node (ref "U2") (pin "6") (pinfunction "VLOGIC_6") (pintype "passive"))
      (node (ref "U3") (pin "6") (pinfunction "VLOGIC_6") (pintype "passive"))
      (node (ref "U8") (pin "55") (pinfunction "C3IN1+/VCMPST3/RP71/RD7_55") (pintype "passive"))
    )
    (net (code "28") (name "/FB") (class "Default")
      (node (ref "C166") (pin "1") (pinfunction "1_1") (pintype "passive"))
      (node (ref "R26") (pin "1") (pinfunction "1_1") (pintype "passive"))
      (node (ref "U8") (pin "17") (pinfunction "PGEC1/AN6/RPI38/RB6_17") (pintype "passive"))
    )
    (net (code "29") (name "/GREEN") (class "Default")
      (node (ref "D5") (pin "2") (pinfunction "A_2") (pintype "passive"))
      (node (ref "U8") (pin "47") (pinfunction "PGED2/SOSCI/C3IN3-/RPI61/RC13_47") (pintype "passive"))
    )
    (net (code "30") (name "/HO1") (class "Default")
      (node (ref "Q2") (pin "4") (pinfunction "G_4") (pintype "passive"))
      (node (ref "U1") (pin "1") (pinfunction "TG_1") (pintype "passive"))
    )
    (net (code "31") (name "/HO2") (class "Default")
      (node (ref "Q3") (pin "4") (pinfunction "G_4") (pintype "passive"))
      (node (ref "U2") (pin "1") (pinfunction "TG_1") (pintype "passive"))
    )
    (net (code "32") (name "/HO3") (class "Default")
      (node (ref "Q1") (pin "4") (pinfunction "G_4") (pintype "passive"))
      (node (ref "U3") (pin "1") (pinfunction "TG_1") (pintype "passive"))
    )
    (net (code "33") (name "/LDO3.3V-5.0V") (class "Default")
      (node (ref "R48") (pin "1") (pinfunction "1_1") (pintype "passive"))
      (node (ref "R49") (pin "1") (pinfunction "1_1") (pintype "passive"))
      (node (ref "U22") (pin "5") (pinfunction "CTL_5") (pintype "passive"))
      (node (ref "U22") (pin "8") (pinfunction "VCC_8") (pintype "passive"))
      (node (ref "U23") (pin "5") (pinfunction "CTL_5") (pintype "passive"))
      (node (ref "U23") (pin "8") (pinfunction "VCC_8") (pintype "passive"))
    )
    (net (code "34") (name "/LDO5.0V") (class "Default")
      (node (ref "C226") (pin "1") (pinfunction "1_1") (pintype "passive"))
      (node (ref "D10") (pin "2") (pinfunction "A_2") (pintype "passive"))
      (node (ref "D8") (pin "1") (pinfunction "C_1") (pintype "passive"))
      (node (ref "R33") (pin "1") (pinfunction "1_1") (pintype "passive"))
      (node (ref "R42") (pin "2") (pinfunction "2_2") (pintype "passive"))
      (node (ref "R49") (pin "2") (pinfunction "2_2") (pintype "passive"))
      (node (ref "U14") (pin "1") (pinfunction "IN_1") (pintype "passive"))
      (node (ref "U14") (pin "3") (pinfunction "EN_3") (pintype "passive"))
      (node (ref "U15") (pin "5") (pinfunction "CTL_5") (pintype "passive"))
      (node (ref "U15") (pin "8") (pinfunction "VCC_8") (pintype "passive"))
    )
    (net (code "35") (name "/LM12V") (class "Default")
      (node (ref "D11") (pin "1") (pinfunction "C_1") (pintype "passive"))
      (node (ref "R47") (pin "1") (pinfunction "1_1") (pintype "passive"))
      (node (ref "U13") (pin "8") (pinfunction "INPUT_8") (pintype "passive"))
      (node (ref "U16") (pin "1") (pinfunction "Vin_1") (pintype "passive"))
      (node (ref "U17") (pin "1") (pinfunction "Vin_1") (pintype "passive"))
    )
    (net (code "36") (name "/LO1") (class "Default")
      (node (ref "Q6") (pin "4") (pinfunction "G_4") (pintype "passive"))
      (node (ref "Q7") (pin "4") (pinfunction "G_4") (pintype "passive"))
      (node (ref "U1") (pin "3") (pinfunction "BG_3") (pintype "passive"))
    )
    (net (code "37") (name "/LO2") (class "Default")
      (node (ref "Q8") (pin "4") (pinfunction "G_4") (pintype "passive"))
      (node (ref "Q9") (pin "4") (pinfunction "G_4") (pintype "passive"))
      (node (ref "U2") (pin "3") (pinfunction "BG_3") (pintype "passive"))
    )
    (net (code "38") (name "/LO3") (class "Default")
      (node (ref "Q4") (pin "4") (pinfunction "G_4") (pintype "passive"))
      (node (ref "Q5") (pin "4") (pinfunction "G_4") (pintype "passive"))
      (node (ref "U3") (pin "3") (pinfunction "BG_3") (pintype "passive"))
    )
    (net (code "39") (name "/LTC_EN") (class "Default")
      (node (ref "R6") (pin "1") (pinfunction "1_1") (pintype "passive"))
      (node (ref "U10") (pin "47") (pinfunction "LTC_EN_47") (pintype "passive"))
      (node (ref "U11") (pin "47") (pinfunction "LTC_EN_47") (pintype "passive"))
      (node (ref "U12") (pin "47") (pinfunction "LTC_EN_47") (pintype "passive"))
      (node (ref "U18") (pin "47") (pinfunction "LTC_EN_47") (pintype "passive"))
      (node (ref "U19") (pin "47") (pinfunction "LTC_EN_47") (pintype "passive"))
      (node (ref "U20") (pin "47") (pinfunction "LTC_EN_47") (pintype "passive"))
      (node (ref "U21") (pin "47") (pinfunction "LTC_EN_47") (pintype "passive"))
      (node (ref "U24") (pin "47") (pinfunction "LTC_EN_47") (pintype "passive"))
      (node (ref "U25") (pin "47") (pinfunction "LTC_EN_47") (pintype "passive"))
      (node (ref "U26") (pin "47") (pinfunction "LTC_EN_47") (pintype "passive"))
      (node (ref "U27") (pin "47") (pinfunction "LTC_EN_47") (pintype "passive"))
      (node (ref "U4") (pin "47") (pinfunction "LTC_EN_47") (pintype "passive"))
      (node (ref "U5") (pin "47") (pinfunction "LTC_EN_47") (pintype "passive"))
      (node (ref "U6") (pin "47") (pinfunction "LTC_EN_47") (pintype "passive"))
      (node (ref "U7") (pin "47") (pinfunction "LTC_EN_47") (pintype "passive"))
      (node (ref "U8") (pin "23") (pinfunction "TMS/AN10/CVREF/PMA13/RPI42/RB10_23") (pintype "passive"))
      (node (ref "U9") (pin "47") (pinfunction "LTC_EN_47") (pintype "passive"))
    )
    (net (code "40") (name "/MCLR") (class "Default")
      (node (ref "C168") (pin "1") (pinfunction "1_1") (pintype "passive"))
      (node (ref "J1") (pin "1") (pinfunction "1_1") (pintype "passive"))
      (node (ref "R31") (pin "1") (pinfunction "1_1") (pintype "passive"))
      (node (ref "U8") (pin "7") (pinfunction "~{MCLR}_7") (pintype "passive"))
    )
    (net (code "41") (name "/MCU5.0V") (class "Default")
      (node (ref "R32") (pin "2") (pinfunction "2_2") (pintype "passive"))
      (node (ref "U8") (pin "34") (pinfunction "VBUS_34") (pintype "passive"))
    )
    (net (code "42") (name "/MEAS12") (class "Default")
      (node (ref "C138") (pin "1") (pinfunction "1_1") (pintype "passive"))
      (node (ref "R23") (pin "2") (pinfunction "2_2") (pintype "passive"))
      (node (ref "R25") (pin "2") (pinfunction "2_2") (pintype "passive"))
      (node (ref "U8") (pin "18") (pinfunction "PGED1/AN7/RCV/RPI39/RB7_18") (pintype "passive"))
    )
    (net (code "43") (name "/Main OSC In") (class "Default")
      (node (ref "C173") (pin "1") (pinfunction "1_1") (pintype "passive"))
      (node (ref "U8") (pin "39") (pinfunction "OSC1/RPI60/RC12_39") (pintype "passive"))
      (node (ref "Y1") (pin "1") (pinfunction "1_1") (pintype "passive"))
    )
    (net (code "44") (name "/Main OSC Out") (class "Default")
      (node (ref "C174") (pin "1") (pinfunction "1_1") (pintype "passive"))
      (node (ref "U8") (pin "40") (pinfunction "OSC2/CLKO/RC15_40") (pintype "passive"))
      (node (ref "Y1") (pin "2") (pinfunction "2_2") (pintype "passive"))
    )
    (net (code "45") (name "/ORANGE") (class "Default")
      (node (ref "D7") (pin "2") (pinfunction "A_2") (pintype "passive"))
      (node (ref "U8") (pin "45") (pinfunction "PMCS1/RPI75/RD11_45") (pintype "passive"))
    )
    (net (code "46") (name "/PGC") (class "Default")
      (node (ref "J1") (pin "5") (pinfunction "5_5") (pintype "passive"))
      (node (ref "U8") (pin "15") (pinfunction "PGEC3/AN1/VREF-/RPI33/RB1_15") (pintype "passive"))
    )
    (net (code "47") (name "/PGD") (class "Default")
      (node (ref "J1") (pin "4") (pinfunction "4_4") (pintype "passive"))
      (node (ref "U8") (pin "16") (pinfunction "PGED3/AN0/VREF+/RPI32/RB0_16") (pintype "passive"))
    )
    (net (code "48") (name "/PLL_SUP") (class "Default")
      (node (ref "C259") (pin "1") (pinfunction "1_1") (pintype "passive"))
      (node (ref "C260") (pin "1") (pinfunction "1_1") (pintype "passive"))
      (node (ref "C274") (pin "1") (pinfunction "1_1") (pintype "passive"))
      (node (ref "FB1") (pin "1") (pinfunction "1_1") (pintype "passive"))
      (node (ref "R50") (pin "1") (pinfunction "1_1") (pintype "passive"))
      (node (ref "R52") (pin "1") (pinfunction "1_1") (pintype "passive"))
      (node (ref "U22") (pin "1") (pinfunction "OUT_1") (pintype "passive"))
      (node (ref "U23") (pin "1") (pinfunction "OUT_1") (pintype "passive"))
    )
    (net (code "49") (name "/PWM2H") (class "Default")
      (node (ref "R22") (pin "1") (pinfunction "1_1") (pintype "passive"))
      (node (ref "U2") (pin "5") (pinfunction "IN_5") (pintype "passive"))
      (node (ref "U8") (pin "63") (pinfunction "AN27/PWM2H/PMD3/RPI83/RE3_63") (pintype "passive"))
    )
    (net (code "50") (name "/PWM2L") (class "Default")
      (node (ref "R24") (pin "1") (pinfunction "1_1") (pintype "passive"))
      (node (ref "U1") (pin "5") (pinfunction "IN_5") (pintype "passive"))
      (node (ref "U8") (pin "62") (pinfunction "AN26/PWM2L/PMD2/RP82/RE2_62") (pintype "passive"))
    )
    (net (code "51") (name "/PWM3L") (class "Default")
      (node (ref "R21") (pin "1") (pinfunction "1_1") (pintype "passive"))
      (node (ref "U3") (pin "5") (pinfunction "IN_5") (pintype "passive"))
      (node (ref "U8") (pin "64") (pinfunction "AN28/PWM3L/PMD4/RP84/RE4_64") (pintype "passive"))
    )
    (net (code "52") (name "/RED") (class "Default")
      (node (ref "D4") (pin "2") (pinfunction "A_2") (pintype "passive"))
      (node (ref "U8") (pin "48") (pinfunction "PGEC2/SOSCO/C3IN1-/T1CK/RPI62/RC14_48") (pintype "passive"))
    )
    (net (code "53") (name "/RX_BTC_0") (class "Default")
      (node (ref "U10") (pin "1") (pinfunction "CFG_P_1") (pintype "passive"))
      (node (ref "U11") (pin "1") (pinfunction "CFG_P_1") (pintype "passive"))
      (node (ref "U12") (pin "1") (pinfunction "CFG_P_1") (pintype "passive"))
      (node (ref "U4") (pin "1") (pinfunction "CFG_P_1") (pintype "passive"))
      (node (ref "U5") (pin "1") (pinfunction "CFG_P_1") (pintype "passive"))
      (node (ref "U6") (pin "1") (pinfunction "CFG_P_1") (pintype "passive"))
      (node (ref "U7") (pin "1") (pinfunction "CFG_P_1") (pintype "passive"))
      (node (ref "U8") (pin "59") (pinfunction "VCMPST2/RP97/RF1_59") (pintype "passive"))
      (node (ref "U9") (pin "1") (pinfunction "CFG_P_1") (pintype "passive"))
    )
    (net (code "54") (name "/RX_BTC_1") (class "Default")
      (node (ref "U18") (pin "1") (pinfunction "CFG_P_1") (pintype "passive"))
      (node (ref "U19") (pin "1") (pinfunction "CFG_P_1") (pintype "passive"))
      (node (ref "U20") (pin "1") (pinfunction "CFG_P_1") (pintype "passive"))
      (node (ref "U21") (pin "1") (pinfunction "CFG_P_1") (pintype "passive"))
      (node (ref "U24") (pin "1") (pinfunction "CFG_P_1") (pintype "passive"))
      (node (ref "U25") (pin "1") (pinfunction "CFG_P_1") (pintype "passive"))
      (node (ref "U26") (pin "1") (pinfunction "CFG_P_1") (pintype "passive"))
      (node (ref "U27") (pin "1") (pinfunction "CFG_P_1") (pintype "passive"))
      (node (ref "U8") (pin "3") (pinfunction "AN31/PWM4H/PMD7/RP87/RE7_3") (pintype "passive"))
    )
    (net (code "55") (name "/RX_LTC_0") (class "Default")
      (node (ref "U10") (pin "2") (pinfunction "CFG_N_2") (pintype "passive"))
      (node (ref "U11") (pin "2") (pinfunction "CFG_N_2") (pintype "passive"))
      (node (ref "U12") (pin "2") (pinfunction "CFG_N_2") (pintype "passive"))
      (node (ref "U4") (pin "2") (pinfunction "CFG_N_2") (pintype "passive"))
      (node (ref "U5") (pin "2") (pinfunction "CFG_N_2") (pintype "passive"))
      (node (ref "U6") (pin "2") (pinfunction "CFG_N_2") (pintype "passive"))
      (node (ref "U7") (pin "2") (pinfunction "CFG_N_2") (pintype "passive"))
      (node (ref "U8") (pin "58") (pinfunction "VCMPST1/RP96/RF0_58") (pintype "passive"))
      (node (ref "U9") (pin "2") (pinfunction "CFG_N_2") (pintype "passive"))
    )
    (net (code "56") (name "/RX_LTC_1") (class "Default")
      (node (ref "U18") (pin "2") (pinfunction "CFG_N_2") (pintype "passive"))
      (node (ref "U19") (pin "2") (pinfunction "CFG_N_2") (pintype "passive"))
      (node (ref "U20") (pin "2") (pinfunction "CFG_N_2") (pintype "passive"))
      (node (ref "U21") (pin "2") (pinfunction "CFG_N_2") (pintype "passive"))
      (node (ref "U24") (pin "2") (pinfunction "CFG_N_2") (pintype "passive"))
      (node (ref "U25") (pin "2") (pinfunction "CFG_N_2") (pintype "passive"))
      (node (ref "U26") (pin "2") (pinfunction "CFG_N_2") (pintype "passive"))
      (node (ref "U27") (pin "2") (pinfunction "CFG_N_2") (pintype "passive"))
      (node (ref "U8") (pin "4") (pinfunction "C1IN3-/SCK2/PMA5/RP118/RG6_4") (pintype "passive"))
    )
    (net (code "57") (name "/SWN1") (class "Default")
      (node (ref "C7") (pin "2") (pinfunction "2_2") (pintype "passive"))
      (node (ref "L1") (pin "1") (pinfunction "1_1") (pintype "passive"))
      (node (ref "Q2") (pin "1") (pinfunction "S_1") (pintype "passive"))
      (node (ref "Q2") (pin "2") (pinfunction "S_2") (pintype "passive"))
      (node (ref "Q2") (pin "3") (pinfunction "S_3") (pintype "passive"))
      (node (ref "Q6") (pin "5") (pinfunction "D_5") (pintype "passive"))
      (node (ref "Q6") (pin "6") (pinfunction "D_6") (pintype "passive"))
      (node (ref "Q6") (pin "7") (pinfunction "D_7") (pintype "passive"))
      (node (ref "Q6") (pin "8") (pinfunction "D_8") (pintype "passive"))
      (node (ref "Q7") (pin "5") (pinfunction "D_5") (pintype "passive"))
      (node (ref "Q7") (pin "6") (pinfunction "D_6") (pintype "passive"))
      (node (ref "Q7") (pin "7") (pinfunction "D_7") (pintype "passive"))
      (node (ref "Q7") (pin "8") (pinfunction "D_8") (pintype "passive"))
      (node (ref "U1") (pin "2") (pinfunction "TS_2") (pintype "passive"))
    )
    (net (code "58") (name "/SWN2") (class "Default")
      (node (ref "C8") (pin "2") (pinfunction "2_2") (pintype "passive"))
      (node (ref "L2") (pin "1") (pinfunction "1_1") (pintype "passive"))
      (node (ref "Q3") (pin "1") (pinfunction "S_1") (pintype "passive"))
      (node (ref "Q3") (pin "2") (pinfunction "S_2") (pintype "passive"))
      (node (ref "Q3") (pin "3") (pinfunction "S_3") (pintype "passive"))
      (node (ref "Q8") (pin "5") (pinfunction "D_5") (pintype "passive"))
      (node (ref "Q8") (pin "6") (pinfunction "D_6") (pintype "passive"))
      (node (ref "Q8") (pin "7") (pinfunction "D_7") (pintype "passive"))
      (node (ref "Q8") (pin "8") (pinfunction "D_8") (pintype "passive"))
      (node (ref "Q9") (pin "5") (pinfunction "D_5") (pintype "passive"))
      (node (ref "Q9") (pin "6") (pinfunction "D_6") (pintype "passive"))
      (node (ref "Q9") (pin "7") (pinfunction "D_7") (pintype "passive"))
      (node (ref "Q9") (pin "8") (pinfunction "D_8") (pintype "passive"))
      (node (ref "U2") (pin "2") (pinfunction "TS_2") (pintype "passive"))
    )
    (net (code "59") (name "/SWN3") (class "Default")
      (node (ref "C9") (pin "2") (pinfunction "2_2") (pintype "passive"))
      (node (ref "L3") (pin "1") (pinfunction "1_1") (pintype "passive"))
      (node (ref "Q1") (pin "1") (pinfunction "S_1") (pintype "passive"))
      (node (ref "Q1") (pin "2") (pinfunction "S_2") (pintype "passive"))
      (node (ref "Q1") (pin "3") (pinfunction "S_3") (pintype "passive"))
      (node (ref "Q4") (pin "5") (pinfunction "D_5") (pintype "passive"))
      (node (ref "Q4") (pin "6") (pinfunction "D_6") (pintype "passive"))
      (node (ref "Q4") (pin "7") (pinfunction "D_7") (pintype "passive"))
      (node (ref "Q4") (pin "8") (pinfunction "D_8") (pintype "passive"))
      (node (ref "Q5") (pin "5") (pinfunction "D_5") (pintype "passive"))
      (node (ref "Q5") (pin "6") (pinfunction "D_6") (pintype "passive"))
      (node (ref "Q5") (pin "7") (pinfunction "D_7") (pintype "passive"))
      (node (ref "Q5") (pin "8") (pinfunction "D_8") (pintype "passive"))
      (node (ref "U3") (pin "2") (pinfunction "TS_2") (pintype "passive"))
    )
    (net (code "60") (name "/TP1011") (class "Default")
      (node (ref "TP5") (pin "1") (pinfunction "1_1") (pintype "passive"))
      (node (ref "U4") (pin "25") (pinfunction "RPT_BUSYN_25") (pintype "passive"))
    )
    (net (code "61") (name "/TP1012") (class "Default")
      (node (ref "TP6") (pin "1") (pinfunction "1_1") (pintype "passive"))
      (node (ref "U5") (pin "25") (pinfunction "RPT_BUSYN_25") (pintype "passive"))
    )
    (net (code "62") (name "/TP1013") (class "Default")
      (node (ref "TP7") (pin "1") (pinfunction "1_1") (pintype "passive"))
      (node (ref "U6") (pin "25") (pinfunction "RPT_BUSYN_25") (pintype "passive"))
    )
    (net (code "63") (name "/TP1014") (class "Default")
      (node (ref "TP8") (pin "1") (pinfunction "1_1") (pintype "passive"))
      (node (ref "U7") (pin "25") (pinfunction "RPT_BUSYN_25") (pintype "passive"))
    )
    (net (code "64") (name "/TP1015") (class "Default")
      (node (ref "TP32") (pin "1") (pinfunction "1_1") (pintype "passive"))
      (node (ref "U9") (pin "25") (pinfunction "RPT_BUSYN_25") (pintype "passive"))
    )
    (net (code "65") (name "/TP1016") (class "Default")
      (node (ref "TP33") (pin "1") (pinfunction "1_1") (pintype "passive"))
      (node (ref "U10") (pin "25") (pinfunction "RPT_BUSYN_25") (pintype "passive"))
    )
    (net (code "66") (name "/TP1017") (class "Default")
      (node (ref "TP34") (pin "1") (pinfunction "1_1") (pintype "passive"))
      (node (ref "U11") (pin "25") (pinfunction "RPT_BUSYN_25") (pintype "passive"))
    )
    (net (code "67") (name "/TP1018") (class "Default")
      (node (ref "TP35") (pin "1") (pinfunction "1_1") (pintype "passive"))
      (node (ref "U12") (pin "25") (pinfunction "RPT_BUSYN_25") (pintype "passive"))
    )
    (net (code "68") (name "/TP1019") (class "Default")
      (node (ref "TP40") (pin "1") (pinfunction "1_1") (pintype "passive"))
      (node (ref "U18") (pin "25") (pinfunction "RPT_BUSYN_25") (pintype "passive"))
    )
    (net (code "69") (name "/TP10110") (class "Default")
      (node (ref "TP41") (pin "1") (pinfunction "1_1") (pintype "passive"))
      (node (ref "U19") (pin "25") (pinfunction "RPT_BUSYN_25") (pintype "passive"))
    )
    (net (code "70") (name "/TP10111") (class "Default")
      (node (ref "TP42") (pin "1") (pinfunction "1_1") (pintype "passive"))
      (node (ref "U20") (pin "25") (pinfunction "RPT_BUSYN_25") (pintype "passive"))
    )
    (net (code "71") (name "/TP10112") (class "Default")
      (node (ref "TP43") (pin "1") (pinfunction "1_1") (pintype "passive"))
      (node (ref "U21") (pin "25") (pinfunction "RPT_BUSYN_25") (pintype "passive"))
    )
    (net (code "72") (name "/TP10113") (class "Default")
      (node (ref "TP49") (pin "1") (pinfunction "1_1") (pintype "passive"))
      (node (ref "U24") (pin "25") (pinfunction "RPT_BUSYN_25") (pintype "passive"))
    )
    (net (code "73") (name "/TP10114") (class "Default")
      (node (ref "TP50") (pin "1") (pinfunction "1_1") (pintype "passive"))
      (node (ref "U25") (pin "25") (pinfunction "RPT_BUSYN_25") (pintype "passive"))
    )
    (net (code "74") (name "/TP10115") (class "Default")
      (node (ref "TP51") (pin "1") (pinfunction "1_1") (pintype "passive"))
      (node (ref "U26") (pin "25") (pinfunction "RPT_BUSYN_25") (pintype "passive"))
    )
    (net (code "75") (name "/TP10116") (class "Default")
      (node (ref "TP52") (pin "1") (pinfunction "1_1") (pintype "passive"))
      (node (ref "U27") (pin "25") (pinfunction "RPT_BUSYN_25") (pintype "passive"))
    )
    (net (code "76") (name "/TP_1001") (class "Default")
      (node (ref "TP1") (pin "1") (pinfunction "1_1") (pintype "passive"))
      (node (ref "U4") (pin "48") (pinfunction "LTC_BUSYN_48") (pintype "passive"))
    )
    (net (code "77") (name "/TP_1002") (class "Default")
      (node (ref "TP2") (pin "1") (pinfunction "1_1") (pintype "passive"))
      (node (ref "U5") (pin "48") (pinfunction "LTC_BUSYN_48") (pintype "passive"))
    )
    (net (code "78") (name "/TP_1003") (class "Default")
      (node (ref "TP3") (pin "1") (pinfunction "1_1") (pintype "passive"))
      (node (ref "U6") (pin "48") (pinfunction "LTC_BUSYN_48") (pintype "passive"))
    )
    (net (code "79") (name "/TP_1004") (class "Default")
      (node (ref "TP4") (pin "1") (pinfunction "1_1") (pintype "passive"))
      (node (ref "U7") (pin "48") (pinfunction "LTC_BUSYN_48") (pintype "passive"))
    )
    (net (code "80") (name "/TP_1005") (class "Default")
      (node (ref "TP13") (pin "1") (pinfunction "1_1") (pintype "passive"))
      (node (ref "U9") (pin "48") (pinfunction "LTC_BUSYN_48") (pintype "passive"))
    )
    (net (code "81") (name "/TP_1006") (class "Default")
      (node (ref "TP14") (pin "1") (pinfunction "1_1") (pintype "passive"))
      (node (ref "U10") (pin "48") (pinfunction "LTC_BUSYN_48") (pintype "passive"))
    )
    (net (code "82") (name "/TP_1007") (class "Default")
      (node (ref "TP15") (pin "1") (pinfunction "1_1") (pintype "passive"))
      (node (ref "U11") (pin "48") (pinfunction "LTC_BUSYN_48") (pintype "passive"))
    )
    (net (code "83") (name "/TP_1008") (class "Default")
      (node (ref "TP16") (pin "1") (pinfunction "1_1") (pintype "passive"))
      (node (ref "U12") (pin "48") (pinfunction "LTC_BUSYN_48") (pintype "passive"))
    )
    (net (code "84") (name "/TP_1009") (class "Default")
      (node (ref "TP36") (pin "1") (pinfunction "1_1") (pintype "passive"))
      (node (ref "U18") (pin "48") (pinfunction "LTC_BUSYN_48") (pintype "passive"))
    )
    (net (code "85") (name "/TP_10010") (class "Default")
      (node (ref "TP37") (pin "1") (pinfunction "1_1") (pintype "passive"))
      (node (ref "U19") (pin "48") (pinfunction "LTC_BUSYN_48") (pintype "passive"))
    )
    (net (code "86") (name "/TP_10011") (class "Default")
      (node (ref "TP38") (pin "1") (pinfunction "1_1") (pintype "passive"))
      (node (ref "U20") (pin "48") (pinfunction "LTC_BUSYN_48") (pintype "passive"))
    )
    (net (code "87") (name "/TP_10012") (class "Default")
      (node (ref "TP39") (pin "1") (pinfunction "1_1") (pintype "passive"))
      (node (ref "U21") (pin "48") (pinfunction "LTC_BUSYN_48") (pintype "passive"))
    )
    (net (code "88") (name "/TP_10013") (class "Default")
      (node (ref "TP44") (pin "1") (pinfunction "1_1") (pintype "passive"))
      (node (ref "U24") (pin "48") (pinfunction "LTC_BUSYN_48") (pintype "passive"))
    )
    (net (code "89") (name "/TP_10014") (class "Default")
      (node (ref "TP45") (pin "1") (pinfunction "1_1") (pintype "passive"))
      (node (ref "U25") (pin "48") (pinfunction "LTC_BUSYN_48") (pintype "passive"))
    )
    (net (code "90") (name "/TP_10015") (class "Default")
      (node (ref "TP46") (pin "1") (pinfunction "1_1") (pintype "passive"))
      (node (ref "U26") (pin "48") (pinfunction "LTC_BUSYN_48") (pintype "passive"))
    )
    (net (code "91") (name "/TP_10016") (class "Default")
      (node (ref "TP47") (pin "1") (pinfunction "1_1") (pintype "passive"))
      (node (ref "U27") (pin "48") (pinfunction "LTC_BUSYN_48") (pintype "passive"))
    )
    (net (code "92") (name "/TX_BTC_0") (class "Default")
      (node (ref "R7") (pin "1") (pinfunction "1_1") (pintype "passive"))
      (node (ref "U10") (pin "24") (pinfunction "RPT_P_24") (pintype "passive"))
      (node (ref "U11") (pin "24") (pinfunction "RPT_P_24") (pintype "passive"))
      (node (ref "U12") (pin "24") (pinfunction "RPT_P_24") (pintype "passive"))
      (node (ref "U4") (pin "24") (pinfunction "RPT_P_24") (pintype "passive"))
      (node (ref "U5") (pin "24") (pinfunction "RPT_P_24") (pintype "passive"))
      (node (ref "U6") (pin "24") (pinfunction "RPT_P_24") (pintype "passive"))
      (node (ref "U7") (pin "24") (pinfunction "RPT_P_24") (pintype "passive"))
      (node (ref "U8") (pin "61") (pinfunction "AN25/PWM1H/PMD1/RPI81/RE1_61") (pintype "passive"))
      (node (ref "U9") (pin "24") (pinfunction "RPT_P_24") (pintype "passive"))
    )
    (net (code "93") (name "/TX_BTC_1") (class "Default")
      (node (ref "R53") (pin "1") (pinfunction "1_1") (pintype "passive"))
      (node (ref "U18") (pin "24") (pinfunction "RPT_P_24") (pintype "passive"))
      (node (ref "U19") (pin "24") (pinfunction "RPT_P_24") (pintype "passive"))
      (node (ref "U20") (pin "24") (pinfunction "RPT_P_24") (pintype "passive"))
      (node (ref "U21") (pin "24") (pinfunction "RPT_P_24") (pintype "passive"))
      (node (ref "U24") (pin "24") (pinfunction "RPT_P_24") (pintype "passive"))
      (node (ref "U25") (pin "24") (pinfunction "RPT_P_24") (pintype "passive"))
      (node (ref "U26") (pin "24") (pinfunction "RPT_P_24") (pintype "passive"))
      (node (ref "U27") (pin "24") (pinfunction "RPT_P_24") (pintype "passive"))
      (node (ref "U8") (pin "1") (pinfunction "AN29/PWM3H/PMD5/RP85/RE5_1") (pintype "passive"))
    )
    (net (code "94") (name "/TX_LTC_0") (class "Default")
      (node (ref "R8") (pin "2") (pinfunction "2_2") (pintype "passive"))
      (node (ref "U10") (pin "23") (pinfunction "RPT_N_23") (pintype "passive"))
      (node (ref "U11") (pin "23") (pinfunction "RPT_N_23") (pintype "passive"))
      (node (ref "U12") (pin "23") (pinfunction "RPT_N_23") (pintype "passive"))
      (node (ref "U4") (pin "23") (pinfunction "RPT_N_23") (pintype "passive"))
      (node (ref "U5") (pin "23") (pinfunction "RPT_N_23") (pintype "passive"))
      (node (ref "U6") (pin "23") (pinfunction "RPT_N_23") (pintype "passive"))
      (node (ref "U7") (pin "23") (pinfunction "RPT_N_23") (pintype "passive"))
      (node (ref "U8") (pin "60") (pinfunction "AN24/PWM1L/PMD0/RP80/RE0_60") (pintype "passive"))
      (node (ref "U9") (pin "23") (pinfunction "RPT_N_23") (pintype "passive"))
    )
    (net (code "95") (name "/TX_LTC_1") (class "Default")
      (node (ref "R54") (pin "2") (pinfunction "2_2") (pintype "passive"))
      (node (ref "U18") (pin "23") (pinfunction "RPT_N_23") (pintype "passive"))
      (node (ref "U19") (pin "23") (pinfunction "RPT_N_23") (pintype "passive"))
      (node (ref "U20") (pin "23") (pinfunction "RPT_N_23") (pintype "passive"))
      (node (ref "U21") (pin "23") (pinfunction "RPT_N_23") (pintype "passive"))
      (node (ref "U24") (pin "23") (pinfunction "RPT_N_23") (pintype "passive"))
      (node (ref "U25") (pin "23") (pinfunction "RPT_N_23") (pintype "passive"))
      (node (ref "U26") (pin "23") (pinfunction "RPT_N_23") (pintype "passive"))
      (node (ref "U27") (pin "23") (pinfunction "RPT_N_23") (pintype "passive"))
      (node (ref "U8") (pin "2") (pinfunction "AN30/PWM4L/PMD6/RPI86/RE6_2") (pintype "passive"))
    )
    (net (code "96") (name "/USB5.0V") (class "Default")
      (node (ref "D9") (pin "4") (pinfunction "4_4") (pintype "passive"))
      (node (ref "D9") (pin "6") (pinfunction "6_6") (pintype "passive"))
      (node (ref "J2") (pin "1") (pinfunction "1_1") (pintype "passive"))
      (node (ref "R32") (pin "1") (pinfunction "1_1") (pintype "passive"))
      (node (ref "R33") (pin "2") (pinfunction "2_2") (pintype "passive"))
    )
    (net (code "97") (name "/VCAP") (class "Default")
      (node (ref "C139") (pin "1") (pinfunction "1_1") (pintype "passive"))
      (node (ref "U8") (pin "56") (pinfunction "VCAP_56") (pintype "passive"))
    )
    (net (code "98") (name "/VDD_PLL") (class "Default")
      (node (ref "C261") (pin "1") (pinfunction "1_1") (pintype "passive"))
      (node (ref "FB1") (pin "2") (pinfunction "2_2") (pintype "passive"))
      (node (ref "U10") (pin "8") (pinfunction "VDDA_PLL_8") (pintype "passive"))
      (node (ref "U10") (pin "9") (pinfunction "VDD_PLL_9") (pintype "passive"))
      (node (ref "U11") (pin "8") (pinfunction "VDDA_PLL_8") (pintype "passive"))
      (node (ref "U11") (pin "9") (pinfunction "VDD_PLL_9") (pintype "passive"))
      (node (ref "U12") (pin "8") (pinfunction "VDDA_PLL_8") (pintype "passive"))
      (node (ref "U12") (pin "9") (pinfunction "VDD_PLL_9") (pintype "passive"))
      (node (ref "U18") (pin "8") (pinfunction "VDDA_PLL_8") (pintype "passive"))
      (node (ref "U18") (pin "9") (pinfunction "VDD_PLL_9") (pintype "passive"))
      (node (ref "U19") (pin "8") (pinfunction "VDDA_PLL_8") (pintype "passive"))
      (node (ref "U19") (pin "9") (pinfunction "VDD_PLL_9") (pintype "passive"))
      (node (ref "U20") (pin "8") (pinfunction "VDDA_PLL_8") (pintype "passive"))
      (node (ref "U20") (pin "9") (pinfunction "VDD_PLL_9") (pintype "passive"))
      (node (ref "U21") (pin "8") (pinfunction "VDDA_PLL_8") (pintype "passive"))
      (node (ref "U21") (pin "9") (pinfunction "VDD_PLL_9") (pintype "passive"))
      (node (ref "U24") (pin "8") (pinfunction "VDDA_PLL_8") (pintype "passive"))
      (node (ref "U24") (pin "9") (pinfunction "VDD_PLL_9") (pintype "passive"))
      (node (ref "U25") (pin "8") (pinfunction "VDDA_PLL_8") (pintype "passive"))
      (node (ref "U25") (pin "9") (pinfunction "VDD_PLL_9") (pintype "passive"))
      (node (ref "U26") (pin "8") (pinfunction "VDDA_PLL_8") (pintype "passive"))
      (node (ref "U26") (pin "9") (pinfunction "VDD_PLL_9") (pintype "passive"))
      (node (ref "U27") (pin "8") (pinfunction "VDDA_PLL_8") (pintype "passive"))
      (node (ref "U27") (pin "9") (pinfunction "VDD_PLL_9") (pintype "passive"))
      (node (ref "U4") (pin "8") (pinfunction "VDDA_PLL_8") (pintype "passive"))
      (node (ref "U4") (pin "9") (pinfunction "VDD_PLL_9") (pintype "passive"))
      (node (ref "U5") (pin "8") (pinfunction "VDDA_PLL_8") (pintype "passive"))
      (node (ref "U5") (pin "9") (pinfunction "VDD_PLL_9") (pintype "passive"))
      (node (ref "U6") (pin "8") (pinfunction "VDDA_PLL_8") (pintype "passive"))
      (node (ref "U6") (pin "9") (pinfunction "VDD_PLL_9") (pintype "passive"))
      (node (ref "U7") (pin "8") (pinfunction "VDDA_PLL_8") (pintype "passive"))
      (node (ref "U7") (pin "9") (pinfunction "VDD_PLL_9") (pintype "passive"))
      (node (ref "U9") (pin "8") (pinfunction "VDDA_PLL_8") (pintype "passive"))
      (node (ref "U9") (pin "9") (pinfunction "VDD_PLL_9") (pintype "passive"))
    )
    (net (code "99") (name "/XCLK1") (class "Default")
      (node (ref "R27") (pin "2") (pinfunction "2_2") (pintype "passive"))
      (node (ref "U8") (pin "46") (pinfunction "INT0/DMH/RP64/RD0_46") (pintype "passive"))
      (node (ref "U8") (pin "49") (pinfunction "VCPCON/RP65/RD1_49") (pintype "passive"))
      (node (ref "U8") (pin "52") (pinfunction "PMWR/RP68/RD4_52") (pintype "passive"))
      (node (ref "U8") (pin "53") (pinfunction "PMRD/RP69/RD5_53") (pintype "passive"))
    )
    (net (code "100") (name "/XCLKIN") (class "Default")
      (node (ref "R27") (pin "1") (pinfunction "1_1") (pintype "passive"))
      (node (ref "R30") (pin "1") (pinfunction "1_1") (pintype "passive"))
      (node (ref "U4") (pin "11") (pinfunction "XCLKIN_11") (pintype "passive"))
    )
    (net (code "101") (name "/XCLKOUT_1") (class "Default")
      (node (ref "U4") (pin "12") (pinfunction "XCLKOUT_12") (pintype "passive"))
      (node (ref "U5") (pin "11") (pinfunction "XCLKIN_11") (pintype "passive"))
    )
    (net (code "102") (name "/XCLKOUT_2") (class "Default")
      (node (ref "U5") (pin "12") (pinfunction "XCLKOUT_12") (pintype "passive"))
      (node (ref "U6") (pin "11") (pinfunction "XCLKIN_11") (pintype "passive"))
    )
    (net (code "103") (name "/XCLKOUT_3") (class "Default")
      (node (ref "U6") (pin "12") (pinfunction "XCLKOUT_12") (pintype "passive"))
      (node (ref "U7") (pin "11") (pinfunction "XCLKIN_11") (pintype "passive"))
    )
    (net (code "104") (name "/XCLKOUT_4") (class "Default")
      (node (ref "U7") (pin "12") (pinfunction "XCLKOUT_12") (pintype "passive"))
      (node (ref "U9") (pin "11") (pinfunction "XCLKIN_11") (pintype "passive"))
    )
    (net (code "105") (name "/XCLKOUT_5") (class "Default")
      (node (ref "U10") (pin "11") (pinfunction "XCLKIN_11") (pintype "passive"))
      (node (ref "U9") (pin "12") (pinfunction "XCLKOUT_12") (pintype "passive"))
    )
    (net (code "106") (name "/XCLKOUT_6") (class "Default")
      (node (ref "U10") (pin "12") (pinfunction "XCLKOUT_12") (pintype "passive"))
      (node (ref "U11") (pin "11") (pinfunction "XCLKIN_11") (pintype "passive"))
    )
    (net (code "107") (name "/XCLKOUT_7") (class "Default")
      (node (ref "U11") (pin "12") (pinfunction "XCLKOUT_12") (pintype "passive"))
      (node (ref "U12") (pin "11") (pinfunction "XCLKIN_11") (pintype "passive"))
    )
    (net (code "108") (name "/XCLKOUT_8") (class "Default")
      (node (ref "U12") (pin "12") (pinfunction "XCLKOUT_12") (pintype "passive"))
      (node (ref "U18") (pin "11") (pinfunction "XCLKIN_11") (pintype "passive"))
    )
    (net (code "109") (name "/XCLKOUT_9") (class "Default")
      (node (ref "U18") (pin "12") (pinfunction "XCLKOUT_12") (pintype "passive"))
      (node (ref "U19") (pin "11") (pinfunction "XCLKIN_11") (pintype "passive"))
    )
    (net (code "110") (name "/XCLKOUT_10") (class "Default")
      (node (ref "U19") (pin "12") (pinfunction "XCLKOUT_12") (pintype "passive"))
      (node (ref "U20") (pin "11") (pinfunction "XCLKIN_11") (pintype "passive"))
    )
    (net (code "111") (name "/XCLKOUT_11") (class "Default")
      (node (ref "U20") (pin "12") (pinfunction "XCLKOUT_12") (pintype "passive"))
      (node (ref "U21") (pin "11") (pinfunction "XCLKIN_11") (pintype "passive"))
    )
    (net (code "112") (name "/XCLKOUT_12") (class "Default")
      (node (ref "U21") (pin "12") (pinfunction "XCLKOUT_12") (pintype "passive"))
      (node (ref "U24") (pin "11") (pinfunction "XCLKIN_11") (pintype "passive"))
    )
    (net (code "113") (name "/XCLKOUT_13") (class "Default")
      (node (ref "U24") (pin "12") (pinfunction "XCLKOUT_12") (pintype "passive"))
      (node (ref "U25") (pin "11") (pinfunction "XCLKIN_11") (pintype "passive"))
    )
    (net (code "114") (name "/XCLKOUT_14") (class "Default")
      (node (ref "U25") (pin "12") (pinfunction "XCLKOUT_12") (pintype "passive"))
      (node (ref "U26") (pin "11") (pinfunction "XCLKIN_11") (pintype "passive"))
    )
    (net (code "115") (name "/XCLKOUT_15") (class "Default")
      (node (ref "U26") (pin "12") (pinfunction "XCLKOUT_12") (pintype "passive"))
      (node (ref "U27") (pin "11") (pinfunction "XCLKIN_11") (pintype "passive"))
    )
    (net (code "116") (name "/XCLKOUT_16") (class "Default")
      (node (ref "TP48") (pin "1") (pinfunction "1_1") (pintype "passive"))
      (node (ref "U27") (pin "12") (pinfunction "XCLKOUT_12") (pintype "passive"))
    )
    (net (code "117") (name "/YELLOW") (class "Default")
      (node (ref "D6") (pin "2") (pinfunction "A_2") (pintype "passive"))
      (node (ref "U8") (pin "44") (pinfunction "ASCL1/PMCS2/RPI74/RD10_44") (pintype "passive"))
    )
    (net (code "118") (name "GND") (class "Default")
      (node (ref "C1") (pin "1") (pinfunction "1_1") (pintype "passive"))
      (node (ref "C10") (pin "1") (pinfunction "1_1") (pintype "passive"))
      (node (ref "C11") (pin "1") (pinfunction "1_1") (pintype "passive"))
      (node (ref "C118") (pin "1") (pinfunction "1_1") (pintype "passive"))
      (node (ref "C119") (pin "1") (pinfunction "1_1") (pintype "passive"))
      (node (ref "C12") (pin "1") (pinfunction "1_1") (pintype "passive"))
      (node (ref "C120") (pin "1") (pinfunction "1_1") (pintype "passive"))
      (node (ref "C121") (pin "1") (pinfunction "1_1") (pintype "passive"))
      (node (ref "C122") (pin "1") (pinfunction "1_1") (pintype "passive"))
      (node (ref "C123") (pin "1") (pinfunction "1_1") (pintype "passive"))
      (node (ref "C124") (pin "1") (pinfunction "1_1") (pintype "passive"))
      (node (ref "C125") (pin "1") (pinfunction "1_1") (pintype "passive"))
      (node (ref "C126") (pin "1") (pinfunction "1_1") (pintype "passive"))
      (node (ref "C127") (pin "1") (pinfunction "1_1") (pintype "passive"))
      (node (ref "C128") (pin "1") (pinfunction "1_1") (pintype "passive"))
      (node (ref "C129") (pin "1") (pinfunction "1_1") (pintype "passive"))
      (node (ref "C13") (pin "1") (pinfunction "1_1") (pintype "passive"))
      (node (ref "C130") (pin "1") (pinfunction "1_1") (pintype "passive"))
      (node (ref "C131") (pin "1") (pinfunction "1_1") (pintype "passive"))
      (node (ref "C132") (pin "1") (pinfunction "1_1") (pintype "passive"))
      (node (ref "C133") (pin "1") (pinfunction "1_1") (pintype "passive"))
      (node (ref "C134") (pin "1") (pinfunction "1_1") (pintype "passive"))
      (node (ref "C135") (pin "1") (pinfunction "1_1") (pintype "passive"))
      (node (ref "C136") (pin "1") (pinfunction "1_1") (pintype "passive"))
      (node (ref "C137") (pin "1") (pinfunction "1_1") (pintype "passive"))
      (node (ref "C138") (pin "2") (pinfunction "2_2") (pintype "passive"))
      (node (ref "C139") (pin "2") (pinfunction "2_2") (pintype "passive"))
      (node (ref "C14") (pin "1") (pinfunction "1_1") (pintype "passive"))
      (node (ref "C140") (pin "1") (pinfunction "1_1") (pintype "passive"))
      (node (ref "C141") (pin "1") (pinfunction "1_1") (pintype "passive"))
      (node (ref "C142") (pin "1") (pinfunction "1_1") (pintype "passive"))
      (node (ref "C143") (pin "1") (pinfunction "1_1") (pintype "passive"))
      (node (ref "C144") (pin "1") (pinfunction "1_1") (pintype "passive"))
      (node (ref "C145") (pin "1") (pinfunction "1_1") (pintype "passive"))
      (node (ref "C146") (pin "1") (pinfunction "1_1") (pintype "passive"))
      (node (ref "C147") (pin "1") (pinfunction "1_1") (pintype "passive"))
      (node (ref "C148") (pin "1") (pinfunction "1_1") (pintype "passive"))
      (node (ref "C149") (pin "1") (pinfunction "1_1") (pintype "passive"))
      (node (ref "C15") (pin "1") (pinfunction "1_1") (pintype "passive"))
      (node (ref "C150") (pin "1") (pinfunction "1_1") (pintype "passive"))
      (node (ref "C151") (pin "1") (pinfunction "1_1") (pintype "passive"))
      (node (ref "C152") (pin "1") (pinfunction "1_1") (pintype "passive"))
      (node (ref "C153") (pin "1") (pinfunction "1_1") (pintype "passive"))
      (node (ref "C154") (pin "1") (pinfunction "1_1") (pintype "passive"))
      (node (ref "C155") (pin "1") (pinfunction "1_1") (pintype "passive"))
      (node (ref "C156") (pin "1") (pinfunction "1_1") (pintype "passive"))
      (node (ref "C157") (pin "1") (pinfunction "1_1") (pintype "passive"))
      (node (ref "C158") (pin "1") (pinfunction "1_1") (pintype "passive"))
      (node (ref "C159") (pin "1") (pinfunction "1_1") (pintype "passive"))
      (node (ref "C16") (pin "1") (pinfunction "1_1") (pintype "passive"))
      (node (ref "C160") (pin "1") (pinfunction "1_1") (pintype "passive"))
      (node (ref "C161") (pin "1") (pinfunction "1_1") (pintype "passive"))
      (node (ref "C162") (pin "1") (pinfunction "1_1") (pintype "passive"))
      (node (ref "C163") (pin "1") (pinfunction "1_1") (pintype "passive"))
      (node (ref "C166") (pin "2") (pinfunction "2_2") (pintype "passive"))
      (node (ref "C167") (pin "2") (pinfunction "2_2") (pintype "passive"))
      (node (ref "C168") (pin "2") (pinfunction "2_2") (pintype "passive"))
      (node (ref "C169") (pin "2") (pinfunction "2_2") (pintype "passive"))
      (node (ref "C17") (pin "1") (pinfunction "1_1") (pintype "passive"))
      (node (ref "C170") (pin "2") (pinfunction "2_2") (pintype "passive"))
      (node (ref "C171") (pin "2") (pinfunction "2_2") (pintype "passive"))
      (node (ref "C172") (pin "2") (pinfunction "2_2") (pintype "passive"))
      (node (ref "C173") (pin "2") (pinfunction "2_2") (pintype "passive"))
      (node (ref "C174") (pin "2") (pinfunction "2_2") (pintype "passive"))
      (node (ref "C175") (pin "1") (pinfunction "1_1") (pintype "passive"))
      (node (ref "C176") (pin "1") (pinfunction "1_1") (pintype "passive"))
      (node (ref "C177") (pin "1") (pinfunction "1_1") (pintype "passive"))
      (node (ref "C178") (pin "1") (pinfunction "1_1") (pintype "passive"))
      (node (ref "C179") (pin "1") (pinfunction "1_1") (pintype "passive"))
      (node (ref "C18") (pin "1") (pinfunction "1_1") (pintype "passive"))
      (node (ref "C180") (pin "1") (pinfunction "1_1") (pintype "passive"))
      (node (ref "C181") (pin "1") (pinfunction "1_1") (pintype "passive"))
      (node (ref "C182") (pin "1") (pinfunction "1_1") (pintype "passive"))
      (node (ref "C183") (pin "1") (pinfunction "1_1") (pintype "passive"))
      (node (ref "C184") (pin "1") (pinfunction "1_1") (pintype "passive"))
      (node (ref "C185") (pin "1") (pinfunction "1_1") (pintype "passive"))
      (node (ref "C186") (pin "1") (pinfunction "1_1") (pintype "passive"))
      (node (ref "C187") (pin "1") (pinfunction "1_1") (pintype "passive"))
      (node (ref "C188") (pin "1") (pinfunction "1_1") (pintype "passive"))
      (node (ref "C189") (pin "1") (pinfunction "1_1") (pintype "passive"))
      (node (ref "C19") (pin "1") (pinfunction "1_1") (pintype "passive"))
      (node (ref "C190") (pin "1") (pinfunction "1_1") (pintype "passive"))
      (node (ref "C191") (pin "2") (pinfunction "2_2") (pintype "passive"))
      (node (ref "C2") (pin "1") (pinfunction "1_1") (pintype "passive"))
      (node (ref "C20") (pin "2") (pinfunction "2_2") (pintype "passive"))
      (node (ref "C21") (pin "2") (pinfunction "2_2") (pintype "passive"))
      (node (ref "C22") (pin "1") (pinfunction "1_1") (pintype "passive"))
      (node (ref "C224") (pin "1") (pinfunction "1_1") (pintype "passive"))
      (node (ref "C225") (pin "2") (pinfunction "2_2") (pintype "passive"))
      (node (ref "C226") (pin "2") (pinfunction "2_2") (pintype "passive"))
      (node (ref "C227") (pin "1") (pinfunction "1_1") (pintype "passive"))
      (node (ref "C228") (pin "1") (pinfunction "1_1") (pintype "passive"))
      (node (ref "C229") (pin "1") (pinfunction "1_1") (pintype "passive"))
      (node (ref "C23") (pin "1") (pinfunction "1_1") (pintype "passive"))
      (node (ref "C230") (pin "1") (pinfunction "1_1") (pintype "passive"))
      (node (ref "C231") (pin "1") (pinfunction "1_1") (pintype "passive"))
      (node (ref "C232") (pin "1") (pinfunction "1_1") (pintype "passive"))
      (node (ref "C233") (pin "1") (pinfunction "1_1") (pintype "passive"))
      (node (ref "C234") (pin "1") (pinfunction "1_1") (pintype "passive"))
      (node (ref "C235") (pin "1") (pinfunction "1_1") (pintype "passive"))
      (node (ref "C236") (pin "1") (pinfunction "1_1") (pintype "passive"))
      (node (ref "C237") (pin "1") (pinfunction "1_1") (pintype "passive"))
      (node (ref "C238") (pin "1") (pinfunction "1_1") (pintype "passive"))
      (node (ref "C239") (pin "1") (pinfunction "1_1") (pintype "passive"))
      (node (ref "C24") (pin "1") (pinfunction "1_1") (pintype "passive"))
      (node (ref "C240") (pin "1") (pinfunction "1_1") (pintype "passive"))
      (node (ref "C241") (pin "1") (pinfunction "1_1") (pintype "passive"))
      (node (ref "C242") (pin "1") (pinfunction "1_1") (pintype "passive"))
      (node (ref "C243") (pin "1") (pinfunction "1_1") (pintype "passive"))
      (node (ref "C244") (pin "1") (pinfunction "1_1") (pintype "passive"))
      (node (ref "C245") (pin "1") (pinfunction "1_1") (pintype "passive"))
      (node (ref "C246") (pin "1") (pinfunction "1_1") (pintype "passive"))
      (node (ref "C247") (pin "1") (pinfunction "1_1") (pintype "passive"))
      (node (ref "C248") (pin "1") (pinfunction "1_1") (pintype "passive"))
      (node (ref "C249") (pin "1") (pinfunction "1_1") (pintype "passive"))
      (node (ref "C25") (pin "1") (pinfunction "1_1") (pintype "passive"))
      (node (ref "C250") (pin "1") (pinfunction "1_1") (pintype "passive"))
      (node (ref "C251") (pin "1") (pinfunction "1_1") (pintype "passive"))
      (node (ref "C252") (pin "1") (pinfunction "1_1") (pintype "passive"))
      (node (ref "C253") (pin "1") (pinfunction "1_1") (pintype "passive"))
      (node (ref "C254") (pin "1") (pinfunction "1_1") (pintype "passive"))
      (node (ref "C255") (pin "1") (pinfunction "1_1") (pintype "passive"))
      (node (ref "C256") (pin "1") (pinfunction "1_1") (pintype "passive"))
      (node (ref "C257") (pin "1") (pinfunction "1_1") (pintype "passive"))
      (node (ref "C258") (pin "1") (pinfunction "1_1") (pintype "passive"))
      (node (ref "C259") (pin "2") (pinfunction "2_2") (pintype "passive"))
      (node (ref "C26") (pin "1") (pinfunction "1_1") (pintype "passive"))
      (node (ref "C260") (pin "2") (pinfunction "2_2") (pintype "passive"))
      (node (ref "C261") (pin "2") (pinfunction "2_2") (pintype "passive"))
      (node (ref "C262") (pin "1") (pinfunction "1_1") (pintype "passive"))
      (node (ref "C263") (pin "1") (pinfunction "1_1") (pintype "passive"))
      (node (ref "C264") (pin "1") (pinfunction "1_1") (pintype "passive"))
      (node (ref "C265") (pin "1") (pinfunction "1_1") (pintype "passive"))
      (node (ref "C266") (pin "1") (pinfunction "1_1") (pintype "passive"))
      (node (ref "C267") (pin "1") (pinfunction "1_1") (pintype "passive"))
      (node (ref "C268") (pin "1") (pinfunction "1_1") (pintype "passive"))
      (node (ref "C269") (pin "1") (pinfunction "1_1") (pintype "passive"))
      (node (ref "C27") (pin "1") (pinfunction "1_1") (pintype "passive"))
      (node (ref "C270") (pin "1") (pinfunction "1_1") (pintype "passive"))
      (node (ref "C271") (pin "1") (pinfunction "1_1") (pintype "passive"))
      (node (ref "C272") (pin "1") (pinfunction "1_1") (pintype "passive"))
      (node (ref "C273") (pin "1") (pinfunction "1_1") (pintype "passive"))
      (node (ref "C274") (pin "2") (pinfunction "2_2") (pintype "passive"))
      (node (ref "C275") (pin "2") (pinfunction "2_2") (pintype "passive"))
      (node (ref "C276") (pin "1") (pinfunction "1_1") (pintype "passive"))
      (node (ref "C277") (pin "1") (pinfunction "1_1") (pintype "passive"))
      (node (ref "C278") (pin "1") (pinfunction "1_1") (pintype "passive"))
      (node (ref "C279") (pin "1") (pinfunction "1_1") (pintype "passive"))
      (node (ref "C28") (pin "1") (pinfunction "1_1") (pintype "passive"))
      (node (ref "C280") (pin "1") (pinfunction "1_1") (pintype "passive"))
      (node (ref "C281") (pin "1") (pinfunction "1_1") (pintype "passive"))
      (node (ref "C282") (pin "1") (pinfunction "1_1") (pintype "passive"))
      (node (ref "C283") (pin "1") (pinfunction "1_1") (pintype "passive"))
      (node (ref "C284") (pin "1") (pinfunction "1_1") (pintype "passive"))
      (node (ref "C285") (pin "1") (pinfunction "1_1") (pintype "passive"))
      (node (ref "C286") (pin "1") (pinfunction "1_1") (pintype "passive"))
      (node (ref "C287") (pin "1") (pinfunction "1_1") (pintype "passive"))
      (node (ref "C288") (pin "1") (pinfunction "1_1") (pintype "passive"))
      (node (ref "C289") (pin "1") (pinfunction "1_1") (pintype "passive"))
      (node (ref "C29") (pin "1") (pinfunction "1_1") (pintype "passive"))
      (node (ref "C290") (pin "1") (pinfunction "1_1") (pintype "passive"))
      (node (ref "C291") (pin "1") (pinfunction "1_1") (pintype "passive"))
      (node (ref "C3") (pin "1") (pinfunction "1_1") (pintype "passive"))
      (node (ref "C30") (pin "1") (pinfunction "1_1") (pintype "passive"))
      (node (ref "C31") (pin "1") (pinfunction "1_1") (pintype "passive"))
      (node (ref "C32") (pin "1") (pinfunction "1_1") (pintype "passive"))
      (node (ref "C324") (pin "1") (pinfunction "1_1") (pintype "passive"))
      (node (ref "C325") (pin "1") (pinfunction "1_1") (pintype "passive"))
      (node (ref "C326") (pin "1") (pinfunction "1_1") (pintype "passive"))
      (node (ref "C327") (pin "1") (pinfunction "1_1") (pintype "passive"))
      (node (ref "C328") (pin "1") (pinfunction "1_1") (pintype "passive"))
      (node (ref "C329") (pin "1") (pinfunction "1_1") (pintype "passive"))
      (node (ref "C33") (pin "1") (pinfunction "1_1") (pintype "passive"))
      (node (ref "C330") (pin "1") (pinfunction "1_1") (pintype "passive"))
      (node (ref "C331") (pin "1") (pinfunction "1_1") (pintype "passive"))
      (node (ref "C332") (pin "1") (pinfunction "1_1") (pintype "passive"))
      (node (ref "C333") (pin "1") (pinfunction "1_1") (pintype "passive"))
      (node (ref "C334") (pin "1") (pinfunction "1_1") (pintype "passive"))
      (node (ref "C335") (pin "1") (pinfunction "1_1") (pintype "passive"))
      (node (ref "C336") (pin "1") (pinfunction "1_1") (pintype "passive"))
      (node (ref "C337") (pin "1") (pinfunction "1_1") (pintype "passive"))
      (node (ref "C338") (pin "1") (pinfunction "1_1") (pintype "passive"))
      (node (ref "C339") (pin "1") (pinfunction "1_1") (pintype "passive"))
      (node (ref "C34") (pin "1") (pinfunction "1_1") (pintype "passive"))
      (node (ref "C340") (pin "1") (pinfunction "1_1") (pintype "passive"))
      (node (ref "C341") (pin "1") (pinfunction "1_1") (pintype "passive"))
      (node (ref "C342") (pin "1") (pinfunction "1_1") (pintype "passive"))
      (node (ref "C343") (pin "1") (pinfunction "1_1") (pintype "passive"))
      (node (ref "C344") (pin "1") (pinfunction "1_1") (pintype "passive"))
      (node (ref "C345") (pin "1") (pinfunction "1_1") (pintype "passive"))
      (node (ref "C346") (pin "1") (pinfunction "1_1") (pintype "passive"))
      (node (ref "C347") (pin "1") (pinfunction "1_1") (pintype "passive"))
      (node (ref "C348") (pin "1") (pinfunction "1_1") (pintype "passive"))
      (node (ref "C349") (pin "1") (pinfunction "1_1") (pintype "passive"))
      (node (ref "C35") (pin "1") (pinfunction "1_1") (pintype "passive"))
      (node (ref "C350") (pin "1") (pinfunction "1_1") (pintype "passive"))
      (node (ref "C351") (pin "1") (pinfunction "1_1") (pintype "passive"))
      (node (ref "C352") (pin "1") (pinfunction "1_1") (pintype "passive"))
      (node (ref "C353") (pin "1") (pinfunction "1_1") (pintype "passive"))
      (node (ref "C354") (pin "1") (pinfunction "1_1") (pintype "passive"))
      (node (ref "C355") (pin "1") (pinfunction "1_1") (pintype "passive"))
      (node (ref "C356") (pin "1") (pinfunction "1_1") (pintype "passive"))
      (node (ref "C357") (pin "1") (pinfunction "1_1") (pintype "passive"))
      (node (ref "C358") (pin "1") (pinfunction "1_1") (pintype "passive"))
      (node (ref "C359") (pin "1") (pinfunction "1_1") (pintype "passive"))
      (node (ref "C36") (pin "1") (pinfunction "1_1") (pintype "passive"))
      (node (ref "C360") (pin "1") (pinfunction "1_1") (pintype "passive"))
      (node (ref "C361") (pin "1") (pinfunction "1_1") (pintype "passive"))
      (node (ref "C362") (pin "1") (pinfunction "1_1") (pintype "passive"))
      (node (ref "C363") (pin "1") (pinfunction "1_1") (pintype "passive"))
      (node (ref "C364") (pin "1") (pinfunction "1_1") (pintype "passive"))
      (node (ref "C365") (pin "1") (pinfunction "1_1") (pintype "passive"))
      (node (ref "C366") (pin "1") (pinfunction "1_1") (pintype "passive"))
      (node (ref "C367") (pin "1") (pinfunction "1_1") (pintype "passive"))
      (node (ref "C368") (pin "1") (pinfunction "1_1") (pintype "passive"))
      (node (ref "C369") (pin "1") (pinfunction "1_1") (pintype "passive"))
      (node (ref "C37") (pin "1") (pinfunction "1_1") (pintype "passive"))
      (node (ref "C370") (pin "1") (pinfunction "1_1") (pintype "passive"))
      (node (ref "C371") (pin "1") (pinfunction "1_1") (pintype "passive"))
      (node (ref "C372") (pin "1") (pinfunction "1_1") (pintype "passive"))
      (node (ref "C373") (pin "1") (pinfunction "1_1") (pintype "passive"))
      (node (ref "C374") (pin "1") (pinfunction "1_1") (pintype "passive"))
      (node (ref "C375") (pin "1") (pinfunction "1_1") (pintype "passive"))
      (node (ref "C376") (pin "1") (pinfunction "1_1") (pintype "passive"))
      (node (ref "C377") (pin "1") (pinfunction "1_1") (pintype "passive"))
      (node (ref "C378") (pin "1") (pinfunction "1_1") (pintype "passive"))
      (node (ref "C379") (pin "1") (pinfunction "1_1") (pintype "passive"))
      (node (ref "C38") (pin "1") (pinfunction "1_1") (pintype "passive"))
      (node (ref "C380") (pin "1") (pinfunction "1_1") (pintype "passive"))
      (node (ref "C381") (pin "1") (pinfunction "1_1") (pintype "passive"))
      (node (ref "C382") (pin "1") (pinfunction "1_1") (pintype "passive"))
      (node (ref "C383") (pin "1") (pinfunction "1_1") (pintype "passive"))
      (node (ref "C39") (pin "1") (pinfunction "1_1") (pintype "passive"))
      (node (ref "C4") (pin "2") (pinfunction "2_2") (pintype "passive"))
      (node (ref "C40") (pin "1") (pinfunction "1_1") (pintype "passive"))
      (node (ref "C41") (pin "1") (pinfunction "1_1") (pintype "passive"))
      (node (ref "C42") (pin "1") (pinfunction "1_1") (pintype "passive"))
      (node (ref "C43") (pin "1") (pinfunction "1_1") (pintype "passive"))
      (node (ref "C44") (pin "1") (pinfunction "1_1") (pintype "passive"))
      (node (ref "C45") (pin "1") (pinfunction "1_1") (pintype "passive"))
      (node (ref "C46") (pin "1") (pinfunction "1_1") (pintype "passive"))
      (node (ref "C47") (pin "1") (pinfunction "1_1") (pintype "passive"))
      (node (ref "C48") (pin "1") (pinfunction "1_1") (pintype "passive"))
      (node (ref "C49") (pin "1") (pinfunction "1_1") (pintype "passive"))
      (node (ref "C5") (pin "2") (pinfunction "2_2") (pintype "passive"))
      (node (ref "C50") (pin "1") (pinfunction "1_1") (pintype "passive"))
      (node (ref "C51") (pin "1") (pinfunction "1_1") (pintype "passive"))
      (node (ref "C52") (pin "1") (pinfunction "1_1") (pintype "passive"))
      (node (ref "C53") (pin "1") (pinfunction "1_1") (pintype "passive"))
      (node (ref "C54") (pin "1") (pinfunction "1_1") (pintype "passive"))
      (node (ref "C55") (pin "1") (pinfunction "1_1") (pintype "passive"))
      (node (ref "C56") (pin "1") (pinfunction "1_1") (pintype "passive"))
      (node (ref "C57") (pin "1") (pinfunction "1_1") (pintype "passive"))
      (node (ref "C58") (pin "1") (pinfunction "1_1") (pintype "passive"))
      (node (ref "C59") (pin "1") (pinfunction "1_1") (pintype "passive"))
      (node (ref "C6") (pin "2") (pinfunction "2_2") (pintype "passive"))
      (node (ref "C60") (pin "1") (pinfunction "1_1") (pintype "passive"))
      (node (ref "C61") (pin "1") (pinfunction "1_1") (pintype "passive"))
      (node (ref "C62") (pin "1") (pinfunction "1_1") (pintype "passive"))
      (node (ref "C63") (pin "1") (pinfunction "1_1") (pintype "passive"))
      (node (ref "C64") (pin "1") (pinfunction "1_1") (pintype "passive"))
      (node (ref "C65") (pin "1") (pinfunction "1_1") (pintype "passive"))
      (node (ref "C66") (pin "1") (pinfunction "1_1") (pintype "passive"))
      (node (ref "C67") (pin "1") (pinfunction "1_1") (pintype "passive"))
      (node (ref "C68") (pin "1") (pinfunction "1_1") (pintype "passive"))
      (node (ref "C69") (pin "2") (pinfunction "2_2") (pintype "passive"))
      (node (ref "C70") (pin "1") (pinfunction "1_1") (pintype "passive"))
      (node (ref "C71") (pin "1") (pinfunction "1_1") (pintype "passive"))
      (node (ref "C72") (pin "1") (pinfunction "1_1") (pintype "passive"))
      (node (ref "C73") (pin "1") (pinfunction "1_1") (pintype "passive"))
      (node (ref "C74") (pin "1") (pinfunction "1_1") (pintype "passive"))
      (node (ref "C75") (pin "1") (pinfunction "1_1") (pintype "passive"))
      (node (ref "C76") (pin "1") (pinfunction "1_1") (pintype "passive"))
      (node (ref "C77") (pin "1") (pinfunction "1_1") (pintype "passive"))
      (node (ref "C78") (pin "1") (pinfunction "1_1") (pintype "passive"))
      (node (ref "C79") (pin "1") (pinfunction "1_1") (pintype "passive"))
      (node (ref "C80") (pin "1") (pinfunction "1_1") (pintype "passive"))
      (node (ref "C81") (pin "1") (pinfunction "1_1") (pintype "passive"))
      (node (ref "C82") (pin "1") (pinfunction "1_1") (pintype "passive"))
      (node (ref "C83") (pin "1") (pinfunction "1_1") (pintype "passive"))
      (node (ref "C84") (pin "1") (pinfunction "1_1") (pintype "passive"))
      (node (ref "C85") (pin "1") (pinfunction "1_1") (pintype "passive"))
      (node (ref "C_1") (pin "2") (pinfunction "2_2") (pintype "passive"))
      (node (ref "C_10") (pin "2") (pinfunction "2_2") (pintype "passive"))
      (node (ref "C_11") (pin "2") (pinfunction "2_2") (pintype "passive"))
      (node (ref "C_12") (pin "2") (pinfunction "2_2") (pintype "passive"))
      (node (ref "C_13") (pin "2") (pinfunction "2_2") (pintype "passive"))
      (node (ref "C_14") (pin "2") (pinfunction "2_2") (pintype "passive"))
      (node (ref "C_15") (pin "2") (pinfunction "2_2") (pintype "passive"))
      (node (ref "C_16") (pin "2") (pinfunction "2_2") (pintype "passive"))
      (node (ref "C_17") (pin "2") (pinfunction "2_2") (pintype "passive"))
      (node (ref "C_18") (pin "2") (pinfunction "2_2") (pintype "passive"))
      (node (ref "C_19") (pin "2") (pinfunction "2_2") (pintype "passive"))
      (node (ref "C_2") (pin "2") (pinfunction "2_2") (pintype "passive"))
      (node (ref "C_20") (pin "2") (pinfunction "2_2") (pintype "passive"))
      (node (ref "C_21") (pin "2") (pinfunction "2_2") (pintype "passive"))
      (node (ref "C_22") (pin "2") (pinfunction "2_2") (pintype "passive"))
      (node (ref "C_23") (pin "2") (pinfunction "2_2") (pintype "passive"))
      (node (ref "C_24") (pin "2") (pinfunction "2_2") (pintype "passive"))
      (node (ref "C_25") (pin "2") (pinfunction "2_2") (pintype "passive"))
      (node (ref "C_26") (pin "2") (pinfunction "2_2") (pintype "passive"))
      (node (ref "C_27") (pin "2") (pinfunction "2_2") (pintype "passive"))
      (node (ref "C_28") (pin "2") (pinfunction "2_2") (pintype "passive"))
      (node (ref "C_29") (pin "2") (pinfunction "2_2") (pintype "passive"))
      (node (ref "C_3") (pin "2") (pinfunction "2_2") (pintype "passive"))
      (node (ref "C_30") (pin "2") (pinfunction "2_2") (pintype "passive"))
      (node (ref "C_31") (pin "2") (pinfunction "2_2") (pintype "passive"))
      (node (ref "C_32") (pin "2") (pinfunction "2_2") (pintype "passive"))
      (node (ref "C_33") (pin "2") (pinfunction "2_2") (pintype "passive"))
      (node (ref "C_34") (pin "2") (pinfunction "2_2") (pintype "passive"))
      (node (ref "C_35") (pin "2") (pinfunction "2_2") (pintype "passive"))
      (node (ref "C_36") (pin "2") (pinfunction "2_2") (pintype "passive"))
      (node (ref "C_37") (pin "2") (pinfunction "2_2") (pintype "passive"))
      (node (ref "C_38") (pin "2") (pinfunction "2_2") (pintype "passive"))
      (node (ref "C_39") (pin "2") (pinfunction "2_2") (pintype "passive"))
      (node (ref "C_4") (pin "2") (pinfunction "2_2") (pintype "passive"))
      (node (ref "C_40") (pin "2") (pinfunction "2_2") (pintype "passive"))
      (node (ref "C_41") (pin "2") (pinfunction "2_2") (pintype "passive"))
      (node (ref "C_42") (pin "2") (pinfunction "2_2") (pintype "passive"))
      (node (ref "C_43") (pin "2") (pinfunction "2_2") (pintype "passive"))
      (node (ref "C_44") (pin "2") (pinfunction "2_2") (pintype "passive"))
      (node (ref "C_45") (pin "2") (pinfunction "2_2") (pintype "passive"))
      (node (ref "C_46") (pin "2") (pinfunction "2_2") (pintype "passive"))
      (node (ref "C_47") (pin "2") (pinfunction "2_2") (pintype "passive"))
      (node (ref "C_48") (pin "2") (pinfunction "2_2") (pintype "passive"))
      (node (ref "C_49") (pin "2") (pinfunction "2_2") (pintype "passive"))
      (node (ref "C_5") (pin "2") (pinfunction "2_2") (pintype "passive"))
      (node (ref "C_50") (pin "2") (pinfunction "2_2") (pintype "passive"))
      (node (ref "C_51") (pin "2") (pinfunction "2_2") (pintype "passive"))
      (node (ref "C_52") (pin "2") (pinfunction "2_2") (pintype "passive"))
      (node (ref "C_53") (pin "2") (pinfunction "2_2") (pintype "passive"))
      (node (ref "C_54") (pin "2") (pinfunction "2_2") (pintype "passive"))
      (node (ref "C_55") (pin "2") (pinfunction "2_2") (pintype "passive"))
      (node (ref "C_56") (pin "2") (pinfunction "2_2") (pintype "passive"))
      (node (ref "C_57") (pin "2") (pinfunction "2_2") (pintype "passive"))
      (node (ref "C_58") (pin "2") (pinfunction "2_2") (pintype "passive"))
      (node (ref "C_59") (pin "2") (pinfunction "2_2") (pintype "passive"))
      (node (ref "C_6") (pin "2") (pinfunction "2_2") (pintype "passive"))
      (node (ref "C_60") (pin "2") (pinfunction "2_2") (pintype "passive"))
      (node (ref "C_61") (pin "2") (pinfunction "2_2") (pintype "passive"))
      (node (ref "C_62") (pin "2") (pinfunction "2_2") (pintype "passive"))
      (node (ref "C_63") (pin "2") (pinfunction "2_2") (pintype "passive"))
      (node (ref "C_64") (pin "2") (pinfunction "2_2") (pintype "passive"))
      (node (ref "C_65") (pin "2") (pinfunction "2_2") (pintype "passive"))
      (node (ref "C_66") (pin "2") (pinfunction "2_2") (pintype "passive"))
      (node (ref "C_67") (pin "2") (pinfunction "2_2") (pintype "passive"))
      (node (ref "C_68") (pin "2") (pinfunction "2_2") (pintype "passive"))
      (node (ref "C_69") (pin "2") (pinfunction "2_2") (pintype "passive"))
      (node (ref "C_7") (pin "2") (pinfunction "2_2") (pintype "passive"))
      (node (ref "C_70") (pin "2") (pinfunction "2_2") (pintype "passive"))
      (node (ref "C_71") (pin "2") (pinfunction "2_2") (pintype "passive"))
      (node (ref "C_72") (pin "2") (pinfunction "2_2") (pintype "passive"))
      (node (ref "C_8") (pin "2") (pinfunction "2_2") (pintype "passive"))
      (node (ref "C_9") (pin "2") (pinfunction "2_2") (pintype "passive"))
      (node (ref "D12") (pin "2") (pinfunction "A_2") (pintype "passive"))
      (node (ref "D4") (pin "1") (pinfunction "C_1") (pintype "passive"))
      (node (ref "D5") (pin "1") (pinfunction "C_1") (pintype "passive"))
      (node (ref "D6") (pin "1") (pinfunction "C_1") (pintype "passive"))
      (node (ref "D7") (pin "1") (pinfunction "C_1") (pintype "passive"))
      (node (ref "D9") (pin "2") (pinfunction "2_2") (pintype "passive"))
      (node (ref "D9") (pin "5") (pinfunction "5_5") (pintype "passive"))
      (node (ref "J1") (pin "3") (pinfunction "3_3") (pintype "passive"))
      (node (ref "J10") (pin "1") (pinfunction "1_1") (pintype "passive"))
      (node (ref "J11") (pin "1") (pinfunction "1_1") (pintype "passive"))
      (node (ref "J12") (pin "1") (pinfunction "1_1") (pintype "passive"))
      (node (ref "J13") (pin "1") (pinfunction "1_1") (pintype "passive"))
      (node (ref "J14") (pin "1") (pinfunction "1_1") (pintype "passive"))
      (node (ref "J15") (pin "1") (pinfunction "1_1") (pintype "passive"))
      (node (ref "J2") (pin "5") (pinfunction "5_5") (pintype "passive"))
      (node (ref "J2") (pin "6") (pinfunction "6_6") (pintype "passive"))
      (node (ref "J2") (pin "7") (pinfunction "7_7") (pintype "passive"))
      (node (ref "J2") (pin "8") (pinfunction "8_8") (pintype "passive"))
      (node (ref "J2") (pin "9") (pinfunction "9_9") (pintype "passive"))
      (node (ref "J3") (pin "2") (pinfunction "2_2") (pintype "passive"))
      (node (ref "J4") (pin "4") (pinfunction "4_4") (pintype "passive"))
      (node (ref "J4") (pin "5") (pinfunction "5_5") (pintype "passive"))
      (node (ref "J4") (pin "6") (pinfunction "6_6") (pintype "passive"))
      (node (ref "J5") (pin "1") (pinfunction "1_1") (pintype "passive"))
      (node (ref "J6") (pin "1") (pinfunction "1_1") (pintype "passive"))
      (node (ref "J7") (pin "1") (pinfunction "1_1") (pintype "passive"))
      (node (ref "J8") (pin "1") (pinfunction "1_1") (pintype "passive"))
      (node (ref "J9") (pin "1") (pinfunction "1_1") (pintype "passive"))
      (node (ref "Q4") (pin "1") (pinfunction "S_1") (pintype "passive"))
      (node (ref "Q4") (pin "2") (pinfunction "S_2") (pintype "passive"))
      (node (ref "Q4") (pin "3") (pinfunction "S_3") (pintype "passive"))
      (node (ref "Q5") (pin "1") (pinfunction "S_1") (pintype "passive"))
      (node (ref "Q5") (pin "2") (pinfunction "S_2") (pintype "passive"))
      (node (ref "Q5") (pin "3") (pinfunction "S_3") (pintype "passive"))
      (node (ref "Q6") (pin "1") (pinfunction "S_1") (pintype "passive"))
      (node (ref "Q6") (pin "2") (pinfunction "S_2") (pintype "passive"))
      (node (ref "Q6") (pin "3") (pinfunction "S_3") (pintype "passive"))
      (node (ref "Q7") (pin "1") (pinfunction "S_1") (pintype "passive"))
      (node (ref "Q7") (pin "2") (pinfunction "S_2") (pintype "passive"))
      (node (ref "Q7") (pin "3") (pinfunction "S_3") (pintype "passive"))
      (node (ref "Q8") (pin "1") (pinfunction "S_1") (pintype "passive"))
      (node (ref "Q8") (pin "2") (pinfunction "S_2") (pintype "passive"))
      (node (ref "Q8") (pin "3") (pinfunction "S_3") (pintype "passive"))
      (node (ref "Q9") (pin "1") (pinfunction "S_1") (pintype "passive"))
      (node (ref "Q9") (pin "2") (pinfunction "S_2") (pintype "passive"))
      (node (ref "Q9") (pin "3") (pinfunction "S_3") (pintype "passive"))
      (node (ref "R1") (pin "1") (pinfunction "1_1") (pintype "passive"))
      (node (ref "R17") (pin "2") (pinfunction "2_2") (pintype "passive"))
      (node (ref "R18") (pin "1") (pinfunction "1_1") (pintype "passive"))
      (node (ref "R19") (pin "1") (pinfunction "1_1") (pintype "passive"))
      (node (ref "R2") (pin "1") (pinfunction "1_1") (pintype "passive"))
      (node (ref "R20") (pin "1") (pinfunction "1_1") (pintype "passive"))
      (node (ref "R21") (pin "2") (pinfunction "2_2") (pintype "passive"))
      (node (ref "R22") (pin "2") (pinfunction "2_2") (pintype "passive"))
      (node (ref "R24") (pin "2") (pinfunction "2_2") (pintype "passive"))
      (node (ref "R25") (pin "1") (pinfunction "1_1") (pintype "passive"))
      (node (ref "R3") (pin "1") (pinfunction "1_1") (pintype "passive"))
      (node (ref "R30") (pin "2") (pinfunction "2_2") (pintype "passive"))
      (node (ref "R4") (pin "1") (pinfunction "1_1") (pintype "passive"))
      (node (ref "R43") (pin "1") (pinfunction "1_1") (pintype "passive"))
      (node (ref "R44") (pin "1") (pinfunction "1_1") (pintype "passive"))
      (node (ref "R45") (pin "1") (pinfunction "1_1") (pintype "passive"))
      (node (ref "R46") (pin "1") (pinfunction "1_1") (pintype "passive"))
      (node (ref "R51") (pin "2") (pinfunction "2_2") (pintype "passive"))
      (node (ref "R55") (pin "2") (pinfunction "2_2") (pintype "passive"))
      (node (ref "R64") (pin "1") (pinfunction "1_1") (pintype "passive"))
      (node (ref "R65") (pin "1") (pinfunction "1_1") (pintype "passive"))
      (node (ref "R66") (pin "1") (pinfunction "1_1") (pintype "passive"))
      (node (ref "R67") (pin "1") (pinfunction "1_1") (pintype "passive"))
      (node (ref "U1") (pin "4") (pinfunction "GND_4") (pintype "passive"))
      (node (ref "U1") (pin "9") (pinfunction "EP_9") (pintype "passive"))
      (node (ref "U10") (pin "10") (pinfunction "VSS_PLL_10") (pintype "passive"))
      (node (ref "U10") (pin "15") (pinfunction "DVSS_15") (pintype "passive"))
      (node (ref "U10") (pin "17") (pinfunction "CHIP_ID1_17") (pintype "passive"))
      (node (ref "U10") (pin "28") (pinfunction "DVSS_28") (pintype "passive"))
      (node (ref "U10") (pin "31") (pinfunction "OVSS1_31") (pintype "passive"))
      (node (ref "U10") (pin "33") (pinfunction "DVSS_33") (pintype "passive"))
      (node (ref "U10") (pin "36") (pinfunction "DVSS_36") (pintype "passive"))
      (node (ref "U10") (pin "40") (pinfunction "DVSS_40") (pintype "passive"))
      (node (ref "U10") (pin "44") (pinfunction "DVSS_44") (pintype "passive"))
      (node (ref "U10") (pin "50") (pinfunction "OVSS0_50") (pintype "passive"))
      (node (ref "U10") (pin "53") (pinfunction "DVSS_53") (pintype "passive"))
      (node (ref "U10") (pin "61") (pinfunction "DVSS_61") (pintype "passive"))
      (node (ref "U10") (pin "64") (pinfunction "DVSS_64") (pintype "passive"))
      (node (ref "U10") (pin "65") (pinfunction "DVSS_EP_65") (pintype "passive"))
      (node (ref "U10") (pin "7") (pinfunction "VSSA_PLL_7") (pintype "passive"))
      (node (ref "U11") (pin "10") (pinfunction "VSS_PLL_10") (pintype "passive"))
      (node (ref "U11") (pin "15") (pinfunction "DVSS_15") (pintype "passive"))
      (node (ref "U11") (pin "16") (pinfunction "CHIP_ID0_16") (pintype "passive"))
      (node (ref "U11") (pin "28") (pinfunction "DVSS_28") (pintype "passive"))
      (node (ref "U11") (pin "31") (pinfunction "OVSS1_31") (pintype "passive"))
      (node (ref "U11") (pin "33") (pinfunction "DVSS_33") (pintype "passive"))
      (node (ref "U11") (pin "36") (pinfunction "DVSS_36") (pintype "passive"))
      (node (ref "U11") (pin "40") (pinfunction "DVSS_40") (pintype "passive"))
      (node (ref "U11") (pin "44") (pinfunction "DVSS_44") (pintype "passive"))
      (node (ref "U11") (pin "50") (pinfunction "OVSS0_50") (pintype "passive"))
      (node (ref "U11") (pin "53") (pinfunction "DVSS_53") (pintype "passive"))
      (node (ref "U11") (pin "61") (pinfunction "DVSS_61") (pintype "passive"))
      (node (ref "U11") (pin "64") (pinfunction "DVSS_64") (pintype "passive"))
      (node (ref "U11") (pin "65") (pinfunction "DVSS_EP_65") (pintype "passive"))
      (node (ref "U11") (pin "7") (pinfunction "VSSA_PLL_7") (pintype "passive"))
      (node (ref "U12") (pin "10") (pinfunction "VSS_PLL_10") (pintype "passive"))
      (node (ref "U12") (pin "15") (pinfunction "DVSS_15") (pintype "passive"))
      (node (ref "U12") (pin "28") (pinfunction "DVSS_28") (pintype "passive"))
      (node (ref "U12") (pin "31") (pinfunction "OVSS1_31") (pintype "passive"))
      (node (ref "U12") (pin "33") (pinfunction "DVSS_33") (pintype "passive"))
      (node (ref "U12") (pin "36") (pinfunction "DVSS_36") (pintype "passive"))
      (node (ref "U12") (pin "40") (pinfunction "DVSS_40") (pintype "passive"))
      (node (ref "U12") (pin "44") (pinfunction "DVSS_44") (pintype "passive"))
      (node (ref "U12") (pin "50") (pinfunction "OVSS0_50") (pintype "passive"))
      (node (ref "U12") (pin "53") (pinfunction "DVSS_53") (pintype "passive"))
      (node (ref "U12") (pin "61") (pinfunction "DVSS_61") (pintype "passive"))
      (node (ref "U12") (pin "64") (pinfunction "DVSS_64") (pintype "passive"))
      (node (ref "U12") (pin "65") (pinfunction "DVSS_EP_65") (pintype "passive"))
      (node (ref "U12") (pin "7") (pinfunction "VSSA_PLL_7") (pintype "passive"))
      (node (ref "U13") (pin "2") (pinfunction "GND_2") (pintype "passive"))
      (node (ref "U13") (pin "3") (pinfunction "GND_3") (pintype "passive"))
      (node (ref "U13") (pin "6") (pinfunction "GND_6") (pintype "passive"))
      (node (ref "U13") (pin "7") (pinfunction "GND_7") (pintype "passive"))
      (node (ref "U14") (pin "2") (pinfunction "GND_2") (pintype "passive"))
      (node (ref "U15") (pin "6") (pinfunction "GND_6") (pintype "passive"))
      (node (ref "U15") (pin "7") (pinfunction "GND_7") (pintype "passive"))
      (node (ref "U16") (pin "4") (pinfunction "GND_4") (pintype "passive"))
      (node (ref "U17") (pin "4") (pinfunction "GND_4") (pintype "passive"))
      (node (ref "U18") (pin "10") (pinfunction "VSS_PLL_10") (pintype "passive"))
      (node (ref "U18") (pin "15") (pinfunction "DVSS_15") (pintype "passive"))
      (node (ref "U18") (pin "16") (pinfunction "CHIP_ID0_16") (pintype "passive"))
      (node (ref "U18") (pin "17") (pinfunction "CHIP_ID1_17") (pintype "passive"))
      (node (ref "U18") (pin "18") (pinfunction "CHIP_ID2_18") (pintype "passive"))
      (node (ref "U18") (pin "28") (pinfunction "DVSS_28") (pintype "passive"))
      (node (ref "U18") (pin "31") (pinfunction "OVSS1_31") (pintype "passive"))
      (node (ref "U18") (pin "33") (pinfunction "DVSS_33") (pintype "passive"))
      (node (ref "U18") (pin "36") (pinfunction "DVSS_36") (pintype "passive"))
      (node (ref "U18") (pin "40") (pinfunction "DVSS_40") (pintype "passive"))
      (node (ref "U18") (pin "44") (pinfunction "DVSS_44") (pintype "passive"))
      (node (ref "U18") (pin "50") (pinfunction "OVSS0_50") (pintype "passive"))
      (node (ref "U18") (pin "53") (pinfunction "DVSS_53") (pintype "passive"))
      (node (ref "U18") (pin "61") (pinfunction "DVSS_61") (pintype "passive"))
      (node (ref "U18") (pin "64") (pinfunction "DVSS_64") (pintype "passive"))
      (node (ref "U18") (pin "65") (pinfunction "DVSS_EP_65") (pintype "passive"))
      (node (ref "U18") (pin "7") (pinfunction "VSSA_PLL_7") (pintype "passive"))
      (node (ref "U19") (pin "10") (pinfunction "VSS_PLL_10") (pintype "passive"))
      (node (ref "U19") (pin "15") (pinfunction "DVSS_15") (pintype "passive"))
      (node (ref "U19") (pin "17") (pinfunction "CHIP_ID1_17") (pintype "passive"))
      (node (ref "U19") (pin "18") (pinfunction "CHIP_ID2_18") (pintype "passive"))
      (node (ref "U19") (pin "28") (pinfunction "DVSS_28") (pintype "passive"))
      (node (ref "U19") (pin "31") (pinfunction "OVSS1_31") (pintype "passive"))
      (node (ref "U19") (pin "33") (pinfunction "DVSS_33") (pintype "passive"))
      (node (ref "U19") (pin "36") (pinfunction "DVSS_36") (pintype "passive"))
      (node (ref "U19") (pin "40") (pinfunction "DVSS_40") (pintype "passive"))
      (node (ref "U19") (pin "44") (pinfunction "DVSS_44") (pintype "passive"))
      (node (ref "U19") (pin "50") (pinfunction "OVSS0_50") (pintype "passive"))
      (node (ref "U19") (pin "53") (pinfunction "DVSS_53") (pintype "passive"))
      (node (ref "U19") (pin "61") (pinfunction "DVSS_61") (pintype "passive"))
      (node (ref "U19") (pin "64") (pinfunction "DVSS_64") (pintype "passive"))
      (node (ref "U19") (pin "65") (pinfunction "DVSS_EP_65") (pintype "passive"))
      (node (ref "U19") (pin "7") (pinfunction "VSSA_PLL_7") (pintype "passive"))
      (node (ref "U2") (pin "4") (pinfunction "GND_4") (pintype "passive"))
      (node (ref "U2") (pin "9") (pinfunction "EP_9") (pintype "passive"))
      (node (ref "U20") (pin "10") (pinfunction "VSS_PLL_10") (pintype "passive"))
      (node (ref "U20") (pin "15") (pinfunction "DVSS_15") (pintype "passive"))
      (node (ref "U20") (pin "16") (pinfunction "CHIP_ID0_16") (pintype "passive"))
      (node (ref "U20") (pin "18") (pinfunction "CHIP_ID2_18") (pintype "passive"))
      (node (ref "U20") (pin "28") (pinfunction "DVSS_28") (pintype "passive"))
      (node (ref "U20") (pin "31") (pinfunction "OVSS1_31") (pintype "passive"))
      (node (ref "U20") (pin "33") (pinfunction "DVSS_33") (pintype "passive"))
      (node (ref "U20") (pin "36") (pinfunction "DVSS_36") (pintype "passive"))
      (node (ref "U20") (pin "40") (pinfunction "DVSS_40") (pintype "passive"))
      (node (ref "U20") (pin "44") (pinfunction "DVSS_44") (pintype "passive"))
      (node (ref "U20") (pin "50") (pinfunction "OVSS0_50") (pintype "passive"))
      (node (ref "U20") (pin "53") (pinfunction "DVSS_53") (pintype "passive"))
      (node (ref "U20") (pin "61") (pinfunction "DVSS_61") (pintype "passive"))
      (node (ref "U20") (pin "64") (pinfunction "DVSS_64") (pintype "passive"))
      (node (ref "U20") (pin "65") (pinfunction "DVSS_EP_65") (pintype "passive"))
      (node (ref "U20") (pin "7") (pinfunction "VSSA_PLL_7") (pintype "passive"))
      (node (ref "U21") (pin "10") (pinfunction "VSS_PLL_10") (pintype "passive"))
      (node (ref "U21") (pin "15") (pinfunction "DVSS_15") (pintype "passive"))
      (node (ref "U21") (pin "16") (pinfunction "CHIP_ID0_16") (pintype "passive"))
      (node (ref "U21") (pin "28") (pinfunction "DVSS_28") (pintype "passive"))
      (node (ref "U21") (pin "31") (pinfunction "OVSS1_31") (pintype "passive"))
      (node (ref "U21") (pin "33") (pinfunction "DVSS_33") (pintype "passive"))
      (node (ref "U21") (pin "36") (pinfunction "DVSS_36") (pintype "passive"))
      (node (ref "U21") (pin "40") (pinfunction "DVSS_40") (pintype "passive"))
      (node (ref "U21") (pin "44") (pinfunction "DVSS_44") (pintype "passive"))
      (node (ref "U21") (pin "50") (pinfunction "OVSS0_50") (pintype "passive"))
      (node (ref "U21") (pin "53") (pinfunction "DVSS_53") (pintype "passive"))
      (node (ref "U21") (pin "61") (pinfunction "DVSS_61") (pintype "passive"))
      (node (ref "U21") (pin "64") (pinfunction "DVSS_64") (pintype "passive"))
      (node (ref "U21") (pin "65") (pinfunction "DVSS_EP_65") (pintype "passive"))
      (node (ref "U21") (pin "7") (pinfunction "VSSA_PLL_7") (pintype "passive"))
      (node (ref "U22") (pin "6") (pinfunction "GND_6") (pintype "passive"))
      (node (ref "U22") (pin "7") (pinfunction "GND_7") (pintype "passive"))
      (node (ref "U23") (pin "6") (pinfunction "GND_6") (pintype "passive"))
      (node (ref "U23") (pin "7") (pinfunction "GND_7") (pintype "passive"))
      (node (ref "U24") (pin "10") (pinfunction "VSS_PLL_10") (pintype "passive"))
      (node (ref "U24") (pin "15") (pinfunction "DVSS_15") (pintype "passive"))
      (node (ref "U24") (pin "16") (pinfunction "CHIP_ID0_16") (pintype "passive"))
      (node (ref "U24") (pin "17") (pinfunction "CHIP_ID1_17") (pintype "passive"))
      (node (ref "U24") (pin "28") (pinfunction "DVSS_28") (pintype "passive"))
      (node (ref "U24") (pin "31") (pinfunction "OVSS1_31") (pintype "passive"))
      (node (ref "U24") (pin "33") (pinfunction "DVSS_33") (pintype "passive"))
      (node (ref "U24") (pin "36") (pinfunction "DVSS_36") (pintype "passive"))
      (node (ref "U24") (pin "40") (pinfunction "DVSS_40") (pintype "passive"))
      (node (ref "U24") (pin "44") (pinfunction "DVSS_44") (pintype "passive"))
      (node (ref "U24") (pin "50") (pinfunction "OVSS0_50") (pintype "passive"))
      (node (ref "U24") (pin "53") (pinfunction "DVSS_53") (pintype "passive"))
      (node (ref "U24") (pin "61") (pinfunction "DVSS_61") (pintype "passive"))
      (node (ref "U24") (pin "64") (pinfunction "DVSS_64") (pintype "passive"))
      (node (ref "U24") (pin "65") (pinfunction "DVSS_EP_65") (pintype "passive"))
      (node (ref "U24") (pin "7") (pinfunction "VSSA_PLL_7") (pintype "passive"))
      (node (ref "U25") (pin "10") (pinfunction "VSS_PLL_10") (pintype "passive"))
      (node (ref "U25") (pin "15") (pinfunction "DVSS_15") (pintype "passive"))
      (node (ref "U25") (pin "17") (pinfunction "CHIP_ID1_17") (pintype "passive"))
      (node (ref "U25") (pin "28") (pinfunction "DVSS_28") (pintype "passive"))
      (node (ref "U25") (pin "31") (pinfunction "OVSS1_31") (pintype "passive"))
      (node (ref "U25") (pin "33") (pinfunction "DVSS_33") (pintype "passive"))
      (node (ref "U25") (pin "36") (pinfunction "DVSS_36") (pintype "passive"))
      (node (ref "U25") (pin "40") (pinfunction "DVSS_40") (pintype "passive"))
      (node (ref "U25") (pin "44") (pinfunction "DVSS_44") (pintype "passive"))
      (node (ref "U25") (pin "50") (pinfunction "OVSS0_50") (pintype "passive"))
      (node (ref "U25") (pin "53") (pinfunction "DVSS_53") (pintype "passive"))
      (node (ref "U25") (pin "61") (pinfunction "DVSS_61") (pintype "passive"))
      (node (ref "U25") (pin "64") (pinfunction "DVSS_64") (pintype "passive"))
      (node (ref "U25") (pin "65") (pinfunction "DVSS_EP_65") (pintype "passive"))
      (node (ref "U25") (pin "7") (pinfunction "VSSA_PLL_7") (pintype "passive"))
      (node (ref "U26") (pin "10") (pinfunction "VSS_PLL_10") (pintype "passive"))
      (node (ref "U26") (pin "15") (pinfunction "DVSS_15") (pintype "passive"))
      (node (ref "U26") (pin "16") (pinfunction "CHIP_ID0_16") (pintype "passive"))
      (node (ref "U26") (pin "28") (pinfunction "DVSS_28") (pintype "passive"))
      (node (ref "U26") (pin "31") (pinfunction "OVSS1_31") (pintype "passive"))
      (node (ref "U26") (pin "33") (pinfunction "DVSS_33") (pintype "passive"))
      (node (ref "U26") (pin "36") (pinfunction "DVSS_36") (pintype "passive"))
      (node (ref "U26") (pin "40") (pinfunction "DVSS_40") (pintype "passive"))
      (node (ref "U26") (pin "44") (pinfunction "DVSS_44") (pintype "passive"))
      (node (ref "U26") (pin "50") (pinfunction "OVSS0_50") (pintype "passive"))
      (node (ref "U26") (pin "53") (pinfunction "DVSS_53") (pintype "passive"))
      (node (ref "U26") (pin "61") (pinfunction "DVSS_61") (pintype "passive"))
      (node (ref "U26") (pin "64") (pinfunction "DVSS_64") (pintype "passive"))
      (node (ref "U26") (pin "65") (pinfunction "DVSS_EP_65") (pintype "passive"))
      (node (ref "U26") (pin "7") (pinfunction "VSSA_PLL_7") (pintype "passive"))
      (node (ref "U27") (pin "10") (pinfunction "VSS_PLL_10") (pintype "passive"))
      (node (ref "U27") (pin "15") (pinfunction "DVSS_15") (pintype "passive"))
      (node (ref "U27") (pin "28") (pinfunction "DVSS_28") (pintype "passive"))
      (node (ref "U27") (pin "31") (pinfunction "OVSS1_31") (pintype "passive"))
      (node (ref "U27") (pin "33") (pinfunction "DVSS_33") (pintype "passive"))
      (node (ref "U27") (pin "36") (pinfunction "DVSS_36") (pintype "passive"))
      (node (ref "U27") (pin "40") (pinfunction "DVSS_40") (pintype "passive"))
      (node (ref "U27") (pin "44") (pinfunction "DVSS_44") (pintype "passive"))
      (node (ref "U27") (pin "50") (pinfunction "OVSS0_50") (pintype "passive"))
      (node (ref "U27") (pin "53") (pinfunction "DVSS_53") (pintype "passive"))
      (node (ref "U27") (pin "61") (pinfunction "DVSS_61") (pintype "passive"))
      (node (ref "U27") (pin "64") (pinfunction "DVSS_64") (pintype "passive"))
      (node (ref "U27") (pin "65") (pinfunction "DVSS_EP_65") (pintype "passive"))
      (node (ref "U27") (pin "7") (pinfunction "VSSA_PLL_7") (pintype "passive"))
      (node (ref "U3") (pin "4") (pinfunction "GND_4") (pintype "passive"))
      (node (ref "U3") (pin "9") (pinfunction "EP_9") (pintype "passive"))
      (node (ref "U4") (pin "10") (pinfunction "VSS_PLL_10") (pintype "passive"))
      (node (ref "U4") (pin "15") (pinfunction "DVSS_15") (pintype "passive"))
      (node (ref "U4") (pin "16") (pinfunction "CHIP_ID0_16") (pintype "passive"))
      (node (ref "U4") (pin "17") (pinfunction "CHIP_ID1_17") (pintype "passive"))
      (node (ref "U4") (pin "18") (pinfunction "CHIP_ID2_18") (pintype "passive"))
      (node (ref "U4") (pin "28") (pinfunction "DVSS_28") (pintype "passive"))
      (node (ref "U4") (pin "31") (pinfunction "OVSS1_31") (pintype "passive"))
      (node (ref "U4") (pin "33") (pinfunction "DVSS_33") (pintype "passive"))
      (node (ref "U4") (pin "36") (pinfunction "DVSS_36") (pintype "passive"))
      (node (ref "U4") (pin "40") (pinfunction "DVSS_40") (pintype "passive"))
      (node (ref "U4") (pin "44") (pinfunction "DVSS_44") (pintype "passive"))
      (node (ref "U4") (pin "50") (pinfunction "OVSS0_50") (pintype "passive"))
      (node (ref "U4") (pin "53") (pinfunction "DVSS_53") (pintype "passive"))
      (node (ref "U4") (pin "61") (pinfunction "DVSS_61") (pintype "passive"))
      (node (ref "U4") (pin "64") (pinfunction "DVSS_64") (pintype "passive"))
      (node (ref "U4") (pin "65") (pinfunction "DVSS_EP_65") (pintype "passive"))
      (node (ref "U4") (pin "7") (pinfunction "VSSA_PLL_7") (pintype "passive"))
      (node (ref "U5") (pin "10") (pinfunction "VSS_PLL_10") (pintype "passive"))
      (node (ref "U5") (pin "15") (pinfunction "DVSS_15") (pintype "passive"))
      (node (ref "U5") (pin "17") (pinfunction "CHIP_ID1_17") (pintype "passive"))
      (node (ref "U5") (pin "18") (pinfunction "CHIP_ID2_18") (pintype "passive"))
      (node (ref "U5") (pin "28") (pinfunction "DVSS_28") (pintype "passive"))
      (node (ref "U5") (pin "31") (pinfunction "OVSS1_31") (pintype "passive"))
      (node (ref "U5") (pin "33") (pinfunction "DVSS_33") (pintype "passive"))
      (node (ref "U5") (pin "36") (pinfunction "DVSS_36") (pintype "passive"))
      (node (ref "U5") (pin "40") (pinfunction "DVSS_40") (pintype "passive"))
      (node (ref "U5") (pin "44") (pinfunction "DVSS_44") (pintype "passive"))
      (node (ref "U5") (pin "50") (pinfunction "OVSS0_50") (pintype "passive"))
      (node (ref "U5") (pin "53") (pinfunction "DVSS_53") (pintype "passive"))
      (node (ref "U5") (pin "61") (pinfunction "DVSS_61") (pintype "passive"))
      (node (ref "U5") (pin "64") (pinfunction "DVSS_64") (pintype "passive"))
      (node (ref "U5") (pin "65") (pinfunction "DVSS_EP_65") (pintype "passive"))
      (node (ref "U5") (pin "7") (pinfunction "VSSA_PLL_7") (pintype "passive"))
      (node (ref "U6") (pin "10") (pinfunction "VSS_PLL_10") (pintype "passive"))
      (node (ref "U6") (pin "15") (pinfunction "DVSS_15") (pintype "passive"))
      (node (ref "U6") (pin "16") (pinfunction "CHIP_ID0_16") (pintype "passive"))
      (node (ref "U6") (pin "18") (pinfunction "CHIP_ID2_18") (pintype "passive"))
      (node (ref "U6") (pin "28") (pinfunction "DVSS_28") (pintype "passive"))
      (node (ref "U6") (pin "31") (pinfunction "OVSS1_31") (pintype "passive"))
      (node (ref "U6") (pin "33") (pinfunction "DVSS_33") (pintype "passive"))
      (node (ref "U6") (pin "36") (pinfunction "DVSS_36") (pintype "passive"))
      (node (ref "U6") (pin "40") (pinfunction "DVSS_40") (pintype "passive"))
      (node (ref "U6") (pin "44") (pinfunction "DVSS_44") (pintype "passive"))
      (node (ref "U6") (pin "50") (pinfunction "OVSS0_50") (pintype "passive"))
      (node (ref "U6") (pin "53") (pinfunction "DVSS_53") (pintype "passive"))
      (node (ref "U6") (pin "61") (pinfunction "DVSS_61") (pintype "passive"))
      (node (ref "U6") (pin "64") (pinfunction "DVSS_64") (pintype "passive"))
      (node (ref "U6") (pin "65") (pinfunction "DVSS_EP_65") (pintype "passive"))
      (node (ref "U6") (pin "7") (pinfunction "VSSA_PLL_7") (pintype "passive"))
      (node (ref "U7") (pin "10") (pinfunction "VSS_PLL_10") (pintype "passive"))
      (node (ref "U7") (pin "15") (pinfunction "DVSS_15") (pintype "passive"))
      (node (ref "U7") (pin "18") (pinfunction "CHIP_ID2_18") (pintype "passive"))
      (node (ref "U7") (pin "28") (pinfunction "DVSS_28") (pintype "passive"))
      (node (ref "U7") (pin "31") (pinfunction "OVSS1_31") (pintype "passive"))
      (node (ref "U7") (pin "33") (pinfunction "DVSS_33") (pintype "passive"))
      (node (ref "U7") (pin "36") (pinfunction "DVSS_36") (pintype "passive"))
      (node (ref "U7") (pin "40") (pinfunction "DVSS_40") (pintype "passive"))
      (node (ref "U7") (pin "44") (pinfunction "DVSS_44") (pintype "passive"))
      (node (ref "U7") (pin "50") (pinfunction "OVSS0_50") (pintype "passive"))
      (node (ref "U7") (pin "53") (pinfunction "DVSS_53") (pintype "passive"))
      (node (ref "U7") (pin "61") (pinfunction "DVSS_61") (pintype "passive"))
      (node (ref "U7") (pin "64") (pinfunction "DVSS_64") (pintype "passive"))
      (node (ref "U7") (pin "65") (pinfunction "DVSS_EP_65") (pintype "passive"))
      (node (ref "U7") (pin "7") (pinfunction "VSSA_PLL_7") (pintype "passive"))
      (node (ref "U8") (pin "20") (pinfunction "AVSS_20") (pintype "passive"))
      (node (ref "U8") (pin "25") (pinfunction "VSS_25") (pintype "passive"))
      (node (ref "U8") (pin "41") (pinfunction "VSS_41") (pintype "passive"))
      (node (ref "U8") (pin "9") (pinfunction "VSS_9") (pintype "passive"))
      (node (ref "U9") (pin "10") (pinfunction "VSS_PLL_10") (pintype "passive"))
      (node (ref "U9") (pin "15") (pinfunction "DVSS_15") (pintype "passive"))
      (node (ref "U9") (pin "16") (pinfunction "CHIP_ID0_16") (pintype "passive"))
      (node (ref "U9") (pin "17") (pinfunction "CHIP_ID1_17") (pintype "passive"))
      (node (ref "U9") (pin "28") (pinfunction "DVSS_28") (pintype "passive"))
      (node (ref "U9") (pin "31") (pinfunction "OVSS1_31") (pintype "passive"))
      (node (ref "U9") (pin "33") (pinfunction "DVSS_33") (pintype "passive"))
      (node (ref "U9") (pin "36") (pinfunction "DVSS_36") (pintype "passive"))
      (node (ref "U9") (pin "40") (pinfunction "DVSS_40") (pintype "passive"))
      (node (ref "U9") (pin "44") (pinfunction "DVSS_44") (pintype "passive"))
      (node (ref "U9") (pin "50") (pinfunction "OVSS0_50") (pintype "passive"))
      (node (ref "U9") (pin "53") (pinfunction "DVSS_53") (pintype "passive"))
      (node (ref "U9") (pin "61") (pinfunction "DVSS_61") (pintype "passive"))
      (node (ref "U9") (pin "64") (pinfunction "DVSS_64") (pintype "passive"))
      (node (ref "U9") (pin "65") (pinfunction "DVSS_EP_65") (pintype "passive"))
      (node (ref "U9") (pin "7") (pinfunction "VSSA_PLL_7") (pintype "passive"))
    )
    (net (code "119") (name "Net-(U8-AN2{slash}C2IN2-{slash}VMIO{slash}RPI34{slash}RB2)") (class "Default")
      (node (ref "TP17") (pin "1") (pinfunction "1_1") (pintype "passive"))
      (node (ref "U8") (pin "14") (pinfunction "AN2/C2IN2-/VMIO/RPI34/RB2_14") (pintype "passive"))
    )
    (net (code "120") (name "Net-(U8-AN3{slash}C2IN1+{slash}VPIO{slash}RPI35{slash}RB3)") (class "Default")
      (node (ref "TP12") (pin "1") (pinfunction "1_1") (pintype "passive"))
      (node (ref "U8") (pin "13") (pinfunction "AN3/C2IN1+/VPIO/RPI35/RB3_13") (pintype "passive"))
    )
    (net (code "121") (name "Net-(U8-AN4{slash}C1IN2-{slash}USBOEN{slash}RPI36{slash}RB4)") (class "Default")
      (node (ref "TP54") (pin "1") (pinfunction "1_1") (pintype "passive"))
      (node (ref "U8") (pin "12") (pinfunction "AN4/C1IN2-/USBOEN/RPI36/RB4_12") (pintype "passive"))
    )
    (net (code "122") (name "Net-(U8-AN5{slash}C1IN1+{slash}VBUSON{slash}VBUSST{slash}RPI37{slash}RB5)") (class "Default")
      (node (ref "TP53") (pin "1") (pinfunction "1_1") (pintype "passive"))
      (node (ref "U8") (pin "11") (pinfunction "AN5/C1IN1+/VBUSON/VBUSST/RPI37/RB5_11") (pintype "passive"))
    )
    (net (code "123") (name "Net-(U8-AN8{slash}PMA6{slash}RPI40{slash}RB8)") (class "Default")
      (node (ref "TP20") (pin "1") (pinfunction "1_1") (pintype "passive"))
      (node (ref "U8") (pin "21") (pinfunction "AN8/PMA6/RPI40/RB8_21") (pintype "passive"))
    )
    (net (code "124") (name "Net-(U8-AN9{slash}PMA7{slash}{slash}RPI41{slash}RB9)") (class "Default")
      (node (ref "TP21") (pin "1") (pinfunction "1_1") (pintype "passive"))
      (node (ref "U8") (pin "22") (pinfunction "AN9/PMA7//RPI41/RB9_22") (pintype "passive"))
    )
    (net (code "125") (name "Net-(U8-AN14{slash}PMA1{slash}RPI46{slash}RB14)") (class "Default")
      (node (ref "TP27") (pin "1") (pinfunction "1_1") (pintype "passive"))
      (node (ref "U8") (pin "29") (pinfunction "AN14/PMA1/RPI46/RB14_29") (pintype "passive"))
    )
    (net (code "126") (name "Net-(U8-AN15{slash}PMA0{slash}RPI47{slash}RB15)") (class "Default")
      (node (ref "TP28") (pin "1") (pinfunction "1_1") (pintype "passive"))
      (node (ref "U8") (pin "30") (pinfunction "AN15/PMA0/RPI47/RB15_30") (pintype "passive"))
    )
    (net (code "127") (name "Net-(U8-ASDA1{slash}DPLN{slash}RPI73{slash}RD9)") (class "Default")
      (node (ref "TP22") (pin "1") (pinfunction "1_1") (pintype "passive"))
      (node (ref "U8") (pin "43") (pinfunction "ASDA1/DPLN/RPI73/RD9_43") (pintype "passive"))
    )
    (net (code "128") (name "Net-(U8-C2IN1-{slash}PMA2{slash}RPI121{slash}RG9)") (class "Default")
      (node (ref "TP10") (pin "1") (pinfunction "1_1") (pintype "passive"))
      (node (ref "U8") (pin "8") (pinfunction "C2IN1-/PMA2/RPI121/RG9_8") (pintype "passive"))
    )
    (net (code "129") (name "Net-(U8-C2IN3-{slash}SDO2{slash}PMA3{slash}RP120{slash}RG8)") (class "Default")
      (node (ref "TP9") (pin "1") (pinfunction "1_1") (pintype "passive"))
      (node (ref "U8") (pin "6") (pinfunction "C2IN3-/SDO2/PMA3/RP120/RG8_6") (pintype "passive"))
    )
    (net (code "130") (name "Net-(U8-C3IN2-{slash}RP70{slash}RD6)") (class "Default")
      (node (ref "TP11") (pin "1") (pinfunction "1_1") (pintype "passive"))
      (node (ref "U8") (pin "54") (pinfunction "C3IN2-/RP70/RD6_54") (pintype "passive"))
    )
    (net (code "131") (name "Net-(U8-DPH{slash}RP66{slash}RD2)") (class "Default")
      (node (ref "TP19") (pin "1") (pinfunction "1_1") (pintype "passive"))
      (node (ref "U8") (pin "50") (pinfunction "DPH/RP66/RD2_50") (pintype "passive"))
    )
    (net (code "132") (name "Net-(U8-PMBE{slash}RP67{slash}RD3)") (class "Default")
      (node (ref "TP18") (pin "1") (pinfunction "1_1") (pintype "passive"))
      (node (ref "U8") (pin "51") (pinfunction "PMBE/RP67/RD3_51") (pintype "passive"))
    )
    (net (code "133") (name "Net-(U8-RTCC{slash}DMLN{slash}RPI72{slash}RD8)") (class "Default")
      (node (ref "TP23") (pin "1") (pinfunction "1_1") (pintype "passive"))
      (node (ref "U8") (pin "42") (pinfunction "RTCC/DMLN/RPI72/RD8_42") (pintype "passive"))
    )
    (net (code "134") (name "Net-(U8-SCL2{slash}PMA8{slash}RP101{slash}RF5)") (class "Default")
      (node (ref "TP30") (pin "1") (pinfunction "1_1") (pintype "passive"))
      (node (ref "U8") (pin "32") (pinfunction "SCL2/PMA8/RP101/RF5_32") (pintype "passive"))
    )
    (net (code "135") (name "Net-(U8-SDA2{slash}PMA9{slash}RP100{slash}RF4)") (class "Default")
      (node (ref "TP29") (pin "1") (pinfunction "1_1") (pintype "passive"))
      (node (ref "U8") (pin "31") (pinfunction "SDA2/PMA9/RP100/RF4_31") (pintype "passive"))
    )
    (net (code "136") (name "Net-(U8-TCK{slash}AN12{slash}PMA11{slash}RPI44{slash}RB12)") (class "Default")
      (node (ref "TP25") (pin "1") (pinfunction "1_1") (pintype "passive"))
      (node (ref "U8") (pin "27") (pinfunction "TCK/AN12/PMA11/RPI44/RB12_27") (pintype "passive"))
    )
    (net (code "137") (name "Net-(U8-TDI{slash}AN13{slash}PMA10{slash}RPI45{slash}RB13)") (class "Default")
      (node (ref "TP26") (pin "1") (pinfunction "1_1") (pintype "passive"))
      (node (ref "U8") (pin "28") (pinfunction "TDI/AN13/PMA10/RPI45/RB13_28") (pintype "passive"))
    )
    (net (code "138") (name "Net-(U8-TDO{slash}AN11{slash}PMA12{slash}RPI43{slash}RB11)") (class "Default")
      (node (ref "TP24") (pin "1") (pinfunction "1_1") (pintype "passive"))
      (node (ref "U8") (pin "24") (pinfunction "TDO/AN11/PMA12/RPI43/RB11_24") (pintype "passive"))
    )
    (net (code "139") (name "Net-(U8-USBID{slash}RP99{slash}RF3)") (class "Default")
      (node (ref "TP31") (pin "1") (pinfunction "1_1") (pintype "passive"))
      (node (ref "U8") (pin "33") (pinfunction "USBID/RP99/RF3_33") (pintype "passive"))
    )
    (net (code "140") (name "Net-(U22-ADJ)") (class "Default")
      (node (ref "R50") (pin "2") (pinfunction "2_2") (pintype "passive"))
      (node (ref "R51") (pin "1") (pinfunction "1_1") (pintype "passive"))
      (node (ref "U22") (pin "2") (pinfunction "ADJ_2") (pintype "passive"))
    )
    (net (code "141") (name "Net-(U23-ADJ)") (class "Default")
      (node (ref "R52") (pin "2") (pinfunction "2_2") (pintype "passive"))
      (node (ref "R55") (pin "1") (pinfunction "1_1") (pintype "passive"))
      (node (ref "U23") (pin "2") (pinfunction "ADJ_2") (pintype "passive"))
    )
    (net (code "142") (name "unconnected-(J2-Pad4)") (class "Default")
      (node (ref "J2") (pin "4") (pinfunction "4_4") (pintype "passive"))
    )
    (net (code "143") (name "unconnected-(U13-N.C.-Pad4)") (class "Default")
      (node (ref "U13") (pin "4") (pinfunction "N.C._4") (pintype "passive+no_connect"))
    )
    (net (code "144") (name "unconnected-(U13-N.C.-Pad5)") (class "Default")
      (node (ref "U13") (pin "5") (pinfunction "N.C._5") (pintype "passive+no_connect"))
    )
    (net (code "145") (name "unconnected-(U14-N.C.-Pad4)") (class "Default")
      (node (ref "U14") (pin "4") (pinfunction "N.C._4") (pintype "passive+no_connect"))
    )
    (net (code "146") (name "unconnected-(U15-NC-Pad2)") (class "Default")
      (node (ref "U15") (pin "2") (pinfunction "NC_2") (pintype "passive+no_connect"))
    )
    (net (code "147") (name "unconnected-(U15-NC-Pad3)") (class "Default")
      (node (ref "U15") (pin "3") (pinfunction "NC_3") (pintype "passive+no_connect"))
    )
    (net (code "148") (name "unconnected-(U15-NC-Pad4)") (class "Default")
      (node (ref "U15") (pin "4") (pinfunction "NC_4") (pintype "passive+no_connect"))
    )
    (net (code "149") (name "unconnected-(U22-NC-Pad3)") (class "Default")
      (node (ref "U22") (pin "3") (pinfunction "NC_3") (pintype "passive+no_connect"))
    )
    (net (code "150") (name "unconnected-(U22-NC-Pad4)") (class "Default")
      (node (ref "U22") (pin "4") (pinfunction "NC_4") (pintype "passive+no_connect"))
    )
    (net (code "151") (name "unconnected-(U23-NC-Pad3)") (class "Default")
      (node (ref "U23") (pin "3") (pinfunction "NC_3") (pintype "passive+no_connect"))
    )
    (net (code "152") (name "unconnected-(U23-NC-Pad4)") (class "Default")
      (node (ref "U23") (pin "4") (pinfunction "NC_4") (pintype "passive+no_connect"))
    )
  )
)
